# AutoPad-R3-RevA.net
KiCad netlist of a schematic drawn in EAGLE
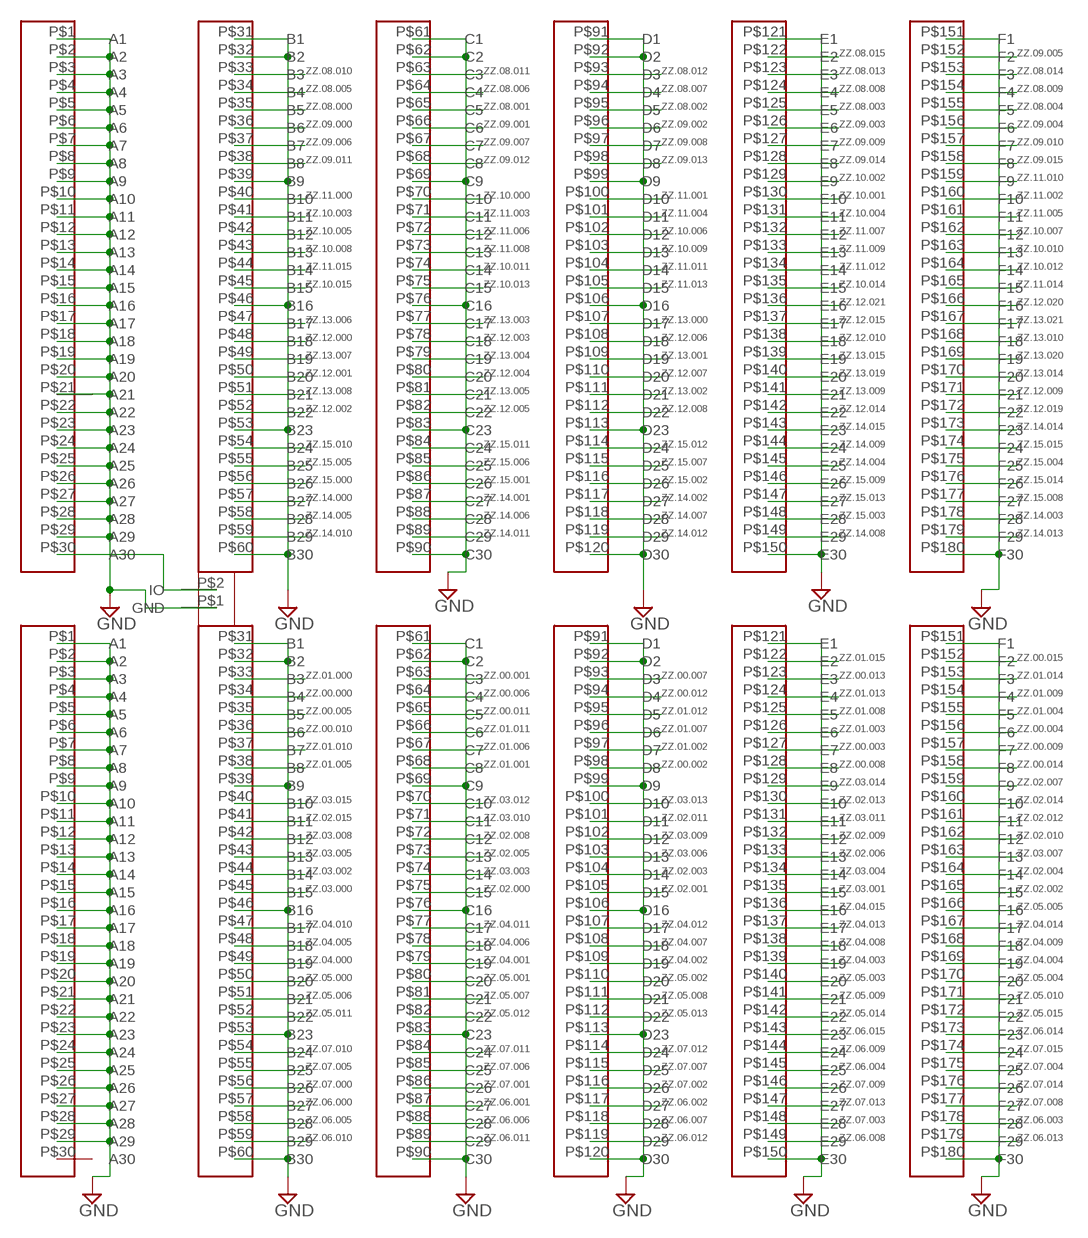
[diagram p0: schematic, sheet 1]
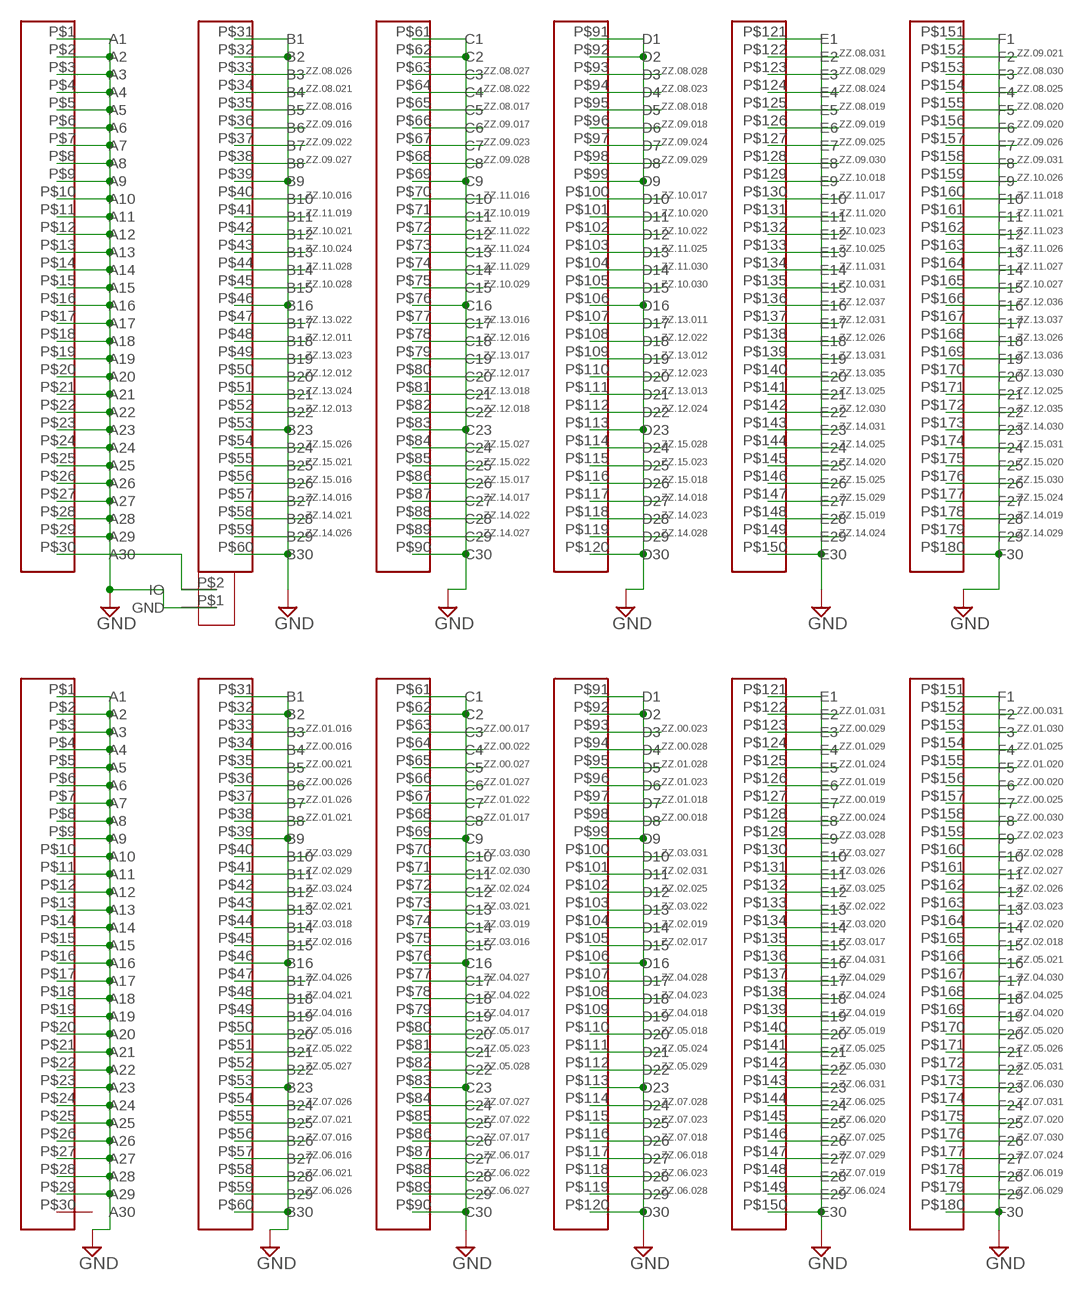
[diagram p1: schematic, sheet 2]
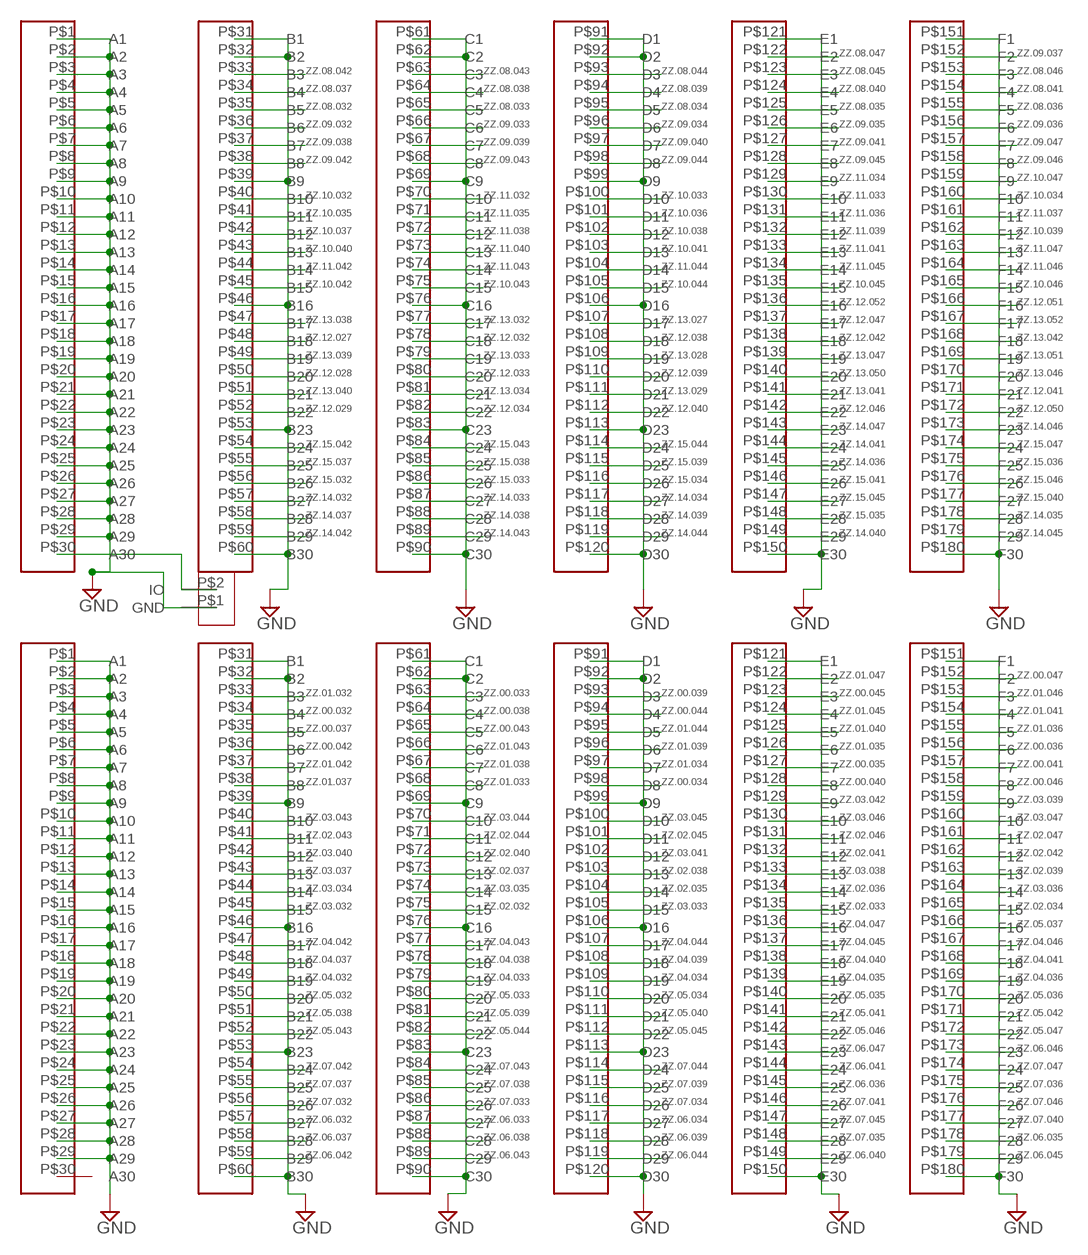
[diagram p2: schematic, sheet 3]
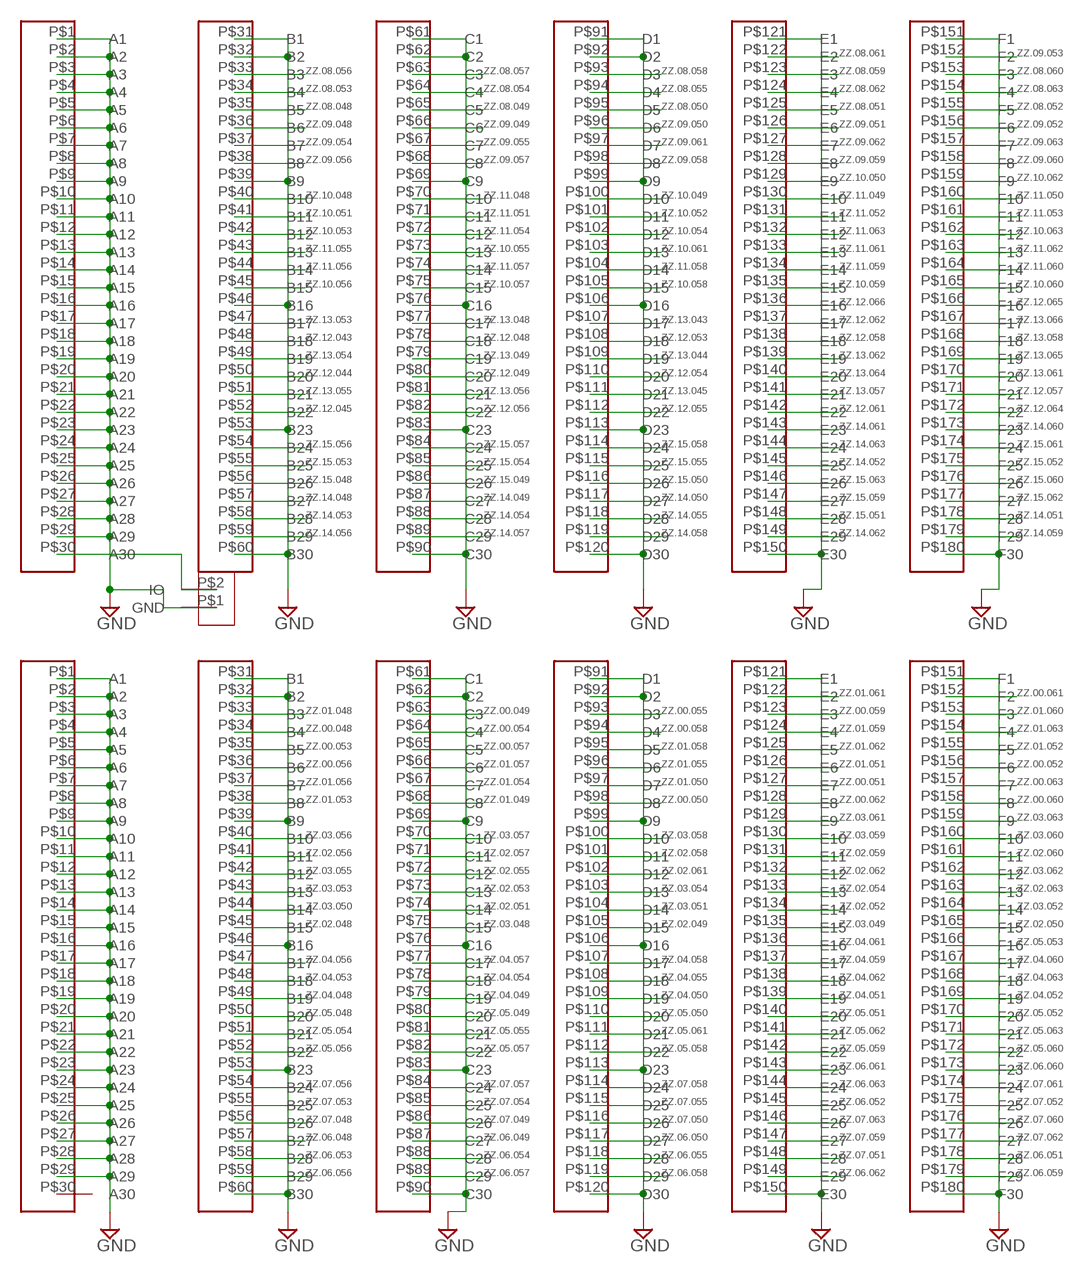
[diagram p3: schematic, sheet 4]
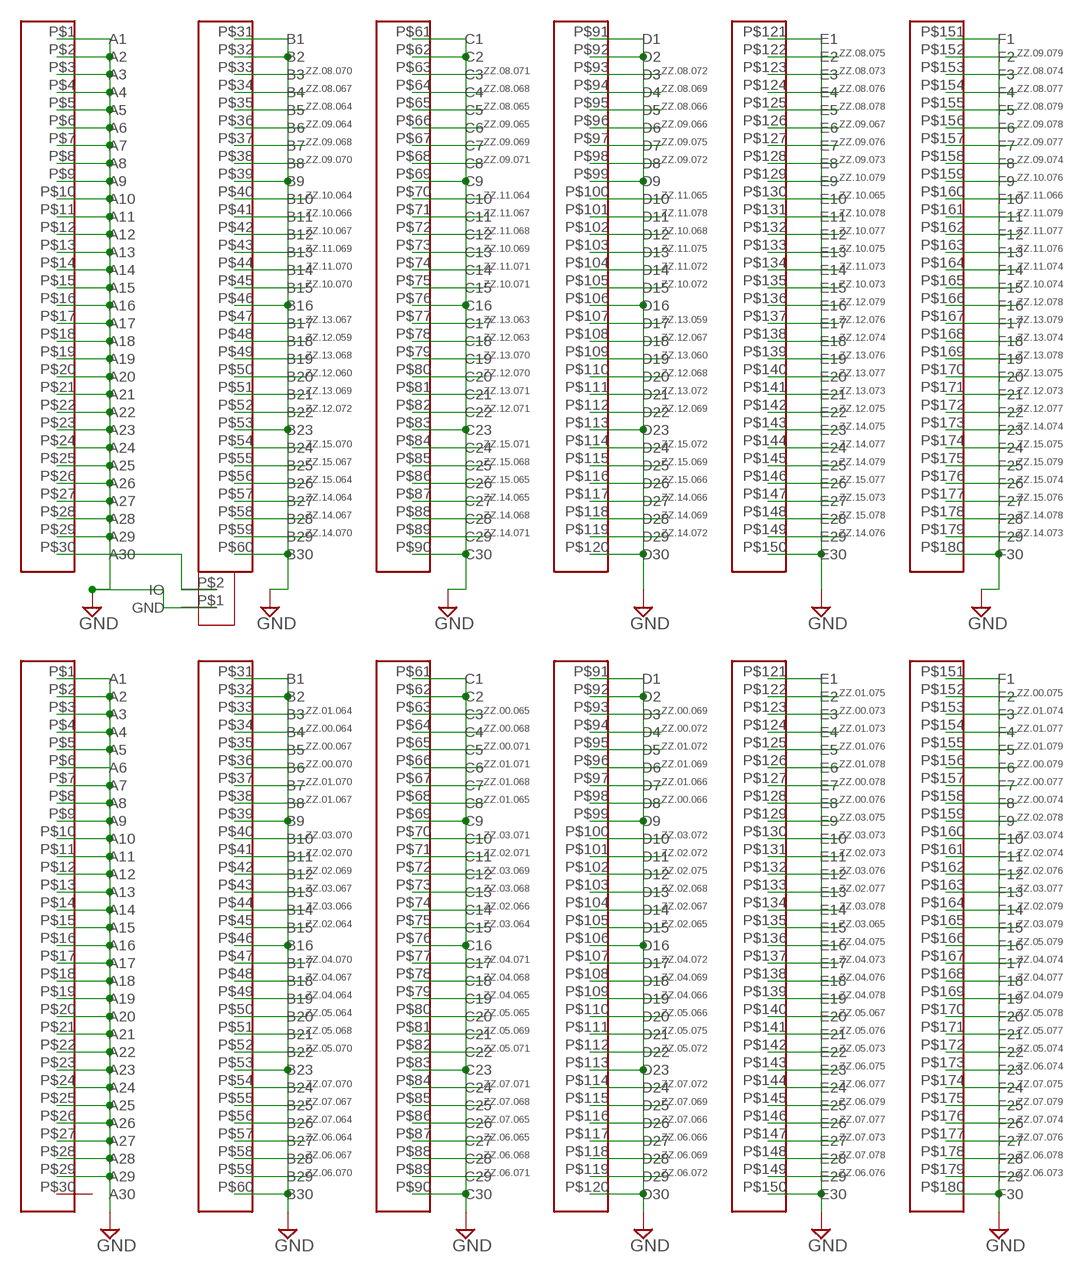
[diagram p4: schematic, sheet 5]
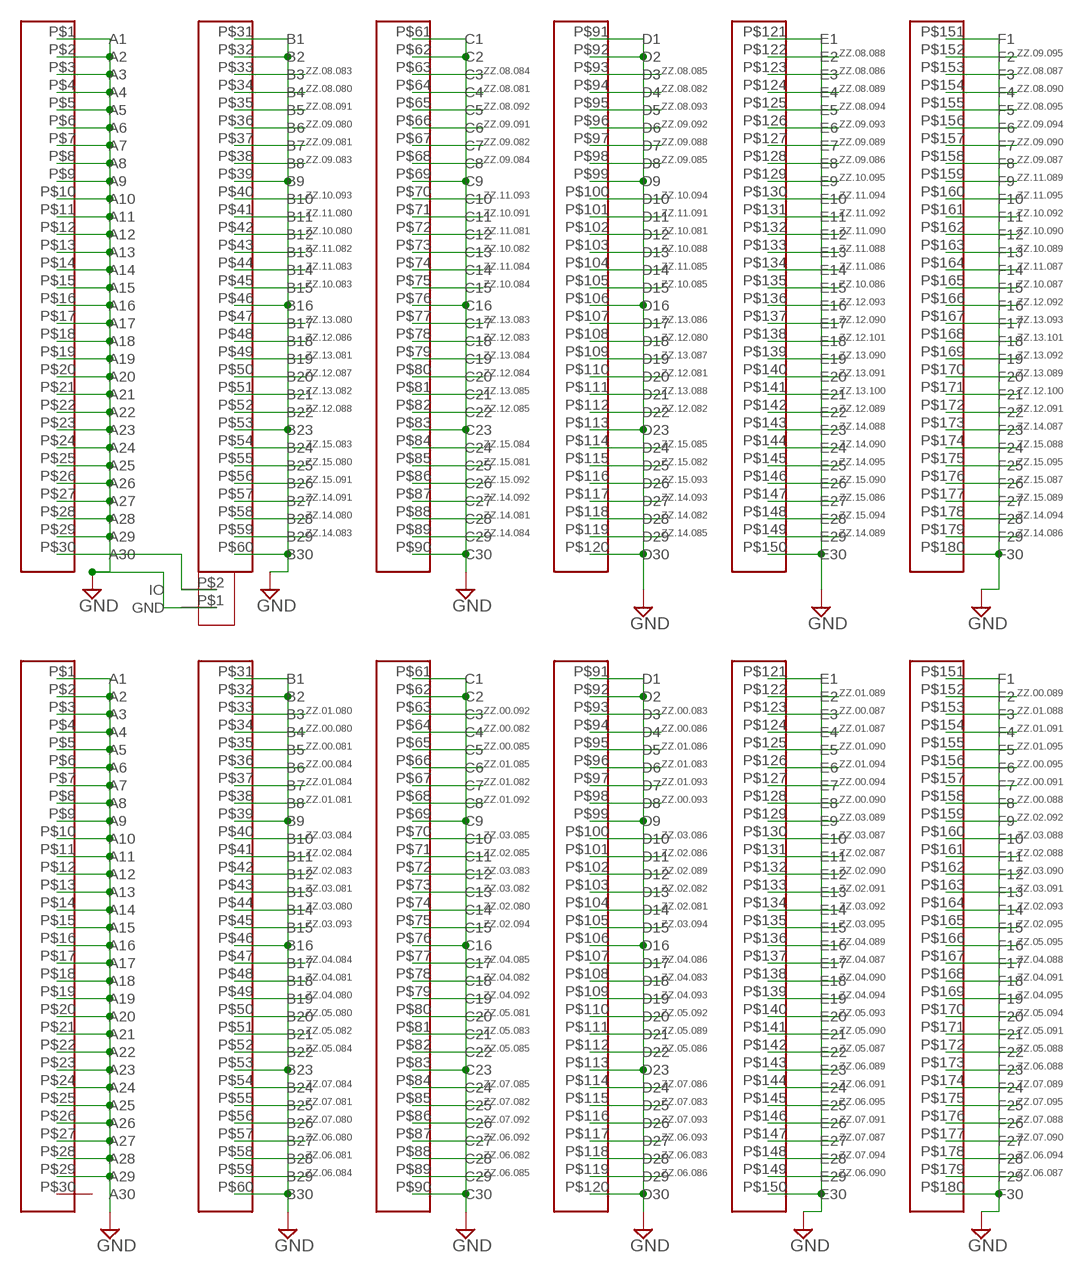
[diagram p5: schematic, sheet 6]
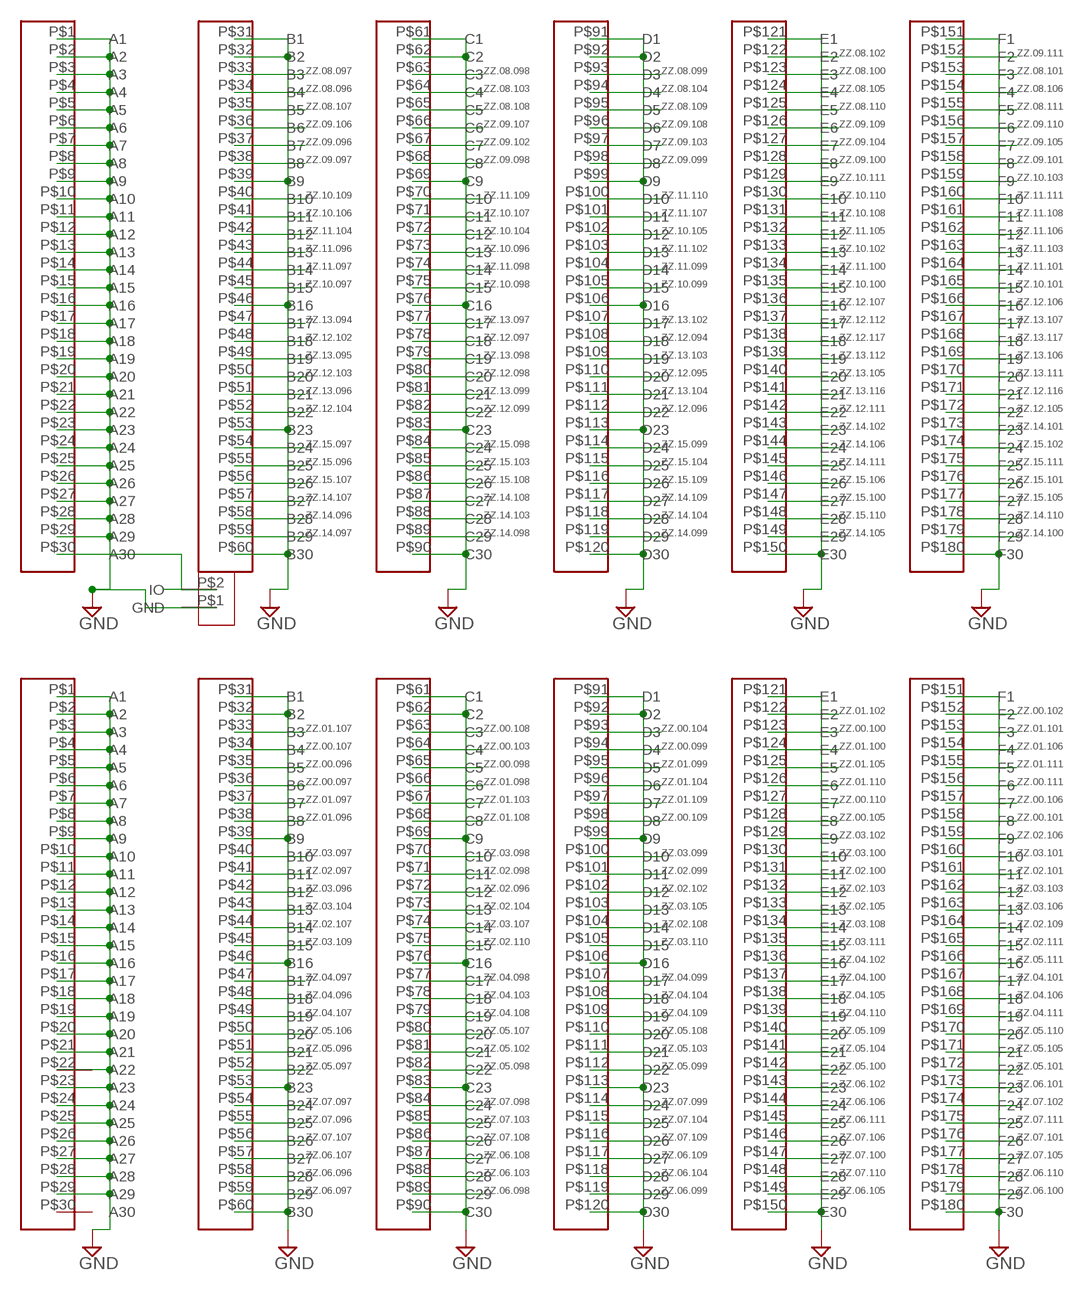
[diagram p6: schematic, sheet 7]
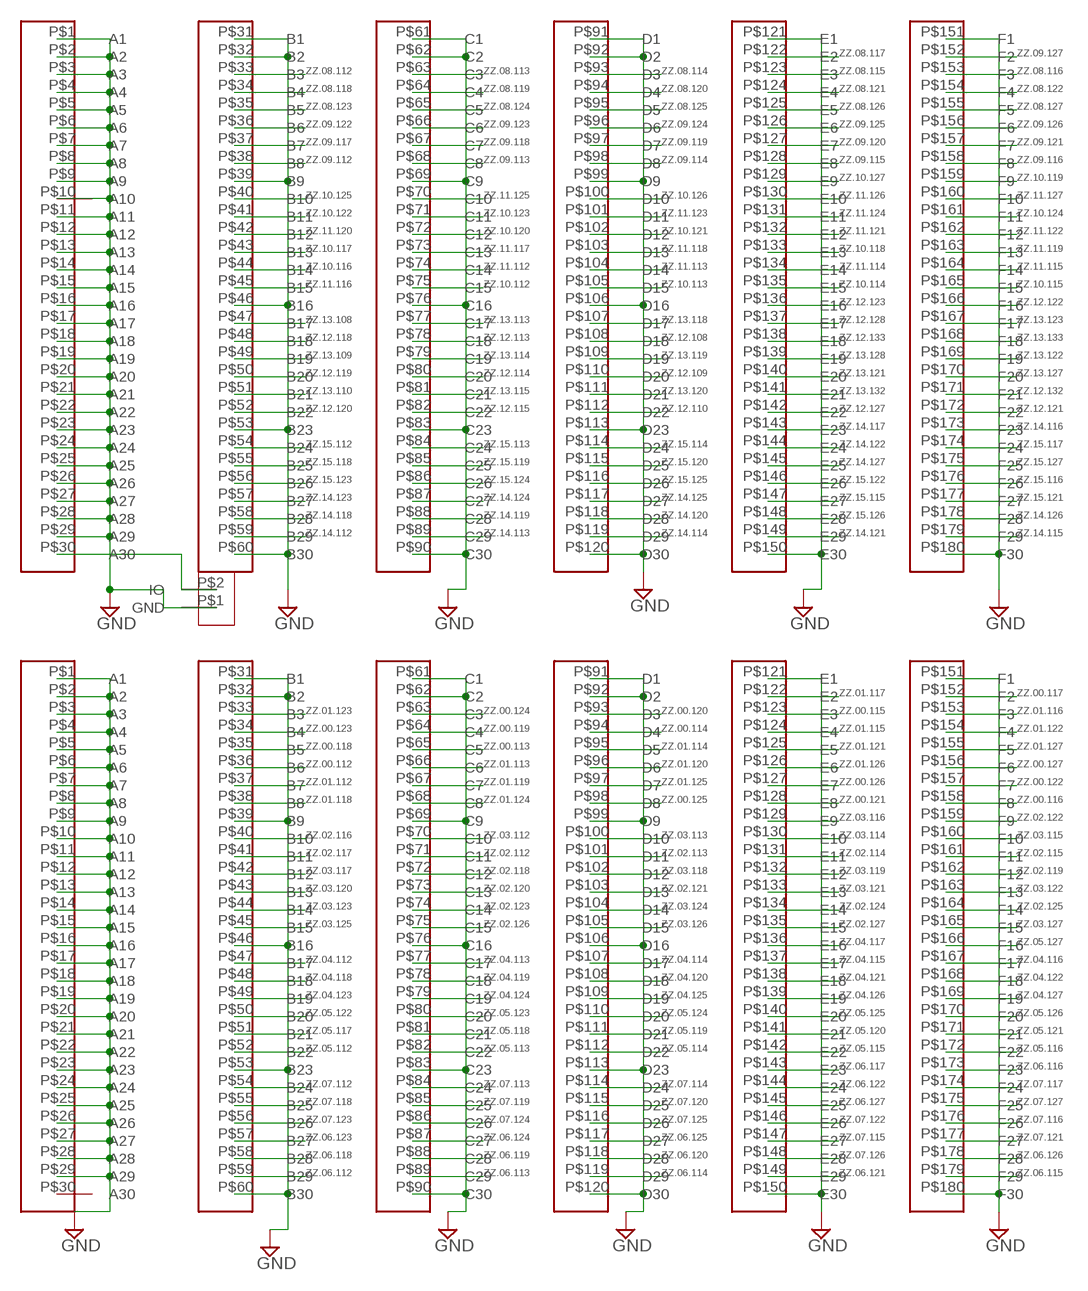
[diagram p7: schematic, sheet 8]
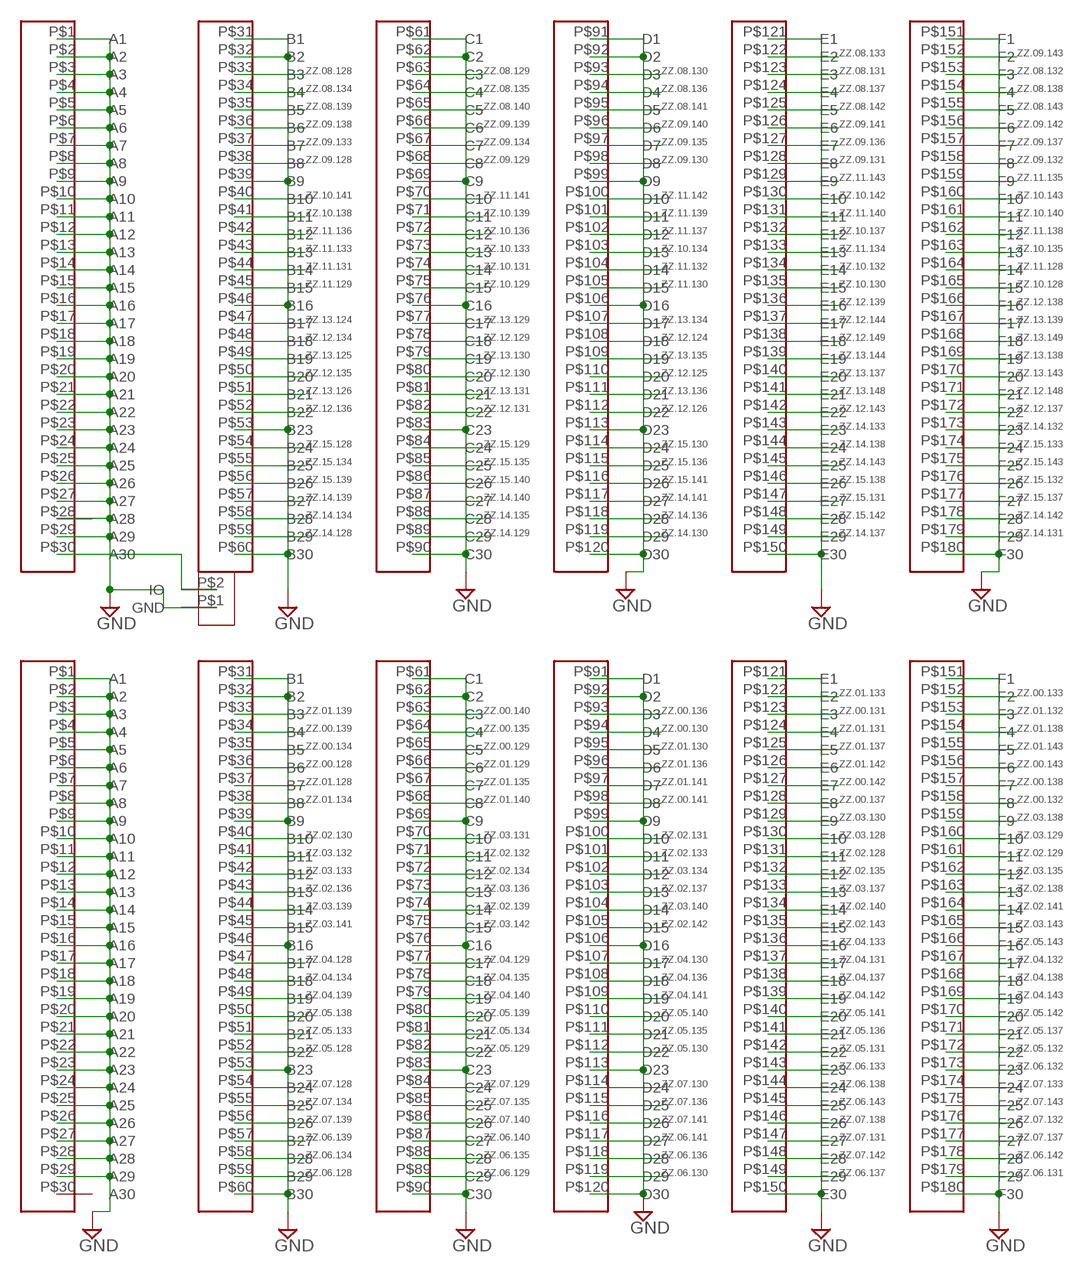
[diagram p8: schematic, sheet 9]
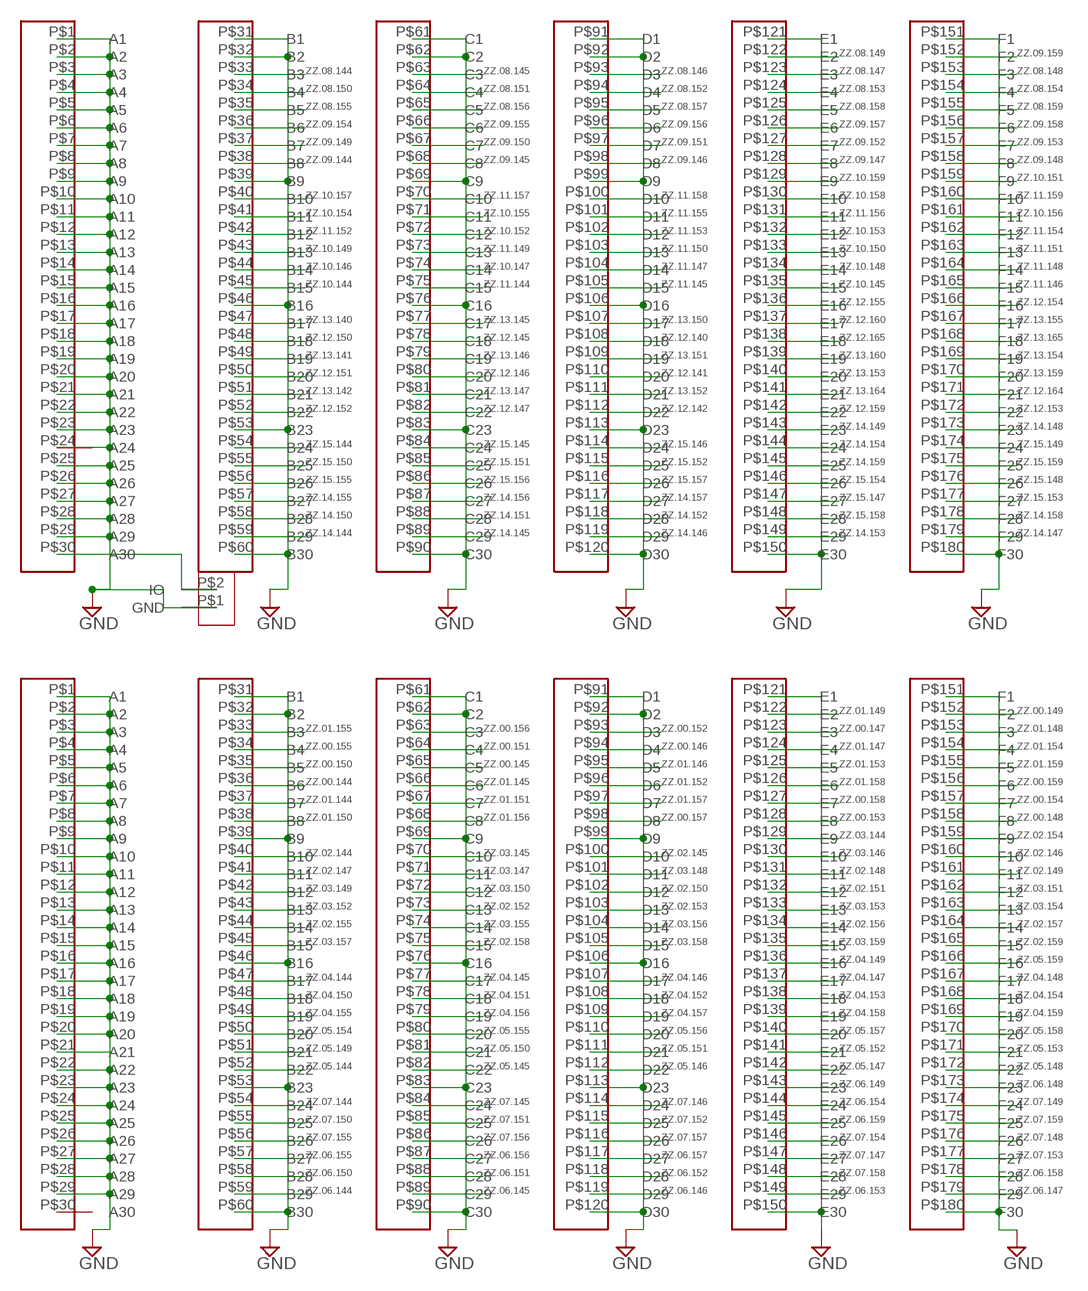
[diagram p9: schematic, sheet 10]
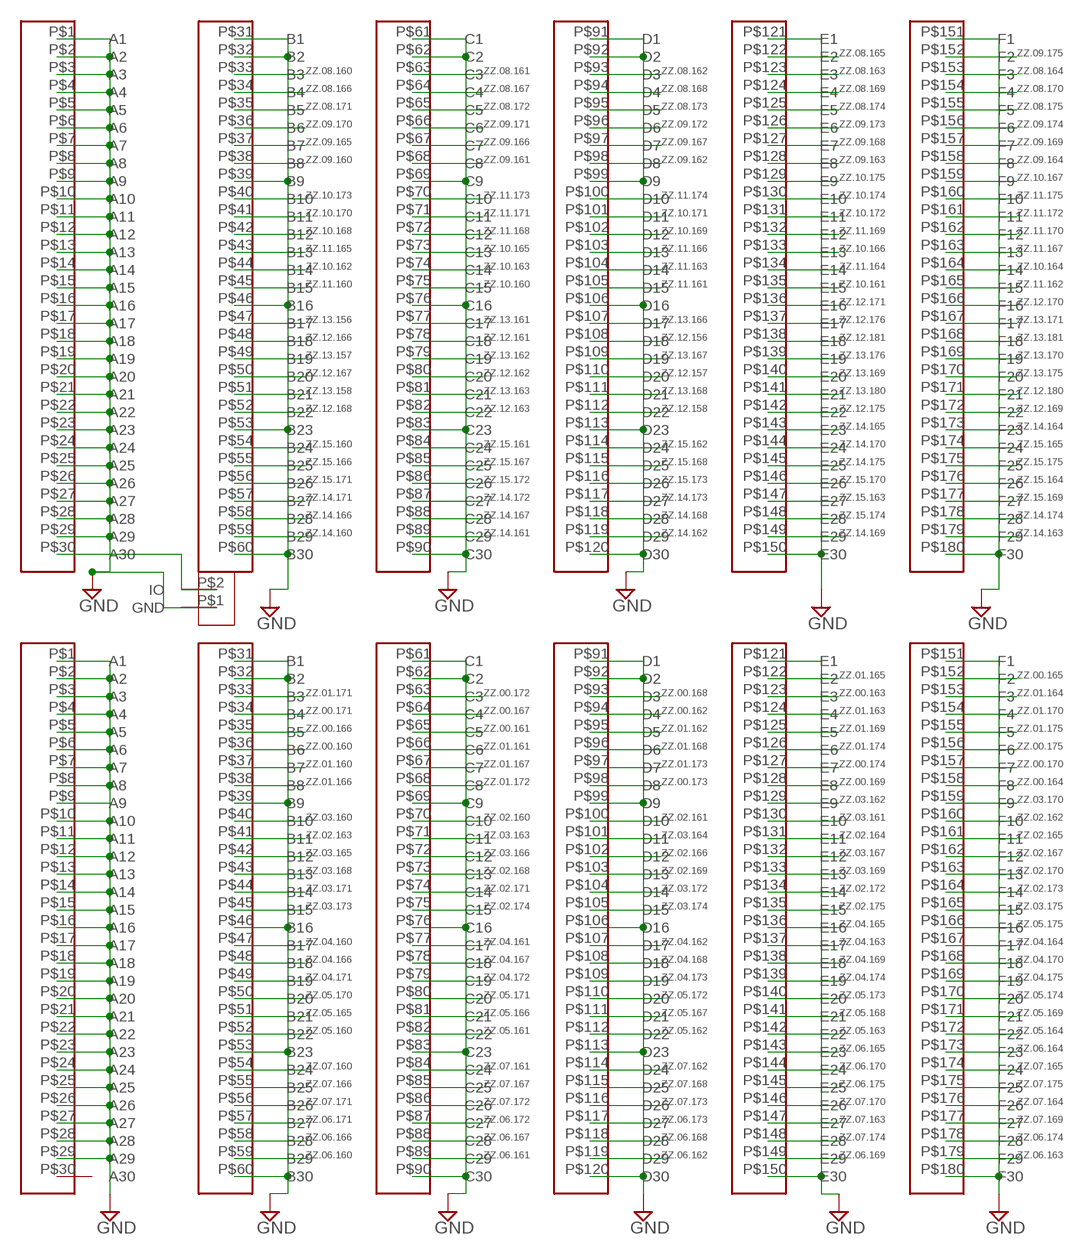
[diagram p10: schematic, sheet 11]
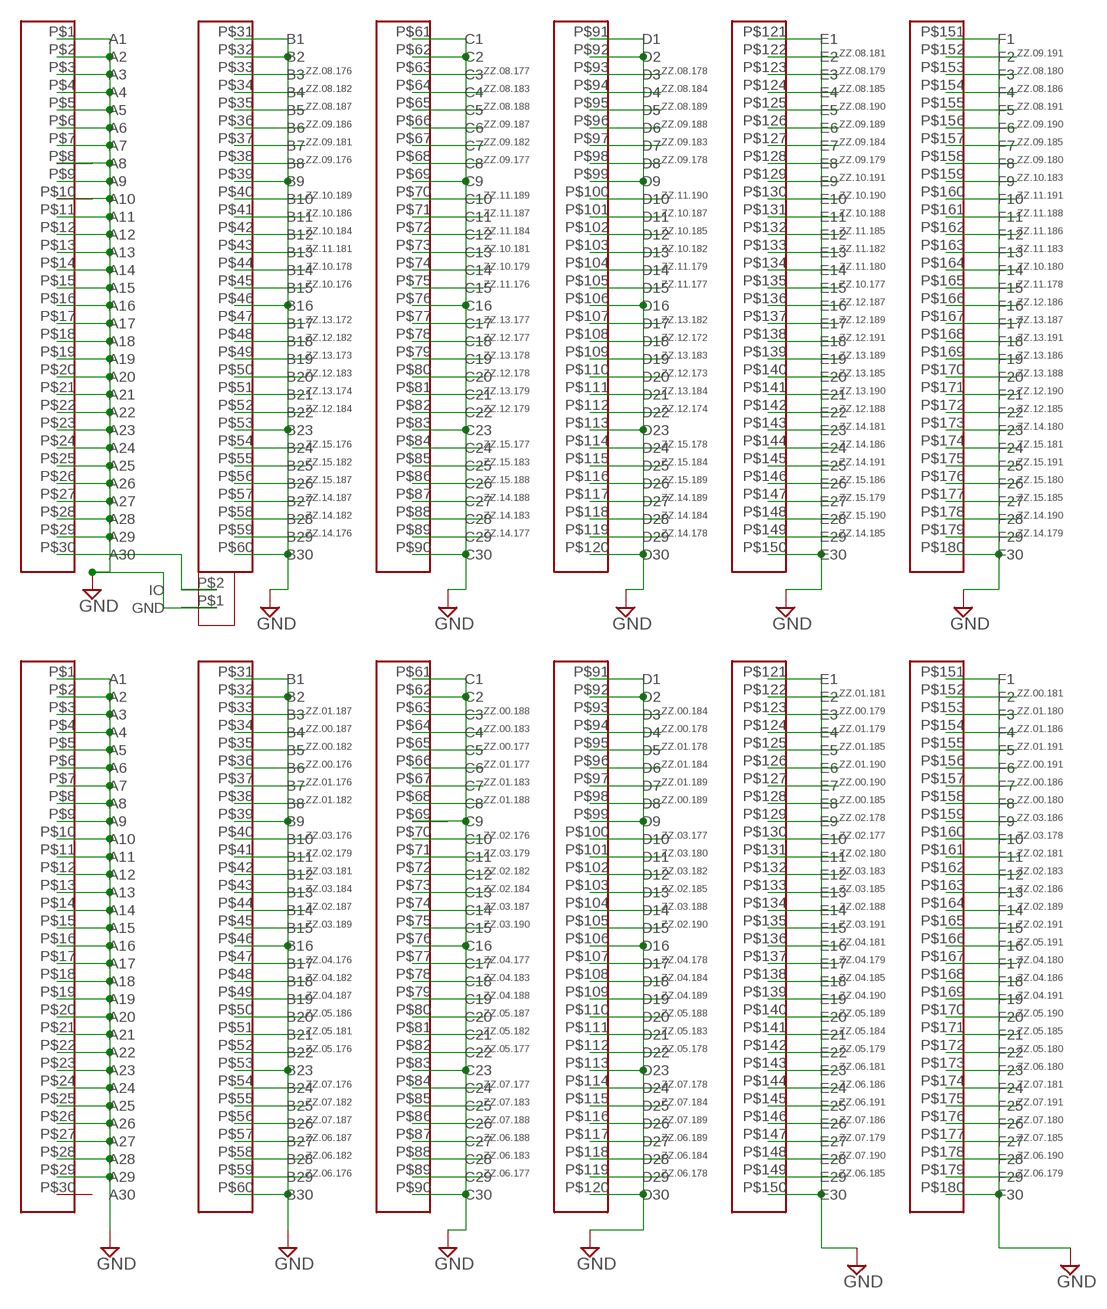
[diagram p11: schematic, sheet 12]

(export (version "E")
  (design (tool "Eeschema 10.0.6"))
  (components
    (comp (ref "U$5")
      (value "SEAM-30-02.0-L-06-1-A-K-TR")
      (footprint "eagle-import:SEAM-30-02.0-L-06-1-A-K-TR")
      (libsource (lib "eagle-import") (part "SEAM-30-02.0-L-06-1-A-K-TR"))
    )
    (comp (ref "U$6")
      (value "SEAM-30-02.0-L-06-1-A-K-TR")
      (footprint "eagle-import:SEAM-30-02.0-L-06-1-A-K-TR")
      (libsource (lib "eagle-import") (part "SEAM-30-02.0-L-06-1-A-K-TR"))
    )
    (comp (ref "U$27")
      (value "DS2431")
      (footprint "eagle-import:SD2431")
      (libsource (lib "eagle-import") (part "DS2431"))
    )
    (comp (ref "U$9")
      (value "SEAM-30-02.0-L-06-1-A-K-TR")
      (footprint "eagle-import:SEAM-30-02.0-L-06-1-A-K-TR")
      (libsource (lib "eagle-import") (part "SEAM-30-02.0-L-06-1-A-K-TR"))
    )
    (comp (ref "U$10")
      (value "SEAM-30-02.0-L-06-1-A-K-TR")
      (footprint "eagle-import:SEAM-30-02.0-L-06-1-A-K-TR")
      (libsource (lib "eagle-import") (part "SEAM-30-02.0-L-06-1-A-K-TR"))
    )
    (comp (ref "U$29")
      (value "DS2431")
      (footprint "eagle-import:SD2431")
      (libsource (lib "eagle-import") (part "DS2431"))
    )
    (comp (ref "U$13")
      (value "SEAM-30-02.0-L-06-1-A-K-TR")
      (footprint "eagle-import:SEAM-30-02.0-L-06-1-A-K-TR")
      (libsource (lib "eagle-import") (part "SEAM-30-02.0-L-06-1-A-K-TR"))
    )
    (comp (ref "U$14")
      (value "SEAM-30-02.0-L-06-1-A-K-TR")
      (footprint "eagle-import:SEAM-30-02.0-L-06-1-A-K-TR")
      (libsource (lib "eagle-import") (part "SEAM-30-02.0-L-06-1-A-K-TR"))
    )
    (comp (ref "U$31")
      (value "DS2431")
      (footprint "eagle-import:SD2431")
      (libsource (lib "eagle-import") (part "DS2431"))
    )
    (comp (ref "U$3")
      (value "SEAM-30-02.0-L-06-1-A-K-TR")
      (footprint "eagle-import:SEAM-30-02.0-L-06-1-A-K-TR")
      (libsource (lib "eagle-import") (part "SEAM-30-02.0-L-06-1-A-K-TR"))
    )
    (comp (ref "U$4")
      (value "SEAM-30-02.0-L-06-1-A-K-TR")
      (footprint "eagle-import:SEAM-30-02.0-L-06-1-A-K-TR")
      (libsource (lib "eagle-import") (part "SEAM-30-02.0-L-06-1-A-K-TR"))
    )
    (comp (ref "U$26")
      (value "DS2431")
      (footprint "eagle-import:SD2431")
      (libsource (lib "eagle-import") (part "DS2431"))
    )
    (comp (ref "U$21")
      (value "SEAM-30-02.0-L-06-1-A-K-TR")
      (footprint "eagle-import:SEAM-30-02.0-L-06-1-A-K-TR")
      (libsource (lib "eagle-import") (part "SEAM-30-02.0-L-06-1-A-K-TR"))
    )
    (comp (ref "U$22")
      (value "SEAM-30-02.0-L-06-1-A-K-TR")
      (footprint "eagle-import:SEAM-30-02.0-L-06-1-A-K-TR")
      (libsource (lib "eagle-import") (part "SEAM-30-02.0-L-06-1-A-K-TR"))
    )
    (comp (ref "U$35")
      (value "DS2431")
      (footprint "eagle-import:SD2431")
      (libsource (lib "eagle-import") (part "DS2431"))
    )
    (comp (ref "U$17")
      (value "SEAM-30-02.0-L-06-1-A-K-TR")
      (footprint "eagle-import:SEAM-30-02.0-L-06-1-A-K-TR")
      (libsource (lib "eagle-import") (part "SEAM-30-02.0-L-06-1-A-K-TR"))
    )
    (comp (ref "U$18")
      (value "SEAM-30-02.0-L-06-1-A-K-TR")
      (footprint "eagle-import:SEAM-30-02.0-L-06-1-A-K-TR")
      (libsource (lib "eagle-import") (part "SEAM-30-02.0-L-06-1-A-K-TR"))
    )
    (comp (ref "U$33")
      (value "DS2431")
      (footprint "eagle-import:SD2431")
      (libsource (lib "eagle-import") (part "DS2431"))
    )
    (comp (ref "U$1")
      (value "SEAM-30-02.0-L-06-1-A-K-TR")
      (footprint "eagle-import:SEAM-30-02.0-L-06-1-A-K-TR")
      (libsource (lib "eagle-import") (part "SEAM-30-02.0-L-06-1-A-K-TR"))
    )
    (comp (ref "U$2")
      (value "SEAM-30-02.0-L-06-1-A-K-TR")
      (footprint "eagle-import:SEAM-30-02.0-L-06-1-A-K-TR")
      (libsource (lib "eagle-import") (part "SEAM-30-02.0-L-06-1-A-K-TR"))
    )
    (comp (ref "U$25")
      (value "DS2431")
      (footprint "eagle-import:SD2431")
      (libsource (lib "eagle-import") (part "DS2431"))
    )
    (comp (ref "U$19")
      (value "SEAM-30-02.0-L-06-1-A-K-TR")
      (footprint "eagle-import:SEAM-30-02.0-L-06-1-A-K-TR")
      (libsource (lib "eagle-import") (part "SEAM-30-02.0-L-06-1-A-K-TR"))
    )
    (comp (ref "U$20")
      (value "SEAM-30-02.0-L-06-1-A-K-TR")
      (footprint "eagle-import:SEAM-30-02.0-L-06-1-A-K-TR")
      (libsource (lib "eagle-import") (part "SEAM-30-02.0-L-06-1-A-K-TR"))
    )
    (comp (ref "U$34")
      (value "DS2431")
      (footprint "eagle-import:SD2431")
      (libsource (lib "eagle-import") (part "DS2431"))
    )
    (comp (ref "U$23")
      (value "SEAM-30-02.0-L-06-1-A-K-TR")
      (footprint "eagle-import:SEAM-30-02.0-L-06-1-A-K-TR")
      (libsource (lib "eagle-import") (part "SEAM-30-02.0-L-06-1-A-K-TR"))
    )
    (comp (ref "U$24")
      (value "SEAM-30-02.0-L-06-1-A-K-TR")
      (footprint "eagle-import:SEAM-30-02.0-L-06-1-A-K-TR")
      (libsource (lib "eagle-import") (part "SEAM-30-02.0-L-06-1-A-K-TR"))
    )
    (comp (ref "U$36")
      (value "DS2431")
      (footprint "eagle-import:SD2431")
      (libsource (lib "eagle-import") (part "DS2431"))
    )
    (comp (ref "U$11")
      (value "SEAM-30-02.0-L-06-1-A-K-TR")
      (footprint "eagle-import:SEAM-30-02.0-L-06-1-A-K-TR")
      (libsource (lib "eagle-import") (part "SEAM-30-02.0-L-06-1-A-K-TR"))
    )
    (comp (ref "U$12")
      (value "SEAM-30-02.0-L-06-1-A-K-TR")
      (footprint "eagle-import:SEAM-30-02.0-L-06-1-A-K-TR")
      (libsource (lib "eagle-import") (part "SEAM-30-02.0-L-06-1-A-K-TR"))
    )
    (comp (ref "U$30")
      (value "DS2431")
      (footprint "eagle-import:SD2431")
      (libsource (lib "eagle-import") (part "DS2431"))
    )
    (comp (ref "U$15")
      (value "SEAM-30-02.0-L-06-1-A-K-TR")
      (footprint "eagle-import:SEAM-30-02.0-L-06-1-A-K-TR")
      (libsource (lib "eagle-import") (part "SEAM-30-02.0-L-06-1-A-K-TR"))
    )
    (comp (ref "U$16")
      (value "SEAM-30-02.0-L-06-1-A-K-TR")
      (footprint "eagle-import:SEAM-30-02.0-L-06-1-A-K-TR")
      (libsource (lib "eagle-import") (part "SEAM-30-02.0-L-06-1-A-K-TR"))
    )
    (comp (ref "U$32")
      (value "DS2431")
      (footprint "eagle-import:SD2431")
      (libsource (lib "eagle-import") (part "DS2431"))
    )
    (comp (ref "U$7")
      (value "SEAM-30-02.0-L-06-1-A-K-TR")
      (footprint "eagle-import:SEAM-30-02.0-L-06-1-A-K-TR")
      (libsource (lib "eagle-import") (part "SEAM-30-02.0-L-06-1-A-K-TR"))
    )
    (comp (ref "U$8")
      (value "SEAM-30-02.0-L-06-1-A-K-TR")
      (footprint "eagle-import:SEAM-30-02.0-L-06-1-A-K-TR")
      (libsource (lib "eagle-import") (part "SEAM-30-02.0-L-06-1-A-K-TR"))
    )
    (comp (ref "U$28")
      (value "DS2431")
      (footprint "eagle-import:SD2431")
      (libsource (lib "eagle-import") (part "DS2431"))
    )
  )
  (nets
    (net (code "1") (name "GND") (class "Default")
      (node (ref "U$1") (pin "P$1") (pinfunction "A1_P$1") (pintype "bidirectional"))
      (node (ref "U$1") (pin "P$10") (pinfunction "A10_P$10") (pintype "bidirectional"))
      (node (ref "U$1") (pin "P$106") (pinfunction "D16_P$106") (pintype "bidirectional"))
      (node (ref "U$1") (pin "P$11") (pinfunction "A11_P$11") (pintype "bidirectional"))
      (node (ref "U$1") (pin "P$113") (pinfunction "D23_P$113") (pintype "bidirectional"))
      (node (ref "U$1") (pin "P$12") (pinfunction "A12_P$12") (pintype "bidirectional"))
      (node (ref "U$1") (pin "P$120") (pinfunction "D30_P$120") (pintype "bidirectional"))
      (node (ref "U$1") (pin "P$121") (pinfunction "E1_P$121") (pintype "bidirectional"))
      (node (ref "U$1") (pin "P$13") (pinfunction "A13_P$13") (pintype "bidirectional"))
      (node (ref "U$1") (pin "P$14") (pinfunction "A14_P$14") (pintype "bidirectional"))
      (node (ref "U$1") (pin "P$15") (pinfunction "A15_P$15") (pintype "bidirectional"))
      (node (ref "U$1") (pin "P$150") (pinfunction "E30_P$150") (pintype "bidirectional"))
      (node (ref "U$1") (pin "P$151") (pinfunction "F1_P$151") (pintype "bidirectional"))
      (node (ref "U$1") (pin "P$16") (pinfunction "A16_P$16") (pintype "bidirectional"))
      (node (ref "U$1") (pin "P$17") (pinfunction "A17_P$17") (pintype "bidirectional"))
      (node (ref "U$1") (pin "P$18") (pinfunction "A18_P$18") (pintype "bidirectional"))
      (node (ref "U$1") (pin "P$180") (pinfunction "F30_P$180") (pintype "bidirectional"))
      (node (ref "U$1") (pin "P$19") (pinfunction "A19_P$19") (pintype "bidirectional"))
      (node (ref "U$1") (pin "P$2") (pinfunction "A2_P$2") (pintype "bidirectional"))
      (node (ref "U$1") (pin "P$20") (pinfunction "A20_P$20") (pintype "bidirectional"))
      (node (ref "U$1") (pin "P$21") (pinfunction "A21_P$21") (pintype "bidirectional"))
      (node (ref "U$1") (pin "P$22") (pinfunction "A22_P$22") (pintype "bidirectional"))
      (node (ref "U$1") (pin "P$23") (pinfunction "A23_P$23") (pintype "bidirectional"))
      (node (ref "U$1") (pin "P$24") (pinfunction "A24_P$24") (pintype "bidirectional"))
      (node (ref "U$1") (pin "P$25") (pinfunction "A25_P$25") (pintype "bidirectional"))
      (node (ref "U$1") (pin "P$26") (pinfunction "A26_P$26") (pintype "bidirectional"))
      (node (ref "U$1") (pin "P$27") (pinfunction "A27_P$27") (pintype "bidirectional"))
      (node (ref "U$1") (pin "P$28") (pinfunction "A28_P$28") (pintype "bidirectional"))
      (node (ref "U$1") (pin "P$29") (pinfunction "A29_P$29") (pintype "bidirectional"))
      (node (ref "U$1") (pin "P$3") (pinfunction "A3_P$3") (pintype "bidirectional"))
      (node (ref "U$1") (pin "P$31") (pinfunction "B1_P$31") (pintype "bidirectional"))
      (node (ref "U$1") (pin "P$32") (pinfunction "B2_P$32") (pintype "bidirectional"))
      (node (ref "U$1") (pin "P$39") (pinfunction "B9_P$39") (pintype "bidirectional"))
      (node (ref "U$1") (pin "P$4") (pinfunction "A4_P$4") (pintype "bidirectional"))
      (node (ref "U$1") (pin "P$46") (pinfunction "B16_P$46") (pintype "bidirectional"))
      (node (ref "U$1") (pin "P$5") (pinfunction "A5_P$5") (pintype "bidirectional"))
      (node (ref "U$1") (pin "P$53") (pinfunction "B23_P$53") (pintype "bidirectional"))
      (node (ref "U$1") (pin "P$6") (pinfunction "A6_P$6") (pintype "bidirectional"))
      (node (ref "U$1") (pin "P$60") (pinfunction "B30_P$60") (pintype "bidirectional"))
      (node (ref "U$1") (pin "P$61") (pinfunction "C1_P$61") (pintype "bidirectional"))
      (node (ref "U$1") (pin "P$62") (pinfunction "C2_P$62") (pintype "bidirectional"))
      (node (ref "U$1") (pin "P$69") (pinfunction "C9_P$69") (pintype "bidirectional"))
      (node (ref "U$1") (pin "P$7") (pinfunction "A7_P$7") (pintype "bidirectional"))
      (node (ref "U$1") (pin "P$76") (pinfunction "C16_P$76") (pintype "bidirectional"))
      (node (ref "U$1") (pin "P$8") (pinfunction "A8_P$8") (pintype "bidirectional"))
      (node (ref "U$1") (pin "P$83") (pinfunction "C23_P$83") (pintype "bidirectional"))
      (node (ref "U$1") (pin "P$9") (pinfunction "A9_P$9") (pintype "bidirectional"))
      (node (ref "U$1") (pin "P$90") (pinfunction "C30_P$90") (pintype "bidirectional"))
      (node (ref "U$1") (pin "P$91") (pinfunction "D1_P$91") (pintype "bidirectional"))
      (node (ref "U$1") (pin "P$92") (pinfunction "D2_P$92") (pintype "bidirectional"))
      (node (ref "U$1") (pin "P$99") (pinfunction "D9_P$99") (pintype "bidirectional"))
      (node (ref "U$10") (pin "P$1") (pinfunction "A1_P$1") (pintype "bidirectional"))
      (node (ref "U$10") (pin "P$10") (pinfunction "A10_P$10") (pintype "bidirectional"))
      (node (ref "U$10") (pin "P$106") (pinfunction "D16_P$106") (pintype "bidirectional"))
      (node (ref "U$10") (pin "P$11") (pinfunction "A11_P$11") (pintype "bidirectional"))
      (node (ref "U$10") (pin "P$113") (pinfunction "D23_P$113") (pintype "bidirectional"))
      (node (ref "U$10") (pin "P$12") (pinfunction "A12_P$12") (pintype "bidirectional"))
      (node (ref "U$10") (pin "P$120") (pinfunction "D30_P$120") (pintype "bidirectional"))
      (node (ref "U$10") (pin "P$121") (pinfunction "E1_P$121") (pintype "bidirectional"))
      (node (ref "U$10") (pin "P$13") (pinfunction "A13_P$13") (pintype "bidirectional"))
      (node (ref "U$10") (pin "P$14") (pinfunction "A14_P$14") (pintype "bidirectional"))
      (node (ref "U$10") (pin "P$15") (pinfunction "A15_P$15") (pintype "bidirectional"))
      (node (ref "U$10") (pin "P$150") (pinfunction "E30_P$150") (pintype "bidirectional"))
      (node (ref "U$10") (pin "P$151") (pinfunction "F1_P$151") (pintype "bidirectional"))
      (node (ref "U$10") (pin "P$16") (pinfunction "A16_P$16") (pintype "bidirectional"))
      (node (ref "U$10") (pin "P$17") (pinfunction "A17_P$17") (pintype "bidirectional"))
      (node (ref "U$10") (pin "P$18") (pinfunction "A18_P$18") (pintype "bidirectional"))
      (node (ref "U$10") (pin "P$180") (pinfunction "F30_P$180") (pintype "bidirectional"))
      (node (ref "U$10") (pin "P$19") (pinfunction "A19_P$19") (pintype "bidirectional"))
      (node (ref "U$10") (pin "P$2") (pinfunction "A2_P$2") (pintype "bidirectional"))
      (node (ref "U$10") (pin "P$20") (pinfunction "A20_P$20") (pintype "bidirectional"))
      (node (ref "U$10") (pin "P$21") (pinfunction "A21_P$21") (pintype "bidirectional"))
      (node (ref "U$10") (pin "P$22") (pinfunction "A22_P$22") (pintype "bidirectional"))
      (node (ref "U$10") (pin "P$23") (pinfunction "A23_P$23") (pintype "bidirectional"))
      (node (ref "U$10") (pin "P$24") (pinfunction "A24_P$24") (pintype "bidirectional"))
      (node (ref "U$10") (pin "P$25") (pinfunction "A25_P$25") (pintype "bidirectional"))
      (node (ref "U$10") (pin "P$26") (pinfunction "A26_P$26") (pintype "bidirectional"))
      (node (ref "U$10") (pin "P$27") (pinfunction "A27_P$27") (pintype "bidirectional"))
      (node (ref "U$10") (pin "P$28") (pinfunction "A28_P$28") (pintype "bidirectional"))
      (node (ref "U$10") (pin "P$29") (pinfunction "A29_P$29") (pintype "bidirectional"))
      (node (ref "U$10") (pin "P$3") (pinfunction "A3_P$3") (pintype "bidirectional"))
      (node (ref "U$10") (pin "P$31") (pinfunction "B1_P$31") (pintype "bidirectional"))
      (node (ref "U$10") (pin "P$32") (pinfunction "B2_P$32") (pintype "bidirectional"))
      (node (ref "U$10") (pin "P$39") (pinfunction "B9_P$39") (pintype "bidirectional"))
      (node (ref "U$10") (pin "P$4") (pinfunction "A4_P$4") (pintype "bidirectional"))
      (node (ref "U$10") (pin "P$46") (pinfunction "B16_P$46") (pintype "bidirectional"))
      (node (ref "U$10") (pin "P$5") (pinfunction "A5_P$5") (pintype "bidirectional"))
      (node (ref "U$10") (pin "P$53") (pinfunction "B23_P$53") (pintype "bidirectional"))
      (node (ref "U$10") (pin "P$6") (pinfunction "A6_P$6") (pintype "bidirectional"))
      (node (ref "U$10") (pin "P$60") (pinfunction "B30_P$60") (pintype "bidirectional"))
      (node (ref "U$10") (pin "P$61") (pinfunction "C1_P$61") (pintype "bidirectional"))
      (node (ref "U$10") (pin "P$62") (pinfunction "C2_P$62") (pintype "bidirectional"))
      (node (ref "U$10") (pin "P$69") (pinfunction "C9_P$69") (pintype "bidirectional"))
      (node (ref "U$10") (pin "P$7") (pinfunction "A7_P$7") (pintype "bidirectional"))
      (node (ref "U$10") (pin "P$76") (pinfunction "C16_P$76") (pintype "bidirectional"))
      (node (ref "U$10") (pin "P$8") (pinfunction "A8_P$8") (pintype "bidirectional"))
      (node (ref "U$10") (pin "P$83") (pinfunction "C23_P$83") (pintype "bidirectional"))
      (node (ref "U$10") (pin "P$9") (pinfunction "A9_P$9") (pintype "bidirectional"))
      (node (ref "U$10") (pin "P$90") (pinfunction "C30_P$90") (pintype "bidirectional"))
      (node (ref "U$10") (pin "P$91") (pinfunction "D1_P$91") (pintype "bidirectional"))
      (node (ref "U$10") (pin "P$92") (pinfunction "D2_P$92") (pintype "bidirectional"))
      (node (ref "U$10") (pin "P$99") (pinfunction "D9_P$99") (pintype "bidirectional"))
      (node (ref "U$11") (pin "P$1") (pinfunction "A1_P$1") (pintype "bidirectional"))
      (node (ref "U$11") (pin "P$10") (pinfunction "A10_P$10") (pintype "bidirectional"))
      (node (ref "U$11") (pin "P$106") (pinfunction "D16_P$106") (pintype "bidirectional"))
      (node (ref "U$11") (pin "P$11") (pinfunction "A11_P$11") (pintype "bidirectional"))
      (node (ref "U$11") (pin "P$113") (pinfunction "D23_P$113") (pintype "bidirectional"))
      (node (ref "U$11") (pin "P$12") (pinfunction "A12_P$12") (pintype "bidirectional"))
      (node (ref "U$11") (pin "P$120") (pinfunction "D30_P$120") (pintype "bidirectional"))
      (node (ref "U$11") (pin "P$121") (pinfunction "E1_P$121") (pintype "bidirectional"))
      (node (ref "U$11") (pin "P$13") (pinfunction "A13_P$13") (pintype "bidirectional"))
      (node (ref "U$11") (pin "P$14") (pinfunction "A14_P$14") (pintype "bidirectional"))
      (node (ref "U$11") (pin "P$15") (pinfunction "A15_P$15") (pintype "bidirectional"))
      (node (ref "U$11") (pin "P$150") (pinfunction "E30_P$150") (pintype "bidirectional"))
      (node (ref "U$11") (pin "P$151") (pinfunction "F1_P$151") (pintype "bidirectional"))
      (node (ref "U$11") (pin "P$16") (pinfunction "A16_P$16") (pintype "bidirectional"))
      (node (ref "U$11") (pin "P$17") (pinfunction "A17_P$17") (pintype "bidirectional"))
      (node (ref "U$11") (pin "P$18") (pinfunction "A18_P$18") (pintype "bidirectional"))
      (node (ref "U$11") (pin "P$180") (pinfunction "F30_P$180") (pintype "bidirectional"))
      (node (ref "U$11") (pin "P$19") (pinfunction "A19_P$19") (pintype "bidirectional"))
      (node (ref "U$11") (pin "P$2") (pinfunction "A2_P$2") (pintype "bidirectional"))
      (node (ref "U$11") (pin "P$20") (pinfunction "A20_P$20") (pintype "bidirectional"))
      (node (ref "U$11") (pin "P$21") (pinfunction "A21_P$21") (pintype "bidirectional"))
      (node (ref "U$11") (pin "P$22") (pinfunction "A22_P$22") (pintype "bidirectional"))
      (node (ref "U$11") (pin "P$23") (pinfunction "A23_P$23") (pintype "bidirectional"))
      (node (ref "U$11") (pin "P$24") (pinfunction "A24_P$24") (pintype "bidirectional"))
      (node (ref "U$11") (pin "P$25") (pinfunction "A25_P$25") (pintype "bidirectional"))
      (node (ref "U$11") (pin "P$26") (pinfunction "A26_P$26") (pintype "bidirectional"))
      (node (ref "U$11") (pin "P$27") (pinfunction "A27_P$27") (pintype "bidirectional"))
      (node (ref "U$11") (pin "P$28") (pinfunction "A28_P$28") (pintype "bidirectional"))
      (node (ref "U$11") (pin "P$29") (pinfunction "A29_P$29") (pintype "bidirectional"))
      (node (ref "U$11") (pin "P$3") (pinfunction "A3_P$3") (pintype "bidirectional"))
      (node (ref "U$11") (pin "P$31") (pinfunction "B1_P$31") (pintype "bidirectional"))
      (node (ref "U$11") (pin "P$32") (pinfunction "B2_P$32") (pintype "bidirectional"))
      (node (ref "U$11") (pin "P$39") (pinfunction "B9_P$39") (pintype "bidirectional"))
      (node (ref "U$11") (pin "P$4") (pinfunction "A4_P$4") (pintype "bidirectional"))
      (node (ref "U$11") (pin "P$46") (pinfunction "B16_P$46") (pintype "bidirectional"))
      (node (ref "U$11") (pin "P$5") (pinfunction "A5_P$5") (pintype "bidirectional"))
      (node (ref "U$11") (pin "P$53") (pinfunction "B23_P$53") (pintype "bidirectional"))
      (node (ref "U$11") (pin "P$6") (pinfunction "A6_P$6") (pintype "bidirectional"))
      (node (ref "U$11") (pin "P$60") (pinfunction "B30_P$60") (pintype "bidirectional"))
      (node (ref "U$11") (pin "P$61") (pinfunction "C1_P$61") (pintype "bidirectional"))
      (node (ref "U$11") (pin "P$62") (pinfunction "C2_P$62") (pintype "bidirectional"))
      (node (ref "U$11") (pin "P$69") (pinfunction "C9_P$69") (pintype "bidirectional"))
      (node (ref "U$11") (pin "P$7") (pinfunction "A7_P$7") (pintype "bidirectional"))
      (node (ref "U$11") (pin "P$76") (pinfunction "C16_P$76") (pintype "bidirectional"))
      (node (ref "U$11") (pin "P$8") (pinfunction "A8_P$8") (pintype "bidirectional"))
      (node (ref "U$11") (pin "P$83") (pinfunction "C23_P$83") (pintype "bidirectional"))
      (node (ref "U$11") (pin "P$9") (pinfunction "A9_P$9") (pintype "bidirectional"))
      (node (ref "U$11") (pin "P$90") (pinfunction "C30_P$90") (pintype "bidirectional"))
      (node (ref "U$11") (pin "P$91") (pinfunction "D1_P$91") (pintype "bidirectional"))
      (node (ref "U$11") (pin "P$92") (pinfunction "D2_P$92") (pintype "bidirectional"))
      (node (ref "U$11") (pin "P$99") (pinfunction "D9_P$99") (pintype "bidirectional"))
      (node (ref "U$12") (pin "P$1") (pinfunction "A1_P$1") (pintype "bidirectional"))
      (node (ref "U$12") (pin "P$10") (pinfunction "A10_P$10") (pintype "bidirectional"))
      (node (ref "U$12") (pin "P$106") (pinfunction "D16_P$106") (pintype "bidirectional"))
      (node (ref "U$12") (pin "P$11") (pinfunction "A11_P$11") (pintype "bidirectional"))
      (node (ref "U$12") (pin "P$113") (pinfunction "D23_P$113") (pintype "bidirectional"))
      (node (ref "U$12") (pin "P$12") (pinfunction "A12_P$12") (pintype "bidirectional"))
      (node (ref "U$12") (pin "P$120") (pinfunction "D30_P$120") (pintype "bidirectional"))
      (node (ref "U$12") (pin "P$121") (pinfunction "E1_P$121") (pintype "bidirectional"))
      (node (ref "U$12") (pin "P$13") (pinfunction "A13_P$13") (pintype "bidirectional"))
      (node (ref "U$12") (pin "P$14") (pinfunction "A14_P$14") (pintype "bidirectional"))
      (node (ref "U$12") (pin "P$15") (pinfunction "A15_P$15") (pintype "bidirectional"))
      (node (ref "U$12") (pin "P$150") (pinfunction "E30_P$150") (pintype "bidirectional"))
      (node (ref "U$12") (pin "P$151") (pinfunction "F1_P$151") (pintype "bidirectional"))
      (node (ref "U$12") (pin "P$16") (pinfunction "A16_P$16") (pintype "bidirectional"))
      (node (ref "U$12") (pin "P$17") (pinfunction "A17_P$17") (pintype "bidirectional"))
      (node (ref "U$12") (pin "P$18") (pinfunction "A18_P$18") (pintype "bidirectional"))
      (node (ref "U$12") (pin "P$180") (pinfunction "F30_P$180") (pintype "bidirectional"))
      (node (ref "U$12") (pin "P$19") (pinfunction "A19_P$19") (pintype "bidirectional"))
      (node (ref "U$12") (pin "P$2") (pinfunction "A2_P$2") (pintype "bidirectional"))
      (node (ref "U$12") (pin "P$20") (pinfunction "A20_P$20") (pintype "bidirectional"))
      (node (ref "U$12") (pin "P$21") (pinfunction "A21_P$21") (pintype "bidirectional"))
      (node (ref "U$12") (pin "P$22") (pinfunction "A22_P$22") (pintype "bidirectional"))
      (node (ref "U$12") (pin "P$23") (pinfunction "A23_P$23") (pintype "bidirectional"))
      (node (ref "U$12") (pin "P$24") (pinfunction "A24_P$24") (pintype "bidirectional"))
      (node (ref "U$12") (pin "P$25") (pinfunction "A25_P$25") (pintype "bidirectional"))
      (node (ref "U$12") (pin "P$26") (pinfunction "A26_P$26") (pintype "bidirectional"))
      (node (ref "U$12") (pin "P$27") (pinfunction "A27_P$27") (pintype "bidirectional"))
      (node (ref "U$12") (pin "P$28") (pinfunction "A28_P$28") (pintype "bidirectional"))
      (node (ref "U$12") (pin "P$29") (pinfunction "A29_P$29") (pintype "bidirectional"))
      (node (ref "U$12") (pin "P$3") (pinfunction "A3_P$3") (pintype "bidirectional"))
      (node (ref "U$12") (pin "P$31") (pinfunction "B1_P$31") (pintype "bidirectional"))
      (node (ref "U$12") (pin "P$32") (pinfunction "B2_P$32") (pintype "bidirectional"))
      (node (ref "U$12") (pin "P$39") (pinfunction "B9_P$39") (pintype "bidirectional"))
      (node (ref "U$12") (pin "P$4") (pinfunction "A4_P$4") (pintype "bidirectional"))
      (node (ref "U$12") (pin "P$46") (pinfunction "B16_P$46") (pintype "bidirectional"))
      (node (ref "U$12") (pin "P$5") (pinfunction "A5_P$5") (pintype "bidirectional"))
      (node (ref "U$12") (pin "P$53") (pinfunction "B23_P$53") (pintype "bidirectional"))
      (node (ref "U$12") (pin "P$6") (pinfunction "A6_P$6") (pintype "bidirectional"))
      (node (ref "U$12") (pin "P$60") (pinfunction "B30_P$60") (pintype "bidirectional"))
      (node (ref "U$12") (pin "P$61") (pinfunction "C1_P$61") (pintype "bidirectional"))
      (node (ref "U$12") (pin "P$62") (pinfunction "C2_P$62") (pintype "bidirectional"))
      (node (ref "U$12") (pin "P$69") (pinfunction "C9_P$69") (pintype "bidirectional"))
      (node (ref "U$12") (pin "P$7") (pinfunction "A7_P$7") (pintype "bidirectional"))
      (node (ref "U$12") (pin "P$76") (pinfunction "C16_P$76") (pintype "bidirectional"))
      (node (ref "U$12") (pin "P$8") (pinfunction "A8_P$8") (pintype "bidirectional"))
      (node (ref "U$12") (pin "P$83") (pinfunction "C23_P$83") (pintype "bidirectional"))
      (node (ref "U$12") (pin "P$9") (pinfunction "A9_P$9") (pintype "bidirectional"))
      (node (ref "U$12") (pin "P$90") (pinfunction "C30_P$90") (pintype "bidirectional"))
      (node (ref "U$12") (pin "P$91") (pinfunction "D1_P$91") (pintype "bidirectional"))
      (node (ref "U$12") (pin "P$92") (pinfunction "D2_P$92") (pintype "bidirectional"))
      (node (ref "U$12") (pin "P$99") (pinfunction "D9_P$99") (pintype "bidirectional"))
      (node (ref "U$13") (pin "P$1") (pinfunction "A1_P$1") (pintype "bidirectional"))
      (node (ref "U$13") (pin "P$10") (pinfunction "A10_P$10") (pintype "bidirectional"))
      (node (ref "U$13") (pin "P$106") (pinfunction "D16_P$106") (pintype "bidirectional"))
      (node (ref "U$13") (pin "P$11") (pinfunction "A11_P$11") (pintype "bidirectional"))
      (node (ref "U$13") (pin "P$113") (pinfunction "D23_P$113") (pintype "bidirectional"))
      (node (ref "U$13") (pin "P$12") (pinfunction "A12_P$12") (pintype "bidirectional"))
      (node (ref "U$13") (pin "P$120") (pinfunction "D30_P$120") (pintype "bidirectional"))
      (node (ref "U$13") (pin "P$121") (pinfunction "E1_P$121") (pintype "bidirectional"))
      (node (ref "U$13") (pin "P$13") (pinfunction "A13_P$13") (pintype "bidirectional"))
      (node (ref "U$13") (pin "P$14") (pinfunction "A14_P$14") (pintype "bidirectional"))
      (node (ref "U$13") (pin "P$15") (pinfunction "A15_P$15") (pintype "bidirectional"))
      (node (ref "U$13") (pin "P$150") (pinfunction "E30_P$150") (pintype "bidirectional"))
      (node (ref "U$13") (pin "P$151") (pinfunction "F1_P$151") (pintype "bidirectional"))
      (node (ref "U$13") (pin "P$16") (pinfunction "A16_P$16") (pintype "bidirectional"))
      (node (ref "U$13") (pin "P$17") (pinfunction "A17_P$17") (pintype "bidirectional"))
      (node (ref "U$13") (pin "P$18") (pinfunction "A18_P$18") (pintype "bidirectional"))
      (node (ref "U$13") (pin "P$180") (pinfunction "F30_P$180") (pintype "bidirectional"))
      (node (ref "U$13") (pin "P$19") (pinfunction "A19_P$19") (pintype "bidirectional"))
      (node (ref "U$13") (pin "P$2") (pinfunction "A2_P$2") (pintype "bidirectional"))
      (node (ref "U$13") (pin "P$20") (pinfunction "A20_P$20") (pintype "bidirectional"))
      (node (ref "U$13") (pin "P$21") (pinfunction "A21_P$21") (pintype "bidirectional"))
      (node (ref "U$13") (pin "P$22") (pinfunction "A22_P$22") (pintype "bidirectional"))
      (node (ref "U$13") (pin "P$23") (pinfunction "A23_P$23") (pintype "bidirectional"))
      (node (ref "U$13") (pin "P$24") (pinfunction "A24_P$24") (pintype "bidirectional"))
      (node (ref "U$13") (pin "P$25") (pinfunction "A25_P$25") (pintype "bidirectional"))
      (node (ref "U$13") (pin "P$26") (pinfunction "A26_P$26") (pintype "bidirectional"))
      (node (ref "U$13") (pin "P$27") (pinfunction "A27_P$27") (pintype "bidirectional"))
      (node (ref "U$13") (pin "P$28") (pinfunction "A28_P$28") (pintype "bidirectional"))
      (node (ref "U$13") (pin "P$29") (pinfunction "A29_P$29") (pintype "bidirectional"))
      (node (ref "U$13") (pin "P$3") (pinfunction "A3_P$3") (pintype "bidirectional"))
      (node (ref "U$13") (pin "P$31") (pinfunction "B1_P$31") (pintype "bidirectional"))
      (node (ref "U$13") (pin "P$32") (pinfunction "B2_P$32") (pintype "bidirectional"))
      (node (ref "U$13") (pin "P$39") (pinfunction "B9_P$39") (pintype "bidirectional"))
      (node (ref "U$13") (pin "P$4") (pinfunction "A4_P$4") (pintype "bidirectional"))
      (node (ref "U$13") (pin "P$46") (pinfunction "B16_P$46") (pintype "bidirectional"))
      (node (ref "U$13") (pin "P$5") (pinfunction "A5_P$5") (pintype "bidirectional"))
      (node (ref "U$13") (pin "P$53") (pinfunction "B23_P$53") (pintype "bidirectional"))
      (node (ref "U$13") (pin "P$6") (pinfunction "A6_P$6") (pintype "bidirectional"))
      (node (ref "U$13") (pin "P$60") (pinfunction "B30_P$60") (pintype "bidirectional"))
      (node (ref "U$13") (pin "P$61") (pinfunction "C1_P$61") (pintype "bidirectional"))
      (node (ref "U$13") (pin "P$62") (pinfunction "C2_P$62") (pintype "bidirectional"))
      (node (ref "U$13") (pin "P$69") (pinfunction "C9_P$69") (pintype "bidirectional"))
      (node (ref "U$13") (pin "P$7") (pinfunction "A7_P$7") (pintype "bidirectional"))
      (node (ref "U$13") (pin "P$76") (pinfunction "C16_P$76") (pintype "bidirectional"))
      (node (ref "U$13") (pin "P$8") (pinfunction "A8_P$8") (pintype "bidirectional"))
      (node (ref "U$13") (pin "P$83") (pinfunction "C23_P$83") (pintype "bidirectional"))
      (node (ref "U$13") (pin "P$9") (pinfunction "A9_P$9") (pintype "bidirectional"))
      (node (ref "U$13") (pin "P$90") (pinfunction "C30_P$90") (pintype "bidirectional"))
      (node (ref "U$13") (pin "P$91") (pinfunction "D1_P$91") (pintype "bidirectional"))
      (node (ref "U$13") (pin "P$92") (pinfunction "D2_P$92") (pintype "bidirectional"))
      (node (ref "U$13") (pin "P$99") (pinfunction "D9_P$99") (pintype "bidirectional"))
      (node (ref "U$14") (pin "P$1") (pinfunction "A1_P$1") (pintype "bidirectional"))
      (node (ref "U$14") (pin "P$10") (pinfunction "A10_P$10") (pintype "bidirectional"))
      (node (ref "U$14") (pin "P$106") (pinfunction "D16_P$106") (pintype "bidirectional"))
      (node (ref "U$14") (pin "P$11") (pinfunction "A11_P$11") (pintype "bidirectional"))
      (node (ref "U$14") (pin "P$113") (pinfunction "D23_P$113") (pintype "bidirectional"))
      (node (ref "U$14") (pin "P$12") (pinfunction "A12_P$12") (pintype "bidirectional"))
      (node (ref "U$14") (pin "P$120") (pinfunction "D30_P$120") (pintype "bidirectional"))
      (node (ref "U$14") (pin "P$121") (pinfunction "E1_P$121") (pintype "bidirectional"))
      (node (ref "U$14") (pin "P$13") (pinfunction "A13_P$13") (pintype "bidirectional"))
      (node (ref "U$14") (pin "P$14") (pinfunction "A14_P$14") (pintype "bidirectional"))
      (node (ref "U$14") (pin "P$15") (pinfunction "A15_P$15") (pintype "bidirectional"))
      (node (ref "U$14") (pin "P$150") (pinfunction "E30_P$150") (pintype "bidirectional"))
      (node (ref "U$14") (pin "P$151") (pinfunction "F1_P$151") (pintype "bidirectional"))
      (node (ref "U$14") (pin "P$16") (pinfunction "A16_P$16") (pintype "bidirectional"))
      (node (ref "U$14") (pin "P$17") (pinfunction "A17_P$17") (pintype "bidirectional"))
      (node (ref "U$14") (pin "P$18") (pinfunction "A18_P$18") (pintype "bidirectional"))
      (node (ref "U$14") (pin "P$180") (pinfunction "F30_P$180") (pintype "bidirectional"))
      (node (ref "U$14") (pin "P$19") (pinfunction "A19_P$19") (pintype "bidirectional"))
      (node (ref "U$14") (pin "P$2") (pinfunction "A2_P$2") (pintype "bidirectional"))
      (node (ref "U$14") (pin "P$20") (pinfunction "A20_P$20") (pintype "bidirectional"))
      (node (ref "U$14") (pin "P$21") (pinfunction "A21_P$21") (pintype "bidirectional"))
      (node (ref "U$14") (pin "P$22") (pinfunction "A22_P$22") (pintype "bidirectional"))
      (node (ref "U$14") (pin "P$23") (pinfunction "A23_P$23") (pintype "bidirectional"))
      (node (ref "U$14") (pin "P$24") (pinfunction "A24_P$24") (pintype "bidirectional"))
      (node (ref "U$14") (pin "P$25") (pinfunction "A25_P$25") (pintype "bidirectional"))
      (node (ref "U$14") (pin "P$26") (pinfunction "A26_P$26") (pintype "bidirectional"))
      (node (ref "U$14") (pin "P$27") (pinfunction "A27_P$27") (pintype "bidirectional"))
      (node (ref "U$14") (pin "P$28") (pinfunction "A28_P$28") (pintype "bidirectional"))
      (node (ref "U$14") (pin "P$29") (pinfunction "A29_P$29") (pintype "bidirectional"))
      (node (ref "U$14") (pin "P$3") (pinfunction "A3_P$3") (pintype "bidirectional"))
      (node (ref "U$14") (pin "P$31") (pinfunction "B1_P$31") (pintype "bidirectional"))
      (node (ref "U$14") (pin "P$32") (pinfunction "B2_P$32") (pintype "bidirectional"))
      (node (ref "U$14") (pin "P$39") (pinfunction "B9_P$39") (pintype "bidirectional"))
      (node (ref "U$14") (pin "P$4") (pinfunction "A4_P$4") (pintype "bidirectional"))
      (node (ref "U$14") (pin "P$46") (pinfunction "B16_P$46") (pintype "bidirectional"))
      (node (ref "U$14") (pin "P$5") (pinfunction "A5_P$5") (pintype "bidirectional"))
      (node (ref "U$14") (pin "P$53") (pinfunction "B23_P$53") (pintype "bidirectional"))
      (node (ref "U$14") (pin "P$6") (pinfunction "A6_P$6") (pintype "bidirectional"))
      (node (ref "U$14") (pin "P$60") (pinfunction "B30_P$60") (pintype "bidirectional"))
      (node (ref "U$14") (pin "P$61") (pinfunction "C1_P$61") (pintype "bidirectional"))
      (node (ref "U$14") (pin "P$62") (pinfunction "C2_P$62") (pintype "bidirectional"))
      (node (ref "U$14") (pin "P$69") (pinfunction "C9_P$69") (pintype "bidirectional"))
      (node (ref "U$14") (pin "P$7") (pinfunction "A7_P$7") (pintype "bidirectional"))
      (node (ref "U$14") (pin "P$76") (pinfunction "C16_P$76") (pintype "bidirectional"))
      (node (ref "U$14") (pin "P$8") (pinfunction "A8_P$8") (pintype "bidirectional"))
      (node (ref "U$14") (pin "P$83") (pinfunction "C23_P$83") (pintype "bidirectional"))
      (node (ref "U$14") (pin "P$9") (pinfunction "A9_P$9") (pintype "bidirectional"))
      (node (ref "U$14") (pin "P$90") (pinfunction "C30_P$90") (pintype "bidirectional"))
      (node (ref "U$14") (pin "P$91") (pinfunction "D1_P$91") (pintype "bidirectional"))
      (node (ref "U$14") (pin "P$92") (pinfunction "D2_P$92") (pintype "bidirectional"))
      (node (ref "U$14") (pin "P$99") (pinfunction "D9_P$99") (pintype "bidirectional"))
      (node (ref "U$15") (pin "P$1") (pinfunction "A1_P$1") (pintype "bidirectional"))
      (node (ref "U$15") (pin "P$10") (pinfunction "A10_P$10") (pintype "bidirectional"))
      (node (ref "U$15") (pin "P$106") (pinfunction "D16_P$106") (pintype "bidirectional"))
      (node (ref "U$15") (pin "P$11") (pinfunction "A11_P$11") (pintype "bidirectional"))
      (node (ref "U$15") (pin "P$113") (pinfunction "D23_P$113") (pintype "bidirectional"))
      (node (ref "U$15") (pin "P$12") (pinfunction "A12_P$12") (pintype "bidirectional"))
      (node (ref "U$15") (pin "P$120") (pinfunction "D30_P$120") (pintype "bidirectional"))
      (node (ref "U$15") (pin "P$121") (pinfunction "E1_P$121") (pintype "bidirectional"))
      (node (ref "U$15") (pin "P$13") (pinfunction "A13_P$13") (pintype "bidirectional"))
      (node (ref "U$15") (pin "P$14") (pinfunction "A14_P$14") (pintype "bidirectional"))
      (node (ref "U$15") (pin "P$15") (pinfunction "A15_P$15") (pintype "bidirectional"))
      (node (ref "U$15") (pin "P$150") (pinfunction "E30_P$150") (pintype "bidirectional"))
      (node (ref "U$15") (pin "P$151") (pinfunction "F1_P$151") (pintype "bidirectional"))
      (node (ref "U$15") (pin "P$16") (pinfunction "A16_P$16") (pintype "bidirectional"))
      (node (ref "U$15") (pin "P$17") (pinfunction "A17_P$17") (pintype "bidirectional"))
      (node (ref "U$15") (pin "P$18") (pinfunction "A18_P$18") (pintype "bidirectional"))
      (node (ref "U$15") (pin "P$180") (pinfunction "F30_P$180") (pintype "bidirectional"))
      (node (ref "U$15") (pin "P$19") (pinfunction "A19_P$19") (pintype "bidirectional"))
      (node (ref "U$15") (pin "P$2") (pinfunction "A2_P$2") (pintype "bidirectional"))
      (node (ref "U$15") (pin "P$20") (pinfunction "A20_P$20") (pintype "bidirectional"))
      (node (ref "U$15") (pin "P$21") (pinfunction "A21_P$21") (pintype "bidirectional"))
      (node (ref "U$15") (pin "P$22") (pinfunction "A22_P$22") (pintype "bidirectional"))
      (node (ref "U$15") (pin "P$23") (pinfunction "A23_P$23") (pintype "bidirectional"))
      (node (ref "U$15") (pin "P$24") (pinfunction "A24_P$24") (pintype "bidirectional"))
      (node (ref "U$15") (pin "P$25") (pinfunction "A25_P$25") (pintype "bidirectional"))
      (node (ref "U$15") (pin "P$26") (pinfunction "A26_P$26") (pintype "bidirectional"))
      (node (ref "U$15") (pin "P$27") (pinfunction "A27_P$27") (pintype "bidirectional"))
      (node (ref "U$15") (pin "P$28") (pinfunction "A28_P$28") (pintype "bidirectional"))
      (node (ref "U$15") (pin "P$29") (pinfunction "A29_P$29") (pintype "bidirectional"))
      (node (ref "U$15") (pin "P$3") (pinfunction "A3_P$3") (pintype "bidirectional"))
      (node (ref "U$15") (pin "P$31") (pinfunction "B1_P$31") (pintype "bidirectional"))
      (node (ref "U$15") (pin "P$32") (pinfunction "B2_P$32") (pintype "bidirectional"))
      (node (ref "U$15") (pin "P$39") (pinfunction "B9_P$39") (pintype "bidirectional"))
      (node (ref "U$15") (pin "P$4") (pinfunction "A4_P$4") (pintype "bidirectional"))
      (node (ref "U$15") (pin "P$46") (pinfunction "B16_P$46") (pintype "bidirectional"))
      (node (ref "U$15") (pin "P$5") (pinfunction "A5_P$5") (pintype "bidirectional"))
      (node (ref "U$15") (pin "P$53") (pinfunction "B23_P$53") (pintype "bidirectional"))
      (node (ref "U$15") (pin "P$6") (pinfunction "A6_P$6") (pintype "bidirectional"))
      (node (ref "U$15") (pin "P$60") (pinfunction "B30_P$60") (pintype "bidirectional"))
      (node (ref "U$15") (pin "P$61") (pinfunction "C1_P$61") (pintype "bidirectional"))
      (node (ref "U$15") (pin "P$62") (pinfunction "C2_P$62") (pintype "bidirectional"))
      (node (ref "U$15") (pin "P$69") (pinfunction "C9_P$69") (pintype "bidirectional"))
      (node (ref "U$15") (pin "P$7") (pinfunction "A7_P$7") (pintype "bidirectional"))
      (node (ref "U$15") (pin "P$76") (pinfunction "C16_P$76") (pintype "bidirectional"))
      (node (ref "U$15") (pin "P$8") (pinfunction "A8_P$8") (pintype "bidirectional"))
      (node (ref "U$15") (pin "P$83") (pinfunction "C23_P$83") (pintype "bidirectional"))
      (node (ref "U$15") (pin "P$9") (pinfunction "A9_P$9") (pintype "bidirectional"))
      (node (ref "U$15") (pin "P$90") (pinfunction "C30_P$90") (pintype "bidirectional"))
      (node (ref "U$15") (pin "P$91") (pinfunction "D1_P$91") (pintype "bidirectional"))
      (node (ref "U$15") (pin "P$92") (pinfunction "D2_P$92") (pintype "bidirectional"))
      (node (ref "U$15") (pin "P$99") (pinfunction "D9_P$99") (pintype "bidirectional"))
      (node (ref "U$16") (pin "P$1") (pinfunction "A1_P$1") (pintype "bidirectional"))
      (node (ref "U$16") (pin "P$10") (pinfunction "A10_P$10") (pintype "bidirectional"))
      (node (ref "U$16") (pin "P$106") (pinfunction "D16_P$106") (pintype "bidirectional"))
      (node (ref "U$16") (pin "P$11") (pinfunction "A11_P$11") (pintype "bidirectional"))
      (node (ref "U$16") (pin "P$113") (pinfunction "D23_P$113") (pintype "bidirectional"))
      (node (ref "U$16") (pin "P$12") (pinfunction "A12_P$12") (pintype "bidirectional"))
      (node (ref "U$16") (pin "P$120") (pinfunction "D30_P$120") (pintype "bidirectional"))
      (node (ref "U$16") (pin "P$121") (pinfunction "E1_P$121") (pintype "bidirectional"))
      (node (ref "U$16") (pin "P$13") (pinfunction "A13_P$13") (pintype "bidirectional"))
      (node (ref "U$16") (pin "P$14") (pinfunction "A14_P$14") (pintype "bidirectional"))
      (node (ref "U$16") (pin "P$15") (pinfunction "A15_P$15") (pintype "bidirectional"))
      (node (ref "U$16") (pin "P$150") (pinfunction "E30_P$150") (pintype "bidirectional"))
      (node (ref "U$16") (pin "P$151") (pinfunction "F1_P$151") (pintype "bidirectional"))
      (node (ref "U$16") (pin "P$16") (pinfunction "A16_P$16") (pintype "bidirectional"))
      (node (ref "U$16") (pin "P$17") (pinfunction "A17_P$17") (pintype "bidirectional"))
      (node (ref "U$16") (pin "P$18") (pinfunction "A18_P$18") (pintype "bidirectional"))
      (node (ref "U$16") (pin "P$180") (pinfunction "F30_P$180") (pintype "bidirectional"))
      (node (ref "U$16") (pin "P$19") (pinfunction "A19_P$19") (pintype "bidirectional"))
      (node (ref "U$16") (pin "P$2") (pinfunction "A2_P$2") (pintype "bidirectional"))
      (node (ref "U$16") (pin "P$20") (pinfunction "A20_P$20") (pintype "bidirectional"))
      (node (ref "U$16") (pin "P$21") (pinfunction "A21_P$21") (pintype "bidirectional"))
      (node (ref "U$16") (pin "P$22") (pinfunction "A22_P$22") (pintype "bidirectional"))
      (node (ref "U$16") (pin "P$23") (pinfunction "A23_P$23") (pintype "bidirectional"))
      (node (ref "U$16") (pin "P$24") (pinfunction "A24_P$24") (pintype "bidirectional"))
      (node (ref "U$16") (pin "P$25") (pinfunction "A25_P$25") (pintype "bidirectional"))
      (node (ref "U$16") (pin "P$26") (pinfunction "A26_P$26") (pintype "bidirectional"))
      (node (ref "U$16") (pin "P$27") (pinfunction "A27_P$27") (pintype "bidirectional"))
      (node (ref "U$16") (pin "P$28") (pinfunction "A28_P$28") (pintype "bidirectional"))
      (node (ref "U$16") (pin "P$29") (pinfunction "A29_P$29") (pintype "bidirectional"))
      (node (ref "U$16") (pin "P$3") (pinfunction "A3_P$3") (pintype "bidirectional"))
      (node (ref "U$16") (pin "P$31") (pinfunction "B1_P$31") (pintype "bidirectional"))
      (node (ref "U$16") (pin "P$32") (pinfunction "B2_P$32") (pintype "bidirectional"))
      (node (ref "U$16") (pin "P$39") (pinfunction "B9_P$39") (pintype "bidirectional"))
      (node (ref "U$16") (pin "P$4") (pinfunction "A4_P$4") (pintype "bidirectional"))
      (node (ref "U$16") (pin "P$46") (pinfunction "B16_P$46") (pintype "bidirectional"))
      (node (ref "U$16") (pin "P$5") (pinfunction "A5_P$5") (pintype "bidirectional"))
      (node (ref "U$16") (pin "P$53") (pinfunction "B23_P$53") (pintype "bidirectional"))
      (node (ref "U$16") (pin "P$6") (pinfunction "A6_P$6") (pintype "bidirectional"))
      (node (ref "U$16") (pin "P$60") (pinfunction "B30_P$60") (pintype "bidirectional"))
      (node (ref "U$16") (pin "P$61") (pinfunction "C1_P$61") (pintype "bidirectional"))
      (node (ref "U$16") (pin "P$62") (pinfunction "C2_P$62") (pintype "bidirectional"))
      (node (ref "U$16") (pin "P$69") (pinfunction "C9_P$69") (pintype "bidirectional"))
      (node (ref "U$16") (pin "P$7") (pinfunction "A7_P$7") (pintype "bidirectional"))
      (node (ref "U$16") (pin "P$76") (pinfunction "C16_P$76") (pintype "bidirectional"))
      (node (ref "U$16") (pin "P$8") (pinfunction "A8_P$8") (pintype "bidirectional"))
      (node (ref "U$16") (pin "P$83") (pinfunction "C23_P$83") (pintype "bidirectional"))
      (node (ref "U$16") (pin "P$9") (pinfunction "A9_P$9") (pintype "bidirectional"))
      (node (ref "U$16") (pin "P$90") (pinfunction "C30_P$90") (pintype "bidirectional"))
      (node (ref "U$16") (pin "P$91") (pinfunction "D1_P$91") (pintype "bidirectional"))
      (node (ref "U$16") (pin "P$92") (pinfunction "D2_P$92") (pintype "bidirectional"))
      (node (ref "U$16") (pin "P$99") (pinfunction "D9_P$99") (pintype "bidirectional"))
      (node (ref "U$17") (pin "P$1") (pinfunction "A1_P$1") (pintype "bidirectional"))
      (node (ref "U$17") (pin "P$10") (pinfunction "A10_P$10") (pintype "bidirectional"))
      (node (ref "U$17") (pin "P$106") (pinfunction "D16_P$106") (pintype "bidirectional"))
      (node (ref "U$17") (pin "P$11") (pinfunction "A11_P$11") (pintype "bidirectional"))
      (node (ref "U$17") (pin "P$113") (pinfunction "D23_P$113") (pintype "bidirectional"))
      (node (ref "U$17") (pin "P$12") (pinfunction "A12_P$12") (pintype "bidirectional"))
      (node (ref "U$17") (pin "P$120") (pinfunction "D30_P$120") (pintype "bidirectional"))
      (node (ref "U$17") (pin "P$121") (pinfunction "E1_P$121") (pintype "bidirectional"))
      (node (ref "U$17") (pin "P$13") (pinfunction "A13_P$13") (pintype "bidirectional"))
      (node (ref "U$17") (pin "P$14") (pinfunction "A14_P$14") (pintype "bidirectional"))
      (node (ref "U$17") (pin "P$15") (pinfunction "A15_P$15") (pintype "bidirectional"))
      (node (ref "U$17") (pin "P$150") (pinfunction "E30_P$150") (pintype "bidirectional"))
      (node (ref "U$17") (pin "P$151") (pinfunction "F1_P$151") (pintype "bidirectional"))
      (node (ref "U$17") (pin "P$16") (pinfunction "A16_P$16") (pintype "bidirectional"))
      (node (ref "U$17") (pin "P$17") (pinfunction "A17_P$17") (pintype "bidirectional"))
      (node (ref "U$17") (pin "P$18") (pinfunction "A18_P$18") (pintype "bidirectional"))
      (node (ref "U$17") (pin "P$180") (pinfunction "F30_P$180") (pintype "bidirectional"))
      (node (ref "U$17") (pin "P$19") (pinfunction "A19_P$19") (pintype "bidirectional"))
      (node (ref "U$17") (pin "P$2") (pinfunction "A2_P$2") (pintype "bidirectional"))
      (node (ref "U$17") (pin "P$20") (pinfunction "A20_P$20") (pintype "bidirectional"))
      (node (ref "U$17") (pin "P$21") (pinfunction "A21_P$21") (pintype "bidirectional"))
      (node (ref "U$17") (pin "P$22") (pinfunction "A22_P$22") (pintype "bidirectional"))
      (node (ref "U$17") (pin "P$23") (pinfunction "A23_P$23") (pintype "bidirectional"))
      (node (ref "U$17") (pin "P$24") (pinfunction "A24_P$24") (pintype "bidirectional"))
      (node (ref "U$17") (pin "P$25") (pinfunction "A25_P$25") (pintype "bidirectional"))
      (node (ref "U$17") (pin "P$26") (pinfunction "A26_P$26") (pintype "bidirectional"))
      (node (ref "U$17") (pin "P$27") (pinfunction "A27_P$27") (pintype "bidirectional"))
      (node (ref "U$17") (pin "P$28") (pinfunction "A28_P$28") (pintype "bidirectional"))
      (node (ref "U$17") (pin "P$29") (pinfunction "A29_P$29") (pintype "bidirectional"))
      (node (ref "U$17") (pin "P$3") (pinfunction "A3_P$3") (pintype "bidirectional"))
      (node (ref "U$17") (pin "P$31") (pinfunction "B1_P$31") (pintype "bidirectional"))
      (node (ref "U$17") (pin "P$32") (pinfunction "B2_P$32") (pintype "bidirectional"))
      (node (ref "U$17") (pin "P$39") (pinfunction "B9_P$39") (pintype "bidirectional"))
      (node (ref "U$17") (pin "P$4") (pinfunction "A4_P$4") (pintype "bidirectional"))
      (node (ref "U$17") (pin "P$46") (pinfunction "B16_P$46") (pintype "bidirectional"))
      (node (ref "U$17") (pin "P$5") (pinfunction "A5_P$5") (pintype "bidirectional"))
      (node (ref "U$17") (pin "P$53") (pinfunction "B23_P$53") (pintype "bidirectional"))
      (node (ref "U$17") (pin "P$6") (pinfunction "A6_P$6") (pintype "bidirectional"))
      (node (ref "U$17") (pin "P$60") (pinfunction "B30_P$60") (pintype "bidirectional"))
      (node (ref "U$17") (pin "P$61") (pinfunction "C1_P$61") (pintype "bidirectional"))
      (node (ref "U$17") (pin "P$62") (pinfunction "C2_P$62") (pintype "bidirectional"))
      (node (ref "U$17") (pin "P$69") (pinfunction "C9_P$69") (pintype "bidirectional"))
      (node (ref "U$17") (pin "P$7") (pinfunction "A7_P$7") (pintype "bidirectional"))
      (node (ref "U$17") (pin "P$76") (pinfunction "C16_P$76") (pintype "bidirectional"))
      (node (ref "U$17") (pin "P$8") (pinfunction "A8_P$8") (pintype "bidirectional"))
      (node (ref "U$17") (pin "P$83") (pinfunction "C23_P$83") (pintype "bidirectional"))
      (node (ref "U$17") (pin "P$9") (pinfunction "A9_P$9") (pintype "bidirectional"))
      (node (ref "U$17") (pin "P$90") (pinfunction "C30_P$90") (pintype "bidirectional"))
      (node (ref "U$17") (pin "P$91") (pinfunction "D1_P$91") (pintype "bidirectional"))
      (node (ref "U$17") (pin "P$92") (pinfunction "D2_P$92") (pintype "bidirectional"))
      (node (ref "U$17") (pin "P$99") (pinfunction "D9_P$99") (pintype "bidirectional"))
      (node (ref "U$18") (pin "P$1") (pinfunction "A1_P$1") (pintype "bidirectional"))
      (node (ref "U$18") (pin "P$10") (pinfunction "A10_P$10") (pintype "bidirectional"))
      (node (ref "U$18") (pin "P$106") (pinfunction "D16_P$106") (pintype "bidirectional"))
      (node (ref "U$18") (pin "P$11") (pinfunction "A11_P$11") (pintype "bidirectional"))
      (node (ref "U$18") (pin "P$113") (pinfunction "D23_P$113") (pintype "bidirectional"))
      (node (ref "U$18") (pin "P$12") (pinfunction "A12_P$12") (pintype "bidirectional"))
      (node (ref "U$18") (pin "P$120") (pinfunction "D30_P$120") (pintype "bidirectional"))
      (node (ref "U$18") (pin "P$121") (pinfunction "E1_P$121") (pintype "bidirectional"))
      (node (ref "U$18") (pin "P$13") (pinfunction "A13_P$13") (pintype "bidirectional"))
      (node (ref "U$18") (pin "P$14") (pinfunction "A14_P$14") (pintype "bidirectional"))
      (node (ref "U$18") (pin "P$15") (pinfunction "A15_P$15") (pintype "bidirectional"))
      (node (ref "U$18") (pin "P$150") (pinfunction "E30_P$150") (pintype "bidirectional"))
      (node (ref "U$18") (pin "P$151") (pinfunction "F1_P$151") (pintype "bidirectional"))
      (node (ref "U$18") (pin "P$16") (pinfunction "A16_P$16") (pintype "bidirectional"))
      (node (ref "U$18") (pin "P$17") (pinfunction "A17_P$17") (pintype "bidirectional"))
      (node (ref "U$18") (pin "P$18") (pinfunction "A18_P$18") (pintype "bidirectional"))
      (node (ref "U$18") (pin "P$180") (pinfunction "F30_P$180") (pintype "bidirectional"))
      (node (ref "U$18") (pin "P$19") (pinfunction "A19_P$19") (pintype "bidirectional"))
      (node (ref "U$18") (pin "P$2") (pinfunction "A2_P$2") (pintype "bidirectional"))
      (node (ref "U$18") (pin "P$20") (pinfunction "A20_P$20") (pintype "bidirectional"))
      (node (ref "U$18") (pin "P$21") (pinfunction "A21_P$21") (pintype "bidirectional"))
      (node (ref "U$18") (pin "P$22") (pinfunction "A22_P$22") (pintype "bidirectional"))
      (node (ref "U$18") (pin "P$23") (pinfunction "A23_P$23") (pintype "bidirectional"))
      (node (ref "U$18") (pin "P$24") (pinfunction "A24_P$24") (pintype "bidirectional"))
      (node (ref "U$18") (pin "P$25") (pinfunction "A25_P$25") (pintype "bidirectional"))
      (node (ref "U$18") (pin "P$26") (pinfunction "A26_P$26") (pintype "bidirectional"))
      (node (ref "U$18") (pin "P$27") (pinfunction "A27_P$27") (pintype "bidirectional"))
      (node (ref "U$18") (pin "P$28") (pinfunction "A28_P$28") (pintype "bidirectional"))
      (node (ref "U$18") (pin "P$29") (pinfunction "A29_P$29") (pintype "bidirectional"))
      (node (ref "U$18") (pin "P$3") (pinfunction "A3_P$3") (pintype "bidirectional"))
      (node (ref "U$18") (pin "P$31") (pinfunction "B1_P$31") (pintype "bidirectional"))
      (node (ref "U$18") (pin "P$32") (pinfunction "B2_P$32") (pintype "bidirectional"))
      (node (ref "U$18") (pin "P$39") (pinfunction "B9_P$39") (pintype "bidirectional"))
      (node (ref "U$18") (pin "P$4") (pinfunction "A4_P$4") (pintype "bidirectional"))
      (node (ref "U$18") (pin "P$46") (pinfunction "B16_P$46") (pintype "bidirectional"))
      (node (ref "U$18") (pin "P$5") (pinfunction "A5_P$5") (pintype "bidirectional"))
      (node (ref "U$18") (pin "P$53") (pinfunction "B23_P$53") (pintype "bidirectional"))
      (node (ref "U$18") (pin "P$6") (pinfunction "A6_P$6") (pintype "bidirectional"))
      (node (ref "U$18") (pin "P$60") (pinfunction "B30_P$60") (pintype "bidirectional"))
      (node (ref "U$18") (pin "P$61") (pinfunction "C1_P$61") (pintype "bidirectional"))
      (node (ref "U$18") (pin "P$62") (pinfunction "C2_P$62") (pintype "bidirectional"))
      (node (ref "U$18") (pin "P$69") (pinfunction "C9_P$69") (pintype "bidirectional"))
      (node (ref "U$18") (pin "P$7") (pinfunction "A7_P$7") (pintype "bidirectional"))
      (node (ref "U$18") (pin "P$76") (pinfunction "C16_P$76") (pintype "bidirectional"))
      (node (ref "U$18") (pin "P$8") (pinfunction "A8_P$8") (pintype "bidirectional"))
      (node (ref "U$18") (pin "P$83") (pinfunction "C23_P$83") (pintype "bidirectional"))
      (node (ref "U$18") (pin "P$9") (pinfunction "A9_P$9") (pintype "bidirectional"))
      (node (ref "U$18") (pin "P$90") (pinfunction "C30_P$90") (pintype "bidirectional"))
      (node (ref "U$18") (pin "P$91") (pinfunction "D1_P$91") (pintype "bidirectional"))
      (node (ref "U$18") (pin "P$92") (pinfunction "D2_P$92") (pintype "bidirectional"))
      (node (ref "U$18") (pin "P$99") (pinfunction "D9_P$99") (pintype "bidirectional"))
      (node (ref "U$19") (pin "P$1") (pinfunction "A1_P$1") (pintype "bidirectional"))
      (node (ref "U$19") (pin "P$10") (pinfunction "A10_P$10") (pintype "bidirectional"))
      (node (ref "U$19") (pin "P$106") (pinfunction "D16_P$106") (pintype "bidirectional"))
      (node (ref "U$19") (pin "P$11") (pinfunction "A11_P$11") (pintype "bidirectional"))
      (node (ref "U$19") (pin "P$113") (pinfunction "D23_P$113") (pintype "bidirectional"))
      (node (ref "U$19") (pin "P$12") (pinfunction "A12_P$12") (pintype "bidirectional"))
      (node (ref "U$19") (pin "P$120") (pinfunction "D30_P$120") (pintype "bidirectional"))
      (node (ref "U$19") (pin "P$121") (pinfunction "E1_P$121") (pintype "bidirectional"))
      (node (ref "U$19") (pin "P$13") (pinfunction "A13_P$13") (pintype "bidirectional"))
      (node (ref "U$19") (pin "P$14") (pinfunction "A14_P$14") (pintype "bidirectional"))
      (node (ref "U$19") (pin "P$15") (pinfunction "A15_P$15") (pintype "bidirectional"))
      (node (ref "U$19") (pin "P$150") (pinfunction "E30_P$150") (pintype "bidirectional"))
      (node (ref "U$19") (pin "P$151") (pinfunction "F1_P$151") (pintype "bidirectional"))
      (node (ref "U$19") (pin "P$16") (pinfunction "A16_P$16") (pintype "bidirectional"))
      (node (ref "U$19") (pin "P$17") (pinfunction "A17_P$17") (pintype "bidirectional"))
      (node (ref "U$19") (pin "P$18") (pinfunction "A18_P$18") (pintype "bidirectional"))
      (node (ref "U$19") (pin "P$180") (pinfunction "F30_P$180") (pintype "bidirectional"))
      (node (ref "U$19") (pin "P$19") (pinfunction "A19_P$19") (pintype "bidirectional"))
      (node (ref "U$19") (pin "P$2") (pinfunction "A2_P$2") (pintype "bidirectional"))
      (node (ref "U$19") (pin "P$20") (pinfunction "A20_P$20") (pintype "bidirectional"))
      (node (ref "U$19") (pin "P$21") (pinfunction "A21_P$21") (pintype "bidirectional"))
      (node (ref "U$19") (pin "P$22") (pinfunction "A22_P$22") (pintype "bidirectional"))
      (node (ref "U$19") (pin "P$23") (pinfunction "A23_P$23") (pintype "bidirectional"))
      (node (ref "U$19") (pin "P$24") (pinfunction "A24_P$24") (pintype "bidirectional"))
      (node (ref "U$19") (pin "P$25") (pinfunction "A25_P$25") (pintype "bidirectional"))
      (node (ref "U$19") (pin "P$26") (pinfunction "A26_P$26") (pintype "bidirectional"))
      (node (ref "U$19") (pin "P$27") (pinfunction "A27_P$27") (pintype "bidirectional"))
      (node (ref "U$19") (pin "P$28") (pinfunction "A28_P$28") (pintype "bidirectional"))
      (node (ref "U$19") (pin "P$29") (pinfunction "A29_P$29") (pintype "bidirectional"))
      (node (ref "U$19") (pin "P$3") (pinfunction "A3_P$3") (pintype "bidirectional"))
      (node (ref "U$19") (pin "P$31") (pinfunction "B1_P$31") (pintype "bidirectional"))
      (node (ref "U$19") (pin "P$32") (pinfunction "B2_P$32") (pintype "bidirectional"))
      (node (ref "U$19") (pin "P$39") (pinfunction "B9_P$39") (pintype "bidirectional"))
      (node (ref "U$19") (pin "P$4") (pinfunction "A4_P$4") (pintype "bidirectional"))
      (node (ref "U$19") (pin "P$46") (pinfunction "B16_P$46") (pintype "bidirectional"))
      (node (ref "U$19") (pin "P$5") (pinfunction "A5_P$5") (pintype "bidirectional"))
      (node (ref "U$19") (pin "P$53") (pinfunction "B23_P$53") (pintype "bidirectional"))
      (node (ref "U$19") (pin "P$6") (pinfunction "A6_P$6") (pintype "bidirectional"))
      (node (ref "U$19") (pin "P$60") (pinfunction "B30_P$60") (pintype "bidirectional"))
      (node (ref "U$19") (pin "P$61") (pinfunction "C1_P$61") (pintype "bidirectional"))
      (node (ref "U$19") (pin "P$62") (pinfunction "C2_P$62") (pintype "bidirectional"))
      (node (ref "U$19") (pin "P$69") (pinfunction "C9_P$69") (pintype "bidirectional"))
      (node (ref "U$19") (pin "P$7") (pinfunction "A7_P$7") (pintype "bidirectional"))
      (node (ref "U$19") (pin "P$76") (pinfunction "C16_P$76") (pintype "bidirectional"))
      (node (ref "U$19") (pin "P$8") (pinfunction "A8_P$8") (pintype "bidirectional"))
      (node (ref "U$19") (pin "P$83") (pinfunction "C23_P$83") (pintype "bidirectional"))
      (node (ref "U$19") (pin "P$9") (pinfunction "A9_P$9") (pintype "bidirectional"))
      (node (ref "U$19") (pin "P$90") (pinfunction "C30_P$90") (pintype "bidirectional"))
      (node (ref "U$19") (pin "P$91") (pinfunction "D1_P$91") (pintype "bidirectional"))
      (node (ref "U$19") (pin "P$92") (pinfunction "D2_P$92") (pintype "bidirectional"))
      (node (ref "U$19") (pin "P$99") (pinfunction "D9_P$99") (pintype "bidirectional"))
      (node (ref "U$2") (pin "P$1") (pinfunction "A1_P$1") (pintype "bidirectional"))
      (node (ref "U$2") (pin "P$10") (pinfunction "A10_P$10") (pintype "bidirectional"))
      (node (ref "U$2") (pin "P$106") (pinfunction "D16_P$106") (pintype "bidirectional"))
      (node (ref "U$2") (pin "P$11") (pinfunction "A11_P$11") (pintype "bidirectional"))
      (node (ref "U$2") (pin "P$113") (pinfunction "D23_P$113") (pintype "bidirectional"))
      (node (ref "U$2") (pin "P$12") (pinfunction "A12_P$12") (pintype "bidirectional"))
      (node (ref "U$2") (pin "P$120") (pinfunction "D30_P$120") (pintype "bidirectional"))
      (node (ref "U$2") (pin "P$121") (pinfunction "E1_P$121") (pintype "bidirectional"))
      (node (ref "U$2") (pin "P$13") (pinfunction "A13_P$13") (pintype "bidirectional"))
      (node (ref "U$2") (pin "P$14") (pinfunction "A14_P$14") (pintype "bidirectional"))
      (node (ref "U$2") (pin "P$15") (pinfunction "A15_P$15") (pintype "bidirectional"))
      (node (ref "U$2") (pin "P$150") (pinfunction "E30_P$150") (pintype "bidirectional"))
      (node (ref "U$2") (pin "P$151") (pinfunction "F1_P$151") (pintype "bidirectional"))
      (node (ref "U$2") (pin "P$16") (pinfunction "A16_P$16") (pintype "bidirectional"))
      (node (ref "U$2") (pin "P$17") (pinfunction "A17_P$17") (pintype "bidirectional"))
      (node (ref "U$2") (pin "P$18") (pinfunction "A18_P$18") (pintype "bidirectional"))
      (node (ref "U$2") (pin "P$180") (pinfunction "F30_P$180") (pintype "bidirectional"))
      (node (ref "U$2") (pin "P$19") (pinfunction "A19_P$19") (pintype "bidirectional"))
      (node (ref "U$2") (pin "P$2") (pinfunction "A2_P$2") (pintype "bidirectional"))
      (node (ref "U$2") (pin "P$20") (pinfunction "A20_P$20") (pintype "bidirectional"))
      (node (ref "U$2") (pin "P$21") (pinfunction "A21_P$21") (pintype "bidirectional"))
      (node (ref "U$2") (pin "P$22") (pinfunction "A22_P$22") (pintype "bidirectional"))
      (node (ref "U$2") (pin "P$23") (pinfunction "A23_P$23") (pintype "bidirectional"))
      (node (ref "U$2") (pin "P$24") (pinfunction "A24_P$24") (pintype "bidirectional"))
      (node (ref "U$2") (pin "P$25") (pinfunction "A25_P$25") (pintype "bidirectional"))
      (node (ref "U$2") (pin "P$26") (pinfunction "A26_P$26") (pintype "bidirectional"))
      (node (ref "U$2") (pin "P$27") (pinfunction "A27_P$27") (pintype "bidirectional"))
      (node (ref "U$2") (pin "P$28") (pinfunction "A28_P$28") (pintype "bidirectional"))
      (node (ref "U$2") (pin "P$29") (pinfunction "A29_P$29") (pintype "bidirectional"))
      (node (ref "U$2") (pin "P$3") (pinfunction "A3_P$3") (pintype "bidirectional"))
      (node (ref "U$2") (pin "P$31") (pinfunction "B1_P$31") (pintype "bidirectional"))
      (node (ref "U$2") (pin "P$32") (pinfunction "B2_P$32") (pintype "bidirectional"))
      (node (ref "U$2") (pin "P$39") (pinfunction "B9_P$39") (pintype "bidirectional"))
      (node (ref "U$2") (pin "P$4") (pinfunction "A4_P$4") (pintype "bidirectional"))
      (node (ref "U$2") (pin "P$46") (pinfunction "B16_P$46") (pintype "bidirectional"))
      (node (ref "U$2") (pin "P$5") (pinfunction "A5_P$5") (pintype "bidirectional"))
      (node (ref "U$2") (pin "P$53") (pinfunction "B23_P$53") (pintype "bidirectional"))
      (node (ref "U$2") (pin "P$6") (pinfunction "A6_P$6") (pintype "bidirectional"))
      (node (ref "U$2") (pin "P$60") (pinfunction "B30_P$60") (pintype "bidirectional"))
      (node (ref "U$2") (pin "P$61") (pinfunction "C1_P$61") (pintype "bidirectional"))
      (node (ref "U$2") (pin "P$62") (pinfunction "C2_P$62") (pintype "bidirectional"))
      (node (ref "U$2") (pin "P$69") (pinfunction "C9_P$69") (pintype "bidirectional"))
      (node (ref "U$2") (pin "P$7") (pinfunction "A7_P$7") (pintype "bidirectional"))
      (node (ref "U$2") (pin "P$76") (pinfunction "C16_P$76") (pintype "bidirectional"))
      (node (ref "U$2") (pin "P$8") (pinfunction "A8_P$8") (pintype "bidirectional"))
      (node (ref "U$2") (pin "P$83") (pinfunction "C23_P$83") (pintype "bidirectional"))
      (node (ref "U$2") (pin "P$9") (pinfunction "A9_P$9") (pintype "bidirectional"))
      (node (ref "U$2") (pin "P$90") (pinfunction "C30_P$90") (pintype "bidirectional"))
      (node (ref "U$2") (pin "P$91") (pinfunction "D1_P$91") (pintype "bidirectional"))
      (node (ref "U$2") (pin "P$92") (pinfunction "D2_P$92") (pintype "bidirectional"))
      (node (ref "U$2") (pin "P$99") (pinfunction "D9_P$99") (pintype "bidirectional"))
      (node (ref "U$20") (pin "P$1") (pinfunction "A1_P$1") (pintype "bidirectional"))
      (node (ref "U$20") (pin "P$10") (pinfunction "A10_P$10") (pintype "bidirectional"))
      (node (ref "U$20") (pin "P$106") (pinfunction "D16_P$106") (pintype "bidirectional"))
      (node (ref "U$20") (pin "P$11") (pinfunction "A11_P$11") (pintype "bidirectional"))
      (node (ref "U$20") (pin "P$113") (pinfunction "D23_P$113") (pintype "bidirectional"))
      (node (ref "U$20") (pin "P$12") (pinfunction "A12_P$12") (pintype "bidirectional"))
      (node (ref "U$20") (pin "P$120") (pinfunction "D30_P$120") (pintype "bidirectional"))
      (node (ref "U$20") (pin "P$121") (pinfunction "E1_P$121") (pintype "bidirectional"))
      (node (ref "U$20") (pin "P$13") (pinfunction "A13_P$13") (pintype "bidirectional"))
      (node (ref "U$20") (pin "P$14") (pinfunction "A14_P$14") (pintype "bidirectional"))
      (node (ref "U$20") (pin "P$15") (pinfunction "A15_P$15") (pintype "bidirectional"))
      (node (ref "U$20") (pin "P$150") (pinfunction "E30_P$150") (pintype "bidirectional"))
      (node (ref "U$20") (pin "P$151") (pinfunction "F1_P$151") (pintype "bidirectional"))
      (node (ref "U$20") (pin "P$16") (pinfunction "A16_P$16") (pintype "bidirectional"))
      (node (ref "U$20") (pin "P$17") (pinfunction "A17_P$17") (pintype "bidirectional"))
      (node (ref "U$20") (pin "P$18") (pinfunction "A18_P$18") (pintype "bidirectional"))
      (node (ref "U$20") (pin "P$180") (pinfunction "F30_P$180") (pintype "bidirectional"))
      (node (ref "U$20") (pin "P$19") (pinfunction "A19_P$19") (pintype "bidirectional"))
      (node (ref "U$20") (pin "P$2") (pinfunction "A2_P$2") (pintype "bidirectional"))
      (node (ref "U$20") (pin "P$20") (pinfunction "A20_P$20") (pintype "bidirectional"))
      (node (ref "U$20") (pin "P$21") (pinfunction "A21_P$21") (pintype "bidirectional"))
      (node (ref "U$20") (pin "P$22") (pinfunction "A22_P$22") (pintype "bidirectional"))
      (node (ref "U$20") (pin "P$23") (pinfunction "A23_P$23") (pintype "bidirectional"))
      (node (ref "U$20") (pin "P$24") (pinfunction "A24_P$24") (pintype "bidirectional"))
      (node (ref "U$20") (pin "P$25") (pinfunction "A25_P$25") (pintype "bidirectional"))
      (node (ref "U$20") (pin "P$26") (pinfunction "A26_P$26") (pintype "bidirectional"))
      (node (ref "U$20") (pin "P$27") (pinfunction "A27_P$27") (pintype "bidirectional"))
      (node (ref "U$20") (pin "P$28") (pinfunction "A28_P$28") (pintype "bidirectional"))
      (node (ref "U$20") (pin "P$29") (pinfunction "A29_P$29") (pintype "bidirectional"))
      (node (ref "U$20") (pin "P$3") (pinfunction "A3_P$3") (pintype "bidirectional"))
      (node (ref "U$20") (pin "P$31") (pinfunction "B1_P$31") (pintype "bidirectional"))
      (node (ref "U$20") (pin "P$32") (pinfunction "B2_P$32") (pintype "bidirectional"))
      (node (ref "U$20") (pin "P$39") (pinfunction "B9_P$39") (pintype "bidirectional"))
      (node (ref "U$20") (pin "P$4") (pinfunction "A4_P$4") (pintype "bidirectional"))
      (node (ref "U$20") (pin "P$46") (pinfunction "B16_P$46") (pintype "bidirectional"))
      (node (ref "U$20") (pin "P$5") (pinfunction "A5_P$5") (pintype "bidirectional"))
      (node (ref "U$20") (pin "P$53") (pinfunction "B23_P$53") (pintype "bidirectional"))
      (node (ref "U$20") (pin "P$6") (pinfunction "A6_P$6") (pintype "bidirectional"))
      (node (ref "U$20") (pin "P$60") (pinfunction "B30_P$60") (pintype "bidirectional"))
      (node (ref "U$20") (pin "P$61") (pinfunction "C1_P$61") (pintype "bidirectional"))
      (node (ref "U$20") (pin "P$62") (pinfunction "C2_P$62") (pintype "bidirectional"))
      (node (ref "U$20") (pin "P$69") (pinfunction "C9_P$69") (pintype "bidirectional"))
      (node (ref "U$20") (pin "P$7") (pinfunction "A7_P$7") (pintype "bidirectional"))
      (node (ref "U$20") (pin "P$76") (pinfunction "C16_P$76") (pintype "bidirectional"))
      (node (ref "U$20") (pin "P$8") (pinfunction "A8_P$8") (pintype "bidirectional"))
      (node (ref "U$20") (pin "P$83") (pinfunction "C23_P$83") (pintype "bidirectional"))
      (node (ref "U$20") (pin "P$9") (pinfunction "A9_P$9") (pintype "bidirectional"))
      (node (ref "U$20") (pin "P$90") (pinfunction "C30_P$90") (pintype "bidirectional"))
      (node (ref "U$20") (pin "P$91") (pinfunction "D1_P$91") (pintype "bidirectional"))
      (node (ref "U$20") (pin "P$92") (pinfunction "D2_P$92") (pintype "bidirectional"))
      (node (ref "U$20") (pin "P$99") (pinfunction "D9_P$99") (pintype "bidirectional"))
      (node (ref "U$21") (pin "P$1") (pinfunction "A1_P$1") (pintype "bidirectional"))
      (node (ref "U$21") (pin "P$10") (pinfunction "A10_P$10") (pintype "bidirectional"))
      (node (ref "U$21") (pin "P$106") (pinfunction "D16_P$106") (pintype "bidirectional"))
      (node (ref "U$21") (pin "P$11") (pinfunction "A11_P$11") (pintype "bidirectional"))
      (node (ref "U$21") (pin "P$113") (pinfunction "D23_P$113") (pintype "bidirectional"))
      (node (ref "U$21") (pin "P$12") (pinfunction "A12_P$12") (pintype "bidirectional"))
      (node (ref "U$21") (pin "P$120") (pinfunction "D30_P$120") (pintype "bidirectional"))
      (node (ref "U$21") (pin "P$121") (pinfunction "E1_P$121") (pintype "bidirectional"))
      (node (ref "U$21") (pin "P$13") (pinfunction "A13_P$13") (pintype "bidirectional"))
      (node (ref "U$21") (pin "P$14") (pinfunction "A14_P$14") (pintype "bidirectional"))
      (node (ref "U$21") (pin "P$15") (pinfunction "A15_P$15") (pintype "bidirectional"))
      (node (ref "U$21") (pin "P$150") (pinfunction "E30_P$150") (pintype "bidirectional"))
      (node (ref "U$21") (pin "P$151") (pinfunction "F1_P$151") (pintype "bidirectional"))
      (node (ref "U$21") (pin "P$16") (pinfunction "A16_P$16") (pintype "bidirectional"))
      (node (ref "U$21") (pin "P$17") (pinfunction "A17_P$17") (pintype "bidirectional"))
      (node (ref "U$21") (pin "P$18") (pinfunction "A18_P$18") (pintype "bidirectional"))
      (node (ref "U$21") (pin "P$180") (pinfunction "F30_P$180") (pintype "bidirectional"))
      (node (ref "U$21") (pin "P$19") (pinfunction "A19_P$19") (pintype "bidirectional"))
      (node (ref "U$21") (pin "P$2") (pinfunction "A2_P$2") (pintype "bidirectional"))
      (node (ref "U$21") (pin "P$20") (pinfunction "A20_P$20") (pintype "bidirectional"))
      (node (ref "U$21") (pin "P$21") (pinfunction "A21_P$21") (pintype "bidirectional"))
      (node (ref "U$21") (pin "P$22") (pinfunction "A22_P$22") (pintype "bidirectional"))
      (node (ref "U$21") (pin "P$23") (pinfunction "A23_P$23") (pintype "bidirectional"))
      (node (ref "U$21") (pin "P$24") (pinfunction "A24_P$24") (pintype "bidirectional"))
      (node (ref "U$21") (pin "P$25") (pinfunction "A25_P$25") (pintype "bidirectional"))
      (node (ref "U$21") (pin "P$26") (pinfunction "A26_P$26") (pintype "bidirectional"))
      (node (ref "U$21") (pin "P$27") (pinfunction "A27_P$27") (pintype "bidirectional"))
      (node (ref "U$21") (pin "P$28") (pinfunction "A28_P$28") (pintype "bidirectional"))
      (node (ref "U$21") (pin "P$29") (pinfunction "A29_P$29") (pintype "bidirectional"))
      (node (ref "U$21") (pin "P$3") (pinfunction "A3_P$3") (pintype "bidirectional"))
      (node (ref "U$21") (pin "P$31") (pinfunction "B1_P$31") (pintype "bidirectional"))
      (node (ref "U$21") (pin "P$32") (pinfunction "B2_P$32") (pintype "bidirectional"))
      (node (ref "U$21") (pin "P$39") (pinfunction "B9_P$39") (pintype "bidirectional"))
      (node (ref "U$21") (pin "P$4") (pinfunction "A4_P$4") (pintype "bidirectional"))
      (node (ref "U$21") (pin "P$46") (pinfunction "B16_P$46") (pintype "bidirectional"))
      (node (ref "U$21") (pin "P$5") (pinfunction "A5_P$5") (pintype "bidirectional"))
      (node (ref "U$21") (pin "P$53") (pinfunction "B23_P$53") (pintype "bidirectional"))
      (node (ref "U$21") (pin "P$6") (pinfunction "A6_P$6") (pintype "bidirectional"))
      (node (ref "U$21") (pin "P$60") (pinfunction "B30_P$60") (pintype "bidirectional"))
      (node (ref "U$21") (pin "P$61") (pinfunction "C1_P$61") (pintype "bidirectional"))
      (node (ref "U$21") (pin "P$62") (pinfunction "C2_P$62") (pintype "bidirectional"))
      (node (ref "U$21") (pin "P$69") (pinfunction "C9_P$69") (pintype "bidirectional"))
      (node (ref "U$21") (pin "P$7") (pinfunction "A7_P$7") (pintype "bidirectional"))
      (node (ref "U$21") (pin "P$76") (pinfunction "C16_P$76") (pintype "bidirectional"))
      (node (ref "U$21") (pin "P$8") (pinfunction "A8_P$8") (pintype "bidirectional"))
      (node (ref "U$21") (pin "P$83") (pinfunction "C23_P$83") (pintype "bidirectional"))
      (node (ref "U$21") (pin "P$9") (pinfunction "A9_P$9") (pintype "bidirectional"))
      (node (ref "U$21") (pin "P$90") (pinfunction "C30_P$90") (pintype "bidirectional"))
      (node (ref "U$21") (pin "P$91") (pinfunction "D1_P$91") (pintype "bidirectional"))
      (node (ref "U$21") (pin "P$92") (pinfunction "D2_P$92") (pintype "bidirectional"))
      (node (ref "U$21") (pin "P$99") (pinfunction "D9_P$99") (pintype "bidirectional"))
      (node (ref "U$22") (pin "P$1") (pinfunction "A1_P$1") (pintype "bidirectional"))
      (node (ref "U$22") (pin "P$10") (pinfunction "A10_P$10") (pintype "bidirectional"))
      (node (ref "U$22") (pin "P$106") (pinfunction "D16_P$106") (pintype "bidirectional"))
      (node (ref "U$22") (pin "P$11") (pinfunction "A11_P$11") (pintype "bidirectional"))
      (node (ref "U$22") (pin "P$113") (pinfunction "D23_P$113") (pintype "bidirectional"))
      (node (ref "U$22") (pin "P$12") (pinfunction "A12_P$12") (pintype "bidirectional"))
      (node (ref "U$22") (pin "P$120") (pinfunction "D30_P$120") (pintype "bidirectional"))
      (node (ref "U$22") (pin "P$121") (pinfunction "E1_P$121") (pintype "bidirectional"))
      (node (ref "U$22") (pin "P$13") (pinfunction "A13_P$13") (pintype "bidirectional"))
      (node (ref "U$22") (pin "P$14") (pinfunction "A14_P$14") (pintype "bidirectional"))
      (node (ref "U$22") (pin "P$15") (pinfunction "A15_P$15") (pintype "bidirectional"))
      (node (ref "U$22") (pin "P$150") (pinfunction "E30_P$150") (pintype "bidirectional"))
      (node (ref "U$22") (pin "P$151") (pinfunction "F1_P$151") (pintype "bidirectional"))
      (node (ref "U$22") (pin "P$16") (pinfunction "A16_P$16") (pintype "bidirectional"))
      (node (ref "U$22") (pin "P$17") (pinfunction "A17_P$17") (pintype "bidirectional"))
      (node (ref "U$22") (pin "P$18") (pinfunction "A18_P$18") (pintype "bidirectional"))
      (node (ref "U$22") (pin "P$180") (pinfunction "F30_P$180") (pintype "bidirectional"))
      (node (ref "U$22") (pin "P$19") (pinfunction "A19_P$19") (pintype "bidirectional"))
      (node (ref "U$22") (pin "P$2") (pinfunction "A2_P$2") (pintype "bidirectional"))
      (node (ref "U$22") (pin "P$20") (pinfunction "A20_P$20") (pintype "bidirectional"))
      (node (ref "U$22") (pin "P$21") (pinfunction "A21_P$21") (pintype "bidirectional"))
      (node (ref "U$22") (pin "P$22") (pinfunction "A22_P$22") (pintype "bidirectional"))
      (node (ref "U$22") (pin "P$23") (pinfunction "A23_P$23") (pintype "bidirectional"))
      (node (ref "U$22") (pin "P$24") (pinfunction "A24_P$24") (pintype "bidirectional"))
      (node (ref "U$22") (pin "P$25") (pinfunction "A25_P$25") (pintype "bidirectional"))
      (node (ref "U$22") (pin "P$26") (pinfunction "A26_P$26") (pintype "bidirectional"))
      (node (ref "U$22") (pin "P$27") (pinfunction "A27_P$27") (pintype "bidirectional"))
      (node (ref "U$22") (pin "P$28") (pinfunction "A28_P$28") (pintype "bidirectional"))
      (node (ref "U$22") (pin "P$29") (pinfunction "A29_P$29") (pintype "bidirectional"))
      (node (ref "U$22") (pin "P$3") (pinfunction "A3_P$3") (pintype "bidirectional"))
      (node (ref "U$22") (pin "P$31") (pinfunction "B1_P$31") (pintype "bidirectional"))
      (node (ref "U$22") (pin "P$32") (pinfunction "B2_P$32") (pintype "bidirectional"))
      (node (ref "U$22") (pin "P$39") (pinfunction "B9_P$39") (pintype "bidirectional"))
      (node (ref "U$22") (pin "P$4") (pinfunction "A4_P$4") (pintype "bidirectional"))
      (node (ref "U$22") (pin "P$46") (pinfunction "B16_P$46") (pintype "bidirectional"))
      (node (ref "U$22") (pin "P$5") (pinfunction "A5_P$5") (pintype "bidirectional"))
      (node (ref "U$22") (pin "P$53") (pinfunction "B23_P$53") (pintype "bidirectional"))
      (node (ref "U$22") (pin "P$6") (pinfunction "A6_P$6") (pintype "bidirectional"))
      (node (ref "U$22") (pin "P$60") (pinfunction "B30_P$60") (pintype "bidirectional"))
      (node (ref "U$22") (pin "P$61") (pinfunction "C1_P$61") (pintype "bidirectional"))
      (node (ref "U$22") (pin "P$62") (pinfunction "C2_P$62") (pintype "bidirectional"))
      (node (ref "U$22") (pin "P$69") (pinfunction "C9_P$69") (pintype "bidirectional"))
      (node (ref "U$22") (pin "P$7") (pinfunction "A7_P$7") (pintype "bidirectional"))
      (node (ref "U$22") (pin "P$76") (pinfunction "C16_P$76") (pintype "bidirectional"))
      (node (ref "U$22") (pin "P$8") (pinfunction "A8_P$8") (pintype "bidirectional"))
      (node (ref "U$22") (pin "P$83") (pinfunction "C23_P$83") (pintype "bidirectional"))
      (node (ref "U$22") (pin "P$9") (pinfunction "A9_P$9") (pintype "bidirectional"))
      (node (ref "U$22") (pin "P$90") (pinfunction "C30_P$90") (pintype "bidirectional"))
      (node (ref "U$22") (pin "P$91") (pinfunction "D1_P$91") (pintype "bidirectional"))
      (node (ref "U$22") (pin "P$92") (pinfunction "D2_P$92") (pintype "bidirectional"))
      (node (ref "U$22") (pin "P$99") (pinfunction "D9_P$99") (pintype "bidirectional"))
      (node (ref "U$23") (pin "P$1") (pinfunction "A1_P$1") (pintype "bidirectional"))
      (node (ref "U$23") (pin "P$10") (pinfunction "A10_P$10") (pintype "bidirectional"))
      (node (ref "U$23") (pin "P$106") (pinfunction "D16_P$106") (pintype "bidirectional"))
      (node (ref "U$23") (pin "P$11") (pinfunction "A11_P$11") (pintype "bidirectional"))
      (node (ref "U$23") (pin "P$113") (pinfunction "D23_P$113") (pintype "bidirectional"))
      (node (ref "U$23") (pin "P$12") (pinfunction "A12_P$12") (pintype "bidirectional"))
      (node (ref "U$23") (pin "P$120") (pinfunction "D30_P$120") (pintype "bidirectional"))
      (node (ref "U$23") (pin "P$121") (pinfunction "E1_P$121") (pintype "bidirectional"))
      (node (ref "U$23") (pin "P$13") (pinfunction "A13_P$13") (pintype "bidirectional"))
      (node (ref "U$23") (pin "P$14") (pinfunction "A14_P$14") (pintype "bidirectional"))
      (node (ref "U$23") (pin "P$15") (pinfunction "A15_P$15") (pintype "bidirectional"))
      (node (ref "U$23") (pin "P$150") (pinfunction "E30_P$150") (pintype "bidirectional"))
      (node (ref "U$23") (pin "P$151") (pinfunction "F1_P$151") (pintype "bidirectional"))
      (node (ref "U$23") (pin "P$16") (pinfunction "A16_P$16") (pintype "bidirectional"))
      (node (ref "U$23") (pin "P$17") (pinfunction "A17_P$17") (pintype "bidirectional"))
      (node (ref "U$23") (pin "P$18") (pinfunction "A18_P$18") (pintype "bidirectional"))
      (node (ref "U$23") (pin "P$180") (pinfunction "F30_P$180") (pintype "bidirectional"))
      (node (ref "U$23") (pin "P$19") (pinfunction "A19_P$19") (pintype "bidirectional"))
      (node (ref "U$23") (pin "P$2") (pinfunction "A2_P$2") (pintype "bidirectional"))
      (node (ref "U$23") (pin "P$20") (pinfunction "A20_P$20") (pintype "bidirectional"))
      (node (ref "U$23") (pin "P$21") (pinfunction "A21_P$21") (pintype "bidirectional"))
      (node (ref "U$23") (pin "P$22") (pinfunction "A22_P$22") (pintype "bidirectional"))
      (node (ref "U$23") (pin "P$23") (pinfunction "A23_P$23") (pintype "bidirectional"))
      (node (ref "U$23") (pin "P$24") (pinfunction "A24_P$24") (pintype "bidirectional"))
      (node (ref "U$23") (pin "P$25") (pinfunction "A25_P$25") (pintype "bidirectional"))
      (node (ref "U$23") (pin "P$26") (pinfunction "A26_P$26") (pintype "bidirectional"))
      (node (ref "U$23") (pin "P$27") (pinfunction "A27_P$27") (pintype "bidirectional"))
      (node (ref "U$23") (pin "P$28") (pinfunction "A28_P$28") (pintype "bidirectional"))
      (node (ref "U$23") (pin "P$29") (pinfunction "A29_P$29") (pintype "bidirectional"))
      (node (ref "U$23") (pin "P$3") (pinfunction "A3_P$3") (pintype "bidirectional"))
      (node (ref "U$23") (pin "P$31") (pinfunction "B1_P$31") (pintype "bidirectional"))
      (node (ref "U$23") (pin "P$32") (pinfunction "B2_P$32") (pintype "bidirectional"))
      (node (ref "U$23") (pin "P$39") (pinfunction "B9_P$39") (pintype "bidirectional"))
      (node (ref "U$23") (pin "P$4") (pinfunction "A4_P$4") (pintype "bidirectional"))
      (node (ref "U$23") (pin "P$46") (pinfunction "B16_P$46") (pintype "bidirectional"))
      (node (ref "U$23") (pin "P$5") (pinfunction "A5_P$5") (pintype "bidirectional"))
      (node (ref "U$23") (pin "P$53") (pinfunction "B23_P$53") (pintype "bidirectional"))
      (node (ref "U$23") (pin "P$6") (pinfunction "A6_P$6") (pintype "bidirectional"))
      (node (ref "U$23") (pin "P$60") (pinfunction "B30_P$60") (pintype "bidirectional"))
      (node (ref "U$23") (pin "P$61") (pinfunction "C1_P$61") (pintype "bidirectional"))
      (node (ref "U$23") (pin "P$62") (pinfunction "C2_P$62") (pintype "bidirectional"))
      (node (ref "U$23") (pin "P$69") (pinfunction "C9_P$69") (pintype "bidirectional"))
      (node (ref "U$23") (pin "P$7") (pinfunction "A7_P$7") (pintype "bidirectional"))
      (node (ref "U$23") (pin "P$76") (pinfunction "C16_P$76") (pintype "bidirectional"))
      (node (ref "U$23") (pin "P$8") (pinfunction "A8_P$8") (pintype "bidirectional"))
      (node (ref "U$23") (pin "P$83") (pinfunction "C23_P$83") (pintype "bidirectional"))
      (node (ref "U$23") (pin "P$9") (pinfunction "A9_P$9") (pintype "bidirectional"))
      (node (ref "U$23") (pin "P$90") (pinfunction "C30_P$90") (pintype "bidirectional"))
      (node (ref "U$23") (pin "P$91") (pinfunction "D1_P$91") (pintype "bidirectional"))
      (node (ref "U$23") (pin "P$92") (pinfunction "D2_P$92") (pintype "bidirectional"))
      (node (ref "U$23") (pin "P$99") (pinfunction "D9_P$99") (pintype "bidirectional"))
      (node (ref "U$24") (pin "P$1") (pinfunction "A1_P$1") (pintype "bidirectional"))
      (node (ref "U$24") (pin "P$10") (pinfunction "A10_P$10") (pintype "bidirectional"))
      (node (ref "U$24") (pin "P$106") (pinfunction "D16_P$106") (pintype "bidirectional"))
      (node (ref "U$24") (pin "P$11") (pinfunction "A11_P$11") (pintype "bidirectional"))
      (node (ref "U$24") (pin "P$113") (pinfunction "D23_P$113") (pintype "bidirectional"))
      (node (ref "U$24") (pin "P$12") (pinfunction "A12_P$12") (pintype "bidirectional"))
      (node (ref "U$24") (pin "P$120") (pinfunction "D30_P$120") (pintype "bidirectional"))
      (node (ref "U$24") (pin "P$121") (pinfunction "E1_P$121") (pintype "bidirectional"))
      (node (ref "U$24") (pin "P$13") (pinfunction "A13_P$13") (pintype "bidirectional"))
      (node (ref "U$24") (pin "P$14") (pinfunction "A14_P$14") (pintype "bidirectional"))
      (node (ref "U$24") (pin "P$15") (pinfunction "A15_P$15") (pintype "bidirectional"))
      (node (ref "U$24") (pin "P$150") (pinfunction "E30_P$150") (pintype "bidirectional"))
      (node (ref "U$24") (pin "P$151") (pinfunction "F1_P$151") (pintype "bidirectional"))
      (node (ref "U$24") (pin "P$16") (pinfunction "A16_P$16") (pintype "bidirectional"))
      (node (ref "U$24") (pin "P$17") (pinfunction "A17_P$17") (pintype "bidirectional"))
      (node (ref "U$24") (pin "P$18") (pinfunction "A18_P$18") (pintype "bidirectional"))
      (node (ref "U$24") (pin "P$180") (pinfunction "F30_P$180") (pintype "bidirectional"))
      (node (ref "U$24") (pin "P$19") (pinfunction "A19_P$19") (pintype "bidirectional"))
      (node (ref "U$24") (pin "P$2") (pinfunction "A2_P$2") (pintype "bidirectional"))
      (node (ref "U$24") (pin "P$20") (pinfunction "A20_P$20") (pintype "bidirectional"))
      (node (ref "U$24") (pin "P$21") (pinfunction "A21_P$21") (pintype "bidirectional"))
      (node (ref "U$24") (pin "P$22") (pinfunction "A22_P$22") (pintype "bidirectional"))
      (node (ref "U$24") (pin "P$23") (pinfunction "A23_P$23") (pintype "bidirectional"))
      (node (ref "U$24") (pin "P$24") (pinfunction "A24_P$24") (pintype "bidirectional"))
      (node (ref "U$24") (pin "P$25") (pinfunction "A25_P$25") (pintype "bidirectional"))
      (node (ref "U$24") (pin "P$26") (pinfunction "A26_P$26") (pintype "bidirectional"))
      (node (ref "U$24") (pin "P$27") (pinfunction "A27_P$27") (pintype "bidirectional"))
      (node (ref "U$24") (pin "P$28") (pinfunction "A28_P$28") (pintype "bidirectional"))
      (node (ref "U$24") (pin "P$29") (pinfunction "A29_P$29") (pintype "bidirectional"))
      (node (ref "U$24") (pin "P$3") (pinfunction "A3_P$3") (pintype "bidirectional"))
      (node (ref "U$24") (pin "P$31") (pinfunction "B1_P$31") (pintype "bidirectional"))
      (node (ref "U$24") (pin "P$32") (pinfunction "B2_P$32") (pintype "bidirectional"))
      (node (ref "U$24") (pin "P$39") (pinfunction "B9_P$39") (pintype "bidirectional"))
      (node (ref "U$24") (pin "P$4") (pinfunction "A4_P$4") (pintype "bidirectional"))
      (node (ref "U$24") (pin "P$46") (pinfunction "B16_P$46") (pintype "bidirectional"))
      (node (ref "U$24") (pin "P$5") (pinfunction "A5_P$5") (pintype "bidirectional"))
      (node (ref "U$24") (pin "P$53") (pinfunction "B23_P$53") (pintype "bidirectional"))
      (node (ref "U$24") (pin "P$6") (pinfunction "A6_P$6") (pintype "bidirectional"))
      (node (ref "U$24") (pin "P$60") (pinfunction "B30_P$60") (pintype "bidirectional"))
      (node (ref "U$24") (pin "P$61") (pinfunction "C1_P$61") (pintype "bidirectional"))
      (node (ref "U$24") (pin "P$62") (pinfunction "C2_P$62") (pintype "bidirectional"))
      (node (ref "U$24") (pin "P$69") (pinfunction "C9_P$69") (pintype "bidirectional"))
      (node (ref "U$24") (pin "P$7") (pinfunction "A7_P$7") (pintype "bidirectional"))
      (node (ref "U$24") (pin "P$76") (pinfunction "C16_P$76") (pintype "bidirectional"))
      (node (ref "U$24") (pin "P$8") (pinfunction "A8_P$8") (pintype "bidirectional"))
      (node (ref "U$24") (pin "P$83") (pinfunction "C23_P$83") (pintype "bidirectional"))
      (node (ref "U$24") (pin "P$9") (pinfunction "A9_P$9") (pintype "bidirectional"))
      (node (ref "U$24") (pin "P$90") (pinfunction "C30_P$90") (pintype "bidirectional"))
      (node (ref "U$24") (pin "P$91") (pinfunction "D1_P$91") (pintype "bidirectional"))
      (node (ref "U$24") (pin "P$92") (pinfunction "D2_P$92") (pintype "bidirectional"))
      (node (ref "U$24") (pin "P$99") (pinfunction "D9_P$99") (pintype "bidirectional"))
      (node (ref "U$25") (pin "P$1") (pinfunction "GND_P$1") (pintype "bidirectional"))
      (node (ref "U$26") (pin "P$1") (pinfunction "GND_P$1") (pintype "bidirectional"))
      (node (ref "U$27") (pin "P$1") (pinfunction "GND_P$1") (pintype "bidirectional"))
      (node (ref "U$28") (pin "P$1") (pinfunction "GND_P$1") (pintype "bidirectional"))
      (node (ref "U$29") (pin "P$1") (pinfunction "GND_P$1") (pintype "bidirectional"))
      (node (ref "U$3") (pin "P$1") (pinfunction "A1_P$1") (pintype "bidirectional"))
      (node (ref "U$3") (pin "P$10") (pinfunction "A10_P$10") (pintype "bidirectional"))
      (node (ref "U$3") (pin "P$106") (pinfunction "D16_P$106") (pintype "bidirectional"))
      (node (ref "U$3") (pin "P$11") (pinfunction "A11_P$11") (pintype "bidirectional"))
      (node (ref "U$3") (pin "P$113") (pinfunction "D23_P$113") (pintype "bidirectional"))
      (node (ref "U$3") (pin "P$12") (pinfunction "A12_P$12") (pintype "bidirectional"))
      (node (ref "U$3") (pin "P$120") (pinfunction "D30_P$120") (pintype "bidirectional"))
      (node (ref "U$3") (pin "P$121") (pinfunction "E1_P$121") (pintype "bidirectional"))
      (node (ref "U$3") (pin "P$13") (pinfunction "A13_P$13") (pintype "bidirectional"))
      (node (ref "U$3") (pin "P$14") (pinfunction "A14_P$14") (pintype "bidirectional"))
      (node (ref "U$3") (pin "P$15") (pinfunction "A15_P$15") (pintype "bidirectional"))
      (node (ref "U$3") (pin "P$150") (pinfunction "E30_P$150") (pintype "bidirectional"))
      (node (ref "U$3") (pin "P$151") (pinfunction "F1_P$151") (pintype "bidirectional"))
      (node (ref "U$3") (pin "P$16") (pinfunction "A16_P$16") (pintype "bidirectional"))
      (node (ref "U$3") (pin "P$17") (pinfunction "A17_P$17") (pintype "bidirectional"))
      (node (ref "U$3") (pin "P$18") (pinfunction "A18_P$18") (pintype "bidirectional"))
      (node (ref "U$3") (pin "P$180") (pinfunction "F30_P$180") (pintype "bidirectional"))
      (node (ref "U$3") (pin "P$19") (pinfunction "A19_P$19") (pintype "bidirectional"))
      (node (ref "U$3") (pin "P$2") (pinfunction "A2_P$2") (pintype "bidirectional"))
      (node (ref "U$3") (pin "P$20") (pinfunction "A20_P$20") (pintype "bidirectional"))
      (node (ref "U$3") (pin "P$21") (pinfunction "A21_P$21") (pintype "bidirectional"))
      (node (ref "U$3") (pin "P$22") (pinfunction "A22_P$22") (pintype "bidirectional"))
      (node (ref "U$3") (pin "P$23") (pinfunction "A23_P$23") (pintype "bidirectional"))
      (node (ref "U$3") (pin "P$24") (pinfunction "A24_P$24") (pintype "bidirectional"))
      (node (ref "U$3") (pin "P$25") (pinfunction "A25_P$25") (pintype "bidirectional"))
      (node (ref "U$3") (pin "P$26") (pinfunction "A26_P$26") (pintype "bidirectional"))
      (node (ref "U$3") (pin "P$27") (pinfunction "A27_P$27") (pintype "bidirectional"))
      (node (ref "U$3") (pin "P$28") (pinfunction "A28_P$28") (pintype "bidirectional"))
      (node (ref "U$3") (pin "P$29") (pinfunction "A29_P$29") (pintype "bidirectional"))
      (node (ref "U$3") (pin "P$3") (pinfunction "A3_P$3") (pintype "bidirectional"))
      (node (ref "U$3") (pin "P$31") (pinfunction "B1_P$31") (pintype "bidirectional"))
      (node (ref "U$3") (pin "P$32") (pinfunction "B2_P$32") (pintype "bidirectional"))
      (node (ref "U$3") (pin "P$39") (pinfunction "B9_P$39") (pintype "bidirectional"))
      (node (ref "U$3") (pin "P$4") (pinfunction "A4_P$4") (pintype "bidirectional"))
      (node (ref "U$3") (pin "P$46") (pinfunction "B16_P$46") (pintype "bidirectional"))
      (node (ref "U$3") (pin "P$5") (pinfunction "A5_P$5") (pintype "bidirectional"))
      (node (ref "U$3") (pin "P$53") (pinfunction "B23_P$53") (pintype "bidirectional"))
      (node (ref "U$3") (pin "P$6") (pinfunction "A6_P$6") (pintype "bidirectional"))
      (node (ref "U$3") (pin "P$60") (pinfunction "B30_P$60") (pintype "bidirectional"))
      (node (ref "U$3") (pin "P$61") (pinfunction "C1_P$61") (pintype "bidirectional"))
      (node (ref "U$3") (pin "P$62") (pinfunction "C2_P$62") (pintype "bidirectional"))
      (node (ref "U$3") (pin "P$69") (pinfunction "C9_P$69") (pintype "bidirectional"))
      (node (ref "U$3") (pin "P$7") (pinfunction "A7_P$7") (pintype "bidirectional"))
      (node (ref "U$3") (pin "P$76") (pinfunction "C16_P$76") (pintype "bidirectional"))
      (node (ref "U$3") (pin "P$8") (pinfunction "A8_P$8") (pintype "bidirectional"))
      (node (ref "U$3") (pin "P$83") (pinfunction "C23_P$83") (pintype "bidirectional"))
      (node (ref "U$3") (pin "P$9") (pinfunction "A9_P$9") (pintype "bidirectional"))
      (node (ref "U$3") (pin "P$90") (pinfunction "C30_P$90") (pintype "bidirectional"))
      (node (ref "U$3") (pin "P$91") (pinfunction "D1_P$91") (pintype "bidirectional"))
      (node (ref "U$3") (pin "P$92") (pinfunction "D2_P$92") (pintype "bidirectional"))
      (node (ref "U$3") (pin "P$99") (pinfunction "D9_P$99") (pintype "bidirectional"))
      (node (ref "U$30") (pin "P$1") (pinfunction "GND_P$1") (pintype "bidirectional"))
      (node (ref "U$31") (pin "P$1") (pinfunction "GND_P$1") (pintype "bidirectional"))
      (node (ref "U$32") (pin "P$1") (pinfunction "GND_P$1") (pintype "bidirectional"))
      (node (ref "U$33") (pin "P$1") (pinfunction "GND_P$1") (pintype "bidirectional"))
      (node (ref "U$34") (pin "P$1") (pinfunction "GND_P$1") (pintype "bidirectional"))
      (node (ref "U$35") (pin "P$1") (pinfunction "GND_P$1") (pintype "bidirectional"))
      (node (ref "U$36") (pin "P$1") (pinfunction "GND_P$1") (pintype "bidirectional"))
      (node (ref "U$4") (pin "P$1") (pinfunction "A1_P$1") (pintype "bidirectional"))
      (node (ref "U$4") (pin "P$10") (pinfunction "A10_P$10") (pintype "bidirectional"))
      (node (ref "U$4") (pin "P$106") (pinfunction "D16_P$106") (pintype "bidirectional"))
      (node (ref "U$4") (pin "P$11") (pinfunction "A11_P$11") (pintype "bidirectional"))
      (node (ref "U$4") (pin "P$113") (pinfunction "D23_P$113") (pintype "bidirectional"))
      (node (ref "U$4") (pin "P$12") (pinfunction "A12_P$12") (pintype "bidirectional"))
      (node (ref "U$4") (pin "P$120") (pinfunction "D30_P$120") (pintype "bidirectional"))
      (node (ref "U$4") (pin "P$121") (pinfunction "E1_P$121") (pintype "bidirectional"))
      (node (ref "U$4") (pin "P$13") (pinfunction "A13_P$13") (pintype "bidirectional"))
      (node (ref "U$4") (pin "P$14") (pinfunction "A14_P$14") (pintype "bidirectional"))
      (node (ref "U$4") (pin "P$15") (pinfunction "A15_P$15") (pintype "bidirectional"))
      (node (ref "U$4") (pin "P$150") (pinfunction "E30_P$150") (pintype "bidirectional"))
      (node (ref "U$4") (pin "P$151") (pinfunction "F1_P$151") (pintype "bidirectional"))
      (node (ref "U$4") (pin "P$16") (pinfunction "A16_P$16") (pintype "bidirectional"))
      (node (ref "U$4") (pin "P$17") (pinfunction "A17_P$17") (pintype "bidirectional"))
      (node (ref "U$4") (pin "P$18") (pinfunction "A18_P$18") (pintype "bidirectional"))
      (node (ref "U$4") (pin "P$180") (pinfunction "F30_P$180") (pintype "bidirectional"))
      (node (ref "U$4") (pin "P$19") (pinfunction "A19_P$19") (pintype "bidirectional"))
      (node (ref "U$4") (pin "P$2") (pinfunction "A2_P$2") (pintype "bidirectional"))
      (node (ref "U$4") (pin "P$20") (pinfunction "A20_P$20") (pintype "bidirectional"))
      (node (ref "U$4") (pin "P$21") (pinfunction "A21_P$21") (pintype "bidirectional"))
      (node (ref "U$4") (pin "P$22") (pinfunction "A22_P$22") (pintype "bidirectional"))
      (node (ref "U$4") (pin "P$23") (pinfunction "A23_P$23") (pintype "bidirectional"))
      (node (ref "U$4") (pin "P$24") (pinfunction "A24_P$24") (pintype "bidirectional"))
      (node (ref "U$4") (pin "P$25") (pinfunction "A25_P$25") (pintype "bidirectional"))
      (node (ref "U$4") (pin "P$26") (pinfunction "A26_P$26") (pintype "bidirectional"))
      (node (ref "U$4") (pin "P$27") (pinfunction "A27_P$27") (pintype "bidirectional"))
      (node (ref "U$4") (pin "P$28") (pinfunction "A28_P$28") (pintype "bidirectional"))
      (node (ref "U$4") (pin "P$29") (pinfunction "A29_P$29") (pintype "bidirectional"))
      (node (ref "U$4") (pin "P$3") (pinfunction "A3_P$3") (pintype "bidirectional"))
      (node (ref "U$4") (pin "P$31") (pinfunction "B1_P$31") (pintype "bidirectional"))
      (node (ref "U$4") (pin "P$32") (pinfunction "B2_P$32") (pintype "bidirectional"))
      (node (ref "U$4") (pin "P$39") (pinfunction "B9_P$39") (pintype "bidirectional"))
      (node (ref "U$4") (pin "P$4") (pinfunction "A4_P$4") (pintype "bidirectional"))
      (node (ref "U$4") (pin "P$46") (pinfunction "B16_P$46") (pintype "bidirectional"))
      (node (ref "U$4") (pin "P$5") (pinfunction "A5_P$5") (pintype "bidirectional"))
      (node (ref "U$4") (pin "P$53") (pinfunction "B23_P$53") (pintype "bidirectional"))
      (node (ref "U$4") (pin "P$6") (pinfunction "A6_P$6") (pintype "bidirectional"))
      (node (ref "U$4") (pin "P$60") (pinfunction "B30_P$60") (pintype "bidirectional"))
      (node (ref "U$4") (pin "P$61") (pinfunction "C1_P$61") (pintype "bidirectional"))
      (node (ref "U$4") (pin "P$62") (pinfunction "C2_P$62") (pintype "bidirectional"))
      (node (ref "U$4") (pin "P$69") (pinfunction "C9_P$69") (pintype "bidirectional"))
      (node (ref "U$4") (pin "P$7") (pinfunction "A7_P$7") (pintype "bidirectional"))
      (node (ref "U$4") (pin "P$76") (pinfunction "C16_P$76") (pintype "bidirectional"))
      (node (ref "U$4") (pin "P$8") (pinfunction "A8_P$8") (pintype "bidirectional"))
      (node (ref "U$4") (pin "P$83") (pinfunction "C23_P$83") (pintype "bidirectional"))
      (node (ref "U$4") (pin "P$9") (pinfunction "A9_P$9") (pintype "bidirectional"))
      (node (ref "U$4") (pin "P$90") (pinfunction "C30_P$90") (pintype "bidirectional"))
      (node (ref "U$4") (pin "P$91") (pinfunction "D1_P$91") (pintype "bidirectional"))
      (node (ref "U$4") (pin "P$92") (pinfunction "D2_P$92") (pintype "bidirectional"))
      (node (ref "U$4") (pin "P$99") (pinfunction "D9_P$99") (pintype "bidirectional"))
      (node (ref "U$5") (pin "P$1") (pinfunction "A1_P$1") (pintype "bidirectional"))
      (node (ref "U$5") (pin "P$10") (pinfunction "A10_P$10") (pintype "bidirectional"))
      (node (ref "U$5") (pin "P$106") (pinfunction "D16_P$106") (pintype "bidirectional"))
      (node (ref "U$5") (pin "P$11") (pinfunction "A11_P$11") (pintype "bidirectional"))
      (node (ref "U$5") (pin "P$113") (pinfunction "D23_P$113") (pintype "bidirectional"))
      (node (ref "U$5") (pin "P$12") (pinfunction "A12_P$12") (pintype "bidirectional"))
      (node (ref "U$5") (pin "P$120") (pinfunction "D30_P$120") (pintype "bidirectional"))
      (node (ref "U$5") (pin "P$121") (pinfunction "E1_P$121") (pintype "bidirectional"))
      (node (ref "U$5") (pin "P$13") (pinfunction "A13_P$13") (pintype "bidirectional"))
      (node (ref "U$5") (pin "P$14") (pinfunction "A14_P$14") (pintype "bidirectional"))
      (node (ref "U$5") (pin "P$15") (pinfunction "A15_P$15") (pintype "bidirectional"))
      (node (ref "U$5") (pin "P$150") (pinfunction "E30_P$150") (pintype "bidirectional"))
      (node (ref "U$5") (pin "P$151") (pinfunction "F1_P$151") (pintype "bidirectional"))
      (node (ref "U$5") (pin "P$16") (pinfunction "A16_P$16") (pintype "bidirectional"))
      (node (ref "U$5") (pin "P$17") (pinfunction "A17_P$17") (pintype "bidirectional"))
      (node (ref "U$5") (pin "P$18") (pinfunction "A18_P$18") (pintype "bidirectional"))
      (node (ref "U$5") (pin "P$180") (pinfunction "F30_P$180") (pintype "bidirectional"))
      (node (ref "U$5") (pin "P$19") (pinfunction "A19_P$19") (pintype "bidirectional"))
      (node (ref "U$5") (pin "P$2") (pinfunction "A2_P$2") (pintype "bidirectional"))
      (node (ref "U$5") (pin "P$20") (pinfunction "A20_P$20") (pintype "bidirectional"))
      (node (ref "U$5") (pin "P$21") (pinfunction "A21_P$21") (pintype "bidirectional"))
      (node (ref "U$5") (pin "P$22") (pinfunction "A22_P$22") (pintype "bidirectional"))
      (node (ref "U$5") (pin "P$23") (pinfunction "A23_P$23") (pintype "bidirectional"))
      (node (ref "U$5") (pin "P$24") (pinfunction "A24_P$24") (pintype "bidirectional"))
      (node (ref "U$5") (pin "P$25") (pinfunction "A25_P$25") (pintype "bidirectional"))
      (node (ref "U$5") (pin "P$26") (pinfunction "A26_P$26") (pintype "bidirectional"))
      (node (ref "U$5") (pin "P$27") (pinfunction "A27_P$27") (pintype "bidirectional"))
      (node (ref "U$5") (pin "P$28") (pinfunction "A28_P$28") (pintype "bidirectional"))
      (node (ref "U$5") (pin "P$29") (pinfunction "A29_P$29") (pintype "bidirectional"))
      (node (ref "U$5") (pin "P$3") (pinfunction "A3_P$3") (pintype "bidirectional"))
      (node (ref "U$5") (pin "P$31") (pinfunction "B1_P$31") (pintype "bidirectional"))
      (node (ref "U$5") (pin "P$32") (pinfunction "B2_P$32") (pintype "bidirectional"))
      (node (ref "U$5") (pin "P$39") (pinfunction "B9_P$39") (pintype "bidirectional"))
      (node (ref "U$5") (pin "P$4") (pinfunction "A4_P$4") (pintype "bidirectional"))
      (node (ref "U$5") (pin "P$46") (pinfunction "B16_P$46") (pintype "bidirectional"))
      (node (ref "U$5") (pin "P$5") (pinfunction "A5_P$5") (pintype "bidirectional"))
      (node (ref "U$5") (pin "P$53") (pinfunction "B23_P$53") (pintype "bidirectional"))
      (node (ref "U$5") (pin "P$6") (pinfunction "A6_P$6") (pintype "bidirectional"))
      (node (ref "U$5") (pin "P$60") (pinfunction "B30_P$60") (pintype "bidirectional"))
      (node (ref "U$5") (pin "P$61") (pinfunction "C1_P$61") (pintype "bidirectional"))
      (node (ref "U$5") (pin "P$62") (pinfunction "C2_P$62") (pintype "bidirectional"))
      (node (ref "U$5") (pin "P$69") (pinfunction "C9_P$69") (pintype "bidirectional"))
      (node (ref "U$5") (pin "P$7") (pinfunction "A7_P$7") (pintype "bidirectional"))
      (node (ref "U$5") (pin "P$76") (pinfunction "C16_P$76") (pintype "bidirectional"))
      (node (ref "U$5") (pin "P$8") (pinfunction "A8_P$8") (pintype "bidirectional"))
      (node (ref "U$5") (pin "P$83") (pinfunction "C23_P$83") (pintype "bidirectional"))
      (node (ref "U$5") (pin "P$9") (pinfunction "A9_P$9") (pintype "bidirectional"))
      (node (ref "U$5") (pin "P$90") (pinfunction "C30_P$90") (pintype "bidirectional"))
      (node (ref "U$5") (pin "P$91") (pinfunction "D1_P$91") (pintype "bidirectional"))
      (node (ref "U$5") (pin "P$92") (pinfunction "D2_P$92") (pintype "bidirectional"))
      (node (ref "U$5") (pin "P$99") (pinfunction "D9_P$99") (pintype "bidirectional"))
      (node (ref "U$6") (pin "P$1") (pinfunction "A1_P$1") (pintype "bidirectional"))
      (node (ref "U$6") (pin "P$10") (pinfunction "A10_P$10") (pintype "bidirectional"))
      (node (ref "U$6") (pin "P$106") (pinfunction "D16_P$106") (pintype "bidirectional"))
      (node (ref "U$6") (pin "P$11") (pinfunction "A11_P$11") (pintype "bidirectional"))
      (node (ref "U$6") (pin "P$113") (pinfunction "D23_P$113") (pintype "bidirectional"))
      (node (ref "U$6") (pin "P$12") (pinfunction "A12_P$12") (pintype "bidirectional"))
      (node (ref "U$6") (pin "P$120") (pinfunction "D30_P$120") (pintype "bidirectional"))
      (node (ref "U$6") (pin "P$121") (pinfunction "E1_P$121") (pintype "bidirectional"))
      (node (ref "U$6") (pin "P$13") (pinfunction "A13_P$13") (pintype "bidirectional"))
      (node (ref "U$6") (pin "P$14") (pinfunction "A14_P$14") (pintype "bidirectional"))
      (node (ref "U$6") (pin "P$15") (pinfunction "A15_P$15") (pintype "bidirectional"))
      (node (ref "U$6") (pin "P$150") (pinfunction "E30_P$150") (pintype "bidirectional"))
      (node (ref "U$6") (pin "P$151") (pinfunction "F1_P$151") (pintype "bidirectional"))
      (node (ref "U$6") (pin "P$16") (pinfunction "A16_P$16") (pintype "bidirectional"))
      (node (ref "U$6") (pin "P$17") (pinfunction "A17_P$17") (pintype "bidirectional"))
      (node (ref "U$6") (pin "P$18") (pinfunction "A18_P$18") (pintype "bidirectional"))
      (node (ref "U$6") (pin "P$180") (pinfunction "F30_P$180") (pintype "bidirectional"))
      (node (ref "U$6") (pin "P$19") (pinfunction "A19_P$19") (pintype "bidirectional"))
      (node (ref "U$6") (pin "P$2") (pinfunction "A2_P$2") (pintype "bidirectional"))
      (node (ref "U$6") (pin "P$20") (pinfunction "A20_P$20") (pintype "bidirectional"))
      (node (ref "U$6") (pin "P$21") (pinfunction "A21_P$21") (pintype "bidirectional"))
      (node (ref "U$6") (pin "P$22") (pinfunction "A22_P$22") (pintype "bidirectional"))
      (node (ref "U$6") (pin "P$23") (pinfunction "A23_P$23") (pintype "bidirectional"))
      (node (ref "U$6") (pin "P$24") (pinfunction "A24_P$24") (pintype "bidirectional"))
      (node (ref "U$6") (pin "P$25") (pinfunction "A25_P$25") (pintype "bidirectional"))
      (node (ref "U$6") (pin "P$26") (pinfunction "A26_P$26") (pintype "bidirectional"))
      (node (ref "U$6") (pin "P$27") (pinfunction "A27_P$27") (pintype "bidirectional"))
      (node (ref "U$6") (pin "P$28") (pinfunction "A28_P$28") (pintype "bidirectional"))
      (node (ref "U$6") (pin "P$29") (pinfunction "A29_P$29") (pintype "bidirectional"))
      (node (ref "U$6") (pin "P$3") (pinfunction "A3_P$3") (pintype "bidirectional"))
      (node (ref "U$6") (pin "P$31") (pinfunction "B1_P$31") (pintype "bidirectional"))
      (node (ref "U$6") (pin "P$32") (pinfunction "B2_P$32") (pintype "bidirectional"))
      (node (ref "U$6") (pin "P$39") (pinfunction "B9_P$39") (pintype "bidirectional"))
      (node (ref "U$6") (pin "P$4") (pinfunction "A4_P$4") (pintype "bidirectional"))
      (node (ref "U$6") (pin "P$46") (pinfunction "B16_P$46") (pintype "bidirectional"))
      (node (ref "U$6") (pin "P$5") (pinfunction "A5_P$5") (pintype "bidirectional"))
      (node (ref "U$6") (pin "P$53") (pinfunction "B23_P$53") (pintype "bidirectional"))
      (node (ref "U$6") (pin "P$6") (pinfunction "A6_P$6") (pintype "bidirectional"))
      (node (ref "U$6") (pin "P$60") (pinfunction "B30_P$60") (pintype "bidirectional"))
      (node (ref "U$6") (pin "P$61") (pinfunction "C1_P$61") (pintype "bidirectional"))
      (node (ref "U$6") (pin "P$62") (pinfunction "C2_P$62") (pintype "bidirectional"))
      (node (ref "U$6") (pin "P$69") (pinfunction "C9_P$69") (pintype "bidirectional"))
      (node (ref "U$6") (pin "P$7") (pinfunction "A7_P$7") (pintype "bidirectional"))
      (node (ref "U$6") (pin "P$76") (pinfunction "C16_P$76") (pintype "bidirectional"))
      (node (ref "U$6") (pin "P$8") (pinfunction "A8_P$8") (pintype "bidirectional"))
      (node (ref "U$6") (pin "P$83") (pinfunction "C23_P$83") (pintype "bidirectional"))
      (node (ref "U$6") (pin "P$9") (pinfunction "A9_P$9") (pintype "bidirectional"))
      (node (ref "U$6") (pin "P$90") (pinfunction "C30_P$90") (pintype "bidirectional"))
      (node (ref "U$6") (pin "P$91") (pinfunction "D1_P$91") (pintype "bidirectional"))
      (node (ref "U$6") (pin "P$92") (pinfunction "D2_P$92") (pintype "bidirectional"))
      (node (ref "U$6") (pin "P$99") (pinfunction "D9_P$99") (pintype "bidirectional"))
      (node (ref "U$7") (pin "P$1") (pinfunction "A1_P$1") (pintype "bidirectional"))
      (node (ref "U$7") (pin "P$10") (pinfunction "A10_P$10") (pintype "bidirectional"))
      (node (ref "U$7") (pin "P$106") (pinfunction "D16_P$106") (pintype "bidirectional"))
      (node (ref "U$7") (pin "P$11") (pinfunction "A11_P$11") (pintype "bidirectional"))
      (node (ref "U$7") (pin "P$113") (pinfunction "D23_P$113") (pintype "bidirectional"))
      (node (ref "U$7") (pin "P$12") (pinfunction "A12_P$12") (pintype "bidirectional"))
      (node (ref "U$7") (pin "P$120") (pinfunction "D30_P$120") (pintype "bidirectional"))
      (node (ref "U$7") (pin "P$121") (pinfunction "E1_P$121") (pintype "bidirectional"))
      (node (ref "U$7") (pin "P$13") (pinfunction "A13_P$13") (pintype "bidirectional"))
      (node (ref "U$7") (pin "P$14") (pinfunction "A14_P$14") (pintype "bidirectional"))
      (node (ref "U$7") (pin "P$15") (pinfunction "A15_P$15") (pintype "bidirectional"))
      (node (ref "U$7") (pin "P$150") (pinfunction "E30_P$150") (pintype "bidirectional"))
      (node (ref "U$7") (pin "P$151") (pinfunction "F1_P$151") (pintype "bidirectional"))
      (node (ref "U$7") (pin "P$16") (pinfunction "A16_P$16") (pintype "bidirectional"))
      (node (ref "U$7") (pin "P$17") (pinfunction "A17_P$17") (pintype "bidirectional"))
      (node (ref "U$7") (pin "P$18") (pinfunction "A18_P$18") (pintype "bidirectional"))
      (node (ref "U$7") (pin "P$180") (pinfunction "F30_P$180") (pintype "bidirectional"))
      (node (ref "U$7") (pin "P$19") (pinfunction "A19_P$19") (pintype "bidirectional"))
      (node (ref "U$7") (pin "P$2") (pinfunction "A2_P$2") (pintype "bidirectional"))
      (node (ref "U$7") (pin "P$20") (pinfunction "A20_P$20") (pintype "bidirectional"))
      (node (ref "U$7") (pin "P$21") (pinfunction "A21_P$21") (pintype "bidirectional"))
      (node (ref "U$7") (pin "P$22") (pinfunction "A22_P$22") (pintype "bidirectional"))
      (node (ref "U$7") (pin "P$23") (pinfunction "A23_P$23") (pintype "bidirectional"))
      (node (ref "U$7") (pin "P$24") (pinfunction "A24_P$24") (pintype "bidirectional"))
      (node (ref "U$7") (pin "P$25") (pinfunction "A25_P$25") (pintype "bidirectional"))
      (node (ref "U$7") (pin "P$26") (pinfunction "A26_P$26") (pintype "bidirectional"))
      (node (ref "U$7") (pin "P$27") (pinfunction "A27_P$27") (pintype "bidirectional"))
      (node (ref "U$7") (pin "P$28") (pinfunction "A28_P$28") (pintype "bidirectional"))
      (node (ref "U$7") (pin "P$29") (pinfunction "A29_P$29") (pintype "bidirectional"))
      (node (ref "U$7") (pin "P$3") (pinfunction "A3_P$3") (pintype "bidirectional"))
      (node (ref "U$7") (pin "P$31") (pinfunction "B1_P$31") (pintype "bidirectional"))
      (node (ref "U$7") (pin "P$32") (pinfunction "B2_P$32") (pintype "bidirectional"))
      (node (ref "U$7") (pin "P$39") (pinfunction "B9_P$39") (pintype "bidirectional"))
      (node (ref "U$7") (pin "P$4") (pinfunction "A4_P$4") (pintype "bidirectional"))
      (node (ref "U$7") (pin "P$46") (pinfunction "B16_P$46") (pintype "bidirectional"))
      (node (ref "U$7") (pin "P$5") (pinfunction "A5_P$5") (pintype "bidirectional"))
      (node (ref "U$7") (pin "P$53") (pinfunction "B23_P$53") (pintype "bidirectional"))
      (node (ref "U$7") (pin "P$6") (pinfunction "A6_P$6") (pintype "bidirectional"))
      (node (ref "U$7") (pin "P$60") (pinfunction "B30_P$60") (pintype "bidirectional"))
      (node (ref "U$7") (pin "P$61") (pinfunction "C1_P$61") (pintype "bidirectional"))
      (node (ref "U$7") (pin "P$62") (pinfunction "C2_P$62") (pintype "bidirectional"))
      (node (ref "U$7") (pin "P$69") (pinfunction "C9_P$69") (pintype "bidirectional"))
      (node (ref "U$7") (pin "P$7") (pinfunction "A7_P$7") (pintype "bidirectional"))
      (node (ref "U$7") (pin "P$76") (pinfunction "C16_P$76") (pintype "bidirectional"))
      (node (ref "U$7") (pin "P$8") (pinfunction "A8_P$8") (pintype "bidirectional"))
      (node (ref "U$7") (pin "P$83") (pinfunction "C23_P$83") (pintype "bidirectional"))
      (node (ref "U$7") (pin "P$9") (pinfunction "A9_P$9") (pintype "bidirectional"))
      (node (ref "U$7") (pin "P$90") (pinfunction "C30_P$90") (pintype "bidirectional"))
      (node (ref "U$7") (pin "P$91") (pinfunction "D1_P$91") (pintype "bidirectional"))
      (node (ref "U$7") (pin "P$92") (pinfunction "D2_P$92") (pintype "bidirectional"))
      (node (ref "U$7") (pin "P$99") (pinfunction "D9_P$99") (pintype "bidirectional"))
      (node (ref "U$8") (pin "P$1") (pinfunction "A1_P$1") (pintype "bidirectional"))
      (node (ref "U$8") (pin "P$10") (pinfunction "A10_P$10") (pintype "bidirectional"))
      (node (ref "U$8") (pin "P$106") (pinfunction "D16_P$106") (pintype "bidirectional"))
      (node (ref "U$8") (pin "P$11") (pinfunction "A11_P$11") (pintype "bidirectional"))
      (node (ref "U$8") (pin "P$113") (pinfunction "D23_P$113") (pintype "bidirectional"))
      (node (ref "U$8") (pin "P$12") (pinfunction "A12_P$12") (pintype "bidirectional"))
      (node (ref "U$8") (pin "P$120") (pinfunction "D30_P$120") (pintype "bidirectional"))
      (node (ref "U$8") (pin "P$121") (pinfunction "E1_P$121") (pintype "bidirectional"))
      (node (ref "U$8") (pin "P$13") (pinfunction "A13_P$13") (pintype "bidirectional"))
      (node (ref "U$8") (pin "P$14") (pinfunction "A14_P$14") (pintype "bidirectional"))
      (node (ref "U$8") (pin "P$15") (pinfunction "A15_P$15") (pintype "bidirectional"))
      (node (ref "U$8") (pin "P$150") (pinfunction "E30_P$150") (pintype "bidirectional"))
      (node (ref "U$8") (pin "P$151") (pinfunction "F1_P$151") (pintype "bidirectional"))
      (node (ref "U$8") (pin "P$16") (pinfunction "A16_P$16") (pintype "bidirectional"))
      (node (ref "U$8") (pin "P$17") (pinfunction "A17_P$17") (pintype "bidirectional"))
      (node (ref "U$8") (pin "P$18") (pinfunction "A18_P$18") (pintype "bidirectional"))
      (node (ref "U$8") (pin "P$180") (pinfunction "F30_P$180") (pintype "bidirectional"))
      (node (ref "U$8") (pin "P$19") (pinfunction "A19_P$19") (pintype "bidirectional"))
      (node (ref "U$8") (pin "P$2") (pinfunction "A2_P$2") (pintype "bidirectional"))
      (node (ref "U$8") (pin "P$20") (pinfunction "A20_P$20") (pintype "bidirectional"))
      (node (ref "U$8") (pin "P$21") (pinfunction "A21_P$21") (pintype "bidirectional"))
      (node (ref "U$8") (pin "P$22") (pinfunction "A22_P$22") (pintype "bidirectional"))
      (node (ref "U$8") (pin "P$23") (pinfunction "A23_P$23") (pintype "bidirectional"))
      (node (ref "U$8") (pin "P$24") (pinfunction "A24_P$24") (pintype "bidirectional"))
      (node (ref "U$8") (pin "P$25") (pinfunction "A25_P$25") (pintype "bidirectional"))
      (node (ref "U$8") (pin "P$26") (pinfunction "A26_P$26") (pintype "bidirectional"))
      (node (ref "U$8") (pin "P$27") (pinfunction "A27_P$27") (pintype "bidirectional"))
      (node (ref "U$8") (pin "P$28") (pinfunction "A28_P$28") (pintype "bidirectional"))
      (node (ref "U$8") (pin "P$29") (pinfunction "A29_P$29") (pintype "bidirectional"))
      (node (ref "U$8") (pin "P$3") (pinfunction "A3_P$3") (pintype "bidirectional"))
      (node (ref "U$8") (pin "P$31") (pinfunction "B1_P$31") (pintype "bidirectional"))
      (node (ref "U$8") (pin "P$32") (pinfunction "B2_P$32") (pintype "bidirectional"))
      (node (ref "U$8") (pin "P$39") (pinfunction "B9_P$39") (pintype "bidirectional"))
      (node (ref "U$8") (pin "P$4") (pinfunction "A4_P$4") (pintype "bidirectional"))
      (node (ref "U$8") (pin "P$46") (pinfunction "B16_P$46") (pintype "bidirectional"))
      (node (ref "U$8") (pin "P$5") (pinfunction "A5_P$5") (pintype "bidirectional"))
      (node (ref "U$8") (pin "P$53") (pinfunction "B23_P$53") (pintype "bidirectional"))
      (node (ref "U$8") (pin "P$6") (pinfunction "A6_P$6") (pintype "bidirectional"))
      (node (ref "U$8") (pin "P$60") (pinfunction "B30_P$60") (pintype "bidirectional"))
      (node (ref "U$8") (pin "P$61") (pinfunction "C1_P$61") (pintype "bidirectional"))
      (node (ref "U$8") (pin "P$62") (pinfunction "C2_P$62") (pintype "bidirectional"))
      (node (ref "U$8") (pin "P$69") (pinfunction "C9_P$69") (pintype "bidirectional"))
      (node (ref "U$8") (pin "P$7") (pinfunction "A7_P$7") (pintype "bidirectional"))
      (node (ref "U$8") (pin "P$76") (pinfunction "C16_P$76") (pintype "bidirectional"))
      (node (ref "U$8") (pin "P$8") (pinfunction "A8_P$8") (pintype "bidirectional"))
      (node (ref "U$8") (pin "P$83") (pinfunction "C23_P$83") (pintype "bidirectional"))
      (node (ref "U$8") (pin "P$9") (pinfunction "A9_P$9") (pintype "bidirectional"))
      (node (ref "U$8") (pin "P$90") (pinfunction "C30_P$90") (pintype "bidirectional"))
      (node (ref "U$8") (pin "P$91") (pinfunction "D1_P$91") (pintype "bidirectional"))
      (node (ref "U$8") (pin "P$92") (pinfunction "D2_P$92") (pintype "bidirectional"))
      (node (ref "U$8") (pin "P$99") (pinfunction "D9_P$99") (pintype "bidirectional"))
      (node (ref "U$9") (pin "P$1") (pinfunction "A1_P$1") (pintype "bidirectional"))
      (node (ref "U$9") (pin "P$10") (pinfunction "A10_P$10") (pintype "bidirectional"))
      (node (ref "U$9") (pin "P$106") (pinfunction "D16_P$106") (pintype "bidirectional"))
      (node (ref "U$9") (pin "P$11") (pinfunction "A11_P$11") (pintype "bidirectional"))
      (node (ref "U$9") (pin "P$113") (pinfunction "D23_P$113") (pintype "bidirectional"))
      (node (ref "U$9") (pin "P$12") (pinfunction "A12_P$12") (pintype "bidirectional"))
      (node (ref "U$9") (pin "P$120") (pinfunction "D30_P$120") (pintype "bidirectional"))
      (node (ref "U$9") (pin "P$121") (pinfunction "E1_P$121") (pintype "bidirectional"))
      (node (ref "U$9") (pin "P$13") (pinfunction "A13_P$13") (pintype "bidirectional"))
      (node (ref "U$9") (pin "P$14") (pinfunction "A14_P$14") (pintype "bidirectional"))
      (node (ref "U$9") (pin "P$15") (pinfunction "A15_P$15") (pintype "bidirectional"))
      (node (ref "U$9") (pin "P$150") (pinfunction "E30_P$150") (pintype "bidirectional"))
      (node (ref "U$9") (pin "P$151") (pinfunction "F1_P$151") (pintype "bidirectional"))
      (node (ref "U$9") (pin "P$16") (pinfunction "A16_P$16") (pintype "bidirectional"))
      (node (ref "U$9") (pin "P$17") (pinfunction "A17_P$17") (pintype "bidirectional"))
      (node (ref "U$9") (pin "P$18") (pinfunction "A18_P$18") (pintype "bidirectional"))
      (node (ref "U$9") (pin "P$180") (pinfunction "F30_P$180") (pintype "bidirectional"))
      (node (ref "U$9") (pin "P$19") (pinfunction "A19_P$19") (pintype "bidirectional"))
      (node (ref "U$9") (pin "P$2") (pinfunction "A2_P$2") (pintype "bidirectional"))
      (node (ref "U$9") (pin "P$20") (pinfunction "A20_P$20") (pintype "bidirectional"))
      (node (ref "U$9") (pin "P$21") (pinfunction "A21_P$21") (pintype "bidirectional"))
      (node (ref "U$9") (pin "P$22") (pinfunction "A22_P$22") (pintype "bidirectional"))
      (node (ref "U$9") (pin "P$23") (pinfunction "A23_P$23") (pintype "bidirectional"))
      (node (ref "U$9") (pin "P$24") (pinfunction "A24_P$24") (pintype "bidirectional"))
      (node (ref "U$9") (pin "P$25") (pinfunction "A25_P$25") (pintype "bidirectional"))
      (node (ref "U$9") (pin "P$26") (pinfunction "A26_P$26") (pintype "bidirectional"))
      (node (ref "U$9") (pin "P$27") (pinfunction "A27_P$27") (pintype "bidirectional"))
      (node (ref "U$9") (pin "P$28") (pinfunction "A28_P$28") (pintype "bidirectional"))
      (node (ref "U$9") (pin "P$29") (pinfunction "A29_P$29") (pintype "bidirectional"))
      (node (ref "U$9") (pin "P$3") (pinfunction "A3_P$3") (pintype "bidirectional"))
      (node (ref "U$9") (pin "P$31") (pinfunction "B1_P$31") (pintype "bidirectional"))
      (node (ref "U$9") (pin "P$32") (pinfunction "B2_P$32") (pintype "bidirectional"))
      (node (ref "U$9") (pin "P$39") (pinfunction "B9_P$39") (pintype "bidirectional"))
      (node (ref "U$9") (pin "P$4") (pinfunction "A4_P$4") (pintype "bidirectional"))
      (node (ref "U$9") (pin "P$46") (pinfunction "B16_P$46") (pintype "bidirectional"))
      (node (ref "U$9") (pin "P$5") (pinfunction "A5_P$5") (pintype "bidirectional"))
      (node (ref "U$9") (pin "P$53") (pinfunction "B23_P$53") (pintype "bidirectional"))
      (node (ref "U$9") (pin "P$6") (pinfunction "A6_P$6") (pintype "bidirectional"))
      (node (ref "U$9") (pin "P$60") (pinfunction "B30_P$60") (pintype "bidirectional"))
      (node (ref "U$9") (pin "P$61") (pinfunction "C1_P$61") (pintype "bidirectional"))
      (node (ref "U$9") (pin "P$62") (pinfunction "C2_P$62") (pintype "bidirectional"))
      (node (ref "U$9") (pin "P$69") (pinfunction "C9_P$69") (pintype "bidirectional"))
      (node (ref "U$9") (pin "P$7") (pinfunction "A7_P$7") (pintype "bidirectional"))
      (node (ref "U$9") (pin "P$76") (pinfunction "C16_P$76") (pintype "bidirectional"))
      (node (ref "U$9") (pin "P$8") (pinfunction "A8_P$8") (pintype "bidirectional"))
      (node (ref "U$9") (pin "P$83") (pinfunction "C23_P$83") (pintype "bidirectional"))
      (node (ref "U$9") (pin "P$9") (pinfunction "A9_P$9") (pintype "bidirectional"))
      (node (ref "U$9") (pin "P$90") (pinfunction "C30_P$90") (pintype "bidirectional"))
      (node (ref "U$9") (pin "P$91") (pinfunction "D1_P$91") (pintype "bidirectional"))
      (node (ref "U$9") (pin "P$92") (pinfunction "D2_P$92") (pintype "bidirectional"))
      (node (ref "U$9") (pin "P$99") (pinfunction "D9_P$99") (pintype "bidirectional"))
    )
    (net (code "2") (name "Net-(U$1-A30)") (class "Default")
      (node (ref "U$1") (pin "P$30") (pinfunction "A30_P$30") (pintype "bidirectional"))
      (node (ref "U$25") (pin "P$2") (pinfunction "IO_P$2") (pintype "bidirectional"))
    )
    (net (code "3") (name "Net-(U$11-A30)") (class "Default")
      (node (ref "U$11") (pin "P$30") (pinfunction "A30_P$30") (pintype "bidirectional"))
      (node (ref "U$30") (pin "P$2") (pinfunction "IO_P$2") (pintype "bidirectional"))
    )
    (net (code "4") (name "Net-(U$13-A30)") (class "Default")
      (node (ref "U$13") (pin "P$30") (pinfunction "A30_P$30") (pintype "bidirectional"))
      (node (ref "U$31") (pin "P$2") (pinfunction "IO_P$2") (pintype "bidirectional"))
    )
    (net (code "5") (name "Net-(U$15-A30)") (class "Default")
      (node (ref "U$15") (pin "P$30") (pinfunction "A30_P$30") (pintype "bidirectional"))
      (node (ref "U$32") (pin "P$2") (pinfunction "IO_P$2") (pintype "bidirectional"))
    )
    (net (code "6") (name "Net-(U$17-A30)") (class "Default")
      (node (ref "U$17") (pin "P$30") (pinfunction "A30_P$30") (pintype "bidirectional"))
      (node (ref "U$33") (pin "P$2") (pinfunction "IO_P$2") (pintype "bidirectional"))
    )
    (net (code "7") (name "Net-(U$19-A30)") (class "Default")
      (node (ref "U$19") (pin "P$30") (pinfunction "A30_P$30") (pintype "bidirectional"))
      (node (ref "U$34") (pin "P$2") (pinfunction "IO_P$2") (pintype "bidirectional"))
    )
    (net (code "8") (name "Net-(U$21-A30)") (class "Default")
      (node (ref "U$21") (pin "P$30") (pinfunction "A30_P$30") (pintype "bidirectional"))
      (node (ref "U$35") (pin "P$2") (pinfunction "IO_P$2") (pintype "bidirectional"))
    )
    (net (code "9") (name "Net-(U$23-A30)") (class "Default")
      (node (ref "U$23") (pin "P$30") (pinfunction "A30_P$30") (pintype "bidirectional"))
      (node (ref "U$36") (pin "P$2") (pinfunction "IO_P$2") (pintype "bidirectional"))
    )
    (net (code "10") (name "Net-(U$26-IO)") (class "Default")
      (node (ref "U$26") (pin "P$2") (pinfunction "IO_P$2") (pintype "bidirectional"))
      (node (ref "U$3") (pin "P$30") (pinfunction "A30_P$30") (pintype "bidirectional"))
    )
    (net (code "11") (name "Net-(U$27-IO)") (class "Default")
      (node (ref "U$27") (pin "P$2") (pinfunction "IO_P$2") (pintype "bidirectional"))
      (node (ref "U$5") (pin "P$30") (pinfunction "A30_P$30") (pintype "bidirectional"))
    )
    (net (code "12") (name "Net-(U$28-IO)") (class "Default")
      (node (ref "U$28") (pin "P$2") (pinfunction "IO_P$2") (pintype "bidirectional"))
      (node (ref "U$7") (pin "P$30") (pinfunction "A30_P$30") (pintype "bidirectional"))
    )
    (net (code "13") (name "Net-(U$29-IO)") (class "Default")
      (node (ref "U$29") (pin "P$2") (pinfunction "IO_P$2") (pintype "bidirectional"))
      (node (ref "U$9") (pin "P$30") (pinfunction "A30_P$30") (pintype "bidirectional"))
    )
    (net (code "14") (name "ZZ.00.000") (class "Default")
      (node (ref "U$2") (pin "P$34") (pinfunction "B4_P$34") (pintype "bidirectional"))
    )
    (net (code "15") (name "ZZ.00.001") (class "Default")
      (node (ref "U$2") (pin "P$63") (pinfunction "C3_P$63") (pintype "bidirectional"))
    )
    (net (code "16") (name "ZZ.00.002") (class "Default")
      (node (ref "U$2") (pin "P$98") (pinfunction "D8_P$98") (pintype "bidirectional"))
    )
    (net (code "17") (name "ZZ.00.003") (class "Default")
      (node (ref "U$2") (pin "P$127") (pinfunction "E7_P$127") (pintype "bidirectional"))
    )
    (net (code "18") (name "ZZ.00.004") (class "Default")
      (node (ref "U$2") (pin "P$156") (pinfunction "F6_P$156") (pintype "bidirectional"))
    )
    (net (code "19") (name "ZZ.00.005") (class "Default")
      (node (ref "U$2") (pin "P$35") (pinfunction "B5_P$35") (pintype "bidirectional"))
    )
    (net (code "20") (name "ZZ.00.006") (class "Default")
      (node (ref "U$2") (pin "P$64") (pinfunction "C4_P$64") (pintype "bidirectional"))
    )
    (net (code "21") (name "ZZ.00.007") (class "Default")
      (node (ref "U$2") (pin "P$93") (pinfunction "D3_P$93") (pintype "bidirectional"))
    )
    (net (code "22") (name "ZZ.00.008") (class "Default")
      (node (ref "U$2") (pin "P$128") (pinfunction "E8_P$128") (pintype "bidirectional"))
    )
    (net (code "23") (name "ZZ.00.009") (class "Default")
      (node (ref "U$2") (pin "P$157") (pinfunction "F7_P$157") (pintype "bidirectional"))
    )
    (net (code "24") (name "ZZ.00.010") (class "Default")
      (node (ref "U$2") (pin "P$36") (pinfunction "B6_P$36") (pintype "bidirectional"))
    )
    (net (code "25") (name "ZZ.00.011") (class "Default")
      (node (ref "U$2") (pin "P$65") (pinfunction "C5_P$65") (pintype "bidirectional"))
    )
    (net (code "26") (name "ZZ.00.012") (class "Default")
      (node (ref "U$2") (pin "P$94") (pinfunction "D4_P$94") (pintype "bidirectional"))
    )
    (net (code "27") (name "ZZ.00.013") (class "Default")
      (node (ref "U$2") (pin "P$123") (pinfunction "E3_P$123") (pintype "bidirectional"))
    )
    (net (code "28") (name "ZZ.00.014") (class "Default")
      (node (ref "U$2") (pin "P$158") (pinfunction "F8_P$158") (pintype "bidirectional"))
    )
    (net (code "29") (name "ZZ.00.015") (class "Default")
      (node (ref "U$2") (pin "P$152") (pinfunction "F2_P$152") (pintype "bidirectional"))
    )
    (net (code "30") (name "ZZ.00.016") (class "Default")
      (node (ref "U$4") (pin "P$34") (pinfunction "B4_P$34") (pintype "bidirectional"))
    )
    (net (code "31") (name "ZZ.00.017") (class "Default")
      (node (ref "U$4") (pin "P$63") (pinfunction "C3_P$63") (pintype "bidirectional"))
    )
    (net (code "32") (name "ZZ.00.018") (class "Default")
      (node (ref "U$4") (pin "P$98") (pinfunction "D8_P$98") (pintype "bidirectional"))
    )
    (net (code "33") (name "ZZ.00.019") (class "Default")
      (node (ref "U$4") (pin "P$127") (pinfunction "E7_P$127") (pintype "bidirectional"))
    )
    (net (code "34") (name "ZZ.00.020") (class "Default")
      (node (ref "U$4") (pin "P$156") (pinfunction "F6_P$156") (pintype "bidirectional"))
    )
    (net (code "35") (name "ZZ.00.021") (class "Default")
      (node (ref "U$4") (pin "P$35") (pinfunction "B5_P$35") (pintype "bidirectional"))
    )
    (net (code "36") (name "ZZ.00.022") (class "Default")
      (node (ref "U$4") (pin "P$64") (pinfunction "C4_P$64") (pintype "bidirectional"))
    )
    (net (code "37") (name "ZZ.00.023") (class "Default")
      (node (ref "U$4") (pin "P$93") (pinfunction "D3_P$93") (pintype "bidirectional"))
    )
    (net (code "38") (name "ZZ.00.024") (class "Default")
      (node (ref "U$4") (pin "P$128") (pinfunction "E8_P$128") (pintype "bidirectional"))
    )
    (net (code "39") (name "ZZ.00.025") (class "Default")
      (node (ref "U$4") (pin "P$157") (pinfunction "F7_P$157") (pintype "bidirectional"))
    )
    (net (code "40") (name "ZZ.00.026") (class "Default")
      (node (ref "U$4") (pin "P$36") (pinfunction "B6_P$36") (pintype "bidirectional"))
    )
    (net (code "41") (name "ZZ.00.027") (class "Default")
      (node (ref "U$4") (pin "P$65") (pinfunction "C5_P$65") (pintype "bidirectional"))
    )
    (net (code "42") (name "ZZ.00.028") (class "Default")
      (node (ref "U$4") (pin "P$94") (pinfunction "D4_P$94") (pintype "bidirectional"))
    )
    (net (code "43") (name "ZZ.00.029") (class "Default")
      (node (ref "U$4") (pin "P$123") (pinfunction "E3_P$123") (pintype "bidirectional"))
    )
    (net (code "44") (name "ZZ.00.030") (class "Default")
      (node (ref "U$4") (pin "P$158") (pinfunction "F8_P$158") (pintype "bidirectional"))
    )
    (net (code "45") (name "ZZ.00.031") (class "Default")
      (node (ref "U$4") (pin "P$152") (pinfunction "F2_P$152") (pintype "bidirectional"))
    )
    (net (code "46") (name "ZZ.00.032") (class "Default")
      (node (ref "U$6") (pin "P$34") (pinfunction "B4_P$34") (pintype "bidirectional"))
    )
    (net (code "47") (name "ZZ.00.033") (class "Default")
      (node (ref "U$6") (pin "P$63") (pinfunction "C3_P$63") (pintype "bidirectional"))
    )
    (net (code "48") (name "ZZ.00.034") (class "Default")
      (node (ref "U$6") (pin "P$98") (pinfunction "D8_P$98") (pintype "bidirectional"))
    )
    (net (code "49") (name "ZZ.00.035") (class "Default")
      (node (ref "U$6") (pin "P$127") (pinfunction "E7_P$127") (pintype "bidirectional"))
    )
    (net (code "50") (name "ZZ.00.036") (class "Default")
      (node (ref "U$6") (pin "P$156") (pinfunction "F6_P$156") (pintype "bidirectional"))
    )
    (net (code "51") (name "ZZ.00.037") (class "Default")
      (node (ref "U$6") (pin "P$35") (pinfunction "B5_P$35") (pintype "bidirectional"))
    )
    (net (code "52") (name "ZZ.00.038") (class "Default")
      (node (ref "U$6") (pin "P$64") (pinfunction "C4_P$64") (pintype "bidirectional"))
    )
    (net (code "53") (name "ZZ.00.039") (class "Default")
      (node (ref "U$6") (pin "P$93") (pinfunction "D3_P$93") (pintype "bidirectional"))
    )
    (net (code "54") (name "ZZ.00.040") (class "Default")
      (node (ref "U$6") (pin "P$128") (pinfunction "E8_P$128") (pintype "bidirectional"))
    )
    (net (code "55") (name "ZZ.00.041") (class "Default")
      (node (ref "U$6") (pin "P$157") (pinfunction "F7_P$157") (pintype "bidirectional"))
    )
    (net (code "56") (name "ZZ.00.042") (class "Default")
      (node (ref "U$6") (pin "P$36") (pinfunction "B6_P$36") (pintype "bidirectional"))
    )
    (net (code "57") (name "ZZ.00.043") (class "Default")
      (node (ref "U$6") (pin "P$65") (pinfunction "C5_P$65") (pintype "bidirectional"))
    )
    (net (code "58") (name "ZZ.00.044") (class "Default")
      (node (ref "U$6") (pin "P$94") (pinfunction "D4_P$94") (pintype "bidirectional"))
    )
    (net (code "59") (name "ZZ.00.045") (class "Default")
      (node (ref "U$6") (pin "P$123") (pinfunction "E3_P$123") (pintype "bidirectional"))
    )
    (net (code "60") (name "ZZ.00.046") (class "Default")
      (node (ref "U$6") (pin "P$158") (pinfunction "F8_P$158") (pintype "bidirectional"))
    )
    (net (code "61") (name "ZZ.00.047") (class "Default")
      (node (ref "U$6") (pin "P$152") (pinfunction "F2_P$152") (pintype "bidirectional"))
    )
    (net (code "62") (name "ZZ.00.048") (class "Default")
      (node (ref "U$8") (pin "P$34") (pinfunction "B4_P$34") (pintype "bidirectional"))
    )
    (net (code "63") (name "ZZ.00.049") (class "Default")
      (node (ref "U$8") (pin "P$63") (pinfunction "C3_P$63") (pintype "bidirectional"))
    )
    (net (code "64") (name "ZZ.00.050") (class "Default")
      (node (ref "U$8") (pin "P$98") (pinfunction "D8_P$98") (pintype "bidirectional"))
    )
    (net (code "65") (name "ZZ.00.051") (class "Default")
      (node (ref "U$8") (pin "P$127") (pinfunction "E7_P$127") (pintype "bidirectional"))
    )
    (net (code "66") (name "ZZ.00.052") (class "Default")
      (node (ref "U$8") (pin "P$156") (pinfunction "F6_P$156") (pintype "bidirectional"))
    )
    (net (code "67") (name "ZZ.00.053") (class "Default")
      (node (ref "U$8") (pin "P$35") (pinfunction "B5_P$35") (pintype "bidirectional"))
    )
    (net (code "68") (name "ZZ.00.054") (class "Default")
      (node (ref "U$8") (pin "P$64") (pinfunction "C4_P$64") (pintype "bidirectional"))
    )
    (net (code "69") (name "ZZ.00.055") (class "Default")
      (node (ref "U$8") (pin "P$93") (pinfunction "D3_P$93") (pintype "bidirectional"))
    )
    (net (code "70") (name "ZZ.00.056") (class "Default")
      (node (ref "U$8") (pin "P$36") (pinfunction "B6_P$36") (pintype "bidirectional"))
    )
    (net (code "71") (name "ZZ.00.057") (class "Default")
      (node (ref "U$8") (pin "P$65") (pinfunction "C5_P$65") (pintype "bidirectional"))
    )
    (net (code "72") (name "ZZ.00.058") (class "Default")
      (node (ref "U$8") (pin "P$94") (pinfunction "D4_P$94") (pintype "bidirectional"))
    )
    (net (code "73") (name "ZZ.00.059") (class "Default")
      (node (ref "U$8") (pin "P$123") (pinfunction "E3_P$123") (pintype "bidirectional"))
    )
    (net (code "74") (name "ZZ.00.060") (class "Default")
      (node (ref "U$8") (pin "P$158") (pinfunction "F8_P$158") (pintype "bidirectional"))
    )
    (net (code "75") (name "ZZ.00.061") (class "Default")
      (node (ref "U$8") (pin "P$152") (pinfunction "F2_P$152") (pintype "bidirectional"))
    )
    (net (code "76") (name "ZZ.00.062") (class "Default")
      (node (ref "U$8") (pin "P$128") (pinfunction "E8_P$128") (pintype "bidirectional"))
    )
    (net (code "77") (name "ZZ.00.063") (class "Default")
      (node (ref "U$8") (pin "P$157") (pinfunction "F7_P$157") (pintype "bidirectional"))
    )
    (net (code "78") (name "ZZ.00.064") (class "Default")
      (node (ref "U$10") (pin "P$34") (pinfunction "B4_P$34") (pintype "bidirectional"))
    )
    (net (code "79") (name "ZZ.00.065") (class "Default")
      (node (ref "U$10") (pin "P$63") (pinfunction "C3_P$63") (pintype "bidirectional"))
    )
    (net (code "80") (name "ZZ.00.066") (class "Default")
      (node (ref "U$10") (pin "P$98") (pinfunction "D8_P$98") (pintype "bidirectional"))
    )
    (net (code "81") (name "ZZ.00.067") (class "Default")
      (node (ref "U$10") (pin "P$35") (pinfunction "B5_P$35") (pintype "bidirectional"))
    )
    (net (code "82") (name "ZZ.00.068") (class "Default")
      (node (ref "U$10") (pin "P$64") (pinfunction "C4_P$64") (pintype "bidirectional"))
    )
    (net (code "83") (name "ZZ.00.069") (class "Default")
      (node (ref "U$10") (pin "P$93") (pinfunction "D3_P$93") (pintype "bidirectional"))
    )
    (net (code "84") (name "ZZ.00.070") (class "Default")
      (node (ref "U$10") (pin "P$36") (pinfunction "B6_P$36") (pintype "bidirectional"))
    )
    (net (code "85") (name "ZZ.00.071") (class "Default")
      (node (ref "U$10") (pin "P$65") (pinfunction "C5_P$65") (pintype "bidirectional"))
    )
    (net (code "86") (name "ZZ.00.072") (class "Default")
      (node (ref "U$10") (pin "P$94") (pinfunction "D4_P$94") (pintype "bidirectional"))
    )
    (net (code "87") (name "ZZ.00.073") (class "Default")
      (node (ref "U$10") (pin "P$123") (pinfunction "E3_P$123") (pintype "bidirectional"))
    )
    (net (code "88") (name "ZZ.00.074") (class "Default")
      (node (ref "U$10") (pin "P$158") (pinfunction "F8_P$158") (pintype "bidirectional"))
    )
    (net (code "89") (name "ZZ.00.075") (class "Default")
      (node (ref "U$10") (pin "P$152") (pinfunction "F2_P$152") (pintype "bidirectional"))
    )
    (net (code "90") (name "ZZ.00.076") (class "Default")
      (node (ref "U$10") (pin "P$128") (pinfunction "E8_P$128") (pintype "bidirectional"))
    )
    (net (code "91") (name "ZZ.00.077") (class "Default")
      (node (ref "U$10") (pin "P$157") (pinfunction "F7_P$157") (pintype "bidirectional"))
    )
    (net (code "92") (name "ZZ.00.078") (class "Default")
      (node (ref "U$10") (pin "P$127") (pinfunction "E7_P$127") (pintype "bidirectional"))
    )
    (net (code "93") (name "ZZ.00.079") (class "Default")
      (node (ref "U$10") (pin "P$156") (pinfunction "F6_P$156") (pintype "bidirectional"))
    )
    (net (code "94") (name "ZZ.00.080") (class "Default")
      (node (ref "U$12") (pin "P$34") (pinfunction "B4_P$34") (pintype "bidirectional"))
    )
    (net (code "95") (name "ZZ.00.081") (class "Default")
      (node (ref "U$12") (pin "P$35") (pinfunction "B5_P$35") (pintype "bidirectional"))
    )
    (net (code "96") (name "ZZ.00.082") (class "Default")
      (node (ref "U$12") (pin "P$64") (pinfunction "C4_P$64") (pintype "bidirectional"))
    )
    (net (code "97") (name "ZZ.00.083") (class "Default")
      (node (ref "U$12") (pin "P$93") (pinfunction "D3_P$93") (pintype "bidirectional"))
    )
    (net (code "98") (name "ZZ.00.084") (class "Default")
      (node (ref "U$12") (pin "P$36") (pinfunction "B6_P$36") (pintype "bidirectional"))
    )
    (net (code "99") (name "ZZ.00.085") (class "Default")
      (node (ref "U$12") (pin "P$65") (pinfunction "C5_P$65") (pintype "bidirectional"))
    )
    (net (code "100") (name "ZZ.00.086") (class "Default")
      (node (ref "U$12") (pin "P$94") (pinfunction "D4_P$94") (pintype "bidirectional"))
    )
    (net (code "101") (name "ZZ.00.087") (class "Default")
      (node (ref "U$12") (pin "P$123") (pinfunction "E3_P$123") (pintype "bidirectional"))
    )
    (net (code "102") (name "ZZ.00.088") (class "Default")
      (node (ref "U$12") (pin "P$158") (pinfunction "F8_P$158") (pintype "bidirectional"))
    )
    (net (code "103") (name "ZZ.00.089") (class "Default")
      (node (ref "U$12") (pin "P$152") (pinfunction "F2_P$152") (pintype "bidirectional"))
    )
    (net (code "104") (name "ZZ.00.090") (class "Default")
      (node (ref "U$12") (pin "P$128") (pinfunction "E8_P$128") (pintype "bidirectional"))
    )
    (net (code "105") (name "ZZ.00.091") (class "Default")
      (node (ref "U$12") (pin "P$157") (pinfunction "F7_P$157") (pintype "bidirectional"))
    )
    (net (code "106") (name "ZZ.00.092") (class "Default")
      (node (ref "U$12") (pin "P$63") (pinfunction "C3_P$63") (pintype "bidirectional"))
    )
    (net (code "107") (name "ZZ.00.093") (class "Default")
      (node (ref "U$12") (pin "P$98") (pinfunction "D8_P$98") (pintype "bidirectional"))
    )
    (net (code "108") (name "ZZ.00.094") (class "Default")
      (node (ref "U$12") (pin "P$127") (pinfunction "E7_P$127") (pintype "bidirectional"))
    )
    (net (code "109") (name "ZZ.00.095") (class "Default")
      (node (ref "U$12") (pin "P$156") (pinfunction "F6_P$156") (pintype "bidirectional"))
    )
    (net (code "110") (name "ZZ.00.096") (class "Default")
      (node (ref "U$14") (pin "P$35") (pinfunction "B5_P$35") (pintype "bidirectional"))
    )
    (net (code "111") (name "ZZ.00.097") (class "Default")
      (node (ref "U$14") (pin "P$36") (pinfunction "B6_P$36") (pintype "bidirectional"))
    )
    (net (code "112") (name "ZZ.00.098") (class "Default")
      (node (ref "U$14") (pin "P$65") (pinfunction "C5_P$65") (pintype "bidirectional"))
    )
    (net (code "113") (name "ZZ.00.099") (class "Default")
      (node (ref "U$14") (pin "P$94") (pinfunction "D4_P$94") (pintype "bidirectional"))
    )
    (net (code "114") (name "ZZ.00.100") (class "Default")
      (node (ref "U$14") (pin "P$123") (pinfunction "E3_P$123") (pintype "bidirectional"))
    )
    (net (code "115") (name "ZZ.00.101") (class "Default")
      (node (ref "U$14") (pin "P$158") (pinfunction "F8_P$158") (pintype "bidirectional"))
    )
    (net (code "116") (name "ZZ.00.102") (class "Default")
      (node (ref "U$14") (pin "P$152") (pinfunction "F2_P$152") (pintype "bidirectional"))
    )
    (net (code "117") (name "ZZ.00.103") (class "Default")
      (node (ref "U$14") (pin "P$64") (pinfunction "C4_P$64") (pintype "bidirectional"))
    )
    (net (code "118") (name "ZZ.00.104") (class "Default")
      (node (ref "U$14") (pin "P$93") (pinfunction "D3_P$93") (pintype "bidirectional"))
    )
    (net (code "119") (name "ZZ.00.105") (class "Default")
      (node (ref "U$14") (pin "P$128") (pinfunction "E8_P$128") (pintype "bidirectional"))
    )
    (net (code "120") (name "ZZ.00.106") (class "Default")
      (node (ref "U$14") (pin "P$157") (pinfunction "F7_P$157") (pintype "bidirectional"))
    )
    (net (code "121") (name "ZZ.00.107") (class "Default")
      (node (ref "U$14") (pin "P$34") (pinfunction "B4_P$34") (pintype "bidirectional"))
    )
    (net (code "122") (name "ZZ.00.108") (class "Default")
      (node (ref "U$14") (pin "P$63") (pinfunction "C3_P$63") (pintype "bidirectional"))
    )
    (net (code "123") (name "ZZ.00.109") (class "Default")
      (node (ref "U$14") (pin "P$98") (pinfunction "D8_P$98") (pintype "bidirectional"))
    )
    (net (code "124") (name "ZZ.00.110") (class "Default")
      (node (ref "U$14") (pin "P$127") (pinfunction "E7_P$127") (pintype "bidirectional"))
    )
    (net (code "125") (name "ZZ.00.111") (class "Default")
      (node (ref "U$14") (pin "P$156") (pinfunction "F6_P$156") (pintype "bidirectional"))
    )
    (net (code "126") (name "ZZ.00.112") (class "Default")
      (node (ref "U$16") (pin "P$36") (pinfunction "B6_P$36") (pintype "bidirectional"))
    )
    (net (code "127") (name "ZZ.00.113") (class "Default")
      (node (ref "U$16") (pin "P$65") (pinfunction "C5_P$65") (pintype "bidirectional"))
    )
    (net (code "128") (name "ZZ.00.114") (class "Default")
      (node (ref "U$16") (pin "P$94") (pinfunction "D4_P$94") (pintype "bidirectional"))
    )
    (net (code "129") (name "ZZ.00.115") (class "Default")
      (node (ref "U$16") (pin "P$123") (pinfunction "E3_P$123") (pintype "bidirectional"))
    )
    (net (code "130") (name "ZZ.00.116") (class "Default")
      (node (ref "U$16") (pin "P$158") (pinfunction "F8_P$158") (pintype "bidirectional"))
    )
    (net (code "131") (name "ZZ.00.117") (class "Default")
      (node (ref "U$16") (pin "P$152") (pinfunction "F2_P$152") (pintype "bidirectional"))
    )
    (net (code "132") (name "ZZ.00.118") (class "Default")
      (node (ref "U$16") (pin "P$35") (pinfunction "B5_P$35") (pintype "bidirectional"))
    )
    (net (code "133") (name "ZZ.00.119") (class "Default")
      (node (ref "U$16") (pin "P$64") (pinfunction "C4_P$64") (pintype "bidirectional"))
    )
    (net (code "134") (name "ZZ.00.120") (class "Default")
      (node (ref "U$16") (pin "P$93") (pinfunction "D3_P$93") (pintype "bidirectional"))
    )
    (net (code "135") (name "ZZ.00.121") (class "Default")
      (node (ref "U$16") (pin "P$128") (pinfunction "E8_P$128") (pintype "bidirectional"))
    )
    (net (code "136") (name "ZZ.00.122") (class "Default")
      (node (ref "U$16") (pin "P$157") (pinfunction "F7_P$157") (pintype "bidirectional"))
    )
    (net (code "137") (name "ZZ.00.123") (class "Default")
      (node (ref "U$16") (pin "P$34") (pinfunction "B4_P$34") (pintype "bidirectional"))
    )
    (net (code "138") (name "ZZ.00.124") (class "Default")
      (node (ref "U$16") (pin "P$63") (pinfunction "C3_P$63") (pintype "bidirectional"))
    )
    (net (code "139") (name "ZZ.00.125") (class "Default")
      (node (ref "U$16") (pin "P$98") (pinfunction "D8_P$98") (pintype "bidirectional"))
    )
    (net (code "140") (name "ZZ.00.126") (class "Default")
      (node (ref "U$16") (pin "P$127") (pinfunction "E7_P$127") (pintype "bidirectional"))
    )
    (net (code "141") (name "ZZ.00.127") (class "Default")
      (node (ref "U$16") (pin "P$156") (pinfunction "F6_P$156") (pintype "bidirectional"))
    )
    (net (code "142") (name "ZZ.00.128") (class "Default")
      (node (ref "U$18") (pin "P$36") (pinfunction "B6_P$36") (pintype "bidirectional"))
    )
    (net (code "143") (name "ZZ.00.129") (class "Default")
      (node (ref "U$18") (pin "P$65") (pinfunction "C5_P$65") (pintype "bidirectional"))
    )
    (net (code "144") (name "ZZ.00.130") (class "Default")
      (node (ref "U$18") (pin "P$94") (pinfunction "D4_P$94") (pintype "bidirectional"))
    )
    (net (code "145") (name "ZZ.00.131") (class "Default")
      (node (ref "U$18") (pin "P$123") (pinfunction "E3_P$123") (pintype "bidirectional"))
    )
    (net (code "146") (name "ZZ.00.132") (class "Default")
      (node (ref "U$18") (pin "P$158") (pinfunction "F8_P$158") (pintype "bidirectional"))
    )
    (net (code "147") (name "ZZ.00.133") (class "Default")
      (node (ref "U$18") (pin "P$152") (pinfunction "F2_P$152") (pintype "bidirectional"))
    )
    (net (code "148") (name "ZZ.00.134") (class "Default")
      (node (ref "U$18") (pin "P$35") (pinfunction "B5_P$35") (pintype "bidirectional"))
    )
    (net (code "149") (name "ZZ.00.135") (class "Default")
      (node (ref "U$18") (pin "P$64") (pinfunction "C4_P$64") (pintype "bidirectional"))
    )
    (net (code "150") (name "ZZ.00.136") (class "Default")
      (node (ref "U$18") (pin "P$93") (pinfunction "D3_P$93") (pintype "bidirectional"))
    )
    (net (code "151") (name "ZZ.00.137") (class "Default")
      (node (ref "U$18") (pin "P$128") (pinfunction "E8_P$128") (pintype "bidirectional"))
    )
    (net (code "152") (name "ZZ.00.138") (class "Default")
      (node (ref "U$18") (pin "P$157") (pinfunction "F7_P$157") (pintype "bidirectional"))
    )
    (net (code "153") (name "ZZ.00.139") (class "Default")
      (node (ref "U$18") (pin "P$34") (pinfunction "B4_P$34") (pintype "bidirectional"))
    )
    (net (code "154") (name "ZZ.00.140") (class "Default")
      (node (ref "U$18") (pin "P$63") (pinfunction "C3_P$63") (pintype "bidirectional"))
    )
    (net (code "155") (name "ZZ.00.141") (class "Default")
      (node (ref "U$18") (pin "P$98") (pinfunction "D8_P$98") (pintype "bidirectional"))
    )
    (net (code "156") (name "ZZ.00.142") (class "Default")
      (node (ref "U$18") (pin "P$127") (pinfunction "E7_P$127") (pintype "bidirectional"))
    )
    (net (code "157") (name "ZZ.00.143") (class "Default")
      (node (ref "U$18") (pin "P$156") (pinfunction "F6_P$156") (pintype "bidirectional"))
    )
    (net (code "158") (name "ZZ.00.144") (class "Default")
      (node (ref "U$20") (pin "P$36") (pinfunction "B6_P$36") (pintype "bidirectional"))
    )
    (net (code "159") (name "ZZ.00.145") (class "Default")
      (node (ref "U$20") (pin "P$65") (pinfunction "C5_P$65") (pintype "bidirectional"))
    )
    (net (code "160") (name "ZZ.00.146") (class "Default")
      (node (ref "U$20") (pin "P$94") (pinfunction "D4_P$94") (pintype "bidirectional"))
    )
    (net (code "161") (name "ZZ.00.147") (class "Default")
      (node (ref "U$20") (pin "P$123") (pinfunction "E3_P$123") (pintype "bidirectional"))
    )
    (net (code "162") (name "ZZ.00.148") (class "Default")
      (node (ref "U$20") (pin "P$158") (pinfunction "F8_P$158") (pintype "bidirectional"))
    )
    (net (code "163") (name "ZZ.00.149") (class "Default")
      (node (ref "U$20") (pin "P$152") (pinfunction "F2_P$152") (pintype "bidirectional"))
    )
    (net (code "164") (name "ZZ.00.150") (class "Default")
      (node (ref "U$20") (pin "P$35") (pinfunction "B5_P$35") (pintype "bidirectional"))
    )
    (net (code "165") (name "ZZ.00.151") (class "Default")
      (node (ref "U$20") (pin "P$64") (pinfunction "C4_P$64") (pintype "bidirectional"))
    )
    (net (code "166") (name "ZZ.00.152") (class "Default")
      (node (ref "U$20") (pin "P$93") (pinfunction "D3_P$93") (pintype "bidirectional"))
    )
    (net (code "167") (name "ZZ.00.153") (class "Default")
      (node (ref "U$20") (pin "P$128") (pinfunction "E8_P$128") (pintype "bidirectional"))
    )
    (net (code "168") (name "ZZ.00.154") (class "Default")
      (node (ref "U$20") (pin "P$157") (pinfunction "F7_P$157") (pintype "bidirectional"))
    )
    (net (code "169") (name "ZZ.00.155") (class "Default")
      (node (ref "U$20") (pin "P$34") (pinfunction "B4_P$34") (pintype "bidirectional"))
    )
    (net (code "170") (name "ZZ.00.156") (class "Default")
      (node (ref "U$20") (pin "P$63") (pinfunction "C3_P$63") (pintype "bidirectional"))
    )
    (net (code "171") (name "ZZ.00.157") (class "Default")
      (node (ref "U$20") (pin "P$98") (pinfunction "D8_P$98") (pintype "bidirectional"))
    )
    (net (code "172") (name "ZZ.00.158") (class "Default")
      (node (ref "U$20") (pin "P$127") (pinfunction "E7_P$127") (pintype "bidirectional"))
    )
    (net (code "173") (name "ZZ.00.159") (class "Default")
      (node (ref "U$20") (pin "P$156") (pinfunction "F6_P$156") (pintype "bidirectional"))
    )
    (net (code "174") (name "ZZ.00.160") (class "Default")
      (node (ref "U$22") (pin "P$36") (pinfunction "B6_P$36") (pintype "bidirectional"))
    )
    (net (code "175") (name "ZZ.00.161") (class "Default")
      (node (ref "U$22") (pin "P$65") (pinfunction "C5_P$65") (pintype "bidirectional"))
    )
    (net (code "176") (name "ZZ.00.162") (class "Default")
      (node (ref "U$22") (pin "P$94") (pinfunction "D4_P$94") (pintype "bidirectional"))
    )
    (net (code "177") (name "ZZ.00.163") (class "Default")
      (node (ref "U$22") (pin "P$123") (pinfunction "E3_P$123") (pintype "bidirectional"))
    )
    (net (code "178") (name "ZZ.00.164") (class "Default")
      (node (ref "U$22") (pin "P$158") (pinfunction "F8_P$158") (pintype "bidirectional"))
    )
    (net (code "179") (name "ZZ.00.165") (class "Default")
      (node (ref "U$22") (pin "P$152") (pinfunction "F2_P$152") (pintype "bidirectional"))
    )
    (net (code "180") (name "ZZ.00.166") (class "Default")
      (node (ref "U$22") (pin "P$35") (pinfunction "B5_P$35") (pintype "bidirectional"))
    )
    (net (code "181") (name "ZZ.00.167") (class "Default")
      (node (ref "U$22") (pin "P$64") (pinfunction "C4_P$64") (pintype "bidirectional"))
    )
    (net (code "182") (name "ZZ.00.168") (class "Default")
      (node (ref "U$22") (pin "P$93") (pinfunction "D3_P$93") (pintype "bidirectional"))
    )
    (net (code "183") (name "ZZ.00.169") (class "Default")
      (node (ref "U$22") (pin "P$128") (pinfunction "E8_P$128") (pintype "bidirectional"))
    )
    (net (code "184") (name "ZZ.00.170") (class "Default")
      (node (ref "U$22") (pin "P$157") (pinfunction "F7_P$157") (pintype "bidirectional"))
    )
    (net (code "185") (name "ZZ.00.171") (class "Default")
      (node (ref "U$22") (pin "P$34") (pinfunction "B4_P$34") (pintype "bidirectional"))
    )
    (net (code "186") (name "ZZ.00.172") (class "Default")
      (node (ref "U$22") (pin "P$63") (pinfunction "C3_P$63") (pintype "bidirectional"))
    )
    (net (code "187") (name "ZZ.00.173") (class "Default")
      (node (ref "U$22") (pin "P$98") (pinfunction "D8_P$98") (pintype "bidirectional"))
    )
    (net (code "188") (name "ZZ.00.174") (class "Default")
      (node (ref "U$22") (pin "P$127") (pinfunction "E7_P$127") (pintype "bidirectional"))
    )
    (net (code "189") (name "ZZ.00.175") (class "Default")
      (node (ref "U$22") (pin "P$156") (pinfunction "F6_P$156") (pintype "bidirectional"))
    )
    (net (code "190") (name "ZZ.00.176") (class "Default")
      (node (ref "U$24") (pin "P$36") (pinfunction "B6_P$36") (pintype "bidirectional"))
    )
    (net (code "191") (name "ZZ.00.177") (class "Default")
      (node (ref "U$24") (pin "P$65") (pinfunction "C5_P$65") (pintype "bidirectional"))
    )
    (net (code "192") (name "ZZ.00.178") (class "Default")
      (node (ref "U$24") (pin "P$94") (pinfunction "D4_P$94") (pintype "bidirectional"))
    )
    (net (code "193") (name "ZZ.00.179") (class "Default")
      (node (ref "U$24") (pin "P$123") (pinfunction "E3_P$123") (pintype "bidirectional"))
    )
    (net (code "194") (name "ZZ.00.180") (class "Default")
      (node (ref "U$24") (pin "P$158") (pinfunction "F8_P$158") (pintype "bidirectional"))
    )
    (net (code "195") (name "ZZ.00.181") (class "Default")
      (node (ref "U$24") (pin "P$152") (pinfunction "F2_P$152") (pintype "bidirectional"))
    )
    (net (code "196") (name "ZZ.00.182") (class "Default")
      (node (ref "U$24") (pin "P$35") (pinfunction "B5_P$35") (pintype "bidirectional"))
    )
    (net (code "197") (name "ZZ.00.183") (class "Default")
      (node (ref "U$24") (pin "P$64") (pinfunction "C4_P$64") (pintype "bidirectional"))
    )
    (net (code "198") (name "ZZ.00.184") (class "Default")
      (node (ref "U$24") (pin "P$93") (pinfunction "D3_P$93") (pintype "bidirectional"))
    )
    (net (code "199") (name "ZZ.00.185") (class "Default")
      (node (ref "U$24") (pin "P$128") (pinfunction "E8_P$128") (pintype "bidirectional"))
    )
    (net (code "200") (name "ZZ.00.186") (class "Default")
      (node (ref "U$24") (pin "P$157") (pinfunction "F7_P$157") (pintype "bidirectional"))
    )
    (net (code "201") (name "ZZ.00.187") (class "Default")
      (node (ref "U$24") (pin "P$34") (pinfunction "B4_P$34") (pintype "bidirectional"))
    )
    (net (code "202") (name "ZZ.00.188") (class "Default")
      (node (ref "U$24") (pin "P$63") (pinfunction "C3_P$63") (pintype "bidirectional"))
    )
    (net (code "203") (name "ZZ.00.189") (class "Default")
      (node (ref "U$24") (pin "P$98") (pinfunction "D8_P$98") (pintype "bidirectional"))
    )
    (net (code "204") (name "ZZ.00.190") (class "Default")
      (node (ref "U$24") (pin "P$127") (pinfunction "E7_P$127") (pintype "bidirectional"))
    )
    (net (code "205") (name "ZZ.00.191") (class "Default")
      (node (ref "U$24") (pin "P$156") (pinfunction "F6_P$156") (pintype "bidirectional"))
    )
    (net (code "206") (name "ZZ.01.000") (class "Default")
      (node (ref "U$2") (pin "P$33") (pinfunction "B3_P$33") (pintype "bidirectional"))
    )
    (net (code "207") (name "ZZ.01.001") (class "Default")
      (node (ref "U$2") (pin "P$68") (pinfunction "C8_P$68") (pintype "bidirectional"))
    )
    (net (code "208") (name "ZZ.01.002") (class "Default")
      (node (ref "U$2") (pin "P$97") (pinfunction "D7_P$97") (pintype "bidirectional"))
    )
    (net (code "209") (name "ZZ.01.003") (class "Default")
      (node (ref "U$2") (pin "P$126") (pinfunction "E6_P$126") (pintype "bidirectional"))
    )
    (net (code "210") (name "ZZ.01.004") (class "Default")
      (node (ref "U$2") (pin "P$155") (pinfunction "F5_P$155") (pintype "bidirectional"))
    )
    (net (code "211") (name "ZZ.01.005") (class "Default")
      (node (ref "U$2") (pin "P$38") (pinfunction "B8_P$38") (pintype "bidirectional"))
    )
    (net (code "212") (name "ZZ.01.006") (class "Default")
      (node (ref "U$2") (pin "P$67") (pinfunction "C7_P$67") (pintype "bidirectional"))
    )
    (net (code "213") (name "ZZ.01.007") (class "Default")
      (node (ref "U$2") (pin "P$96") (pinfunction "D6_P$96") (pintype "bidirectional"))
    )
    (net (code "214") (name "ZZ.01.008") (class "Default")
      (node (ref "U$2") (pin "P$125") (pinfunction "E5_P$125") (pintype "bidirectional"))
    )
    (net (code "215") (name "ZZ.01.009") (class "Default")
      (node (ref "U$2") (pin "P$154") (pinfunction "F4_P$154") (pintype "bidirectional"))
    )
    (net (code "216") (name "ZZ.01.010") (class "Default")
      (node (ref "U$2") (pin "P$37") (pinfunction "B7_P$37") (pintype "bidirectional"))
    )
    (net (code "217") (name "ZZ.01.011") (class "Default")
      (node (ref "U$2") (pin "P$66") (pinfunction "C6_P$66") (pintype "bidirectional"))
    )
    (net (code "218") (name "ZZ.01.012") (class "Default")
      (node (ref "U$2") (pin "P$95") (pinfunction "D5_P$95") (pintype "bidirectional"))
    )
    (net (code "219") (name "ZZ.01.013") (class "Default")
      (node (ref "U$2") (pin "P$124") (pinfunction "E4_P$124") (pintype "bidirectional"))
    )
    (net (code "220") (name "ZZ.01.014") (class "Default")
      (node (ref "U$2") (pin "P$153") (pinfunction "F3_P$153") (pintype "bidirectional"))
    )
    (net (code "221") (name "ZZ.01.015") (class "Default")
      (node (ref "U$2") (pin "P$122") (pinfunction "E2_P$122") (pintype "bidirectional"))
    )
    (net (code "222") (name "ZZ.01.016") (class "Default")
      (node (ref "U$4") (pin "P$33") (pinfunction "B3_P$33") (pintype "bidirectional"))
    )
    (net (code "223") (name "ZZ.01.017") (class "Default")
      (node (ref "U$4") (pin "P$68") (pinfunction "C8_P$68") (pintype "bidirectional"))
    )
    (net (code "224") (name "ZZ.01.018") (class "Default")
      (node (ref "U$4") (pin "P$97") (pinfunction "D7_P$97") (pintype "bidirectional"))
    )
    (net (code "225") (name "ZZ.01.019") (class "Default")
      (node (ref "U$4") (pin "P$126") (pinfunction "E6_P$126") (pintype "bidirectional"))
    )
    (net (code "226") (name "ZZ.01.020") (class "Default")
      (node (ref "U$4") (pin "P$155") (pinfunction "F5_P$155") (pintype "bidirectional"))
    )
    (net (code "227") (name "ZZ.01.021") (class "Default")
      (node (ref "U$4") (pin "P$38") (pinfunction "B8_P$38") (pintype "bidirectional"))
    )
    (net (code "228") (name "ZZ.01.022") (class "Default")
      (node (ref "U$4") (pin "P$67") (pinfunction "C7_P$67") (pintype "bidirectional"))
    )
    (net (code "229") (name "ZZ.01.023") (class "Default")
      (node (ref "U$4") (pin "P$96") (pinfunction "D6_P$96") (pintype "bidirectional"))
    )
    (net (code "230") (name "ZZ.01.024") (class "Default")
      (node (ref "U$4") (pin "P$125") (pinfunction "E5_P$125") (pintype "bidirectional"))
    )
    (net (code "231") (name "ZZ.01.025") (class "Default")
      (node (ref "U$4") (pin "P$154") (pinfunction "F4_P$154") (pintype "bidirectional"))
    )
    (net (code "232") (name "ZZ.01.026") (class "Default")
      (node (ref "U$4") (pin "P$37") (pinfunction "B7_P$37") (pintype "bidirectional"))
    )
    (net (code "233") (name "ZZ.01.027") (class "Default")
      (node (ref "U$4") (pin "P$66") (pinfunction "C6_P$66") (pintype "bidirectional"))
    )
    (net (code "234") (name "ZZ.01.028") (class "Default")
      (node (ref "U$4") (pin "P$95") (pinfunction "D5_P$95") (pintype "bidirectional"))
    )
    (net (code "235") (name "ZZ.01.029") (class "Default")
      (node (ref "U$4") (pin "P$124") (pinfunction "E4_P$124") (pintype "bidirectional"))
    )
    (net (code "236") (name "ZZ.01.030") (class "Default")
      (node (ref "U$4") (pin "P$153") (pinfunction "F3_P$153") (pintype "bidirectional"))
    )
    (net (code "237") (name "ZZ.01.031") (class "Default")
      (node (ref "U$4") (pin "P$122") (pinfunction "E2_P$122") (pintype "bidirectional"))
    )
    (net (code "238") (name "ZZ.01.032") (class "Default")
      (node (ref "U$6") (pin "P$33") (pinfunction "B3_P$33") (pintype "bidirectional"))
    )
    (net (code "239") (name "ZZ.01.033") (class "Default")
      (node (ref "U$6") (pin "P$68") (pinfunction "C8_P$68") (pintype "bidirectional"))
    )
    (net (code "240") (name "ZZ.01.034") (class "Default")
      (node (ref "U$6") (pin "P$97") (pinfunction "D7_P$97") (pintype "bidirectional"))
    )
    (net (code "241") (name "ZZ.01.035") (class "Default")
      (node (ref "U$6") (pin "P$126") (pinfunction "E6_P$126") (pintype "bidirectional"))
    )
    (net (code "242") (name "ZZ.01.036") (class "Default")
      (node (ref "U$6") (pin "P$155") (pinfunction "F5_P$155") (pintype "bidirectional"))
    )
    (net (code "243") (name "ZZ.01.037") (class "Default")
      (node (ref "U$6") (pin "P$38") (pinfunction "B8_P$38") (pintype "bidirectional"))
    )
    (net (code "244") (name "ZZ.01.038") (class "Default")
      (node (ref "U$6") (pin "P$67") (pinfunction "C7_P$67") (pintype "bidirectional"))
    )
    (net (code "245") (name "ZZ.01.039") (class "Default")
      (node (ref "U$6") (pin "P$96") (pinfunction "D6_P$96") (pintype "bidirectional"))
    )
    (net (code "246") (name "ZZ.01.040") (class "Default")
      (node (ref "U$6") (pin "P$125") (pinfunction "E5_P$125") (pintype "bidirectional"))
    )
    (net (code "247") (name "ZZ.01.041") (class "Default")
      (node (ref "U$6") (pin "P$154") (pinfunction "F4_P$154") (pintype "bidirectional"))
    )
    (net (code "248") (name "ZZ.01.042") (class "Default")
      (node (ref "U$6") (pin "P$37") (pinfunction "B7_P$37") (pintype "bidirectional"))
    )
    (net (code "249") (name "ZZ.01.043") (class "Default")
      (node (ref "U$6") (pin "P$66") (pinfunction "C6_P$66") (pintype "bidirectional"))
    )
    (net (code "250") (name "ZZ.01.044") (class "Default")
      (node (ref "U$6") (pin "P$95") (pinfunction "D5_P$95") (pintype "bidirectional"))
    )
    (net (code "251") (name "ZZ.01.045") (class "Default")
      (node (ref "U$6") (pin "P$124") (pinfunction "E4_P$124") (pintype "bidirectional"))
    )
    (net (code "252") (name "ZZ.01.046") (class "Default")
      (node (ref "U$6") (pin "P$153") (pinfunction "F3_P$153") (pintype "bidirectional"))
    )
    (net (code "253") (name "ZZ.01.047") (class "Default")
      (node (ref "U$6") (pin "P$122") (pinfunction "E2_P$122") (pintype "bidirectional"))
    )
    (net (code "254") (name "ZZ.01.048") (class "Default")
      (node (ref "U$8") (pin "P$33") (pinfunction "B3_P$33") (pintype "bidirectional"))
    )
    (net (code "255") (name "ZZ.01.049") (class "Default")
      (node (ref "U$8") (pin "P$68") (pinfunction "C8_P$68") (pintype "bidirectional"))
    )
    (net (code "256") (name "ZZ.01.050") (class "Default")
      (node (ref "U$8") (pin "P$97") (pinfunction "D7_P$97") (pintype "bidirectional"))
    )
    (net (code "257") (name "ZZ.01.051") (class "Default")
      (node (ref "U$8") (pin "P$126") (pinfunction "E6_P$126") (pintype "bidirectional"))
    )
    (net (code "258") (name "ZZ.01.052") (class "Default")
      (node (ref "U$8") (pin "P$155") (pinfunction "F5_P$155") (pintype "bidirectional"))
    )
    (net (code "259") (name "ZZ.01.053") (class "Default")
      (node (ref "U$8") (pin "P$38") (pinfunction "B8_P$38") (pintype "bidirectional"))
    )
    (net (code "260") (name "ZZ.01.054") (class "Default")
      (node (ref "U$8") (pin "P$67") (pinfunction "C7_P$67") (pintype "bidirectional"))
    )
    (net (code "261") (name "ZZ.01.055") (class "Default")
      (node (ref "U$8") (pin "P$96") (pinfunction "D6_P$96") (pintype "bidirectional"))
    )
    (net (code "262") (name "ZZ.01.056") (class "Default")
      (node (ref "U$8") (pin "P$37") (pinfunction "B7_P$37") (pintype "bidirectional"))
    )
    (net (code "263") (name "ZZ.01.057") (class "Default")
      (node (ref "U$8") (pin "P$66") (pinfunction "C6_P$66") (pintype "bidirectional"))
    )
    (net (code "264") (name "ZZ.01.058") (class "Default")
      (node (ref "U$8") (pin "P$95") (pinfunction "D5_P$95") (pintype "bidirectional"))
    )
    (net (code "265") (name "ZZ.01.059") (class "Default")
      (node (ref "U$8") (pin "P$124") (pinfunction "E4_P$124") (pintype "bidirectional"))
    )
    (net (code "266") (name "ZZ.01.060") (class "Default")
      (node (ref "U$8") (pin "P$153") (pinfunction "F3_P$153") (pintype "bidirectional"))
    )
    (net (code "267") (name "ZZ.01.061") (class "Default")
      (node (ref "U$8") (pin "P$122") (pinfunction "E2_P$122") (pintype "bidirectional"))
    )
    (net (code "268") (name "ZZ.01.062") (class "Default")
      (node (ref "U$8") (pin "P$125") (pinfunction "E5_P$125") (pintype "bidirectional"))
    )
    (net (code "269") (name "ZZ.01.063") (class "Default")
      (node (ref "U$8") (pin "P$154") (pinfunction "F4_P$154") (pintype "bidirectional"))
    )
    (net (code "270") (name "ZZ.01.064") (class "Default")
      (node (ref "U$10") (pin "P$33") (pinfunction "B3_P$33") (pintype "bidirectional"))
    )
    (net (code "271") (name "ZZ.01.065") (class "Default")
      (node (ref "U$10") (pin "P$68") (pinfunction "C8_P$68") (pintype "bidirectional"))
    )
    (net (code "272") (name "ZZ.01.066") (class "Default")
      (node (ref "U$10") (pin "P$97") (pinfunction "D7_P$97") (pintype "bidirectional"))
    )
    (net (code "273") (name "ZZ.01.067") (class "Default")
      (node (ref "U$10") (pin "P$38") (pinfunction "B8_P$38") (pintype "bidirectional"))
    )
    (net (code "274") (name "ZZ.01.068") (class "Default")
      (node (ref "U$10") (pin "P$67") (pinfunction "C7_P$67") (pintype "bidirectional"))
    )
    (net (code "275") (name "ZZ.01.069") (class "Default")
      (node (ref "U$10") (pin "P$96") (pinfunction "D6_P$96") (pintype "bidirectional"))
    )
    (net (code "276") (name "ZZ.01.070") (class "Default")
      (node (ref "U$10") (pin "P$37") (pinfunction "B7_P$37") (pintype "bidirectional"))
    )
    (net (code "277") (name "ZZ.01.071") (class "Default")
      (node (ref "U$10") (pin "P$66") (pinfunction "C6_P$66") (pintype "bidirectional"))
    )
    (net (code "278") (name "ZZ.01.072") (class "Default")
      (node (ref "U$10") (pin "P$95") (pinfunction "D5_P$95") (pintype "bidirectional"))
    )
    (net (code "279") (name "ZZ.01.073") (class "Default")
      (node (ref "U$10") (pin "P$124") (pinfunction "E4_P$124") (pintype "bidirectional"))
    )
    (net (code "280") (name "ZZ.01.074") (class "Default")
      (node (ref "U$10") (pin "P$153") (pinfunction "F3_P$153") (pintype "bidirectional"))
    )
    (net (code "281") (name "ZZ.01.075") (class "Default")
      (node (ref "U$10") (pin "P$122") (pinfunction "E2_P$122") (pintype "bidirectional"))
    )
    (net (code "282") (name "ZZ.01.076") (class "Default")
      (node (ref "U$10") (pin "P$125") (pinfunction "E5_P$125") (pintype "bidirectional"))
    )
    (net (code "283") (name "ZZ.01.077") (class "Default")
      (node (ref "U$10") (pin "P$154") (pinfunction "F4_P$154") (pintype "bidirectional"))
    )
    (net (code "284") (name "ZZ.01.078") (class "Default")
      (node (ref "U$10") (pin "P$126") (pinfunction "E6_P$126") (pintype "bidirectional"))
    )
    (net (code "285") (name "ZZ.01.079") (class "Default")
      (node (ref "U$10") (pin "P$155") (pinfunction "F5_P$155") (pintype "bidirectional"))
    )
    (net (code "286") (name "ZZ.01.080") (class "Default")
      (node (ref "U$12") (pin "P$33") (pinfunction "B3_P$33") (pintype "bidirectional"))
    )
    (net (code "287") (name "ZZ.01.081") (class "Default")
      (node (ref "U$12") (pin "P$38") (pinfunction "B8_P$38") (pintype "bidirectional"))
    )
    (net (code "288") (name "ZZ.01.082") (class "Default")
      (node (ref "U$12") (pin "P$67") (pinfunction "C7_P$67") (pintype "bidirectional"))
    )
    (net (code "289") (name "ZZ.01.083") (class "Default")
      (node (ref "U$12") (pin "P$96") (pinfunction "D6_P$96") (pintype "bidirectional"))
    )
    (net (code "290") (name "ZZ.01.084") (class "Default")
      (node (ref "U$12") (pin "P$37") (pinfunction "B7_P$37") (pintype "bidirectional"))
    )
    (net (code "291") (name "ZZ.01.085") (class "Default")
      (node (ref "U$12") (pin "P$66") (pinfunction "C6_P$66") (pintype "bidirectional"))
    )
    (net (code "292") (name "ZZ.01.086") (class "Default")
      (node (ref "U$12") (pin "P$95") (pinfunction "D5_P$95") (pintype "bidirectional"))
    )
    (net (code "293") (name "ZZ.01.087") (class "Default")
      (node (ref "U$12") (pin "P$124") (pinfunction "E4_P$124") (pintype "bidirectional"))
    )
    (net (code "294") (name "ZZ.01.088") (class "Default")
      (node (ref "U$12") (pin "P$153") (pinfunction "F3_P$153") (pintype "bidirectional"))
    )
    (net (code "295") (name "ZZ.01.089") (class "Default")
      (node (ref "U$12") (pin "P$122") (pinfunction "E2_P$122") (pintype "bidirectional"))
    )
    (net (code "296") (name "ZZ.01.090") (class "Default")
      (node (ref "U$12") (pin "P$125") (pinfunction "E5_P$125") (pintype "bidirectional"))
    )
    (net (code "297") (name "ZZ.01.091") (class "Default")
      (node (ref "U$12") (pin "P$154") (pinfunction "F4_P$154") (pintype "bidirectional"))
    )
    (net (code "298") (name "ZZ.01.092") (class "Default")
      (node (ref "U$12") (pin "P$68") (pinfunction "C8_P$68") (pintype "bidirectional"))
    )
    (net (code "299") (name "ZZ.01.093") (class "Default")
      (node (ref "U$12") (pin "P$97") (pinfunction "D7_P$97") (pintype "bidirectional"))
    )
    (net (code "300") (name "ZZ.01.094") (class "Default")
      (node (ref "U$12") (pin "P$126") (pinfunction "E6_P$126") (pintype "bidirectional"))
    )
    (net (code "301") (name "ZZ.01.095") (class "Default")
      (node (ref "U$12") (pin "P$155") (pinfunction "F5_P$155") (pintype "bidirectional"))
    )
    (net (code "302") (name "ZZ.01.096") (class "Default")
      (node (ref "U$14") (pin "P$38") (pinfunction "B8_P$38") (pintype "bidirectional"))
    )
    (net (code "303") (name "ZZ.01.097") (class "Default")
      (node (ref "U$14") (pin "P$37") (pinfunction "B7_P$37") (pintype "bidirectional"))
    )
    (net (code "304") (name "ZZ.01.098") (class "Default")
      (node (ref "U$14") (pin "P$66") (pinfunction "C6_P$66") (pintype "bidirectional"))
    )
    (net (code "305") (name "ZZ.01.099") (class "Default")
      (node (ref "U$14") (pin "P$95") (pinfunction "D5_P$95") (pintype "bidirectional"))
    )
    (net (code "306") (name "ZZ.01.100") (class "Default")
      (node (ref "U$14") (pin "P$124") (pinfunction "E4_P$124") (pintype "bidirectional"))
    )
    (net (code "307") (name "ZZ.01.101") (class "Default")
      (node (ref "U$14") (pin "P$153") (pinfunction "F3_P$153") (pintype "bidirectional"))
    )
    (net (code "308") (name "ZZ.01.102") (class "Default")
      (node (ref "U$14") (pin "P$122") (pinfunction "E2_P$122") (pintype "bidirectional"))
    )
    (net (code "309") (name "ZZ.01.103") (class "Default")
      (node (ref "U$14") (pin "P$67") (pinfunction "C7_P$67") (pintype "bidirectional"))
    )
    (net (code "310") (name "ZZ.01.104") (class "Default")
      (node (ref "U$14") (pin "P$96") (pinfunction "D6_P$96") (pintype "bidirectional"))
    )
    (net (code "311") (name "ZZ.01.105") (class "Default")
      (node (ref "U$14") (pin "P$125") (pinfunction "E5_P$125") (pintype "bidirectional"))
    )
    (net (code "312") (name "ZZ.01.106") (class "Default")
      (node (ref "U$14") (pin "P$154") (pinfunction "F4_P$154") (pintype "bidirectional"))
    )
    (net (code "313") (name "ZZ.01.107") (class "Default")
      (node (ref "U$14") (pin "P$33") (pinfunction "B3_P$33") (pintype "bidirectional"))
    )
    (net (code "314") (name "ZZ.01.108") (class "Default")
      (node (ref "U$14") (pin "P$68") (pinfunction "C8_P$68") (pintype "bidirectional"))
    )
    (net (code "315") (name "ZZ.01.109") (class "Default")
      (node (ref "U$14") (pin "P$97") (pinfunction "D7_P$97") (pintype "bidirectional"))
    )
    (net (code "316") (name "ZZ.01.110") (class "Default")
      (node (ref "U$14") (pin "P$126") (pinfunction "E6_P$126") (pintype "bidirectional"))
    )
    (net (code "317") (name "ZZ.01.111") (class "Default")
      (node (ref "U$14") (pin "P$155") (pinfunction "F5_P$155") (pintype "bidirectional"))
    )
    (net (code "318") (name "ZZ.01.112") (class "Default")
      (node (ref "U$16") (pin "P$37") (pinfunction "B7_P$37") (pintype "bidirectional"))
    )
    (net (code "319") (name "ZZ.01.113") (class "Default")
      (node (ref "U$16") (pin "P$66") (pinfunction "C6_P$66") (pintype "bidirectional"))
    )
    (net (code "320") (name "ZZ.01.114") (class "Default")
      (node (ref "U$16") (pin "P$95") (pinfunction "D5_P$95") (pintype "bidirectional"))
    )
    (net (code "321") (name "ZZ.01.115") (class "Default")
      (node (ref "U$16") (pin "P$124") (pinfunction "E4_P$124") (pintype "bidirectional"))
    )
    (net (code "322") (name "ZZ.01.116") (class "Default")
      (node (ref "U$16") (pin "P$153") (pinfunction "F3_P$153") (pintype "bidirectional"))
    )
    (net (code "323") (name "ZZ.01.117") (class "Default")
      (node (ref "U$16") (pin "P$122") (pinfunction "E2_P$122") (pintype "bidirectional"))
    )
    (net (code "324") (name "ZZ.01.118") (class "Default")
      (node (ref "U$16") (pin "P$38") (pinfunction "B8_P$38") (pintype "bidirectional"))
    )
    (net (code "325") (name "ZZ.01.119") (class "Default")
      (node (ref "U$16") (pin "P$67") (pinfunction "C7_P$67") (pintype "bidirectional"))
    )
    (net (code "326") (name "ZZ.01.120") (class "Default")
      (node (ref "U$16") (pin "P$96") (pinfunction "D6_P$96") (pintype "bidirectional"))
    )
    (net (code "327") (name "ZZ.01.121") (class "Default")
      (node (ref "U$16") (pin "P$125") (pinfunction "E5_P$125") (pintype "bidirectional"))
    )
    (net (code "328") (name "ZZ.01.122") (class "Default")
      (node (ref "U$16") (pin "P$154") (pinfunction "F4_P$154") (pintype "bidirectional"))
    )
    (net (code "329") (name "ZZ.01.123") (class "Default")
      (node (ref "U$16") (pin "P$33") (pinfunction "B3_P$33") (pintype "bidirectional"))
    )
    (net (code "330") (name "ZZ.01.124") (class "Default")
      (node (ref "U$16") (pin "P$68") (pinfunction "C8_P$68") (pintype "bidirectional"))
    )
    (net (code "331") (name "ZZ.01.125") (class "Default")
      (node (ref "U$16") (pin "P$97") (pinfunction "D7_P$97") (pintype "bidirectional"))
    )
    (net (code "332") (name "ZZ.01.126") (class "Default")
      (node (ref "U$16") (pin "P$126") (pinfunction "E6_P$126") (pintype "bidirectional"))
    )
    (net (code "333") (name "ZZ.01.127") (class "Default")
      (node (ref "U$16") (pin "P$155") (pinfunction "F5_P$155") (pintype "bidirectional"))
    )
    (net (code "334") (name "ZZ.01.128") (class "Default")
      (node (ref "U$18") (pin "P$37") (pinfunction "B7_P$37") (pintype "bidirectional"))
    )
    (net (code "335") (name "ZZ.01.129") (class "Default")
      (node (ref "U$18") (pin "P$66") (pinfunction "C6_P$66") (pintype "bidirectional"))
    )
    (net (code "336") (name "ZZ.01.130") (class "Default")
      (node (ref "U$18") (pin "P$95") (pinfunction "D5_P$95") (pintype "bidirectional"))
    )
    (net (code "337") (name "ZZ.01.131") (class "Default")
      (node (ref "U$18") (pin "P$124") (pinfunction "E4_P$124") (pintype "bidirectional"))
    )
    (net (code "338") (name "ZZ.01.132") (class "Default")
      (node (ref "U$18") (pin "P$153") (pinfunction "F3_P$153") (pintype "bidirectional"))
    )
    (net (code "339") (name "ZZ.01.133") (class "Default")
      (node (ref "U$18") (pin "P$122") (pinfunction "E2_P$122") (pintype "bidirectional"))
    )
    (net (code "340") (name "ZZ.01.134") (class "Default")
      (node (ref "U$18") (pin "P$38") (pinfunction "B8_P$38") (pintype "bidirectional"))
    )
    (net (code "341") (name "ZZ.01.135") (class "Default")
      (node (ref "U$18") (pin "P$67") (pinfunction "C7_P$67") (pintype "bidirectional"))
    )
    (net (code "342") (name "ZZ.01.136") (class "Default")
      (node (ref "U$18") (pin "P$96") (pinfunction "D6_P$96") (pintype "bidirectional"))
    )
    (net (code "343") (name "ZZ.01.137") (class "Default")
      (node (ref "U$18") (pin "P$125") (pinfunction "E5_P$125") (pintype "bidirectional"))
    )
    (net (code "344") (name "ZZ.01.138") (class "Default")
      (node (ref "U$18") (pin "P$154") (pinfunction "F4_P$154") (pintype "bidirectional"))
    )
    (net (code "345") (name "ZZ.01.139") (class "Default")
      (node (ref "U$18") (pin "P$33") (pinfunction "B3_P$33") (pintype "bidirectional"))
    )
    (net (code "346") (name "ZZ.01.140") (class "Default")
      (node (ref "U$18") (pin "P$68") (pinfunction "C8_P$68") (pintype "bidirectional"))
    )
    (net (code "347") (name "ZZ.01.141") (class "Default")
      (node (ref "U$18") (pin "P$97") (pinfunction "D7_P$97") (pintype "bidirectional"))
    )
    (net (code "348") (name "ZZ.01.142") (class "Default")
      (node (ref "U$18") (pin "P$126") (pinfunction "E6_P$126") (pintype "bidirectional"))
    )
    (net (code "349") (name "ZZ.01.143") (class "Default")
      (node (ref "U$18") (pin "P$155") (pinfunction "F5_P$155") (pintype "bidirectional"))
    )
    (net (code "350") (name "ZZ.01.144") (class "Default")
      (node (ref "U$20") (pin "P$37") (pinfunction "B7_P$37") (pintype "bidirectional"))
    )
    (net (code "351") (name "ZZ.01.145") (class "Default")
      (node (ref "U$20") (pin "P$66") (pinfunction "C6_P$66") (pintype "bidirectional"))
    )
    (net (code "352") (name "ZZ.01.146") (class "Default")
      (node (ref "U$20") (pin "P$95") (pinfunction "D5_P$95") (pintype "bidirectional"))
    )
    (net (code "353") (name "ZZ.01.147") (class "Default")
      (node (ref "U$20") (pin "P$124") (pinfunction "E4_P$124") (pintype "bidirectional"))
    )
    (net (code "354") (name "ZZ.01.148") (class "Default")
      (node (ref "U$20") (pin "P$153") (pinfunction "F3_P$153") (pintype "bidirectional"))
    )
    (net (code "355") (name "ZZ.01.149") (class "Default")
      (node (ref "U$20") (pin "P$122") (pinfunction "E2_P$122") (pintype "bidirectional"))
    )
    (net (code "356") (name "ZZ.01.150") (class "Default")
      (node (ref "U$20") (pin "P$38") (pinfunction "B8_P$38") (pintype "bidirectional"))
    )
    (net (code "357") (name "ZZ.01.151") (class "Default")
      (node (ref "U$20") (pin "P$67") (pinfunction "C7_P$67") (pintype "bidirectional"))
    )
    (net (code "358") (name "ZZ.01.152") (class "Default")
      (node (ref "U$20") (pin "P$96") (pinfunction "D6_P$96") (pintype "bidirectional"))
    )
    (net (code "359") (name "ZZ.01.153") (class "Default")
      (node (ref "U$20") (pin "P$125") (pinfunction "E5_P$125") (pintype "bidirectional"))
    )
    (net (code "360") (name "ZZ.01.154") (class "Default")
      (node (ref "U$20") (pin "P$154") (pinfunction "F4_P$154") (pintype "bidirectional"))
    )
    (net (code "361") (name "ZZ.01.155") (class "Default")
      (node (ref "U$20") (pin "P$33") (pinfunction "B3_P$33") (pintype "bidirectional"))
    )
    (net (code "362") (name "ZZ.01.156") (class "Default")
      (node (ref "U$20") (pin "P$68") (pinfunction "C8_P$68") (pintype "bidirectional"))
    )
    (net (code "363") (name "ZZ.01.157") (class "Default")
      (node (ref "U$20") (pin "P$97") (pinfunction "D7_P$97") (pintype "bidirectional"))
    )
    (net (code "364") (name "ZZ.01.158") (class "Default")
      (node (ref "U$20") (pin "P$126") (pinfunction "E6_P$126") (pintype "bidirectional"))
    )
    (net (code "365") (name "ZZ.01.159") (class "Default")
      (node (ref "U$20") (pin "P$155") (pinfunction "F5_P$155") (pintype "bidirectional"))
    )
    (net (code "366") (name "ZZ.01.160") (class "Default")
      (node (ref "U$22") (pin "P$37") (pinfunction "B7_P$37") (pintype "bidirectional"))
    )
    (net (code "367") (name "ZZ.01.161") (class "Default")
      (node (ref "U$22") (pin "P$66") (pinfunction "C6_P$66") (pintype "bidirectional"))
    )
    (net (code "368") (name "ZZ.01.162") (class "Default")
      (node (ref "U$22") (pin "P$95") (pinfunction "D5_P$95") (pintype "bidirectional"))
    )
    (net (code "369") (name "ZZ.01.163") (class "Default")
      (node (ref "U$22") (pin "P$124") (pinfunction "E4_P$124") (pintype "bidirectional"))
    )
    (net (code "370") (name "ZZ.01.164") (class "Default")
      (node (ref "U$22") (pin "P$153") (pinfunction "F3_P$153") (pintype "bidirectional"))
    )
    (net (code "371") (name "ZZ.01.165") (class "Default")
      (node (ref "U$22") (pin "P$122") (pinfunction "E2_P$122") (pintype "bidirectional"))
    )
    (net (code "372") (name "ZZ.01.166") (class "Default")
      (node (ref "U$22") (pin "P$38") (pinfunction "B8_P$38") (pintype "bidirectional"))
    )
    (net (code "373") (name "ZZ.01.167") (class "Default")
      (node (ref "U$22") (pin "P$67") (pinfunction "C7_P$67") (pintype "bidirectional"))
    )
    (net (code "374") (name "ZZ.01.168") (class "Default")
      (node (ref "U$22") (pin "P$96") (pinfunction "D6_P$96") (pintype "bidirectional"))
    )
    (net (code "375") (name "ZZ.01.169") (class "Default")
      (node (ref "U$22") (pin "P$125") (pinfunction "E5_P$125") (pintype "bidirectional"))
    )
    (net (code "376") (name "ZZ.01.170") (class "Default")
      (node (ref "U$22") (pin "P$154") (pinfunction "F4_P$154") (pintype "bidirectional"))
    )
    (net (code "377") (name "ZZ.01.171") (class "Default")
      (node (ref "U$22") (pin "P$33") (pinfunction "B3_P$33") (pintype "bidirectional"))
    )
    (net (code "378") (name "ZZ.01.172") (class "Default")
      (node (ref "U$22") (pin "P$68") (pinfunction "C8_P$68") (pintype "bidirectional"))
    )
    (net (code "379") (name "ZZ.01.173") (class "Default")
      (node (ref "U$22") (pin "P$97") (pinfunction "D7_P$97") (pintype "bidirectional"))
    )
    (net (code "380") (name "ZZ.01.174") (class "Default")
      (node (ref "U$22") (pin "P$126") (pinfunction "E6_P$126") (pintype "bidirectional"))
    )
    (net (code "381") (name "ZZ.01.175") (class "Default")
      (node (ref "U$22") (pin "P$155") (pinfunction "F5_P$155") (pintype "bidirectional"))
    )
    (net (code "382") (name "ZZ.01.176") (class "Default")
      (node (ref "U$24") (pin "P$37") (pinfunction "B7_P$37") (pintype "bidirectional"))
    )
    (net (code "383") (name "ZZ.01.177") (class "Default")
      (node (ref "U$24") (pin "P$66") (pinfunction "C6_P$66") (pintype "bidirectional"))
    )
    (net (code "384") (name "ZZ.01.178") (class "Default")
      (node (ref "U$24") (pin "P$95") (pinfunction "D5_P$95") (pintype "bidirectional"))
    )
    (net (code "385") (name "ZZ.01.179") (class "Default")
      (node (ref "U$24") (pin "P$124") (pinfunction "E4_P$124") (pintype "bidirectional"))
    )
    (net (code "386") (name "ZZ.01.180") (class "Default")
      (node (ref "U$24") (pin "P$153") (pinfunction "F3_P$153") (pintype "bidirectional"))
    )
    (net (code "387") (name "ZZ.01.181") (class "Default")
      (node (ref "U$24") (pin "P$122") (pinfunction "E2_P$122") (pintype "bidirectional"))
    )
    (net (code "388") (name "ZZ.01.182") (class "Default")
      (node (ref "U$24") (pin "P$38") (pinfunction "B8_P$38") (pintype "bidirectional"))
    )
    (net (code "389") (name "ZZ.01.183") (class "Default")
      (node (ref "U$24") (pin "P$67") (pinfunction "C7_P$67") (pintype "bidirectional"))
    )
    (net (code "390") (name "ZZ.01.184") (class "Default")
      (node (ref "U$24") (pin "P$96") (pinfunction "D6_P$96") (pintype "bidirectional"))
    )
    (net (code "391") (name "ZZ.01.185") (class "Default")
      (node (ref "U$24") (pin "P$125") (pinfunction "E5_P$125") (pintype "bidirectional"))
    )
    (net (code "392") (name "ZZ.01.186") (class "Default")
      (node (ref "U$24") (pin "P$154") (pinfunction "F4_P$154") (pintype "bidirectional"))
    )
    (net (code "393") (name "ZZ.01.187") (class "Default")
      (node (ref "U$24") (pin "P$33") (pinfunction "B3_P$33") (pintype "bidirectional"))
    )
    (net (code "394") (name "ZZ.01.188") (class "Default")
      (node (ref "U$24") (pin "P$68") (pinfunction "C8_P$68") (pintype "bidirectional"))
    )
    (net (code "395") (name "ZZ.01.189") (class "Default")
      (node (ref "U$24") (pin "P$97") (pinfunction "D7_P$97") (pintype "bidirectional"))
    )
    (net (code "396") (name "ZZ.01.190") (class "Default")
      (node (ref "U$24") (pin "P$126") (pinfunction "E6_P$126") (pintype "bidirectional"))
    )
    (net (code "397") (name "ZZ.01.191") (class "Default")
      (node (ref "U$24") (pin "P$155") (pinfunction "F5_P$155") (pintype "bidirectional"))
    )
    (net (code "398") (name "ZZ.02.000") (class "Default")
      (node (ref "U$2") (pin "P$75") (pinfunction "C15_P$75") (pintype "bidirectional"))
    )
    (net (code "399") (name "ZZ.02.001") (class "Default")
      (node (ref "U$2") (pin "P$105") (pinfunction "D15_P$105") (pintype "bidirectional"))
    )
    (net (code "400") (name "ZZ.02.002") (class "Default")
      (node (ref "U$2") (pin "P$165") (pinfunction "F15_P$165") (pintype "bidirectional"))
    )
    (net (code "401") (name "ZZ.02.003") (class "Default")
      (node (ref "U$2") (pin "P$104") (pinfunction "D14_P$104") (pintype "bidirectional"))
    )
    (net (code "402") (name "ZZ.02.004") (class "Default")
      (node (ref "U$2") (pin "P$164") (pinfunction "F14_P$164") (pintype "bidirectional"))
    )
    (net (code "403") (name "ZZ.02.005") (class "Default")
      (node (ref "U$2") (pin "P$73") (pinfunction "C13_P$73") (pintype "bidirectional"))
    )
    (net (code "404") (name "ZZ.02.006") (class "Default")
      (node (ref "U$2") (pin "P$133") (pinfunction "E13_P$133") (pintype "bidirectional"))
    )
    (net (code "405") (name "ZZ.02.007") (class "Default")
      (node (ref "U$2") (pin "P$159") (pinfunction "F9_P$159") (pintype "bidirectional"))
    )
    (net (code "406") (name "ZZ.02.008") (class "Default")
      (node (ref "U$2") (pin "P$72") (pinfunction "C12_P$72") (pintype "bidirectional"))
    )
    (net (code "407") (name "ZZ.02.009") (class "Default")
      (node (ref "U$2") (pin "P$132") (pinfunction "E12_P$132") (pintype "bidirectional"))
    )
    (net (code "408") (name "ZZ.02.010") (class "Default")
      (node (ref "U$2") (pin "P$162") (pinfunction "F12_P$162") (pintype "bidirectional"))
    )
    (net (code "409") (name "ZZ.02.011") (class "Default")
      (node (ref "U$2") (pin "P$101") (pinfunction "D11_P$101") (pintype "bidirectional"))
    )
    (net (code "410") (name "ZZ.02.012") (class "Default")
      (node (ref "U$2") (pin "P$161") (pinfunction "F11_P$161") (pintype "bidirectional"))
    )
    (net (code "411") (name "ZZ.02.013") (class "Default")
      (node (ref "U$2") (pin "P$130") (pinfunction "E10_P$130") (pintype "bidirectional"))
    )
    (net (code "412") (name "ZZ.02.014") (class "Default")
      (node (ref "U$2") (pin "P$160") (pinfunction "F10_P$160") (pintype "bidirectional"))
    )
    (net (code "413") (name "ZZ.02.015") (class "Default")
      (node (ref "U$2") (pin "P$41") (pinfunction "B11_P$41") (pintype "bidirectional"))
    )
    (net (code "414") (name "ZZ.02.016") (class "Default")
      (node (ref "U$4") (pin "P$45") (pinfunction "B15_P$45") (pintype "bidirectional"))
    )
    (net (code "415") (name "ZZ.02.017") (class "Default")
      (node (ref "U$4") (pin "P$105") (pinfunction "D15_P$105") (pintype "bidirectional"))
    )
    (net (code "416") (name "ZZ.02.018") (class "Default")
      (node (ref "U$4") (pin "P$165") (pinfunction "F15_P$165") (pintype "bidirectional"))
    )
    (net (code "417") (name "ZZ.02.019") (class "Default")
      (node (ref "U$4") (pin "P$104") (pinfunction "D14_P$104") (pintype "bidirectional"))
    )
    (net (code "418") (name "ZZ.02.020") (class "Default")
      (node (ref "U$4") (pin "P$164") (pinfunction "F14_P$164") (pintype "bidirectional"))
    )
    (net (code "419") (name "ZZ.02.021") (class "Default")
      (node (ref "U$4") (pin "P$43") (pinfunction "B13_P$43") (pintype "bidirectional"))
    )
    (net (code "420") (name "ZZ.02.022") (class "Default")
      (node (ref "U$4") (pin "P$133") (pinfunction "E13_P$133") (pintype "bidirectional"))
    )
    (net (code "421") (name "ZZ.02.023") (class "Default")
      (node (ref "U$4") (pin "P$159") (pinfunction "F9_P$159") (pintype "bidirectional"))
    )
    (net (code "422") (name "ZZ.02.024") (class "Default")
      (node (ref "U$4") (pin "P$72") (pinfunction "C12_P$72") (pintype "bidirectional"))
    )
    (net (code "423") (name "ZZ.02.025") (class "Default")
      (node (ref "U$4") (pin "P$102") (pinfunction "D12_P$102") (pintype "bidirectional"))
    )
    (net (code "424") (name "ZZ.02.026") (class "Default")
      (node (ref "U$4") (pin "P$162") (pinfunction "F12_P$162") (pintype "bidirectional"))
    )
    (net (code "425") (name "ZZ.02.027") (class "Default")
      (node (ref "U$4") (pin "P$161") (pinfunction "F11_P$161") (pintype "bidirectional"))
    )
    (net (code "426") (name "ZZ.02.028") (class "Default")
      (node (ref "U$4") (pin "P$160") (pinfunction "F10_P$160") (pintype "bidirectional"))
    )
    (net (code "427") (name "ZZ.02.029") (class "Default")
      (node (ref "U$4") (pin "P$41") (pinfunction "B11_P$41") (pintype "bidirectional"))
    )
    (net (code "428") (name "ZZ.02.030") (class "Default")
      (node (ref "U$4") (pin "P$71") (pinfunction "C11_P$71") (pintype "bidirectional"))
    )
    (net (code "429") (name "ZZ.02.031") (class "Default")
      (node (ref "U$4") (pin "P$101") (pinfunction "D11_P$101") (pintype "bidirectional"))
    )
    (net (code "430") (name "ZZ.02.032") (class "Default")
      (node (ref "U$6") (pin "P$75") (pinfunction "C15_P$75") (pintype "bidirectional"))
    )
    (net (code "431") (name "ZZ.02.033") (class "Default")
      (node (ref "U$6") (pin "P$135") (pinfunction "E15_P$135") (pintype "bidirectional"))
    )
    (net (code "432") (name "ZZ.02.034") (class "Default")
      (node (ref "U$6") (pin "P$165") (pinfunction "F15_P$165") (pintype "bidirectional"))
    )
    (net (code "433") (name "ZZ.02.035") (class "Default")
      (node (ref "U$6") (pin "P$104") (pinfunction "D14_P$104") (pintype "bidirectional"))
    )
    (net (code "434") (name "ZZ.02.036") (class "Default")
      (node (ref "U$6") (pin "P$134") (pinfunction "E14_P$134") (pintype "bidirectional"))
    )
    (net (code "435") (name "ZZ.02.037") (class "Default")
      (node (ref "U$6") (pin "P$73") (pinfunction "C13_P$73") (pintype "bidirectional"))
    )
    (net (code "436") (name "ZZ.02.038") (class "Default")
      (node (ref "U$6") (pin "P$103") (pinfunction "D13_P$103") (pintype "bidirectional"))
    )
    (net (code "437") (name "ZZ.02.039") (class "Default")
      (node (ref "U$6") (pin "P$163") (pinfunction "F13_P$163") (pintype "bidirectional"))
    )
    (net (code "438") (name "ZZ.02.040") (class "Default")
      (node (ref "U$6") (pin "P$72") (pinfunction "C12_P$72") (pintype "bidirectional"))
    )
    (net (code "439") (name "ZZ.02.041") (class "Default")
      (node (ref "U$6") (pin "P$132") (pinfunction "E12_P$132") (pintype "bidirectional"))
    )
    (net (code "440") (name "ZZ.02.042") (class "Default")
      (node (ref "U$6") (pin "P$162") (pinfunction "F12_P$162") (pintype "bidirectional"))
    )
    (net (code "441") (name "ZZ.02.043") (class "Default")
      (node (ref "U$6") (pin "P$41") (pinfunction "B11_P$41") (pintype "bidirectional"))
    )
    (net (code "442") (name "ZZ.02.044") (class "Default")
      (node (ref "U$6") (pin "P$71") (pinfunction "C11_P$71") (pintype "bidirectional"))
    )
    (net (code "443") (name "ZZ.02.045") (class "Default")
      (node (ref "U$6") (pin "P$101") (pinfunction "D11_P$101") (pintype "bidirectional"))
    )
    (net (code "444") (name "ZZ.02.046") (class "Default")
      (node (ref "U$6") (pin "P$131") (pinfunction "E11_P$131") (pintype "bidirectional"))
    )
    (net (code "445") (name "ZZ.02.047") (class "Default")
      (node (ref "U$6") (pin "P$161") (pinfunction "F11_P$161") (pintype "bidirectional"))
    )
    (net (code "446") (name "ZZ.02.048") (class "Default")
      (node (ref "U$8") (pin "P$45") (pinfunction "B15_P$45") (pintype "bidirectional"))
    )
    (net (code "447") (name "ZZ.02.049") (class "Default")
      (node (ref "U$8") (pin "P$105") (pinfunction "D15_P$105") (pintype "bidirectional"))
    )
    (net (code "448") (name "ZZ.02.050") (class "Default")
      (node (ref "U$8") (pin "P$165") (pinfunction "F15_P$165") (pintype "bidirectional"))
    )
    (net (code "449") (name "ZZ.02.051") (class "Default")
      (node (ref "U$8") (pin "P$74") (pinfunction "C14_P$74") (pintype "bidirectional"))
    )
    (net (code "450") (name "ZZ.02.052") (class "Default")
      (node (ref "U$8") (pin "P$134") (pinfunction "E14_P$134") (pintype "bidirectional"))
    )
    (net (code "451") (name "ZZ.02.053") (class "Default")
      (node (ref "U$8") (pin "P$73") (pinfunction "C13_P$73") (pintype "bidirectional"))
    )
    (net (code "452") (name "ZZ.02.054") (class "Default")
      (node (ref "U$8") (pin "P$133") (pinfunction "E13_P$133") (pintype "bidirectional"))
    )
    (net (code "453") (name "ZZ.02.055") (class "Default")
      (node (ref "U$8") (pin "P$72") (pinfunction "C12_P$72") (pintype "bidirectional"))
    )
    (net (code "454") (name "ZZ.02.056") (class "Default")
      (node (ref "U$8") (pin "P$41") (pinfunction "B11_P$41") (pintype "bidirectional"))
    )
    (net (code "455") (name "ZZ.02.057") (class "Default")
      (node (ref "U$8") (pin "P$71") (pinfunction "C11_P$71") (pintype "bidirectional"))
    )
    (net (code "456") (name "ZZ.02.058") (class "Default")
      (node (ref "U$8") (pin "P$101") (pinfunction "D11_P$101") (pintype "bidirectional"))
    )
    (net (code "457") (name "ZZ.02.059") (class "Default")
      (node (ref "U$8") (pin "P$131") (pinfunction "E11_P$131") (pintype "bidirectional"))
    )
    (net (code "458") (name "ZZ.02.060") (class "Default")
      (node (ref "U$8") (pin "P$161") (pinfunction "F11_P$161") (pintype "bidirectional"))
    )
    (net (code "459") (name "ZZ.02.061") (class "Default")
      (node (ref "U$8") (pin "P$102") (pinfunction "D12_P$102") (pintype "bidirectional"))
    )
    (net (code "460") (name "ZZ.02.062") (class "Default")
      (node (ref "U$8") (pin "P$132") (pinfunction "E12_P$132") (pintype "bidirectional"))
    )
    (net (code "461") (name "ZZ.02.063") (class "Default")
      (node (ref "U$8") (pin "P$163") (pinfunction "F13_P$163") (pintype "bidirectional"))
    )
    (net (code "462") (name "ZZ.02.064") (class "Default")
      (node (ref "U$10") (pin "P$45") (pinfunction "B15_P$45") (pintype "bidirectional"))
    )
    (net (code "463") (name "ZZ.02.065") (class "Default")
      (node (ref "U$10") (pin "P$105") (pinfunction "D15_P$105") (pintype "bidirectional"))
    )
    (net (code "464") (name "ZZ.02.066") (class "Default")
      (node (ref "U$10") (pin "P$74") (pinfunction "C14_P$74") (pintype "bidirectional"))
    )
    (net (code "465") (name "ZZ.02.067") (class "Default")
      (node (ref "U$10") (pin "P$104") (pinfunction "D14_P$104") (pintype "bidirectional"))
    )
    (net (code "466") (name "ZZ.02.068") (class "Default")
      (node (ref "U$10") (pin "P$103") (pinfunction "D13_P$103") (pintype "bidirectional"))
    )
    (net (code "467") (name "ZZ.02.069") (class "Default")
      (node (ref "U$10") (pin "P$42") (pinfunction "B12_P$42") (pintype "bidirectional"))
    )
    (net (code "468") (name "ZZ.02.070") (class "Default")
      (node (ref "U$10") (pin "P$41") (pinfunction "B11_P$41") (pintype "bidirectional"))
    )
    (net (code "469") (name "ZZ.02.071") (class "Default")
      (node (ref "U$10") (pin "P$71") (pinfunction "C11_P$71") (pintype "bidirectional"))
    )
    (net (code "470") (name "ZZ.02.072") (class "Default")
      (node (ref "U$10") (pin "P$101") (pinfunction "D11_P$101") (pintype "bidirectional"))
    )
    (net (code "471") (name "ZZ.02.073") (class "Default")
      (node (ref "U$10") (pin "P$131") (pinfunction "E11_P$131") (pintype "bidirectional"))
    )
    (net (code "472") (name "ZZ.02.074") (class "Default")
      (node (ref "U$10") (pin "P$161") (pinfunction "F11_P$161") (pintype "bidirectional"))
    )
    (net (code "473") (name "ZZ.02.075") (class "Default")
      (node (ref "U$10") (pin "P$102") (pinfunction "D12_P$102") (pintype "bidirectional"))
    )
    (net (code "474") (name "ZZ.02.076") (class "Default")
      (node (ref "U$10") (pin "P$162") (pinfunction "F12_P$162") (pintype "bidirectional"))
    )
    (net (code "475") (name "ZZ.02.077") (class "Default")
      (node (ref "U$10") (pin "P$133") (pinfunction "E13_P$133") (pintype "bidirectional"))
    )
    (net (code "476") (name "ZZ.02.078") (class "Default")
      (node (ref "U$10") (pin "P$159") (pinfunction "F9_P$159") (pintype "bidirectional"))
    )
    (net (code "477") (name "ZZ.02.079") (class "Default")
      (node (ref "U$10") (pin "P$164") (pinfunction "F14_P$164") (pintype "bidirectional"))
    )
    (net (code "478") (name "ZZ.02.080") (class "Default")
      (node (ref "U$12") (pin "P$74") (pinfunction "C14_P$74") (pintype "bidirectional"))
    )
    (net (code "479") (name "ZZ.02.081") (class "Default")
      (node (ref "U$12") (pin "P$104") (pinfunction "D14_P$104") (pintype "bidirectional"))
    )
    (net (code "480") (name "ZZ.02.082") (class "Default")
      (node (ref "U$12") (pin "P$103") (pinfunction "D13_P$103") (pintype "bidirectional"))
    )
    (net (code "481") (name "ZZ.02.083") (class "Default")
      (node (ref "U$12") (pin "P$42") (pinfunction "B12_P$42") (pintype "bidirectional"))
    )
    (net (code "482") (name "ZZ.02.084") (class "Default")
      (node (ref "U$12") (pin "P$41") (pinfunction "B11_P$41") (pintype "bidirectional"))
    )
    (net (code "483") (name "ZZ.02.085") (class "Default")
      (node (ref "U$12") (pin "P$71") (pinfunction "C11_P$71") (pintype "bidirectional"))
    )
    (net (code "484") (name "ZZ.02.086") (class "Default")
      (node (ref "U$12") (pin "P$101") (pinfunction "D11_P$101") (pintype "bidirectional"))
    )
    (net (code "485") (name "ZZ.02.087") (class "Default")
      (node (ref "U$12") (pin "P$131") (pinfunction "E11_P$131") (pintype "bidirectional"))
    )
    (net (code "486") (name "ZZ.02.088") (class "Default")
      (node (ref "U$12") (pin "P$161") (pinfunction "F11_P$161") (pintype "bidirectional"))
    )
    (net (code "487") (name "ZZ.02.089") (class "Default")
      (node (ref "U$12") (pin "P$102") (pinfunction "D12_P$102") (pintype "bidirectional"))
    )
    (net (code "488") (name "ZZ.02.090") (class "Default")
      (node (ref "U$12") (pin "P$132") (pinfunction "E12_P$132") (pintype "bidirectional"))
    )
    (net (code "489") (name "ZZ.02.091") (class "Default")
      (node (ref "U$12") (pin "P$133") (pinfunction "E13_P$133") (pintype "bidirectional"))
    )
    (net (code "490") (name "ZZ.02.092") (class "Default")
      (node (ref "U$12") (pin "P$159") (pinfunction "F9_P$159") (pintype "bidirectional"))
    )
    (net (code "491") (name "ZZ.02.093") (class "Default")
      (node (ref "U$12") (pin "P$164") (pinfunction "F14_P$164") (pintype "bidirectional"))
    )
    (net (code "492") (name "ZZ.02.094") (class "Default")
      (node (ref "U$12") (pin "P$75") (pinfunction "C15_P$75") (pintype "bidirectional"))
    )
    (net (code "493") (name "ZZ.02.095") (class "Default")
      (node (ref "U$12") (pin "P$165") (pinfunction "F15_P$165") (pintype "bidirectional"))
    )
    (net (code "494") (name "ZZ.02.096") (class "Default")
      (node (ref "U$14") (pin "P$72") (pinfunction "C12_P$72") (pintype "bidirectional"))
    )
    (net (code "495") (name "ZZ.02.097") (class "Default")
      (node (ref "U$14") (pin "P$41") (pinfunction "B11_P$41") (pintype "bidirectional"))
    )
    (net (code "496") (name "ZZ.02.098") (class "Default")
      (node (ref "U$14") (pin "P$71") (pinfunction "C11_P$71") (pintype "bidirectional"))
    )
    (net (code "497") (name "ZZ.02.099") (class "Default")
      (node (ref "U$14") (pin "P$101") (pinfunction "D11_P$101") (pintype "bidirectional"))
    )
    (net (code "498") (name "ZZ.02.100") (class "Default")
      (node (ref "U$14") (pin "P$131") (pinfunction "E11_P$131") (pintype "bidirectional"))
    )
    (net (code "499") (name "ZZ.02.101") (class "Default")
      (node (ref "U$14") (pin "P$161") (pinfunction "F11_P$161") (pintype "bidirectional"))
    )
    (net (code "500") (name "ZZ.02.102") (class "Default")
      (node (ref "U$14") (pin "P$102") (pinfunction "D12_P$102") (pintype "bidirectional"))
    )
    (net (code "501") (name "ZZ.02.103") (class "Default")
      (node (ref "U$14") (pin "P$132") (pinfunction "E12_P$132") (pintype "bidirectional"))
    )
    (net (code "502") (name "ZZ.02.104") (class "Default")
      (node (ref "U$14") (pin "P$73") (pinfunction "C13_P$73") (pintype "bidirectional"))
    )
    (net (code "503") (name "ZZ.02.105") (class "Default")
      (node (ref "U$14") (pin "P$133") (pinfunction "E13_P$133") (pintype "bidirectional"))
    )
    (net (code "504") (name "ZZ.02.106") (class "Default")
      (node (ref "U$14") (pin "P$159") (pinfunction "F9_P$159") (pintype "bidirectional"))
    )
    (net (code "505") (name "ZZ.02.107") (class "Default")
      (node (ref "U$14") (pin "P$44") (pinfunction "B14_P$44") (pintype "bidirectional"))
    )
    (net (code "506") (name "ZZ.02.108") (class "Default")
      (node (ref "U$14") (pin "P$104") (pinfunction "D14_P$104") (pintype "bidirectional"))
    )
    (net (code "507") (name "ZZ.02.109") (class "Default")
      (node (ref "U$14") (pin "P$164") (pinfunction "F14_P$164") (pintype "bidirectional"))
    )
    (net (code "508") (name "ZZ.02.110") (class "Default")
      (node (ref "U$14") (pin "P$75") (pinfunction "C15_P$75") (pintype "bidirectional"))
    )
    (net (code "509") (name "ZZ.02.111") (class "Default")
      (node (ref "U$14") (pin "P$165") (pinfunction "F15_P$165") (pintype "bidirectional"))
    )
    (net (code "510") (name "ZZ.02.112") (class "Default")
      (node (ref "U$16") (pin "P$71") (pinfunction "C11_P$71") (pintype "bidirectional"))
    )
    (net (code "511") (name "ZZ.02.113") (class "Default")
      (node (ref "U$16") (pin "P$101") (pinfunction "D11_P$101") (pintype "bidirectional"))
    )
    (net (code "512") (name "ZZ.02.114") (class "Default")
      (node (ref "U$16") (pin "P$131") (pinfunction "E11_P$131") (pintype "bidirectional"))
    )
    (net (code "513") (name "ZZ.02.115") (class "Default")
      (node (ref "U$16") (pin "P$161") (pinfunction "F11_P$161") (pintype "bidirectional"))
    )
    (net (code "514") (name "ZZ.02.116") (class "Default")
      (node (ref "U$16") (pin "P$40") (pinfunction "B10_P$40") (pintype "bidirectional"))
    )
    (net (code "515") (name "ZZ.02.117") (class "Default")
      (node (ref "U$16") (pin "P$41") (pinfunction "B11_P$41") (pintype "bidirectional"))
    )
    (net (code "516") (name "ZZ.02.118") (class "Default")
      (node (ref "U$16") (pin "P$72") (pinfunction "C12_P$72") (pintype "bidirectional"))
    )
    (net (code "517") (name "ZZ.02.119") (class "Default")
      (node (ref "U$16") (pin "P$162") (pinfunction "F12_P$162") (pintype "bidirectional"))
    )
    (net (code "518") (name "ZZ.02.120") (class "Default")
      (node (ref "U$16") (pin "P$73") (pinfunction "C13_P$73") (pintype "bidirectional"))
    )
    (net (code "519") (name "ZZ.02.121") (class "Default")
      (node (ref "U$16") (pin "P$103") (pinfunction "D13_P$103") (pintype "bidirectional"))
    )
    (net (code "520") (name "ZZ.02.122") (class "Default")
      (node (ref "U$16") (pin "P$159") (pinfunction "F9_P$159") (pintype "bidirectional"))
    )
    (net (code "521") (name "ZZ.02.123") (class "Default")
      (node (ref "U$16") (pin "P$74") (pinfunction "C14_P$74") (pintype "bidirectional"))
    )
    (net (code "522") (name "ZZ.02.124") (class "Default")
      (node (ref "U$16") (pin "P$134") (pinfunction "E14_P$134") (pintype "bidirectional"))
    )
    (net (code "523") (name "ZZ.02.125") (class "Default")
      (node (ref "U$16") (pin "P$164") (pinfunction "F14_P$164") (pintype "bidirectional"))
    )
    (net (code "524") (name "ZZ.02.126") (class "Default")
      (node (ref "U$16") (pin "P$75") (pinfunction "C15_P$75") (pintype "bidirectional"))
    )
    (net (code "525") (name "ZZ.02.127") (class "Default")
      (node (ref "U$16") (pin "P$135") (pinfunction "E15_P$135") (pintype "bidirectional"))
    )
    (net (code "526") (name "ZZ.02.128") (class "Default")
      (node (ref "U$18") (pin "P$131") (pinfunction "E11_P$131") (pintype "bidirectional"))
    )
    (net (code "527") (name "ZZ.02.129") (class "Default")
      (node (ref "U$18") (pin "P$161") (pinfunction "F11_P$161") (pintype "bidirectional"))
    )
    (net (code "528") (name "ZZ.02.130") (class "Default")
      (node (ref "U$18") (pin "P$40") (pinfunction "B10_P$40") (pintype "bidirectional"))
    )
    (net (code "529") (name "ZZ.02.131") (class "Default")
      (node (ref "U$18") (pin "P$100") (pinfunction "D10_P$100") (pintype "bidirectional"))
    )
    (net (code "530") (name "ZZ.02.132") (class "Default")
      (node (ref "U$18") (pin "P$71") (pinfunction "C11_P$71") (pintype "bidirectional"))
    )
    (net (code "531") (name "ZZ.02.133") (class "Default")
      (node (ref "U$18") (pin "P$101") (pinfunction "D11_P$101") (pintype "bidirectional"))
    )
    (net (code "532") (name "ZZ.02.134") (class "Default")
      (node (ref "U$18") (pin "P$72") (pinfunction "C12_P$72") (pintype "bidirectional"))
    )
    (net (code "533") (name "ZZ.02.135") (class "Default")
      (node (ref "U$18") (pin "P$132") (pinfunction "E12_P$132") (pintype "bidirectional"))
    )
    (net (code "534") (name "ZZ.02.136") (class "Default")
      (node (ref "U$18") (pin "P$43") (pinfunction "B13_P$43") (pintype "bidirectional"))
    )
    (net (code "535") (name "ZZ.02.137") (class "Default")
      (node (ref "U$18") (pin "P$103") (pinfunction "D13_P$103") (pintype "bidirectional"))
    )
    (net (code "536") (name "ZZ.02.138") (class "Default")
      (node (ref "U$18") (pin "P$163") (pinfunction "F13_P$163") (pintype "bidirectional"))
    )
    (net (code "537") (name "ZZ.02.139") (class "Default")
      (node (ref "U$18") (pin "P$74") (pinfunction "C14_P$74") (pintype "bidirectional"))
    )
    (net (code "538") (name "ZZ.02.140") (class "Default")
      (node (ref "U$18") (pin "P$134") (pinfunction "E14_P$134") (pintype "bidirectional"))
    )
    (net (code "539") (name "ZZ.02.141") (class "Default")
      (node (ref "U$18") (pin "P$164") (pinfunction "F14_P$164") (pintype "bidirectional"))
    )
    (net (code "540") (name "ZZ.02.142") (class "Default")
      (node (ref "U$18") (pin "P$105") (pinfunction "D15_P$105") (pintype "bidirectional"))
    )
    (net (code "541") (name "ZZ.02.143") (class "Default")
      (node (ref "U$18") (pin "P$135") (pinfunction "E15_P$135") (pintype "bidirectional"))
    )
    (net (code "542") (name "ZZ.02.144") (class "Default")
      (node (ref "U$20") (pin "P$40") (pinfunction "B10_P$40") (pintype "bidirectional"))
    )
    (net (code "543") (name "ZZ.02.145") (class "Default")
      (node (ref "U$20") (pin "P$100") (pinfunction "D10_P$100") (pintype "bidirectional"))
    )
    (net (code "544") (name "ZZ.02.146") (class "Default")
      (node (ref "U$20") (pin "P$160") (pinfunction "F10_P$160") (pintype "bidirectional"))
    )
    (net (code "545") (name "ZZ.02.147") (class "Default")
      (node (ref "U$20") (pin "P$41") (pinfunction "B11_P$41") (pintype "bidirectional"))
    )
    (net (code "546") (name "ZZ.02.148") (class "Default")
      (node (ref "U$20") (pin "P$131") (pinfunction "E11_P$131") (pintype "bidirectional"))
    )
    (net (code "547") (name "ZZ.02.149") (class "Default")
      (node (ref "U$20") (pin "P$161") (pinfunction "F11_P$161") (pintype "bidirectional"))
    )
    (net (code "548") (name "ZZ.02.150") (class "Default")
      (node (ref "U$20") (pin "P$102") (pinfunction "D12_P$102") (pintype "bidirectional"))
    )
    (net (code "549") (name "ZZ.02.151") (class "Default")
      (node (ref "U$20") (pin "P$132") (pinfunction "E12_P$132") (pintype "bidirectional"))
    )
    (net (code "550") (name "ZZ.02.152") (class "Default")
      (node (ref "U$20") (pin "P$73") (pinfunction "C13_P$73") (pintype "bidirectional"))
    )
    (net (code "551") (name "ZZ.02.153") (class "Default")
      (node (ref "U$20") (pin "P$103") (pinfunction "D13_P$103") (pintype "bidirectional"))
    )
    (net (code "552") (name "ZZ.02.154") (class "Default")
      (node (ref "U$20") (pin "P$159") (pinfunction "F9_P$159") (pintype "bidirectional"))
    )
    (net (code "553") (name "ZZ.02.155") (class "Default")
      (node (ref "U$20") (pin "P$44") (pinfunction "B14_P$44") (pintype "bidirectional"))
    )
    (net (code "554") (name "ZZ.02.156") (class "Default")
      (node (ref "U$20") (pin "P$134") (pinfunction "E14_P$134") (pintype "bidirectional"))
    )
    (net (code "555") (name "ZZ.02.157") (class "Default")
      (node (ref "U$20") (pin "P$164") (pinfunction "F14_P$164") (pintype "bidirectional"))
    )
    (net (code "556") (name "ZZ.02.158") (class "Default")
      (node (ref "U$20") (pin "P$75") (pinfunction "C15_P$75") (pintype "bidirectional"))
    )
    (net (code "557") (name "ZZ.02.159") (class "Default")
      (node (ref "U$20") (pin "P$165") (pinfunction "F15_P$165") (pintype "bidirectional"))
    )
    (net (code "558") (name "ZZ.02.160") (class "Default")
      (node (ref "U$22") (pin "P$70") (pinfunction "C10_P$70") (pintype "bidirectional"))
    )
    (net (code "559") (name "ZZ.02.161") (class "Default")
      (node (ref "U$22") (pin "P$100") (pinfunction "D10_P$100") (pintype "bidirectional"))
    )
    (net (code "560") (name "ZZ.02.162") (class "Default")
      (node (ref "U$22") (pin "P$160") (pinfunction "F10_P$160") (pintype "bidirectional"))
    )
    (net (code "561") (name "ZZ.02.163") (class "Default")
      (node (ref "U$22") (pin "P$41") (pinfunction "B11_P$41") (pintype "bidirectional"))
    )
    (net (code "562") (name "ZZ.02.164") (class "Default")
      (node (ref "U$22") (pin "P$131") (pinfunction "E11_P$131") (pintype "bidirectional"))
    )
    (net (code "563") (name "ZZ.02.165") (class "Default")
      (node (ref "U$22") (pin "P$161") (pinfunction "F11_P$161") (pintype "bidirectional"))
    )
    (net (code "564") (name "ZZ.02.166") (class "Default")
      (node (ref "U$22") (pin "P$102") (pinfunction "D12_P$102") (pintype "bidirectional"))
    )
    (net (code "565") (name "ZZ.02.167") (class "Default")
      (node (ref "U$22") (pin "P$162") (pinfunction "F12_P$162") (pintype "bidirectional"))
    )
    (net (code "566") (name "ZZ.02.168") (class "Default")
      (node (ref "U$22") (pin "P$73") (pinfunction "C13_P$73") (pintype "bidirectional"))
    )
    (net (code "567") (name "ZZ.02.169") (class "Default")
      (node (ref "U$22") (pin "P$103") (pinfunction "D13_P$103") (pintype "bidirectional"))
    )
    (net (code "568") (name "ZZ.02.170") (class "Default")
      (node (ref "U$22") (pin "P$163") (pinfunction "F13_P$163") (pintype "bidirectional"))
    )
    (net (code "569") (name "ZZ.02.171") (class "Default")
      (node (ref "U$22") (pin "P$74") (pinfunction "C14_P$74") (pintype "bidirectional"))
    )
    (net (code "570") (name "ZZ.02.172") (class "Default")
      (node (ref "U$22") (pin "P$134") (pinfunction "E14_P$134") (pintype "bidirectional"))
    )
    (net (code "571") (name "ZZ.02.173") (class "Default")
      (node (ref "U$22") (pin "P$164") (pinfunction "F14_P$164") (pintype "bidirectional"))
    )
    (net (code "572") (name "ZZ.02.174") (class "Default")
      (node (ref "U$22") (pin "P$75") (pinfunction "C15_P$75") (pintype "bidirectional"))
    )
    (net (code "573") (name "ZZ.02.175") (class "Default")
      (node (ref "U$22") (pin "P$135") (pinfunction "E15_P$135") (pintype "bidirectional"))
    )
    (net (code "574") (name "ZZ.02.176") (class "Default")
      (node (ref "U$24") (pin "P$70") (pinfunction "C10_P$70") (pintype "bidirectional"))
    )
    (net (code "575") (name "ZZ.02.177") (class "Default")
      (node (ref "U$24") (pin "P$130") (pinfunction "E10_P$130") (pintype "bidirectional"))
    )
    (net (code "576") (name "ZZ.02.178") (class "Default")
      (node (ref "U$24") (pin "P$129") (pinfunction "E9_P$129") (pintype "bidirectional"))
    )
    (net (code "577") (name "ZZ.02.179") (class "Default")
      (node (ref "U$24") (pin "P$41") (pinfunction "B11_P$41") (pintype "bidirectional"))
    )
    (net (code "578") (name "ZZ.02.180") (class "Default")
      (node (ref "U$24") (pin "P$131") (pinfunction "E11_P$131") (pintype "bidirectional"))
    )
    (net (code "579") (name "ZZ.02.181") (class "Default")
      (node (ref "U$24") (pin "P$161") (pinfunction "F11_P$161") (pintype "bidirectional"))
    )
    (net (code "580") (name "ZZ.02.182") (class "Default")
      (node (ref "U$24") (pin "P$72") (pinfunction "C12_P$72") (pintype "bidirectional"))
    )
    (net (code "581") (name "ZZ.02.183") (class "Default")
      (node (ref "U$24") (pin "P$162") (pinfunction "F12_P$162") (pintype "bidirectional"))
    )
    (net (code "582") (name "ZZ.02.184") (class "Default")
      (node (ref "U$24") (pin "P$73") (pinfunction "C13_P$73") (pintype "bidirectional"))
    )
    (net (code "583") (name "ZZ.02.185") (class "Default")
      (node (ref "U$24") (pin "P$103") (pinfunction "D13_P$103") (pintype "bidirectional"))
    )
    (net (code "584") (name "ZZ.02.186") (class "Default")
      (node (ref "U$24") (pin "P$163") (pinfunction "F13_P$163") (pintype "bidirectional"))
    )
    (net (code "585") (name "ZZ.02.187") (class "Default")
      (node (ref "U$24") (pin "P$44") (pinfunction "B14_P$44") (pintype "bidirectional"))
    )
    (net (code "586") (name "ZZ.02.188") (class "Default")
      (node (ref "U$24") (pin "P$134") (pinfunction "E14_P$134") (pintype "bidirectional"))
    )
    (net (code "587") (name "ZZ.02.189") (class "Default")
      (node (ref "U$24") (pin "P$164") (pinfunction "F14_P$164") (pintype "bidirectional"))
    )
    (net (code "588") (name "ZZ.02.190") (class "Default")
      (node (ref "U$24") (pin "P$105") (pinfunction "D15_P$105") (pintype "bidirectional"))
    )
    (net (code "589") (name "ZZ.02.191") (class "Default")
      (node (ref "U$24") (pin "P$165") (pinfunction "F15_P$165") (pintype "bidirectional"))
    )
    (net (code "590") (name "ZZ.03.000") (class "Default")
      (node (ref "U$2") (pin "P$45") (pinfunction "B15_P$45") (pintype "bidirectional"))
    )
    (net (code "591") (name "ZZ.03.001") (class "Default")
      (node (ref "U$2") (pin "P$135") (pinfunction "E15_P$135") (pintype "bidirectional"))
    )
    (net (code "592") (name "ZZ.03.002") (class "Default")
      (node (ref "U$2") (pin "P$44") (pinfunction "B14_P$44") (pintype "bidirectional"))
    )
    (net (code "593") (name "ZZ.03.003") (class "Default")
      (node (ref "U$2") (pin "P$74") (pinfunction "C14_P$74") (pintype "bidirectional"))
    )
    (net (code "594") (name "ZZ.03.004") (class "Default")
      (node (ref "U$2") (pin "P$134") (pinfunction "E14_P$134") (pintype "bidirectional"))
    )
    (net (code "595") (name "ZZ.03.005") (class "Default")
      (node (ref "U$2") (pin "P$43") (pinfunction "B13_P$43") (pintype "bidirectional"))
    )
    (net (code "596") (name "ZZ.03.006") (class "Default")
      (node (ref "U$2") (pin "P$103") (pinfunction "D13_P$103") (pintype "bidirectional"))
    )
    (net (code "597") (name "ZZ.03.007") (class "Default")
      (node (ref "U$2") (pin "P$163") (pinfunction "F13_P$163") (pintype "bidirectional"))
    )
    (net (code "598") (name "ZZ.03.008") (class "Default")
      (node (ref "U$2") (pin "P$42") (pinfunction "B12_P$42") (pintype "bidirectional"))
    )
    (net (code "599") (name "ZZ.03.009") (class "Default")
      (node (ref "U$2") (pin "P$102") (pinfunction "D12_P$102") (pintype "bidirectional"))
    )
    (net (code "600") (name "ZZ.03.010") (class "Default")
      (node (ref "U$2") (pin "P$71") (pinfunction "C11_P$71") (pintype "bidirectional"))
    )
    (net (code "601") (name "ZZ.03.011") (class "Default")
      (node (ref "U$2") (pin "P$131") (pinfunction "E11_P$131") (pintype "bidirectional"))
    )
    (net (code "602") (name "ZZ.03.012") (class "Default")
      (node (ref "U$2") (pin "P$70") (pinfunction "C10_P$70") (pintype "bidirectional"))
    )
    (net (code "603") (name "ZZ.03.013") (class "Default")
      (node (ref "U$2") (pin "P$100") (pinfunction "D10_P$100") (pintype "bidirectional"))
    )
    (net (code "604") (name "ZZ.03.014") (class "Default")
      (node (ref "U$2") (pin "P$129") (pinfunction "E9_P$129") (pintype "bidirectional"))
    )
    (net (code "605") (name "ZZ.03.015") (class "Default")
      (node (ref "U$2") (pin "P$40") (pinfunction "B10_P$40") (pintype "bidirectional"))
    )
    (net (code "606") (name "ZZ.03.016") (class "Default")
      (node (ref "U$4") (pin "P$75") (pinfunction "C15_P$75") (pintype "bidirectional"))
    )
    (net (code "607") (name "ZZ.03.017") (class "Default")
      (node (ref "U$4") (pin "P$135") (pinfunction "E15_P$135") (pintype "bidirectional"))
    )
    (net (code "608") (name "ZZ.03.018") (class "Default")
      (node (ref "U$4") (pin "P$44") (pinfunction "B14_P$44") (pintype "bidirectional"))
    )
    (net (code "609") (name "ZZ.03.019") (class "Default")
      (node (ref "U$4") (pin "P$74") (pinfunction "C14_P$74") (pintype "bidirectional"))
    )
    (net (code "610") (name "ZZ.03.020") (class "Default")
      (node (ref "U$4") (pin "P$134") (pinfunction "E14_P$134") (pintype "bidirectional"))
    )
    (net (code "611") (name "ZZ.03.021") (class "Default")
      (node (ref "U$4") (pin "P$73") (pinfunction "C13_P$73") (pintype "bidirectional"))
    )
    (net (code "612") (name "ZZ.03.022") (class "Default")
      (node (ref "U$4") (pin "P$103") (pinfunction "D13_P$103") (pintype "bidirectional"))
    )
    (net (code "613") (name "ZZ.03.023") (class "Default")
      (node (ref "U$4") (pin "P$163") (pinfunction "F13_P$163") (pintype "bidirectional"))
    )
    (net (code "614") (name "ZZ.03.024") (class "Default")
      (node (ref "U$4") (pin "P$42") (pinfunction "B12_P$42") (pintype "bidirectional"))
    )
    (net (code "615") (name "ZZ.03.025") (class "Default")
      (node (ref "U$4") (pin "P$132") (pinfunction "E12_P$132") (pintype "bidirectional"))
    )
    (net (code "616") (name "ZZ.03.026") (class "Default")
      (node (ref "U$4") (pin "P$131") (pinfunction "E11_P$131") (pintype "bidirectional"))
    )
    (net (code "617") (name "ZZ.03.027") (class "Default")
      (node (ref "U$4") (pin "P$130") (pinfunction "E10_P$130") (pintype "bidirectional"))
    )
    (net (code "618") (name "ZZ.03.028") (class "Default")
      (node (ref "U$4") (pin "P$129") (pinfunction "E9_P$129") (pintype "bidirectional"))
    )
    (net (code "619") (name "ZZ.03.029") (class "Default")
      (node (ref "U$4") (pin "P$40") (pinfunction "B10_P$40") (pintype "bidirectional"))
    )
    (net (code "620") (name "ZZ.03.030") (class "Default")
      (node (ref "U$4") (pin "P$70") (pinfunction "C10_P$70") (pintype "bidirectional"))
    )
    (net (code "621") (name "ZZ.03.031") (class "Default")
      (node (ref "U$4") (pin "P$100") (pinfunction "D10_P$100") (pintype "bidirectional"))
    )
    (net (code "622") (name "ZZ.03.032") (class "Default")
      (node (ref "U$6") (pin "P$45") (pinfunction "B15_P$45") (pintype "bidirectional"))
    )
    (net (code "623") (name "ZZ.03.033") (class "Default")
      (node (ref "U$6") (pin "P$105") (pinfunction "D15_P$105") (pintype "bidirectional"))
    )
    (net (code "624") (name "ZZ.03.034") (class "Default")
      (node (ref "U$6") (pin "P$44") (pinfunction "B14_P$44") (pintype "bidirectional"))
    )
    (net (code "625") (name "ZZ.03.035") (class "Default")
      (node (ref "U$6") (pin "P$74") (pinfunction "C14_P$74") (pintype "bidirectional"))
    )
    (net (code "626") (name "ZZ.03.036") (class "Default")
      (node (ref "U$6") (pin "P$164") (pinfunction "F14_P$164") (pintype "bidirectional"))
    )
    (net (code "627") (name "ZZ.03.037") (class "Default")
      (node (ref "U$6") (pin "P$43") (pinfunction "B13_P$43") (pintype "bidirectional"))
    )
    (net (code "628") (name "ZZ.03.038") (class "Default")
      (node (ref "U$6") (pin "P$133") (pinfunction "E13_P$133") (pintype "bidirectional"))
    )
    (net (code "629") (name "ZZ.03.039") (class "Default")
      (node (ref "U$6") (pin "P$159") (pinfunction "F9_P$159") (pintype "bidirectional"))
    )
    (net (code "630") (name "ZZ.03.040") (class "Default")
      (node (ref "U$6") (pin "P$42") (pinfunction "B12_P$42") (pintype "bidirectional"))
    )
    (net (code "631") (name "ZZ.03.041") (class "Default")
      (node (ref "U$6") (pin "P$102") (pinfunction "D12_P$102") (pintype "bidirectional"))
    )
    (net (code "632") (name "ZZ.03.042") (class "Default")
      (node (ref "U$6") (pin "P$129") (pinfunction "E9_P$129") (pintype "bidirectional"))
    )
    (net (code "633") (name "ZZ.03.043") (class "Default")
      (node (ref "U$6") (pin "P$40") (pinfunction "B10_P$40") (pintype "bidirectional"))
    )
    (net (code "634") (name "ZZ.03.044") (class "Default")
      (node (ref "U$6") (pin "P$70") (pinfunction "C10_P$70") (pintype "bidirectional"))
    )
    (net (code "635") (name "ZZ.03.045") (class "Default")
      (node (ref "U$6") (pin "P$100") (pinfunction "D10_P$100") (pintype "bidirectional"))
    )
    (net (code "636") (name "ZZ.03.046") (class "Default")
      (node (ref "U$6") (pin "P$130") (pinfunction "E10_P$130") (pintype "bidirectional"))
    )
    (net (code "637") (name "ZZ.03.047") (class "Default")
      (node (ref "U$6") (pin "P$160") (pinfunction "F10_P$160") (pintype "bidirectional"))
    )
    (net (code "638") (name "ZZ.03.048") (class "Default")
      (node (ref "U$8") (pin "P$75") (pinfunction "C15_P$75") (pintype "bidirectional"))
    )
    (net (code "639") (name "ZZ.03.049") (class "Default")
      (node (ref "U$8") (pin "P$135") (pinfunction "E15_P$135") (pintype "bidirectional"))
    )
    (net (code "640") (name "ZZ.03.050") (class "Default")
      (node (ref "U$8") (pin "P$44") (pinfunction "B14_P$44") (pintype "bidirectional"))
    )
    (net (code "641") (name "ZZ.03.051") (class "Default")
      (node (ref "U$8") (pin "P$104") (pinfunction "D14_P$104") (pintype "bidirectional"))
    )
    (net (code "642") (name "ZZ.03.052") (class "Default")
      (node (ref "U$8") (pin "P$164") (pinfunction "F14_P$164") (pintype "bidirectional"))
    )
    (net (code "643") (name "ZZ.03.053") (class "Default")
      (node (ref "U$8") (pin "P$43") (pinfunction "B13_P$43") (pintype "bidirectional"))
    )
    (net (code "644") (name "ZZ.03.054") (class "Default")
      (node (ref "U$8") (pin "P$103") (pinfunction "D13_P$103") (pintype "bidirectional"))
    )
    (net (code "645") (name "ZZ.03.055") (class "Default")
      (node (ref "U$8") (pin "P$42") (pinfunction "B12_P$42") (pintype "bidirectional"))
    )
    (net (code "646") (name "ZZ.03.056") (class "Default")
      (node (ref "U$8") (pin "P$40") (pinfunction "B10_P$40") (pintype "bidirectional"))
    )
    (net (code "647") (name "ZZ.03.057") (class "Default")
      (node (ref "U$8") (pin "P$70") (pinfunction "C10_P$70") (pintype "bidirectional"))
    )
    (net (code "648") (name "ZZ.03.058") (class "Default")
      (node (ref "U$8") (pin "P$100") (pinfunction "D10_P$100") (pintype "bidirectional"))
    )
    (net (code "649") (name "ZZ.03.059") (class "Default")
      (node (ref "U$8") (pin "P$130") (pinfunction "E10_P$130") (pintype "bidirectional"))
    )
    (net (code "650") (name "ZZ.03.060") (class "Default")
      (node (ref "U$8") (pin "P$160") (pinfunction "F10_P$160") (pintype "bidirectional"))
    )
    (net (code "651") (name "ZZ.03.061") (class "Default")
      (node (ref "U$8") (pin "P$129") (pinfunction "E9_P$129") (pintype "bidirectional"))
    )
    (net (code "652") (name "ZZ.03.062") (class "Default")
      (node (ref "U$8") (pin "P$162") (pinfunction "F12_P$162") (pintype "bidirectional"))
    )
    (net (code "653") (name "ZZ.03.063") (class "Default")
      (node (ref "U$8") (pin "P$159") (pinfunction "F9_P$159") (pintype "bidirectional"))
    )
    (net (code "654") (name "ZZ.03.064") (class "Default")
      (node (ref "U$10") (pin "P$75") (pinfunction "C15_P$75") (pintype "bidirectional"))
    )
    (net (code "655") (name "ZZ.03.065") (class "Default")
      (node (ref "U$10") (pin "P$135") (pinfunction "E15_P$135") (pintype "bidirectional"))
    )
    (net (code "656") (name "ZZ.03.066") (class "Default")
      (node (ref "U$10") (pin "P$44") (pinfunction "B14_P$44") (pintype "bidirectional"))
    )
    (net (code "657") (name "ZZ.03.067") (class "Default")
      (node (ref "U$10") (pin "P$43") (pinfunction "B13_P$43") (pintype "bidirectional"))
    )
    (net (code "658") (name "ZZ.03.068") (class "Default")
      (node (ref "U$10") (pin "P$73") (pinfunction "C13_P$73") (pintype "bidirectional"))
    )
    (net (code "659") (name "ZZ.03.069") (class "Default")
      (node (ref "U$10") (pin "P$72") (pinfunction "C12_P$72") (pintype "bidirectional"))
    )
    (net (code "660") (name "ZZ.03.070") (class "Default")
      (node (ref "U$10") (pin "P$40") (pinfunction "B10_P$40") (pintype "bidirectional"))
    )
    (net (code "661") (name "ZZ.03.071") (class "Default")
      (node (ref "U$10") (pin "P$70") (pinfunction "C10_P$70") (pintype "bidirectional"))
    )
    (net (code "662") (name "ZZ.03.072") (class "Default")
      (node (ref "U$10") (pin "P$100") (pinfunction "D10_P$100") (pintype "bidirectional"))
    )
    (net (code "663") (name "ZZ.03.073") (class "Default")
      (node (ref "U$10") (pin "P$130") (pinfunction "E10_P$130") (pintype "bidirectional"))
    )
    (net (code "664") (name "ZZ.03.074") (class "Default")
      (node (ref "U$10") (pin "P$160") (pinfunction "F10_P$160") (pintype "bidirectional"))
    )
    (net (code "665") (name "ZZ.03.075") (class "Default")
      (node (ref "U$10") (pin "P$129") (pinfunction "E9_P$129") (pintype "bidirectional"))
    )
    (net (code "666") (name "ZZ.03.076") (class "Default")
      (node (ref "U$10") (pin "P$132") (pinfunction "E12_P$132") (pintype "bidirectional"))
    )
    (net (code "667") (name "ZZ.03.077") (class "Default")
      (node (ref "U$10") (pin "P$163") (pinfunction "F13_P$163") (pintype "bidirectional"))
    )
    (net (code "668") (name "ZZ.03.078") (class "Default")
      (node (ref "U$10") (pin "P$134") (pinfunction "E14_P$134") (pintype "bidirectional"))
    )
    (net (code "669") (name "ZZ.03.079") (class "Default")
      (node (ref "U$10") (pin "P$165") (pinfunction "F15_P$165") (pintype "bidirectional"))
    )
    (net (code "670") (name "ZZ.03.080") (class "Default")
      (node (ref "U$12") (pin "P$44") (pinfunction "B14_P$44") (pintype "bidirectional"))
    )
    (net (code "671") (name "ZZ.03.081") (class "Default")
      (node (ref "U$12") (pin "P$43") (pinfunction "B13_P$43") (pintype "bidirectional"))
    )
    (net (code "672") (name "ZZ.03.082") (class "Default")
      (node (ref "U$12") (pin "P$73") (pinfunction "C13_P$73") (pintype "bidirectional"))
    )
    (net (code "673") (name "ZZ.03.083") (class "Default")
      (node (ref "U$12") (pin "P$72") (pinfunction "C12_P$72") (pintype "bidirectional"))
    )
    (net (code "674") (name "ZZ.03.084") (class "Default")
      (node (ref "U$12") (pin "P$40") (pinfunction "B10_P$40") (pintype "bidirectional"))
    )
    (net (code "675") (name "ZZ.03.085") (class "Default")
      (node (ref "U$12") (pin "P$70") (pinfunction "C10_P$70") (pintype "bidirectional"))
    )
    (net (code "676") (name "ZZ.03.086") (class "Default")
      (node (ref "U$12") (pin "P$100") (pinfunction "D10_P$100") (pintype "bidirectional"))
    )
    (net (code "677") (name "ZZ.03.087") (class "Default")
      (node (ref "U$12") (pin "P$130") (pinfunction "E10_P$130") (pintype "bidirectional"))
    )
    (net (code "678") (name "ZZ.03.088") (class "Default")
      (node (ref "U$12") (pin "P$160") (pinfunction "F10_P$160") (pintype "bidirectional"))
    )
    (net (code "679") (name "ZZ.03.089") (class "Default")
      (node (ref "U$12") (pin "P$129") (pinfunction "E9_P$129") (pintype "bidirectional"))
    )
    (net (code "680") (name "ZZ.03.090") (class "Default")
      (node (ref "U$12") (pin "P$162") (pinfunction "F12_P$162") (pintype "bidirectional"))
    )
    (net (code "681") (name "ZZ.03.091") (class "Default")
      (node (ref "U$12") (pin "P$163") (pinfunction "F13_P$163") (pintype "bidirectional"))
    )
    (net (code "682") (name "ZZ.03.092") (class "Default")
      (node (ref "U$12") (pin "P$134") (pinfunction "E14_P$134") (pintype "bidirectional"))
    )
    (net (code "683") (name "ZZ.03.093") (class "Default")
      (node (ref "U$12") (pin "P$45") (pinfunction "B15_P$45") (pintype "bidirectional"))
    )
    (net (code "684") (name "ZZ.03.094") (class "Default")
      (node (ref "U$12") (pin "P$105") (pinfunction "D15_P$105") (pintype "bidirectional"))
    )
    (net (code "685") (name "ZZ.03.095") (class "Default")
      (node (ref "U$12") (pin "P$135") (pinfunction "E15_P$135") (pintype "bidirectional"))
    )
    (net (code "686") (name "ZZ.03.096") (class "Default")
      (node (ref "U$14") (pin "P$42") (pinfunction "B12_P$42") (pintype "bidirectional"))
    )
    (net (code "687") (name "ZZ.03.097") (class "Default")
      (node (ref "U$14") (pin "P$40") (pinfunction "B10_P$40") (pintype "bidirectional"))
    )
    (net (code "688") (name "ZZ.03.098") (class "Default")
      (node (ref "U$14") (pin "P$70") (pinfunction "C10_P$70") (pintype "bidirectional"))
    )
    (net (code "689") (name "ZZ.03.099") (class "Default")
      (node (ref "U$14") (pin "P$100") (pinfunction "D10_P$100") (pintype "bidirectional"))
    )
    (net (code "690") (name "ZZ.03.100") (class "Default")
      (node (ref "U$14") (pin "P$130") (pinfunction "E10_P$130") (pintype "bidirectional"))
    )
    (net (code "691") (name "ZZ.03.101") (class "Default")
      (node (ref "U$14") (pin "P$160") (pinfunction "F10_P$160") (pintype "bidirectional"))
    )
    (net (code "692") (name "ZZ.03.102") (class "Default")
      (node (ref "U$14") (pin "P$129") (pinfunction "E9_P$129") (pintype "bidirectional"))
    )
    (net (code "693") (name "ZZ.03.103") (class "Default")
      (node (ref "U$14") (pin "P$162") (pinfunction "F12_P$162") (pintype "bidirectional"))
    )
    (net (code "694") (name "ZZ.03.104") (class "Default")
      (node (ref "U$14") (pin "P$43") (pinfunction "B13_P$43") (pintype "bidirectional"))
    )
    (net (code "695") (name "ZZ.03.105") (class "Default")
      (node (ref "U$14") (pin "P$103") (pinfunction "D13_P$103") (pintype "bidirectional"))
    )
    (net (code "696") (name "ZZ.03.106") (class "Default")
      (node (ref "U$14") (pin "P$163") (pinfunction "F13_P$163") (pintype "bidirectional"))
    )
    (net (code "697") (name "ZZ.03.107") (class "Default")
      (node (ref "U$14") (pin "P$74") (pinfunction "C14_P$74") (pintype "bidirectional"))
    )
    (net (code "698") (name "ZZ.03.108") (class "Default")
      (node (ref "U$14") (pin "P$134") (pinfunction "E14_P$134") (pintype "bidirectional"))
    )
    (net (code "699") (name "ZZ.03.109") (class "Default")
      (node (ref "U$14") (pin "P$45") (pinfunction "B15_P$45") (pintype "bidirectional"))
    )
    (net (code "700") (name "ZZ.03.110") (class "Default")
      (node (ref "U$14") (pin "P$105") (pinfunction "D15_P$105") (pintype "bidirectional"))
    )
    (net (code "701") (name "ZZ.03.111") (class "Default")
      (node (ref "U$14") (pin "P$135") (pinfunction "E15_P$135") (pintype "bidirectional"))
    )
    (net (code "702") (name "ZZ.03.112") (class "Default")
      (node (ref "U$16") (pin "P$70") (pinfunction "C10_P$70") (pintype "bidirectional"))
    )
    (net (code "703") (name "ZZ.03.113") (class "Default")
      (node (ref "U$16") (pin "P$100") (pinfunction "D10_P$100") (pintype "bidirectional"))
    )
    (net (code "704") (name "ZZ.03.114") (class "Default")
      (node (ref "U$16") (pin "P$130") (pinfunction "E10_P$130") (pintype "bidirectional"))
    )
    (net (code "705") (name "ZZ.03.115") (class "Default")
      (node (ref "U$16") (pin "P$160") (pinfunction "F10_P$160") (pintype "bidirectional"))
    )
    (net (code "706") (name "ZZ.03.116") (class "Default")
      (node (ref "U$16") (pin "P$129") (pinfunction "E9_P$129") (pintype "bidirectional"))
    )
    (net (code "707") (name "ZZ.03.117") (class "Default")
      (node (ref "U$16") (pin "P$42") (pinfunction "B12_P$42") (pintype "bidirectional"))
    )
    (net (code "708") (name "ZZ.03.118") (class "Default")
      (node (ref "U$16") (pin "P$102") (pinfunction "D12_P$102") (pintype "bidirectional"))
    )
    (net (code "709") (name "ZZ.03.119") (class "Default")
      (node (ref "U$16") (pin "P$132") (pinfunction "E12_P$132") (pintype "bidirectional"))
    )
    (net (code "710") (name "ZZ.03.120") (class "Default")
      (node (ref "U$16") (pin "P$43") (pinfunction "B13_P$43") (pintype "bidirectional"))
    )
    (net (code "711") (name "ZZ.03.121") (class "Default")
      (node (ref "U$16") (pin "P$133") (pinfunction "E13_P$133") (pintype "bidirectional"))
    )
    (net (code "712") (name "ZZ.03.122") (class "Default")
      (node (ref "U$16") (pin "P$163") (pinfunction "F13_P$163") (pintype "bidirectional"))
    )
    (net (code "713") (name "ZZ.03.123") (class "Default")
      (node (ref "U$16") (pin "P$44") (pinfunction "B14_P$44") (pintype "bidirectional"))
    )
    (net (code "714") (name "ZZ.03.124") (class "Default")
      (node (ref "U$16") (pin "P$104") (pinfunction "D14_P$104") (pintype "bidirectional"))
    )
    (net (code "715") (name "ZZ.03.125") (class "Default")
      (node (ref "U$16") (pin "P$45") (pinfunction "B15_P$45") (pintype "bidirectional"))
    )
    (net (code "716") (name "ZZ.03.126") (class "Default")
      (node (ref "U$16") (pin "P$105") (pinfunction "D15_P$105") (pintype "bidirectional"))
    )
    (net (code "717") (name "ZZ.03.127") (class "Default")
      (node (ref "U$16") (pin "P$165") (pinfunction "F15_P$165") (pintype "bidirectional"))
    )
    (net (code "718") (name "ZZ.03.128") (class "Default")
      (node (ref "U$18") (pin "P$130") (pinfunction "E10_P$130") (pintype "bidirectional"))
    )
    (net (code "719") (name "ZZ.03.129") (class "Default")
      (node (ref "U$18") (pin "P$160") (pinfunction "F10_P$160") (pintype "bidirectional"))
    )
    (net (code "720") (name "ZZ.03.130") (class "Default")
      (node (ref "U$18") (pin "P$129") (pinfunction "E9_P$129") (pintype "bidirectional"))
    )
    (net (code "721") (name "ZZ.03.131") (class "Default")
      (node (ref "U$18") (pin "P$70") (pinfunction "C10_P$70") (pintype "bidirectional"))
    )
    (net (code "722") (name "ZZ.03.132") (class "Default")
      (node (ref "U$18") (pin "P$41") (pinfunction "B11_P$41") (pintype "bidirectional"))
    )
    (net (code "723") (name "ZZ.03.133") (class "Default")
      (node (ref "U$18") (pin "P$42") (pinfunction "B12_P$42") (pintype "bidirectional"))
    )
    (net (code "724") (name "ZZ.03.134") (class "Default")
      (node (ref "U$18") (pin "P$102") (pinfunction "D12_P$102") (pintype "bidirectional"))
    )
    (net (code "725") (name "ZZ.03.135") (class "Default")
      (node (ref "U$18") (pin "P$162") (pinfunction "F12_P$162") (pintype "bidirectional"))
    )
    (net (code "726") (name "ZZ.03.136") (class "Default")
      (node (ref "U$18") (pin "P$73") (pinfunction "C13_P$73") (pintype "bidirectional"))
    )
    (net (code "727") (name "ZZ.03.137") (class "Default")
      (node (ref "U$18") (pin "P$133") (pinfunction "E13_P$133") (pintype "bidirectional"))
    )
    (net (code "728") (name "ZZ.03.138") (class "Default")
      (node (ref "U$18") (pin "P$159") (pinfunction "F9_P$159") (pintype "bidirectional"))
    )
    (net (code "729") (name "ZZ.03.139") (class "Default")
      (node (ref "U$18") (pin "P$44") (pinfunction "B14_P$44") (pintype "bidirectional"))
    )
    (net (code "730") (name "ZZ.03.140") (class "Default")
      (node (ref "U$18") (pin "P$104") (pinfunction "D14_P$104") (pintype "bidirectional"))
    )
    (net (code "731") (name "ZZ.03.141") (class "Default")
      (node (ref "U$18") (pin "P$45") (pinfunction "B15_P$45") (pintype "bidirectional"))
    )
    (net (code "732") (name "ZZ.03.142") (class "Default")
      (node (ref "U$18") (pin "P$75") (pinfunction "C15_P$75") (pintype "bidirectional"))
    )
    (net (code "733") (name "ZZ.03.143") (class "Default")
      (node (ref "U$18") (pin "P$165") (pinfunction "F15_P$165") (pintype "bidirectional"))
    )
    (net (code "734") (name "ZZ.03.144") (class "Default")
      (node (ref "U$20") (pin "P$129") (pinfunction "E9_P$129") (pintype "bidirectional"))
    )
    (net (code "735") (name "ZZ.03.145") (class "Default")
      (node (ref "U$20") (pin "P$70") (pinfunction "C10_P$70") (pintype "bidirectional"))
    )
    (net (code "736") (name "ZZ.03.146") (class "Default")
      (node (ref "U$20") (pin "P$130") (pinfunction "E10_P$130") (pintype "bidirectional"))
    )
    (net (code "737") (name "ZZ.03.147") (class "Default")
      (node (ref "U$20") (pin "P$71") (pinfunction "C11_P$71") (pintype "bidirectional"))
    )
    (net (code "738") (name "ZZ.03.148") (class "Default")
      (node (ref "U$20") (pin "P$101") (pinfunction "D11_P$101") (pintype "bidirectional"))
    )
    (net (code "739") (name "ZZ.03.149") (class "Default")
      (node (ref "U$20") (pin "P$42") (pinfunction "B12_P$42") (pintype "bidirectional"))
    )
    (net (code "740") (name "ZZ.03.150") (class "Default")
      (node (ref "U$20") (pin "P$72") (pinfunction "C12_P$72") (pintype "bidirectional"))
    )
    (net (code "741") (name "ZZ.03.151") (class "Default")
      (node (ref "U$20") (pin "P$162") (pinfunction "F12_P$162") (pintype "bidirectional"))
    )
    (net (code "742") (name "ZZ.03.152") (class "Default")
      (node (ref "U$20") (pin "P$43") (pinfunction "B13_P$43") (pintype "bidirectional"))
    )
    (net (code "743") (name "ZZ.03.153") (class "Default")
      (node (ref "U$20") (pin "P$133") (pinfunction "E13_P$133") (pintype "bidirectional"))
    )
    (net (code "744") (name "ZZ.03.154") (class "Default")
      (node (ref "U$20") (pin "P$163") (pinfunction "F13_P$163") (pintype "bidirectional"))
    )
    (net (code "745") (name "ZZ.03.155") (class "Default")
      (node (ref "U$20") (pin "P$74") (pinfunction "C14_P$74") (pintype "bidirectional"))
    )
    (net (code "746") (name "ZZ.03.156") (class "Default")
      (node (ref "U$20") (pin "P$104") (pinfunction "D14_P$104") (pintype "bidirectional"))
    )
    (net (code "747") (name "ZZ.03.157") (class "Default")
      (node (ref "U$20") (pin "P$45") (pinfunction "B15_P$45") (pintype "bidirectional"))
    )
    (net (code "748") (name "ZZ.03.158") (class "Default")
      (node (ref "U$20") (pin "P$105") (pinfunction "D15_P$105") (pintype "bidirectional"))
    )
    (net (code "749") (name "ZZ.03.159") (class "Default")
      (node (ref "U$20") (pin "P$135") (pinfunction "E15_P$135") (pintype "bidirectional"))
    )
    (net (code "750") (name "ZZ.03.160") (class "Default")
      (node (ref "U$22") (pin "P$40") (pinfunction "B10_P$40") (pintype "bidirectional"))
    )
    (net (code "751") (name "ZZ.03.161") (class "Default")
      (node (ref "U$22") (pin "P$130") (pinfunction "E10_P$130") (pintype "bidirectional"))
    )
    (net (code "752") (name "ZZ.03.162") (class "Default")
      (node (ref "U$22") (pin "P$129") (pinfunction "E9_P$129") (pintype "bidirectional"))
    )
    (net (code "753") (name "ZZ.03.163") (class "Default")
      (node (ref "U$22") (pin "P$71") (pinfunction "C11_P$71") (pintype "bidirectional"))
    )
    (net (code "754") (name "ZZ.03.164") (class "Default")
      (node (ref "U$22") (pin "P$101") (pinfunction "D11_P$101") (pintype "bidirectional"))
    )
    (net (code "755") (name "ZZ.03.165") (class "Default")
      (node (ref "U$22") (pin "P$42") (pinfunction "B12_P$42") (pintype "bidirectional"))
    )
    (net (code "756") (name "ZZ.03.166") (class "Default")
      (node (ref "U$22") (pin "P$72") (pinfunction "C12_P$72") (pintype "bidirectional"))
    )
    (net (code "757") (name "ZZ.03.167") (class "Default")
      (node (ref "U$22") (pin "P$132") (pinfunction "E12_P$132") (pintype "bidirectional"))
    )
    (net (code "758") (name "ZZ.03.168") (class "Default")
      (node (ref "U$22") (pin "P$43") (pinfunction "B13_P$43") (pintype "bidirectional"))
    )
    (net (code "759") (name "ZZ.03.169") (class "Default")
      (node (ref "U$22") (pin "P$133") (pinfunction "E13_P$133") (pintype "bidirectional"))
    )
    (net (code "760") (name "ZZ.03.170") (class "Default")
      (node (ref "U$22") (pin "P$159") (pinfunction "F9_P$159") (pintype "bidirectional"))
    )
    (net (code "761") (name "ZZ.03.171") (class "Default")
      (node (ref "U$22") (pin "P$44") (pinfunction "B14_P$44") (pintype "bidirectional"))
    )
    (net (code "762") (name "ZZ.03.172") (class "Default")
      (node (ref "U$22") (pin "P$104") (pinfunction "D14_P$104") (pintype "bidirectional"))
    )
    (net (code "763") (name "ZZ.03.173") (class "Default")
      (node (ref "U$22") (pin "P$45") (pinfunction "B15_P$45") (pintype "bidirectional"))
    )
    (net (code "764") (name "ZZ.03.174") (class "Default")
      (node (ref "U$22") (pin "P$105") (pinfunction "D15_P$105") (pintype "bidirectional"))
    )
    (net (code "765") (name "ZZ.03.175") (class "Default")
      (node (ref "U$22") (pin "P$165") (pinfunction "F15_P$165") (pintype "bidirectional"))
    )
    (net (code "766") (name "ZZ.03.176") (class "Default")
      (node (ref "U$24") (pin "P$40") (pinfunction "B10_P$40") (pintype "bidirectional"))
    )
    (net (code "767") (name "ZZ.03.177") (class "Default")
      (node (ref "U$24") (pin "P$100") (pinfunction "D10_P$100") (pintype "bidirectional"))
    )
    (net (code "768") (name "ZZ.03.178") (class "Default")
      (node (ref "U$24") (pin "P$160") (pinfunction "F10_P$160") (pintype "bidirectional"))
    )
    (net (code "769") (name "ZZ.03.179") (class "Default")
      (node (ref "U$24") (pin "P$71") (pinfunction "C11_P$71") (pintype "bidirectional"))
    )
    (net (code "770") (name "ZZ.03.180") (class "Default")
      (node (ref "U$24") (pin "P$101") (pinfunction "D11_P$101") (pintype "bidirectional"))
    )
    (net (code "771") (name "ZZ.03.181") (class "Default")
      (node (ref "U$24") (pin "P$42") (pinfunction "B12_P$42") (pintype "bidirectional"))
    )
    (net (code "772") (name "ZZ.03.182") (class "Default")
      (node (ref "U$24") (pin "P$102") (pinfunction "D12_P$102") (pintype "bidirectional"))
    )
    (net (code "773") (name "ZZ.03.183") (class "Default")
      (node (ref "U$24") (pin "P$132") (pinfunction "E12_P$132") (pintype "bidirectional"))
    )
    (net (code "774") (name "ZZ.03.184") (class "Default")
      (node (ref "U$24") (pin "P$43") (pinfunction "B13_P$43") (pintype "bidirectional"))
    )
    (net (code "775") (name "ZZ.03.185") (class "Default")
      (node (ref "U$24") (pin "P$133") (pinfunction "E13_P$133") (pintype "bidirectional"))
    )
    (net (code "776") (name "ZZ.03.186") (class "Default")
      (node (ref "U$24") (pin "P$159") (pinfunction "F9_P$159") (pintype "bidirectional"))
    )
    (net (code "777") (name "ZZ.03.187") (class "Default")
      (node (ref "U$24") (pin "P$74") (pinfunction "C14_P$74") (pintype "bidirectional"))
    )
    (net (code "778") (name "ZZ.03.188") (class "Default")
      (node (ref "U$24") (pin "P$104") (pinfunction "D14_P$104") (pintype "bidirectional"))
    )
    (net (code "779") (name "ZZ.03.189") (class "Default")
      (node (ref "U$24") (pin "P$45") (pinfunction "B15_P$45") (pintype "bidirectional"))
    )
    (net (code "780") (name "ZZ.03.190") (class "Default")
      (node (ref "U$24") (pin "P$75") (pinfunction "C15_P$75") (pintype "bidirectional"))
    )
    (net (code "781") (name "ZZ.03.191") (class "Default")
      (node (ref "U$24") (pin "P$135") (pinfunction "E15_P$135") (pintype "bidirectional"))
    )
    (net (code "782") (name "ZZ.04.000") (class "Default")
      (node (ref "U$2") (pin "P$49") (pinfunction "B19_P$49") (pintype "bidirectional"))
    )
    (net (code "783") (name "ZZ.04.001") (class "Default")
      (node (ref "U$2") (pin "P$79") (pinfunction "C19_P$79") (pintype "bidirectional"))
    )
    (net (code "784") (name "ZZ.04.002") (class "Default")
      (node (ref "U$2") (pin "P$109") (pinfunction "D19_P$109") (pintype "bidirectional"))
    )
    (net (code "785") (name "ZZ.04.003") (class "Default")
      (node (ref "U$2") (pin "P$139") (pinfunction "E19_P$139") (pintype "bidirectional"))
    )
    (net (code "786") (name "ZZ.04.004") (class "Default")
      (node (ref "U$2") (pin "P$169") (pinfunction "F19_P$169") (pintype "bidirectional"))
    )
    (net (code "787") (name "ZZ.04.005") (class "Default")
      (node (ref "U$2") (pin "P$48") (pinfunction "B18_P$48") (pintype "bidirectional"))
    )
    (net (code "788") (name "ZZ.04.006") (class "Default")
      (node (ref "U$2") (pin "P$78") (pinfunction "C18_P$78") (pintype "bidirectional"))
    )
    (net (code "789") (name "ZZ.04.007") (class "Default")
      (node (ref "U$2") (pin "P$108") (pinfunction "D18_P$108") (pintype "bidirectional"))
    )
    (net (code "790") (name "ZZ.04.008") (class "Default")
      (node (ref "U$2") (pin "P$138") (pinfunction "E18_P$138") (pintype "bidirectional"))
    )
    (net (code "791") (name "ZZ.04.009") (class "Default")
      (node (ref "U$2") (pin "P$168") (pinfunction "F18_P$168") (pintype "bidirectional"))
    )
    (net (code "792") (name "ZZ.04.010") (class "Default")
      (node (ref "U$2") (pin "P$47") (pinfunction "B17_P$47") (pintype "bidirectional"))
    )
    (net (code "793") (name "ZZ.04.011") (class "Default")
      (node (ref "U$2") (pin "P$77") (pinfunction "C17_P$77") (pintype "bidirectional"))
    )
    (net (code "794") (name "ZZ.04.012") (class "Default")
      (node (ref "U$2") (pin "P$107") (pinfunction "D17_P$107") (pintype "bidirectional"))
    )
    (net (code "795") (name "ZZ.04.013") (class "Default")
      (node (ref "U$2") (pin "P$137") (pinfunction "E17_P$137") (pintype "bidirectional"))
    )
    (net (code "796") (name "ZZ.04.014") (class "Default")
      (node (ref "U$2") (pin "P$167") (pinfunction "F17_P$167") (pintype "bidirectional"))
    )
    (net (code "797") (name "ZZ.04.015") (class "Default")
      (node (ref "U$2") (pin "P$136") (pinfunction "E16_P$136") (pintype "bidirectional"))
    )
    (net (code "798") (name "ZZ.04.016") (class "Default")
      (node (ref "U$4") (pin "P$49") (pinfunction "B19_P$49") (pintype "bidirectional"))
    )
    (net (code "799") (name "ZZ.04.017") (class "Default")
      (node (ref "U$4") (pin "P$79") (pinfunction "C19_P$79") (pintype "bidirectional"))
    )
    (net (code "800") (name "ZZ.04.018") (class "Default")
      (node (ref "U$4") (pin "P$109") (pinfunction "D19_P$109") (pintype "bidirectional"))
    )
    (net (code "801") (name "ZZ.04.019") (class "Default")
      (node (ref "U$4") (pin "P$139") (pinfunction "E19_P$139") (pintype "bidirectional"))
    )
    (net (code "802") (name "ZZ.04.020") (class "Default")
      (node (ref "U$4") (pin "P$169") (pinfunction "F19_P$169") (pintype "bidirectional"))
    )
    (net (code "803") (name "ZZ.04.021") (class "Default")
      (node (ref "U$4") (pin "P$48") (pinfunction "B18_P$48") (pintype "bidirectional"))
    )
    (net (code "804") (name "ZZ.04.022") (class "Default")
      (node (ref "U$4") (pin "P$78") (pinfunction "C18_P$78") (pintype "bidirectional"))
    )
    (net (code "805") (name "ZZ.04.023") (class "Default")
      (node (ref "U$4") (pin "P$108") (pinfunction "D18_P$108") (pintype "bidirectional"))
    )
    (net (code "806") (name "ZZ.04.024") (class "Default")
      (node (ref "U$4") (pin "P$138") (pinfunction "E18_P$138") (pintype "bidirectional"))
    )
    (net (code "807") (name "ZZ.04.025") (class "Default")
      (node (ref "U$4") (pin "P$168") (pinfunction "F18_P$168") (pintype "bidirectional"))
    )
    (net (code "808") (name "ZZ.04.026") (class "Default")
      (node (ref "U$4") (pin "P$47") (pinfunction "B17_P$47") (pintype "bidirectional"))
    )
    (net (code "809") (name "ZZ.04.027") (class "Default")
      (node (ref "U$4") (pin "P$77") (pinfunction "C17_P$77") (pintype "bidirectional"))
    )
    (net (code "810") (name "ZZ.04.028") (class "Default")
      (node (ref "U$4") (pin "P$107") (pinfunction "D17_P$107") (pintype "bidirectional"))
    )
    (net (code "811") (name "ZZ.04.029") (class "Default")
      (node (ref "U$4") (pin "P$137") (pinfunction "E17_P$137") (pintype "bidirectional"))
    )
    (net (code "812") (name "ZZ.04.030") (class "Default")
      (node (ref "U$4") (pin "P$167") (pinfunction "F17_P$167") (pintype "bidirectional"))
    )
    (net (code "813") (name "ZZ.04.031") (class "Default")
      (node (ref "U$4") (pin "P$136") (pinfunction "E16_P$136") (pintype "bidirectional"))
    )
    (net (code "814") (name "ZZ.04.032") (class "Default")
      (node (ref "U$6") (pin "P$49") (pinfunction "B19_P$49") (pintype "bidirectional"))
    )
    (net (code "815") (name "ZZ.04.033") (class "Default")
      (node (ref "U$6") (pin "P$79") (pinfunction "C19_P$79") (pintype "bidirectional"))
    )
    (net (code "816") (name "ZZ.04.034") (class "Default")
      (node (ref "U$6") (pin "P$109") (pinfunction "D19_P$109") (pintype "bidirectional"))
    )
    (net (code "817") (name "ZZ.04.035") (class "Default")
      (node (ref "U$6") (pin "P$139") (pinfunction "E19_P$139") (pintype "bidirectional"))
    )
    (net (code "818") (name "ZZ.04.036") (class "Default")
      (node (ref "U$6") (pin "P$169") (pinfunction "F19_P$169") (pintype "bidirectional"))
    )
    (net (code "819") (name "ZZ.04.037") (class "Default")
      (node (ref "U$6") (pin "P$48") (pinfunction "B18_P$48") (pintype "bidirectional"))
    )
    (net (code "820") (name "ZZ.04.038") (class "Default")
      (node (ref "U$6") (pin "P$78") (pinfunction "C18_P$78") (pintype "bidirectional"))
    )
    (net (code "821") (name "ZZ.04.039") (class "Default")
      (node (ref "U$6") (pin "P$108") (pinfunction "D18_P$108") (pintype "bidirectional"))
    )
    (net (code "822") (name "ZZ.04.040") (class "Default")
      (node (ref "U$6") (pin "P$138") (pinfunction "E18_P$138") (pintype "bidirectional"))
    )
    (net (code "823") (name "ZZ.04.041") (class "Default")
      (node (ref "U$6") (pin "P$168") (pinfunction "F18_P$168") (pintype "bidirectional"))
    )
    (net (code "824") (name "ZZ.04.042") (class "Default")
      (node (ref "U$6") (pin "P$47") (pinfunction "B17_P$47") (pintype "bidirectional"))
    )
    (net (code "825") (name "ZZ.04.043") (class "Default")
      (node (ref "U$6") (pin "P$77") (pinfunction "C17_P$77") (pintype "bidirectional"))
    )
    (net (code "826") (name "ZZ.04.044") (class "Default")
      (node (ref "U$6") (pin "P$107") (pinfunction "D17_P$107") (pintype "bidirectional"))
    )
    (net (code "827") (name "ZZ.04.045") (class "Default")
      (node (ref "U$6") (pin "P$137") (pinfunction "E17_P$137") (pintype "bidirectional"))
    )
    (net (code "828") (name "ZZ.04.046") (class "Default")
      (node (ref "U$6") (pin "P$167") (pinfunction "F17_P$167") (pintype "bidirectional"))
    )
    (net (code "829") (name "ZZ.04.047") (class "Default")
      (node (ref "U$6") (pin "P$136") (pinfunction "E16_P$136") (pintype "bidirectional"))
    )
    (net (code "830") (name "ZZ.04.048") (class "Default")
      (node (ref "U$8") (pin "P$49") (pinfunction "B19_P$49") (pintype "bidirectional"))
    )
    (net (code "831") (name "ZZ.04.049") (class "Default")
      (node (ref "U$8") (pin "P$79") (pinfunction "C19_P$79") (pintype "bidirectional"))
    )
    (net (code "832") (name "ZZ.04.050") (class "Default")
      (node (ref "U$8") (pin "P$109") (pinfunction "D19_P$109") (pintype "bidirectional"))
    )
    (net (code "833") (name "ZZ.04.051") (class "Default")
      (node (ref "U$8") (pin "P$139") (pinfunction "E19_P$139") (pintype "bidirectional"))
    )
    (net (code "834") (name "ZZ.04.052") (class "Default")
      (node (ref "U$8") (pin "P$169") (pinfunction "F19_P$169") (pintype "bidirectional"))
    )
    (net (code "835") (name "ZZ.04.053") (class "Default")
      (node (ref "U$8") (pin "P$48") (pinfunction "B18_P$48") (pintype "bidirectional"))
    )
    (net (code "836") (name "ZZ.04.054") (class "Default")
      (node (ref "U$8") (pin "P$78") (pinfunction "C18_P$78") (pintype "bidirectional"))
    )
    (net (code "837") (name "ZZ.04.055") (class "Default")
      (node (ref "U$8") (pin "P$108") (pinfunction "D18_P$108") (pintype "bidirectional"))
    )
    (net (code "838") (name "ZZ.04.056") (class "Default")
      (node (ref "U$8") (pin "P$47") (pinfunction "B17_P$47") (pintype "bidirectional"))
    )
    (net (code "839") (name "ZZ.04.057") (class "Default")
      (node (ref "U$8") (pin "P$77") (pinfunction "C17_P$77") (pintype "bidirectional"))
    )
    (net (code "840") (name "ZZ.04.058") (class "Default")
      (node (ref "U$8") (pin "P$107") (pinfunction "D17_P$107") (pintype "bidirectional"))
    )
    (net (code "841") (name "ZZ.04.059") (class "Default")
      (node (ref "U$8") (pin "P$137") (pinfunction "E17_P$137") (pintype "bidirectional"))
    )
    (net (code "842") (name "ZZ.04.060") (class "Default")
      (node (ref "U$8") (pin "P$167") (pinfunction "F17_P$167") (pintype "bidirectional"))
    )
    (net (code "843") (name "ZZ.04.061") (class "Default")
      (node (ref "U$8") (pin "P$136") (pinfunction "E16_P$136") (pintype "bidirectional"))
    )
    (net (code "844") (name "ZZ.04.062") (class "Default")
      (node (ref "U$8") (pin "P$138") (pinfunction "E18_P$138") (pintype "bidirectional"))
    )
    (net (code "845") (name "ZZ.04.063") (class "Default")
      (node (ref "U$8") (pin "P$168") (pinfunction "F18_P$168") (pintype "bidirectional"))
    )
    (net (code "846") (name "ZZ.04.064") (class "Default")
      (node (ref "U$10") (pin "P$49") (pinfunction "B19_P$49") (pintype "bidirectional"))
    )
    (net (code "847") (name "ZZ.04.065") (class "Default")
      (node (ref "U$10") (pin "P$79") (pinfunction "C19_P$79") (pintype "bidirectional"))
    )
    (net (code "848") (name "ZZ.04.066") (class "Default")
      (node (ref "U$10") (pin "P$109") (pinfunction "D19_P$109") (pintype "bidirectional"))
    )
    (net (code "849") (name "ZZ.04.067") (class "Default")
      (node (ref "U$10") (pin "P$48") (pinfunction "B18_P$48") (pintype "bidirectional"))
    )
    (net (code "850") (name "ZZ.04.068") (class "Default")
      (node (ref "U$10") (pin "P$78") (pinfunction "C18_P$78") (pintype "bidirectional"))
    )
    (net (code "851") (name "ZZ.04.069") (class "Default")
      (node (ref "U$10") (pin "P$108") (pinfunction "D18_P$108") (pintype "bidirectional"))
    )
    (net (code "852") (name "ZZ.04.070") (class "Default")
      (node (ref "U$10") (pin "P$47") (pinfunction "B17_P$47") (pintype "bidirectional"))
    )
    (net (code "853") (name "ZZ.04.071") (class "Default")
      (node (ref "U$10") (pin "P$77") (pinfunction "C17_P$77") (pintype "bidirectional"))
    )
    (net (code "854") (name "ZZ.04.072") (class "Default")
      (node (ref "U$10") (pin "P$107") (pinfunction "D17_P$107") (pintype "bidirectional"))
    )
    (net (code "855") (name "ZZ.04.073") (class "Default")
      (node (ref "U$10") (pin "P$137") (pinfunction "E17_P$137") (pintype "bidirectional"))
    )
    (net (code "856") (name "ZZ.04.074") (class "Default")
      (node (ref "U$10") (pin "P$167") (pinfunction "F17_P$167") (pintype "bidirectional"))
    )
    (net (code "857") (name "ZZ.04.075") (class "Default")
      (node (ref "U$10") (pin "P$136") (pinfunction "E16_P$136") (pintype "bidirectional"))
    )
    (net (code "858") (name "ZZ.04.076") (class "Default")
      (node (ref "U$10") (pin "P$138") (pinfunction "E18_P$138") (pintype "bidirectional"))
    )
    (net (code "859") (name "ZZ.04.077") (class "Default")
      (node (ref "U$10") (pin "P$168") (pinfunction "F18_P$168") (pintype "bidirectional"))
    )
    (net (code "860") (name "ZZ.04.078") (class "Default")
      (node (ref "U$10") (pin "P$139") (pinfunction "E19_P$139") (pintype "bidirectional"))
    )
    (net (code "861") (name "ZZ.04.079") (class "Default")
      (node (ref "U$10") (pin "P$169") (pinfunction "F19_P$169") (pintype "bidirectional"))
    )
    (net (code "862") (name "ZZ.04.080") (class "Default")
      (node (ref "U$12") (pin "P$49") (pinfunction "B19_P$49") (pintype "bidirectional"))
    )
    (net (code "863") (name "ZZ.04.081") (class "Default")
      (node (ref "U$12") (pin "P$48") (pinfunction "B18_P$48") (pintype "bidirectional"))
    )
    (net (code "864") (name "ZZ.04.082") (class "Default")
      (node (ref "U$12") (pin "P$78") (pinfunction "C18_P$78") (pintype "bidirectional"))
    )
    (net (code "865") (name "ZZ.04.083") (class "Default")
      (node (ref "U$12") (pin "P$108") (pinfunction "D18_P$108") (pintype "bidirectional"))
    )
    (net (code "866") (name "ZZ.04.084") (class "Default")
      (node (ref "U$12") (pin "P$47") (pinfunction "B17_P$47") (pintype "bidirectional"))
    )
    (net (code "867") (name "ZZ.04.085") (class "Default")
      (node (ref "U$12") (pin "P$77") (pinfunction "C17_P$77") (pintype "bidirectional"))
    )
    (net (code "868") (name "ZZ.04.086") (class "Default")
      (node (ref "U$12") (pin "P$107") (pinfunction "D17_P$107") (pintype "bidirectional"))
    )
    (net (code "869") (name "ZZ.04.087") (class "Default")
      (node (ref "U$12") (pin "P$137") (pinfunction "E17_P$137") (pintype "bidirectional"))
    )
    (net (code "870") (name "ZZ.04.088") (class "Default")
      (node (ref "U$12") (pin "P$167") (pinfunction "F17_P$167") (pintype "bidirectional"))
    )
    (net (code "871") (name "ZZ.04.089") (class "Default")
      (node (ref "U$12") (pin "P$136") (pinfunction "E16_P$136") (pintype "bidirectional"))
    )
    (net (code "872") (name "ZZ.04.090") (class "Default")
      (node (ref "U$12") (pin "P$138") (pinfunction "E18_P$138") (pintype "bidirectional"))
    )
    (net (code "873") (name "ZZ.04.091") (class "Default")
      (node (ref "U$12") (pin "P$168") (pinfunction "F18_P$168") (pintype "bidirectional"))
    )
    (net (code "874") (name "ZZ.04.092") (class "Default")
      (node (ref "U$12") (pin "P$79") (pinfunction "C19_P$79") (pintype "bidirectional"))
    )
    (net (code "875") (name "ZZ.04.093") (class "Default")
      (node (ref "U$12") (pin "P$109") (pinfunction "D19_P$109") (pintype "bidirectional"))
    )
    (net (code "876") (name "ZZ.04.094") (class "Default")
      (node (ref "U$12") (pin "P$139") (pinfunction "E19_P$139") (pintype "bidirectional"))
    )
    (net (code "877") (name "ZZ.04.095") (class "Default")
      (node (ref "U$12") (pin "P$169") (pinfunction "F19_P$169") (pintype "bidirectional"))
    )
    (net (code "878") (name "ZZ.04.096") (class "Default")
      (node (ref "U$14") (pin "P$48") (pinfunction "B18_P$48") (pintype "bidirectional"))
    )
    (net (code "879") (name "ZZ.04.097") (class "Default")
      (node (ref "U$14") (pin "P$47") (pinfunction "B17_P$47") (pintype "bidirectional"))
    )
    (net (code "880") (name "ZZ.04.098") (class "Default")
      (node (ref "U$14") (pin "P$77") (pinfunction "C17_P$77") (pintype "bidirectional"))
    )
    (net (code "881") (name "ZZ.04.099") (class "Default")
      (node (ref "U$14") (pin "P$107") (pinfunction "D17_P$107") (pintype "bidirectional"))
    )
    (net (code "882") (name "ZZ.04.100") (class "Default")
      (node (ref "U$14") (pin "P$137") (pinfunction "E17_P$137") (pintype "bidirectional"))
    )
    (net (code "883") (name "ZZ.04.101") (class "Default")
      (node (ref "U$14") (pin "P$167") (pinfunction "F17_P$167") (pintype "bidirectional"))
    )
    (net (code "884") (name "ZZ.04.102") (class "Default")
      (node (ref "U$14") (pin "P$136") (pinfunction "E16_P$136") (pintype "bidirectional"))
    )
    (net (code "885") (name "ZZ.04.103") (class "Default")
      (node (ref "U$14") (pin "P$78") (pinfunction "C18_P$78") (pintype "bidirectional"))
    )
    (net (code "886") (name "ZZ.04.104") (class "Default")
      (node (ref "U$14") (pin "P$108") (pinfunction "D18_P$108") (pintype "bidirectional"))
    )
    (net (code "887") (name "ZZ.04.105") (class "Default")
      (node (ref "U$14") (pin "P$138") (pinfunction "E18_P$138") (pintype "bidirectional"))
    )
    (net (code "888") (name "ZZ.04.106") (class "Default")
      (node (ref "U$14") (pin "P$168") (pinfunction "F18_P$168") (pintype "bidirectional"))
    )
    (net (code "889") (name "ZZ.04.107") (class "Default")
      (node (ref "U$14") (pin "P$49") (pinfunction "B19_P$49") (pintype "bidirectional"))
    )
    (net (code "890") (name "ZZ.04.108") (class "Default")
      (node (ref "U$14") (pin "P$79") (pinfunction "C19_P$79") (pintype "bidirectional"))
    )
    (net (code "891") (name "ZZ.04.109") (class "Default")
      (node (ref "U$14") (pin "P$109") (pinfunction "D19_P$109") (pintype "bidirectional"))
    )
    (net (code "892") (name "ZZ.04.110") (class "Default")
      (node (ref "U$14") (pin "P$139") (pinfunction "E19_P$139") (pintype "bidirectional"))
    )
    (net (code "893") (name "ZZ.04.111") (class "Default")
      (node (ref "U$14") (pin "P$169") (pinfunction "F19_P$169") (pintype "bidirectional"))
    )
    (net (code "894") (name "ZZ.04.112") (class "Default")
      (node (ref "U$16") (pin "P$47") (pinfunction "B17_P$47") (pintype "bidirectional"))
    )
    (net (code "895") (name "ZZ.04.113") (class "Default")
      (node (ref "U$16") (pin "P$77") (pinfunction "C17_P$77") (pintype "bidirectional"))
    )
    (net (code "896") (name "ZZ.04.114") (class "Default")
      (node (ref "U$16") (pin "P$107") (pinfunction "D17_P$107") (pintype "bidirectional"))
    )
    (net (code "897") (name "ZZ.04.115") (class "Default")
      (node (ref "U$16") (pin "P$137") (pinfunction "E17_P$137") (pintype "bidirectional"))
    )
    (net (code "898") (name "ZZ.04.116") (class "Default")
      (node (ref "U$16") (pin "P$167") (pinfunction "F17_P$167") (pintype "bidirectional"))
    )
    (net (code "899") (name "ZZ.04.117") (class "Default")
      (node (ref "U$16") (pin "P$136") (pinfunction "E16_P$136") (pintype "bidirectional"))
    )
    (net (code "900") (name "ZZ.04.118") (class "Default")
      (node (ref "U$16") (pin "P$48") (pinfunction "B18_P$48") (pintype "bidirectional"))
    )
    (net (code "901") (name "ZZ.04.119") (class "Default")
      (node (ref "U$16") (pin "P$78") (pinfunction "C18_P$78") (pintype "bidirectional"))
    )
    (net (code "902") (name "ZZ.04.120") (class "Default")
      (node (ref "U$16") (pin "P$108") (pinfunction "D18_P$108") (pintype "bidirectional"))
    )
    (net (code "903") (name "ZZ.04.121") (class "Default")
      (node (ref "U$16") (pin "P$138") (pinfunction "E18_P$138") (pintype "bidirectional"))
    )
    (net (code "904") (name "ZZ.04.122") (class "Default")
      (node (ref "U$16") (pin "P$168") (pinfunction "F18_P$168") (pintype "bidirectional"))
    )
    (net (code "905") (name "ZZ.04.123") (class "Default")
      (node (ref "U$16") (pin "P$49") (pinfunction "B19_P$49") (pintype "bidirectional"))
    )
    (net (code "906") (name "ZZ.04.124") (class "Default")
      (node (ref "U$16") (pin "P$79") (pinfunction "C19_P$79") (pintype "bidirectional"))
    )
    (net (code "907") (name "ZZ.04.125") (class "Default")
      (node (ref "U$16") (pin "P$109") (pinfunction "D19_P$109") (pintype "bidirectional"))
    )
    (net (code "908") (name "ZZ.04.126") (class "Default")
      (node (ref "U$16") (pin "P$139") (pinfunction "E19_P$139") (pintype "bidirectional"))
    )
    (net (code "909") (name "ZZ.04.127") (class "Default")
      (node (ref "U$16") (pin "P$169") (pinfunction "F19_P$169") (pintype "bidirectional"))
    )
    (net (code "910") (name "ZZ.04.128") (class "Default")
      (node (ref "U$18") (pin "P$47") (pinfunction "B17_P$47") (pintype "bidirectional"))
    )
    (net (code "911") (name "ZZ.04.129") (class "Default")
      (node (ref "U$18") (pin "P$77") (pinfunction "C17_P$77") (pintype "bidirectional"))
    )
    (net (code "912") (name "ZZ.04.130") (class "Default")
      (node (ref "U$18") (pin "P$107") (pinfunction "D17_P$107") (pintype "bidirectional"))
    )
    (net (code "913") (name "ZZ.04.131") (class "Default")
      (node (ref "U$18") (pin "P$137") (pinfunction "E17_P$137") (pintype "bidirectional"))
    )
    (net (code "914") (name "ZZ.04.132") (class "Default")
      (node (ref "U$18") (pin "P$167") (pinfunction "F17_P$167") (pintype "bidirectional"))
    )
    (net (code "915") (name "ZZ.04.133") (class "Default")
      (node (ref "U$18") (pin "P$136") (pinfunction "E16_P$136") (pintype "bidirectional"))
    )
    (net (code "916") (name "ZZ.04.134") (class "Default")
      (node (ref "U$18") (pin "P$48") (pinfunction "B18_P$48") (pintype "bidirectional"))
    )
    (net (code "917") (name "ZZ.04.135") (class "Default")
      (node (ref "U$18") (pin "P$78") (pinfunction "C18_P$78") (pintype "bidirectional"))
    )
    (net (code "918") (name "ZZ.04.136") (class "Default")
      (node (ref "U$18") (pin "P$108") (pinfunction "D18_P$108") (pintype "bidirectional"))
    )
    (net (code "919") (name "ZZ.04.137") (class "Default")
      (node (ref "U$18") (pin "P$138") (pinfunction "E18_P$138") (pintype "bidirectional"))
    )
    (net (code "920") (name "ZZ.04.138") (class "Default")
      (node (ref "U$18") (pin "P$168") (pinfunction "F18_P$168") (pintype "bidirectional"))
    )
    (net (code "921") (name "ZZ.04.139") (class "Default")
      (node (ref "U$18") (pin "P$49") (pinfunction "B19_P$49") (pintype "bidirectional"))
    )
    (net (code "922") (name "ZZ.04.140") (class "Default")
      (node (ref "U$18") (pin "P$79") (pinfunction "C19_P$79") (pintype "bidirectional"))
    )
    (net (code "923") (name "ZZ.04.141") (class "Default")
      (node (ref "U$18") (pin "P$109") (pinfunction "D19_P$109") (pintype "bidirectional"))
    )
    (net (code "924") (name "ZZ.04.142") (class "Default")
      (node (ref "U$18") (pin "P$139") (pinfunction "E19_P$139") (pintype "bidirectional"))
    )
    (net (code "925") (name "ZZ.04.143") (class "Default")
      (node (ref "U$18") (pin "P$169") (pinfunction "F19_P$169") (pintype "bidirectional"))
    )
    (net (code "926") (name "ZZ.04.144") (class "Default")
      (node (ref "U$20") (pin "P$47") (pinfunction "B17_P$47") (pintype "bidirectional"))
    )
    (net (code "927") (name "ZZ.04.145") (class "Default")
      (node (ref "U$20") (pin "P$77") (pinfunction "C17_P$77") (pintype "bidirectional"))
    )
    (net (code "928") (name "ZZ.04.146") (class "Default")
      (node (ref "U$20") (pin "P$107") (pinfunction "D17_P$107") (pintype "bidirectional"))
    )
    (net (code "929") (name "ZZ.04.147") (class "Default")
      (node (ref "U$20") (pin "P$137") (pinfunction "E17_P$137") (pintype "bidirectional"))
    )
    (net (code "930") (name "ZZ.04.148") (class "Default")
      (node (ref "U$20") (pin "P$167") (pinfunction "F17_P$167") (pintype "bidirectional"))
    )
    (net (code "931") (name "ZZ.04.149") (class "Default")
      (node (ref "U$20") (pin "P$136") (pinfunction "E16_P$136") (pintype "bidirectional"))
    )
    (net (code "932") (name "ZZ.04.150") (class "Default")
      (node (ref "U$20") (pin "P$48") (pinfunction "B18_P$48") (pintype "bidirectional"))
    )
    (net (code "933") (name "ZZ.04.151") (class "Default")
      (node (ref "U$20") (pin "P$78") (pinfunction "C18_P$78") (pintype "bidirectional"))
    )
    (net (code "934") (name "ZZ.04.152") (class "Default")
      (node (ref "U$20") (pin "P$108") (pinfunction "D18_P$108") (pintype "bidirectional"))
    )
    (net (code "935") (name "ZZ.04.153") (class "Default")
      (node (ref "U$20") (pin "P$138") (pinfunction "E18_P$138") (pintype "bidirectional"))
    )
    (net (code "936") (name "ZZ.04.154") (class "Default")
      (node (ref "U$20") (pin "P$168") (pinfunction "F18_P$168") (pintype "bidirectional"))
    )
    (net (code "937") (name "ZZ.04.155") (class "Default")
      (node (ref "U$20") (pin "P$49") (pinfunction "B19_P$49") (pintype "bidirectional"))
    )
    (net (code "938") (name "ZZ.04.156") (class "Default")
      (node (ref "U$20") (pin "P$79") (pinfunction "C19_P$79") (pintype "bidirectional"))
    )
    (net (code "939") (name "ZZ.04.157") (class "Default")
      (node (ref "U$20") (pin "P$109") (pinfunction "D19_P$109") (pintype "bidirectional"))
    )
    (net (code "940") (name "ZZ.04.158") (class "Default")
      (node (ref "U$20") (pin "P$139") (pinfunction "E19_P$139") (pintype "bidirectional"))
    )
    (net (code "941") (name "ZZ.04.159") (class "Default")
      (node (ref "U$20") (pin "P$169") (pinfunction "F19_P$169") (pintype "bidirectional"))
    )
    (net (code "942") (name "ZZ.04.160") (class "Default")
      (node (ref "U$22") (pin "P$47") (pinfunction "B17_P$47") (pintype "bidirectional"))
    )
    (net (code "943") (name "ZZ.04.161") (class "Default")
      (node (ref "U$22") (pin "P$77") (pinfunction "C17_P$77") (pintype "bidirectional"))
    )
    (net (code "944") (name "ZZ.04.162") (class "Default")
      (node (ref "U$22") (pin "P$107") (pinfunction "D17_P$107") (pintype "bidirectional"))
    )
    (net (code "945") (name "ZZ.04.163") (class "Default")
      (node (ref "U$22") (pin "P$137") (pinfunction "E17_P$137") (pintype "bidirectional"))
    )
    (net (code "946") (name "ZZ.04.164") (class "Default")
      (node (ref "U$22") (pin "P$167") (pinfunction "F17_P$167") (pintype "bidirectional"))
    )
    (net (code "947") (name "ZZ.04.165") (class "Default")
      (node (ref "U$22") (pin "P$136") (pinfunction "E16_P$136") (pintype "bidirectional"))
    )
    (net (code "948") (name "ZZ.04.166") (class "Default")
      (node (ref "U$22") (pin "P$48") (pinfunction "B18_P$48") (pintype "bidirectional"))
    )
    (net (code "949") (name "ZZ.04.167") (class "Default")
      (node (ref "U$22") (pin "P$78") (pinfunction "C18_P$78") (pintype "bidirectional"))
    )
    (net (code "950") (name "ZZ.04.168") (class "Default")
      (node (ref "U$22") (pin "P$108") (pinfunction "D18_P$108") (pintype "bidirectional"))
    )
    (net (code "951") (name "ZZ.04.169") (class "Default")
      (node (ref "U$22") (pin "P$138") (pinfunction "E18_P$138") (pintype "bidirectional"))
    )
    (net (code "952") (name "ZZ.04.170") (class "Default")
      (node (ref "U$22") (pin "P$168") (pinfunction "F18_P$168") (pintype "bidirectional"))
    )
    (net (code "953") (name "ZZ.04.171") (class "Default")
      (node (ref "U$22") (pin "P$49") (pinfunction "B19_P$49") (pintype "bidirectional"))
    )
    (net (code "954") (name "ZZ.04.172") (class "Default")
      (node (ref "U$22") (pin "P$79") (pinfunction "C19_P$79") (pintype "bidirectional"))
    )
    (net (code "955") (name "ZZ.04.173") (class "Default")
      (node (ref "U$22") (pin "P$109") (pinfunction "D19_P$109") (pintype "bidirectional"))
    )
    (net (code "956") (name "ZZ.04.174") (class "Default")
      (node (ref "U$22") (pin "P$139") (pinfunction "E19_P$139") (pintype "bidirectional"))
    )
    (net (code "957") (name "ZZ.04.175") (class "Default")
      (node (ref "U$22") (pin "P$169") (pinfunction "F19_P$169") (pintype "bidirectional"))
    )
    (net (code "958") (name "ZZ.04.176") (class "Default")
      (node (ref "U$24") (pin "P$47") (pinfunction "B17_P$47") (pintype "bidirectional"))
    )
    (net (code "959") (name "ZZ.04.177") (class "Default")
      (node (ref "U$24") (pin "P$77") (pinfunction "C17_P$77") (pintype "bidirectional"))
    )
    (net (code "960") (name "ZZ.04.178") (class "Default")
      (node (ref "U$24") (pin "P$107") (pinfunction "D17_P$107") (pintype "bidirectional"))
    )
    (net (code "961") (name "ZZ.04.179") (class "Default")
      (node (ref "U$24") (pin "P$137") (pinfunction "E17_P$137") (pintype "bidirectional"))
    )
    (net (code "962") (name "ZZ.04.180") (class "Default")
      (node (ref "U$24") (pin "P$167") (pinfunction "F17_P$167") (pintype "bidirectional"))
    )
    (net (code "963") (name "ZZ.04.181") (class "Default")
      (node (ref "U$24") (pin "P$136") (pinfunction "E16_P$136") (pintype "bidirectional"))
    )
    (net (code "964") (name "ZZ.04.182") (class "Default")
      (node (ref "U$24") (pin "P$48") (pinfunction "B18_P$48") (pintype "bidirectional"))
    )
    (net (code "965") (name "ZZ.04.183") (class "Default")
      (node (ref "U$24") (pin "P$78") (pinfunction "C18_P$78") (pintype "bidirectional"))
    )
    (net (code "966") (name "ZZ.04.184") (class "Default")
      (node (ref "U$24") (pin "P$108") (pinfunction "D18_P$108") (pintype "bidirectional"))
    )
    (net (code "967") (name "ZZ.04.185") (class "Default")
      (node (ref "U$24") (pin "P$138") (pinfunction "E18_P$138") (pintype "bidirectional"))
    )
    (net (code "968") (name "ZZ.04.186") (class "Default")
      (node (ref "U$24") (pin "P$168") (pinfunction "F18_P$168") (pintype "bidirectional"))
    )
    (net (code "969") (name "ZZ.04.187") (class "Default")
      (node (ref "U$24") (pin "P$49") (pinfunction "B19_P$49") (pintype "bidirectional"))
    )
    (net (code "970") (name "ZZ.04.188") (class "Default")
      (node (ref "U$24") (pin "P$79") (pinfunction "C19_P$79") (pintype "bidirectional"))
    )
    (net (code "971") (name "ZZ.04.189") (class "Default")
      (node (ref "U$24") (pin "P$109") (pinfunction "D19_P$109") (pintype "bidirectional"))
    )
    (net (code "972") (name "ZZ.04.190") (class "Default")
      (node (ref "U$24") (pin "P$139") (pinfunction "E19_P$139") (pintype "bidirectional"))
    )
    (net (code "973") (name "ZZ.04.191") (class "Default")
      (node (ref "U$24") (pin "P$169") (pinfunction "F19_P$169") (pintype "bidirectional"))
    )
    (net (code "974") (name "ZZ.05.000") (class "Default")
      (node (ref "U$2") (pin "P$50") (pinfunction "B20_P$50") (pintype "bidirectional"))
    )
    (net (code "975") (name "ZZ.05.001") (class "Default")
      (node (ref "U$2") (pin "P$80") (pinfunction "C20_P$80") (pintype "bidirectional"))
    )
    (net (code "976") (name "ZZ.05.002") (class "Default")
      (node (ref "U$2") (pin "P$110") (pinfunction "D20_P$110") (pintype "bidirectional"))
    )
    (net (code "977") (name "ZZ.05.003") (class "Default")
      (node (ref "U$2") (pin "P$140") (pinfunction "E20_P$140") (pintype "bidirectional"))
    )
    (net (code "978") (name "ZZ.05.004") (class "Default")
      (node (ref "U$2") (pin "P$170") (pinfunction "F20_P$170") (pintype "bidirectional"))
    )
    (net (code "979") (name "ZZ.05.005") (class "Default")
      (node (ref "U$2") (pin "P$166") (pinfunction "F16_P$166") (pintype "bidirectional"))
    )
    (net (code "980") (name "ZZ.05.006") (class "Default")
      (node (ref "U$2") (pin "P$51") (pinfunction "B21_P$51") (pintype "bidirectional"))
    )
    (net (code "981") (name "ZZ.05.007") (class "Default")
      (node (ref "U$2") (pin "P$81") (pinfunction "C21_P$81") (pintype "bidirectional"))
    )
    (net (code "982") (name "ZZ.05.008") (class "Default")
      (node (ref "U$2") (pin "P$111") (pinfunction "D21_P$111") (pintype "bidirectional"))
    )
    (net (code "983") (name "ZZ.05.009") (class "Default")
      (node (ref "U$2") (pin "P$141") (pinfunction "E21_P$141") (pintype "bidirectional"))
    )
    (net (code "984") (name "ZZ.05.010") (class "Default")
      (node (ref "U$2") (pin "P$171") (pinfunction "F21_P$171") (pintype "bidirectional"))
    )
    (net (code "985") (name "ZZ.05.011") (class "Default")
      (node (ref "U$2") (pin "P$52") (pinfunction "B22_P$52") (pintype "bidirectional"))
    )
    (net (code "986") (name "ZZ.05.012") (class "Default")
      (node (ref "U$2") (pin "P$82") (pinfunction "C22_P$82") (pintype "bidirectional"))
    )
    (net (code "987") (name "ZZ.05.013") (class "Default")
      (node (ref "U$2") (pin "P$112") (pinfunction "D22_P$112") (pintype "bidirectional"))
    )
    (net (code "988") (name "ZZ.05.014") (class "Default")
      (node (ref "U$2") (pin "P$142") (pinfunction "E22_P$142") (pintype "bidirectional"))
    )
    (net (code "989") (name "ZZ.05.015") (class "Default")
      (node (ref "U$2") (pin "P$172") (pinfunction "F22_P$172") (pintype "bidirectional"))
    )
    (net (code "990") (name "ZZ.05.016") (class "Default")
      (node (ref "U$4") (pin "P$50") (pinfunction "B20_P$50") (pintype "bidirectional"))
    )
    (net (code "991") (name "ZZ.05.017") (class "Default")
      (node (ref "U$4") (pin "P$80") (pinfunction "C20_P$80") (pintype "bidirectional"))
    )
    (net (code "992") (name "ZZ.05.018") (class "Default")
      (node (ref "U$4") (pin "P$110") (pinfunction "D20_P$110") (pintype "bidirectional"))
    )
    (net (code "993") (name "ZZ.05.019") (class "Default")
      (node (ref "U$4") (pin "P$140") (pinfunction "E20_P$140") (pintype "bidirectional"))
    )
    (net (code "994") (name "ZZ.05.020") (class "Default")
      (node (ref "U$4") (pin "P$170") (pinfunction "F20_P$170") (pintype "bidirectional"))
    )
    (net (code "995") (name "ZZ.05.021") (class "Default")
      (node (ref "U$4") (pin "P$166") (pinfunction "F16_P$166") (pintype "bidirectional"))
    )
    (net (code "996") (name "ZZ.05.022") (class "Default")
      (node (ref "U$4") (pin "P$51") (pinfunction "B21_P$51") (pintype "bidirectional"))
    )
    (net (code "997") (name "ZZ.05.023") (class "Default")
      (node (ref "U$4") (pin "P$81") (pinfunction "C21_P$81") (pintype "bidirectional"))
    )
    (net (code "998") (name "ZZ.05.024") (class "Default")
      (node (ref "U$4") (pin "P$111") (pinfunction "D21_P$111") (pintype "bidirectional"))
    )
    (net (code "999") (name "ZZ.05.025") (class "Default")
      (node (ref "U$4") (pin "P$141") (pinfunction "E21_P$141") (pintype "bidirectional"))
    )
    (net (code "1000") (name "ZZ.05.026") (class "Default")
      (node (ref "U$4") (pin "P$171") (pinfunction "F21_P$171") (pintype "bidirectional"))
    )
    (net (code "1001") (name "ZZ.05.027") (class "Default")
      (node (ref "U$4") (pin "P$52") (pinfunction "B22_P$52") (pintype "bidirectional"))
    )
    (net (code "1002") (name "ZZ.05.028") (class "Default")
      (node (ref "U$4") (pin "P$82") (pinfunction "C22_P$82") (pintype "bidirectional"))
    )
    (net (code "1003") (name "ZZ.05.029") (class "Default")
      (node (ref "U$4") (pin "P$112") (pinfunction "D22_P$112") (pintype "bidirectional"))
    )
    (net (code "1004") (name "ZZ.05.030") (class "Default")
      (node (ref "U$4") (pin "P$142") (pinfunction "E22_P$142") (pintype "bidirectional"))
    )
    (net (code "1005") (name "ZZ.05.031") (class "Default")
      (node (ref "U$4") (pin "P$172") (pinfunction "F22_P$172") (pintype "bidirectional"))
    )
    (net (code "1006") (name "ZZ.05.032") (class "Default")
      (node (ref "U$6") (pin "P$50") (pinfunction "B20_P$50") (pintype "bidirectional"))
    )
    (net (code "1007") (name "ZZ.05.033") (class "Default")
      (node (ref "U$6") (pin "P$80") (pinfunction "C20_P$80") (pintype "bidirectional"))
    )
    (net (code "1008") (name "ZZ.05.034") (class "Default")
      (node (ref "U$6") (pin "P$110") (pinfunction "D20_P$110") (pintype "bidirectional"))
    )
    (net (code "1009") (name "ZZ.05.035") (class "Default")
      (node (ref "U$6") (pin "P$140") (pinfunction "E20_P$140") (pintype "bidirectional"))
    )
    (net (code "1010") (name "ZZ.05.036") (class "Default")
      (node (ref "U$6") (pin "P$170") (pinfunction "F20_P$170") (pintype "bidirectional"))
    )
    (net (code "1011") (name "ZZ.05.037") (class "Default")
      (node (ref "U$6") (pin "P$166") (pinfunction "F16_P$166") (pintype "bidirectional"))
    )
    (net (code "1012") (name "ZZ.05.038") (class "Default")
      (node (ref "U$6") (pin "P$51") (pinfunction "B21_P$51") (pintype "bidirectional"))
    )
    (net (code "1013") (name "ZZ.05.039") (class "Default")
      (node (ref "U$6") (pin "P$81") (pinfunction "C21_P$81") (pintype "bidirectional"))
    )
    (net (code "1014") (name "ZZ.05.040") (class "Default")
      (node (ref "U$6") (pin "P$111") (pinfunction "D21_P$111") (pintype "bidirectional"))
    )
    (net (code "1015") (name "ZZ.05.041") (class "Default")
      (node (ref "U$6") (pin "P$141") (pinfunction "E21_P$141") (pintype "bidirectional"))
    )
    (net (code "1016") (name "ZZ.05.042") (class "Default")
      (node (ref "U$6") (pin "P$171") (pinfunction "F21_P$171") (pintype "bidirectional"))
    )
    (net (code "1017") (name "ZZ.05.043") (class "Default")
      (node (ref "U$6") (pin "P$52") (pinfunction "B22_P$52") (pintype "bidirectional"))
    )
    (net (code "1018") (name "ZZ.05.044") (class "Default")
      (node (ref "U$6") (pin "P$82") (pinfunction "C22_P$82") (pintype "bidirectional"))
    )
    (net (code "1019") (name "ZZ.05.045") (class "Default")
      (node (ref "U$6") (pin "P$112") (pinfunction "D22_P$112") (pintype "bidirectional"))
    )
    (net (code "1020") (name "ZZ.05.046") (class "Default")
      (node (ref "U$6") (pin "P$142") (pinfunction "E22_P$142") (pintype "bidirectional"))
    )
    (net (code "1021") (name "ZZ.05.047") (class "Default")
      (node (ref "U$6") (pin "P$172") (pinfunction "F22_P$172") (pintype "bidirectional"))
    )
    (net (code "1022") (name "ZZ.05.048") (class "Default")
      (node (ref "U$8") (pin "P$50") (pinfunction "B20_P$50") (pintype "bidirectional"))
    )
    (net (code "1023") (name "ZZ.05.049") (class "Default")
      (node (ref "U$8") (pin "P$80") (pinfunction "C20_P$80") (pintype "bidirectional"))
    )
    (net (code "1024") (name "ZZ.05.050") (class "Default")
      (node (ref "U$8") (pin "P$110") (pinfunction "D20_P$110") (pintype "bidirectional"))
    )
    (net (code "1025") (name "ZZ.05.051") (class "Default")
      (node (ref "U$8") (pin "P$140") (pinfunction "E20_P$140") (pintype "bidirectional"))
    )
    (net (code "1026") (name "ZZ.05.052") (class "Default")
      (node (ref "U$8") (pin "P$170") (pinfunction "F20_P$170") (pintype "bidirectional"))
    )
    (net (code "1027") (name "ZZ.05.053") (class "Default")
      (node (ref "U$8") (pin "P$166") (pinfunction "F16_P$166") (pintype "bidirectional"))
    )
    (net (code "1028") (name "ZZ.05.054") (class "Default")
      (node (ref "U$8") (pin "P$51") (pinfunction "B21_P$51") (pintype "bidirectional"))
    )
    (net (code "1029") (name "ZZ.05.055") (class "Default")
      (node (ref "U$8") (pin "P$81") (pinfunction "C21_P$81") (pintype "bidirectional"))
    )
    (net (code "1030") (name "ZZ.05.056") (class "Default")
      (node (ref "U$8") (pin "P$52") (pinfunction "B22_P$52") (pintype "bidirectional"))
    )
    (net (code "1031") (name "ZZ.05.057") (class "Default")
      (node (ref "U$8") (pin "P$82") (pinfunction "C22_P$82") (pintype "bidirectional"))
    )
    (net (code "1032") (name "ZZ.05.058") (class "Default")
      (node (ref "U$8") (pin "P$112") (pinfunction "D22_P$112") (pintype "bidirectional"))
    )
    (net (code "1033") (name "ZZ.05.059") (class "Default")
      (node (ref "U$8") (pin "P$142") (pinfunction "E22_P$142") (pintype "bidirectional"))
    )
    (net (code "1034") (name "ZZ.05.060") (class "Default")
      (node (ref "U$8") (pin "P$172") (pinfunction "F22_P$172") (pintype "bidirectional"))
    )
    (net (code "1035") (name "ZZ.05.061") (class "Default")
      (node (ref "U$8") (pin "P$111") (pinfunction "D21_P$111") (pintype "bidirectional"))
    )
    (net (code "1036") (name "ZZ.05.062") (class "Default")
      (node (ref "U$8") (pin "P$141") (pinfunction "E21_P$141") (pintype "bidirectional"))
    )
    (net (code "1037") (name "ZZ.05.063") (class "Default")
      (node (ref "U$8") (pin "P$171") (pinfunction "F21_P$171") (pintype "bidirectional"))
    )
    (net (code "1038") (name "ZZ.05.064") (class "Default")
      (node (ref "U$10") (pin "P$50") (pinfunction "B20_P$50") (pintype "bidirectional"))
    )
    (net (code "1039") (name "ZZ.05.065") (class "Default")
      (node (ref "U$10") (pin "P$80") (pinfunction "C20_P$80") (pintype "bidirectional"))
    )
    (net (code "1040") (name "ZZ.05.066") (class "Default")
      (node (ref "U$10") (pin "P$110") (pinfunction "D20_P$110") (pintype "bidirectional"))
    )
    (net (code "1041") (name "ZZ.05.067") (class "Default")
      (node (ref "U$10") (pin "P$140") (pinfunction "E20_P$140") (pintype "bidirectional"))
    )
    (net (code "1042") (name "ZZ.05.068") (class "Default")
      (node (ref "U$10") (pin "P$51") (pinfunction "B21_P$51") (pintype "bidirectional"))
    )
    (net (code "1043") (name "ZZ.05.069") (class "Default")
      (node (ref "U$10") (pin "P$81") (pinfunction "C21_P$81") (pintype "bidirectional"))
    )
    (net (code "1044") (name "ZZ.05.070") (class "Default")
      (node (ref "U$10") (pin "P$52") (pinfunction "B22_P$52") (pintype "bidirectional"))
    )
    (net (code "1045") (name "ZZ.05.071") (class "Default")
      (node (ref "U$10") (pin "P$82") (pinfunction "C22_P$82") (pintype "bidirectional"))
    )
    (net (code "1046") (name "ZZ.05.072") (class "Default")
      (node (ref "U$10") (pin "P$112") (pinfunction "D22_P$112") (pintype "bidirectional"))
    )
    (net (code "1047") (name "ZZ.05.073") (class "Default")
      (node (ref "U$10") (pin "P$142") (pinfunction "E22_P$142") (pintype "bidirectional"))
    )
    (net (code "1048") (name "ZZ.05.074") (class "Default")
      (node (ref "U$10") (pin "P$172") (pinfunction "F22_P$172") (pintype "bidirectional"))
    )
    (net (code "1049") (name "ZZ.05.075") (class "Default")
      (node (ref "U$10") (pin "P$111") (pinfunction "D21_P$111") (pintype "bidirectional"))
    )
    (net (code "1050") (name "ZZ.05.076") (class "Default")
      (node (ref "U$10") (pin "P$141") (pinfunction "E21_P$141") (pintype "bidirectional"))
    )
    (net (code "1051") (name "ZZ.05.077") (class "Default")
      (node (ref "U$10") (pin "P$171") (pinfunction "F21_P$171") (pintype "bidirectional"))
    )
    (net (code "1052") (name "ZZ.05.078") (class "Default")
      (node (ref "U$10") (pin "P$170") (pinfunction "F20_P$170") (pintype "bidirectional"))
    )
    (net (code "1053") (name "ZZ.05.079") (class "Default")
      (node (ref "U$10") (pin "P$166") (pinfunction "F16_P$166") (pintype "bidirectional"))
    )
    (net (code "1054") (name "ZZ.05.080") (class "Default")
      (node (ref "U$12") (pin "P$50") (pinfunction "B20_P$50") (pintype "bidirectional"))
    )
    (net (code "1055") (name "ZZ.05.081") (class "Default")
      (node (ref "U$12") (pin "P$80") (pinfunction "C20_P$80") (pintype "bidirectional"))
    )
    (net (code "1056") (name "ZZ.05.082") (class "Default")
      (node (ref "U$12") (pin "P$51") (pinfunction "B21_P$51") (pintype "bidirectional"))
    )
    (net (code "1057") (name "ZZ.05.083") (class "Default")
      (node (ref "U$12") (pin "P$81") (pinfunction "C21_P$81") (pintype "bidirectional"))
    )
    (net (code "1058") (name "ZZ.05.084") (class "Default")
      (node (ref "U$12") (pin "P$52") (pinfunction "B22_P$52") (pintype "bidirectional"))
    )
    (net (code "1059") (name "ZZ.05.085") (class "Default")
      (node (ref "U$12") (pin "P$82") (pinfunction "C22_P$82") (pintype "bidirectional"))
    )
    (net (code "1060") (name "ZZ.05.086") (class "Default")
      (node (ref "U$12") (pin "P$112") (pinfunction "D22_P$112") (pintype "bidirectional"))
    )
    (net (code "1061") (name "ZZ.05.087") (class "Default")
      (node (ref "U$12") (pin "P$142") (pinfunction "E22_P$142") (pintype "bidirectional"))
    )
    (net (code "1062") (name "ZZ.05.088") (class "Default")
      (node (ref "U$12") (pin "P$172") (pinfunction "F22_P$172") (pintype "bidirectional"))
    )
    (net (code "1063") (name "ZZ.05.089") (class "Default")
      (node (ref "U$12") (pin "P$111") (pinfunction "D21_P$111") (pintype "bidirectional"))
    )
    (net (code "1064") (name "ZZ.05.090") (class "Default")
      (node (ref "U$12") (pin "P$141") (pinfunction "E21_P$141") (pintype "bidirectional"))
    )
    (net (code "1065") (name "ZZ.05.091") (class "Default")
      (node (ref "U$12") (pin "P$171") (pinfunction "F21_P$171") (pintype "bidirectional"))
    )
    (net (code "1066") (name "ZZ.05.092") (class "Default")
      (node (ref "U$12") (pin "P$110") (pinfunction "D20_P$110") (pintype "bidirectional"))
    )
    (net (code "1067") (name "ZZ.05.093") (class "Default")
      (node (ref "U$12") (pin "P$140") (pinfunction "E20_P$140") (pintype "bidirectional"))
    )
    (net (code "1068") (name "ZZ.05.094") (class "Default")
      (node (ref "U$12") (pin "P$170") (pinfunction "F20_P$170") (pintype "bidirectional"))
    )
    (net (code "1069") (name "ZZ.05.095") (class "Default")
      (node (ref "U$12") (pin "P$166") (pinfunction "F16_P$166") (pintype "bidirectional"))
    )
    (net (code "1070") (name "ZZ.05.096") (class "Default")
      (node (ref "U$14") (pin "P$51") (pinfunction "B21_P$51") (pintype "bidirectional"))
    )
    (net (code "1071") (name "ZZ.05.097") (class "Default")
      (node (ref "U$14") (pin "P$52") (pinfunction "B22_P$52") (pintype "bidirectional"))
    )
    (net (code "1072") (name "ZZ.05.098") (class "Default")
      (node (ref "U$14") (pin "P$82") (pinfunction "C22_P$82") (pintype "bidirectional"))
    )
    (net (code "1073") (name "ZZ.05.099") (class "Default")
      (node (ref "U$14") (pin "P$112") (pinfunction "D22_P$112") (pintype "bidirectional"))
    )
    (net (code "1074") (name "ZZ.05.100") (class "Default")
      (node (ref "U$14") (pin "P$142") (pinfunction "E22_P$142") (pintype "bidirectional"))
    )
    (net (code "1075") (name "ZZ.05.101") (class "Default")
      (node (ref "U$14") (pin "P$172") (pinfunction "F22_P$172") (pintype "bidirectional"))
    )
    (net (code "1076") (name "ZZ.05.102") (class "Default")
      (node (ref "U$14") (pin "P$81") (pinfunction "C21_P$81") (pintype "bidirectional"))
    )
    (net (code "1077") (name "ZZ.05.103") (class "Default")
      (node (ref "U$14") (pin "P$111") (pinfunction "D21_P$111") (pintype "bidirectional"))
    )
    (net (code "1078") (name "ZZ.05.104") (class "Default")
      (node (ref "U$14") (pin "P$141") (pinfunction "E21_P$141") (pintype "bidirectional"))
    )
    (net (code "1079") (name "ZZ.05.105") (class "Default")
      (node (ref "U$14") (pin "P$171") (pinfunction "F21_P$171") (pintype "bidirectional"))
    )
    (net (code "1080") (name "ZZ.05.106") (class "Default")
      (node (ref "U$14") (pin "P$50") (pinfunction "B20_P$50") (pintype "bidirectional"))
    )
    (net (code "1081") (name "ZZ.05.107") (class "Default")
      (node (ref "U$14") (pin "P$80") (pinfunction "C20_P$80") (pintype "bidirectional"))
    )
    (net (code "1082") (name "ZZ.05.108") (class "Default")
      (node (ref "U$14") (pin "P$110") (pinfunction "D20_P$110") (pintype "bidirectional"))
    )
    (net (code "1083") (name "ZZ.05.109") (class "Default")
      (node (ref "U$14") (pin "P$140") (pinfunction "E20_P$140") (pintype "bidirectional"))
    )
    (net (code "1084") (name "ZZ.05.110") (class "Default")
      (node (ref "U$14") (pin "P$170") (pinfunction "F20_P$170") (pintype "bidirectional"))
    )
    (net (code "1085") (name "ZZ.05.111") (class "Default")
      (node (ref "U$14") (pin "P$166") (pinfunction "F16_P$166") (pintype "bidirectional"))
    )
    (net (code "1086") (name "ZZ.05.112") (class "Default")
      (node (ref "U$16") (pin "P$52") (pinfunction "B22_P$52") (pintype "bidirectional"))
    )
    (net (code "1087") (name "ZZ.05.113") (class "Default")
      (node (ref "U$16") (pin "P$82") (pinfunction "C22_P$82") (pintype "bidirectional"))
    )
    (net (code "1088") (name "ZZ.05.114") (class "Default")
      (node (ref "U$16") (pin "P$112") (pinfunction "D22_P$112") (pintype "bidirectional"))
    )
    (net (code "1089") (name "ZZ.05.115") (class "Default")
      (node (ref "U$16") (pin "P$142") (pinfunction "E22_P$142") (pintype "bidirectional"))
    )
    (net (code "1090") (name "ZZ.05.116") (class "Default")
      (node (ref "U$16") (pin "P$172") (pinfunction "F22_P$172") (pintype "bidirectional"))
    )
    (net (code "1091") (name "ZZ.05.117") (class "Default")
      (node (ref "U$16") (pin "P$51") (pinfunction "B21_P$51") (pintype "bidirectional"))
    )
    (net (code "1092") (name "ZZ.05.118") (class "Default")
      (node (ref "U$16") (pin "P$81") (pinfunction "C21_P$81") (pintype "bidirectional"))
    )
    (net (code "1093") (name "ZZ.05.119") (class "Default")
      (node (ref "U$16") (pin "P$111") (pinfunction "D21_P$111") (pintype "bidirectional"))
    )
    (net (code "1094") (name "ZZ.05.120") (class "Default")
      (node (ref "U$16") (pin "P$141") (pinfunction "E21_P$141") (pintype "bidirectional"))
    )
    (net (code "1095") (name "ZZ.05.121") (class "Default")
      (node (ref "U$16") (pin "P$171") (pinfunction "F21_P$171") (pintype "bidirectional"))
    )
    (net (code "1096") (name "ZZ.05.122") (class "Default")
      (node (ref "U$16") (pin "P$50") (pinfunction "B20_P$50") (pintype "bidirectional"))
    )
    (net (code "1097") (name "ZZ.05.123") (class "Default")
      (node (ref "U$16") (pin "P$80") (pinfunction "C20_P$80") (pintype "bidirectional"))
    )
    (net (code "1098") (name "ZZ.05.124") (class "Default")
      (node (ref "U$16") (pin "P$110") (pinfunction "D20_P$110") (pintype "bidirectional"))
    )
    (net (code "1099") (name "ZZ.05.125") (class "Default")
      (node (ref "U$16") (pin "P$140") (pinfunction "E20_P$140") (pintype "bidirectional"))
    )
    (net (code "1100") (name "ZZ.05.126") (class "Default")
      (node (ref "U$16") (pin "P$170") (pinfunction "F20_P$170") (pintype "bidirectional"))
    )
    (net (code "1101") (name "ZZ.05.127") (class "Default")
      (node (ref "U$16") (pin "P$166") (pinfunction "F16_P$166") (pintype "bidirectional"))
    )
    (net (code "1102") (name "ZZ.05.128") (class "Default")
      (node (ref "U$18") (pin "P$52") (pinfunction "B22_P$52") (pintype "bidirectional"))
    )
    (net (code "1103") (name "ZZ.05.129") (class "Default")
      (node (ref "U$18") (pin "P$82") (pinfunction "C22_P$82") (pintype "bidirectional"))
    )
    (net (code "1104") (name "ZZ.05.130") (class "Default")
      (node (ref "U$18") (pin "P$112") (pinfunction "D22_P$112") (pintype "bidirectional"))
    )
    (net (code "1105") (name "ZZ.05.131") (class "Default")
      (node (ref "U$18") (pin "P$142") (pinfunction "E22_P$142") (pintype "bidirectional"))
    )
    (net (code "1106") (name "ZZ.05.132") (class "Default")
      (node (ref "U$18") (pin "P$172") (pinfunction "F22_P$172") (pintype "bidirectional"))
    )
    (net (code "1107") (name "ZZ.05.133") (class "Default")
      (node (ref "U$18") (pin "P$51") (pinfunction "B21_P$51") (pintype "bidirectional"))
    )
    (net (code "1108") (name "ZZ.05.134") (class "Default")
      (node (ref "U$18") (pin "P$81") (pinfunction "C21_P$81") (pintype "bidirectional"))
    )
    (net (code "1109") (name "ZZ.05.135") (class "Default")
      (node (ref "U$18") (pin "P$111") (pinfunction "D21_P$111") (pintype "bidirectional"))
    )
    (net (code "1110") (name "ZZ.05.136") (class "Default")
      (node (ref "U$18") (pin "P$141") (pinfunction "E21_P$141") (pintype "bidirectional"))
    )
    (net (code "1111") (name "ZZ.05.137") (class "Default")
      (node (ref "U$18") (pin "P$171") (pinfunction "F21_P$171") (pintype "bidirectional"))
    )
    (net (code "1112") (name "ZZ.05.138") (class "Default")
      (node (ref "U$18") (pin "P$50") (pinfunction "B20_P$50") (pintype "bidirectional"))
    )
    (net (code "1113") (name "ZZ.05.139") (class "Default")
      (node (ref "U$18") (pin "P$80") (pinfunction "C20_P$80") (pintype "bidirectional"))
    )
    (net (code "1114") (name "ZZ.05.140") (class "Default")
      (node (ref "U$18") (pin "P$110") (pinfunction "D20_P$110") (pintype "bidirectional"))
    )
    (net (code "1115") (name "ZZ.05.141") (class "Default")
      (node (ref "U$18") (pin "P$140") (pinfunction "E20_P$140") (pintype "bidirectional"))
    )
    (net (code "1116") (name "ZZ.05.142") (class "Default")
      (node (ref "U$18") (pin "P$170") (pinfunction "F20_P$170") (pintype "bidirectional"))
    )
    (net (code "1117") (name "ZZ.05.143") (class "Default")
      (node (ref "U$18") (pin "P$166") (pinfunction "F16_P$166") (pintype "bidirectional"))
    )
    (net (code "1118") (name "ZZ.05.144") (class "Default")
      (node (ref "U$20") (pin "P$52") (pinfunction "B22_P$52") (pintype "bidirectional"))
    )
    (net (code "1119") (name "ZZ.05.145") (class "Default")
      (node (ref "U$20") (pin "P$82") (pinfunction "C22_P$82") (pintype "bidirectional"))
    )
    (net (code "1120") (name "ZZ.05.146") (class "Default")
      (node (ref "U$20") (pin "P$112") (pinfunction "D22_P$112") (pintype "bidirectional"))
    )
    (net (code "1121") (name "ZZ.05.147") (class "Default")
      (node (ref "U$20") (pin "P$142") (pinfunction "E22_P$142") (pintype "bidirectional"))
    )
    (net (code "1122") (name "ZZ.05.148") (class "Default")
      (node (ref "U$20") (pin "P$172") (pinfunction "F22_P$172") (pintype "bidirectional"))
    )
    (net (code "1123") (name "ZZ.05.149") (class "Default")
      (node (ref "U$20") (pin "P$51") (pinfunction "B21_P$51") (pintype "bidirectional"))
    )
    (net (code "1124") (name "ZZ.05.150") (class "Default")
      (node (ref "U$20") (pin "P$81") (pinfunction "C21_P$81") (pintype "bidirectional"))
    )
    (net (code "1125") (name "ZZ.05.151") (class "Default")
      (node (ref "U$20") (pin "P$111") (pinfunction "D21_P$111") (pintype "bidirectional"))
    )
    (net (code "1126") (name "ZZ.05.152") (class "Default")
      (node (ref "U$20") (pin "P$141") (pinfunction "E21_P$141") (pintype "bidirectional"))
    )
    (net (code "1127") (name "ZZ.05.153") (class "Default")
      (node (ref "U$20") (pin "P$171") (pinfunction "F21_P$171") (pintype "bidirectional"))
    )
    (net (code "1128") (name "ZZ.05.154") (class "Default")
      (node (ref "U$20") (pin "P$50") (pinfunction "B20_P$50") (pintype "bidirectional"))
    )
    (net (code "1129") (name "ZZ.05.155") (class "Default")
      (node (ref "U$20") (pin "P$80") (pinfunction "C20_P$80") (pintype "bidirectional"))
    )
    (net (code "1130") (name "ZZ.05.156") (class "Default")
      (node (ref "U$20") (pin "P$110") (pinfunction "D20_P$110") (pintype "bidirectional"))
    )
    (net (code "1131") (name "ZZ.05.157") (class "Default")
      (node (ref "U$20") (pin "P$140") (pinfunction "E20_P$140") (pintype "bidirectional"))
    )
    (net (code "1132") (name "ZZ.05.158") (class "Default")
      (node (ref "U$20") (pin "P$170") (pinfunction "F20_P$170") (pintype "bidirectional"))
    )
    (net (code "1133") (name "ZZ.05.159") (class "Default")
      (node (ref "U$20") (pin "P$166") (pinfunction "F16_P$166") (pintype "bidirectional"))
    )
    (net (code "1134") (name "ZZ.05.160") (class "Default")
      (node (ref "U$22") (pin "P$52") (pinfunction "B22_P$52") (pintype "bidirectional"))
    )
    (net (code "1135") (name "ZZ.05.161") (class "Default")
      (node (ref "U$22") (pin "P$82") (pinfunction "C22_P$82") (pintype "bidirectional"))
    )
    (net (code "1136") (name "ZZ.05.162") (class "Default")
      (node (ref "U$22") (pin "P$112") (pinfunction "D22_P$112") (pintype "bidirectional"))
    )
    (net (code "1137") (name "ZZ.05.163") (class "Default")
      (node (ref "U$22") (pin "P$142") (pinfunction "E22_P$142") (pintype "bidirectional"))
    )
    (net (code "1138") (name "ZZ.05.164") (class "Default")
      (node (ref "U$22") (pin "P$172") (pinfunction "F22_P$172") (pintype "bidirectional"))
    )
    (net (code "1139") (name "ZZ.05.165") (class "Default")
      (node (ref "U$22") (pin "P$51") (pinfunction "B21_P$51") (pintype "bidirectional"))
    )
    (net (code "1140") (name "ZZ.05.166") (class "Default")
      (node (ref "U$22") (pin "P$81") (pinfunction "C21_P$81") (pintype "bidirectional"))
    )
    (net (code "1141") (name "ZZ.05.167") (class "Default")
      (node (ref "U$22") (pin "P$111") (pinfunction "D21_P$111") (pintype "bidirectional"))
    )
    (net (code "1142") (name "ZZ.05.168") (class "Default")
      (node (ref "U$22") (pin "P$141") (pinfunction "E21_P$141") (pintype "bidirectional"))
    )
    (net (code "1143") (name "ZZ.05.169") (class "Default")
      (node (ref "U$22") (pin "P$171") (pinfunction "F21_P$171") (pintype "bidirectional"))
    )
    (net (code "1144") (name "ZZ.05.170") (class "Default")
      (node (ref "U$22") (pin "P$50") (pinfunction "B20_P$50") (pintype "bidirectional"))
    )
    (net (code "1145") (name "ZZ.05.171") (class "Default")
      (node (ref "U$22") (pin "P$80") (pinfunction "C20_P$80") (pintype "bidirectional"))
    )
    (net (code "1146") (name "ZZ.05.172") (class "Default")
      (node (ref "U$22") (pin "P$110") (pinfunction "D20_P$110") (pintype "bidirectional"))
    )
    (net (code "1147") (name "ZZ.05.173") (class "Default")
      (node (ref "U$22") (pin "P$140") (pinfunction "E20_P$140") (pintype "bidirectional"))
    )
    (net (code "1148") (name "ZZ.05.174") (class "Default")
      (node (ref "U$22") (pin "P$170") (pinfunction "F20_P$170") (pintype "bidirectional"))
    )
    (net (code "1149") (name "ZZ.05.175") (class "Default")
      (node (ref "U$22") (pin "P$166") (pinfunction "F16_P$166") (pintype "bidirectional"))
    )
    (net (code "1150") (name "ZZ.05.176") (class "Default")
      (node (ref "U$24") (pin "P$52") (pinfunction "B22_P$52") (pintype "bidirectional"))
    )
    (net (code "1151") (name "ZZ.05.177") (class "Default")
      (node (ref "U$24") (pin "P$82") (pinfunction "C22_P$82") (pintype "bidirectional"))
    )
    (net (code "1152") (name "ZZ.05.178") (class "Default")
      (node (ref "U$24") (pin "P$112") (pinfunction "D22_P$112") (pintype "bidirectional"))
    )
    (net (code "1153") (name "ZZ.05.179") (class "Default")
      (node (ref "U$24") (pin "P$142") (pinfunction "E22_P$142") (pintype "bidirectional"))
    )
    (net (code "1154") (name "ZZ.05.180") (class "Default")
      (node (ref "U$24") (pin "P$172") (pinfunction "F22_P$172") (pintype "bidirectional"))
    )
    (net (code "1155") (name "ZZ.05.181") (class "Default")
      (node (ref "U$24") (pin "P$51") (pinfunction "B21_P$51") (pintype "bidirectional"))
    )
    (net (code "1156") (name "ZZ.05.182") (class "Default")
      (node (ref "U$24") (pin "P$81") (pinfunction "C21_P$81") (pintype "bidirectional"))
    )
    (net (code "1157") (name "ZZ.05.183") (class "Default")
      (node (ref "U$24") (pin "P$111") (pinfunction "D21_P$111") (pintype "bidirectional"))
    )
    (net (code "1158") (name "ZZ.05.184") (class "Default")
      (node (ref "U$24") (pin "P$141") (pinfunction "E21_P$141") (pintype "bidirectional"))
    )
    (net (code "1159") (name "ZZ.05.185") (class "Default")
      (node (ref "U$24") (pin "P$171") (pinfunction "F21_P$171") (pintype "bidirectional"))
    )
    (net (code "1160") (name "ZZ.05.186") (class "Default")
      (node (ref "U$24") (pin "P$50") (pinfunction "B20_P$50") (pintype "bidirectional"))
    )
    (net (code "1161") (name "ZZ.05.187") (class "Default")
      (node (ref "U$24") (pin "P$80") (pinfunction "C20_P$80") (pintype "bidirectional"))
    )
    (net (code "1162") (name "ZZ.05.188") (class "Default")
      (node (ref "U$24") (pin "P$110") (pinfunction "D20_P$110") (pintype "bidirectional"))
    )
    (net (code "1163") (name "ZZ.05.189") (class "Default")
      (node (ref "U$24") (pin "P$140") (pinfunction "E20_P$140") (pintype "bidirectional"))
    )
    (net (code "1164") (name "ZZ.05.190") (class "Default")
      (node (ref "U$24") (pin "P$170") (pinfunction "F20_P$170") (pintype "bidirectional"))
    )
    (net (code "1165") (name "ZZ.05.191") (class "Default")
      (node (ref "U$24") (pin "P$166") (pinfunction "F16_P$166") (pintype "bidirectional"))
    )
    (net (code "1166") (name "ZZ.06.000") (class "Default")
      (node (ref "U$2") (pin "P$57") (pinfunction "B27_P$57") (pintype "bidirectional"))
    )
    (net (code "1167") (name "ZZ.06.001") (class "Default")
      (node (ref "U$2") (pin "P$87") (pinfunction "C27_P$87") (pintype "bidirectional"))
    )
    (net (code "1168") (name "ZZ.06.002") (class "Default")
      (node (ref "U$2") (pin "P$117") (pinfunction "D27_P$117") (pintype "bidirectional"))
    )
    (net (code "1169") (name "ZZ.06.003") (class "Default")
      (node (ref "U$2") (pin "P$178") (pinfunction "F28_P$178") (pintype "bidirectional"))
    )
    (net (code "1170") (name "ZZ.06.004") (class "Default")
      (node (ref "U$2") (pin "P$145") (pinfunction "E25_P$145") (pintype "bidirectional"))
    )
    (net (code "1171") (name "ZZ.06.005") (class "Default")
      (node (ref "U$2") (pin "P$58") (pinfunction "B28_P$58") (pintype "bidirectional"))
    )
    (net (code "1172") (name "ZZ.06.006") (class "Default")
      (node (ref "U$2") (pin "P$88") (pinfunction "C28_P$88") (pintype "bidirectional"))
    )
    (net (code "1173") (name "ZZ.06.007") (class "Default")
      (node (ref "U$2") (pin "P$118") (pinfunction "D28_P$118") (pintype "bidirectional"))
    )
    (net (code "1174") (name "ZZ.06.008") (class "Default")
      (node (ref "U$2") (pin "P$149") (pinfunction "E29_P$149") (pintype "bidirectional"))
    )
    (net (code "1175") (name "ZZ.06.009") (class "Default")
      (node (ref "U$2") (pin "P$144") (pinfunction "E24_P$144") (pintype "bidirectional"))
    )
    (net (code "1176") (name "ZZ.06.010") (class "Default")
      (node (ref "U$2") (pin "P$59") (pinfunction "B29_P$59") (pintype "bidirectional"))
    )
    (net (code "1177") (name "ZZ.06.011") (class "Default")
      (node (ref "U$2") (pin "P$89") (pinfunction "C29_P$89") (pintype "bidirectional"))
    )
    (net (code "1178") (name "ZZ.06.012") (class "Default")
      (node (ref "U$2") (pin "P$119") (pinfunction "D29_P$119") (pintype "bidirectional"))
    )
    (net (code "1179") (name "ZZ.06.013") (class "Default")
      (node (ref "U$2") (pin "P$179") (pinfunction "F29_P$179") (pintype "bidirectional"))
    )
    (net (code "1180") (name "ZZ.06.014") (class "Default")
      (node (ref "U$2") (pin "P$173") (pinfunction "F23_P$173") (pintype "bidirectional"))
    )
    (net (code "1181") (name "ZZ.06.015") (class "Default")
      (node (ref "U$2") (pin "P$143") (pinfunction "E23_P$143") (pintype "bidirectional"))
    )
    (net (code "1182") (name "ZZ.06.016") (class "Default")
      (node (ref "U$4") (pin "P$57") (pinfunction "B27_P$57") (pintype "bidirectional"))
    )
    (net (code "1183") (name "ZZ.06.017") (class "Default")
      (node (ref "U$4") (pin "P$87") (pinfunction "C27_P$87") (pintype "bidirectional"))
    )
    (net (code "1184") (name "ZZ.06.018") (class "Default")
      (node (ref "U$4") (pin "P$117") (pinfunction "D27_P$117") (pintype "bidirectional"))
    )
    (net (code "1185") (name "ZZ.06.019") (class "Default")
      (node (ref "U$4") (pin "P$178") (pinfunction "F28_P$178") (pintype "bidirectional"))
    )
    (net (code "1186") (name "ZZ.06.020") (class "Default")
      (node (ref "U$4") (pin "P$145") (pinfunction "E25_P$145") (pintype "bidirectional"))
    )
    (net (code "1187") (name "ZZ.06.021") (class "Default")
      (node (ref "U$4") (pin "P$58") (pinfunction "B28_P$58") (pintype "bidirectional"))
    )
    (net (code "1188") (name "ZZ.06.022") (class "Default")
      (node (ref "U$4") (pin "P$88") (pinfunction "C28_P$88") (pintype "bidirectional"))
    )
    (net (code "1189") (name "ZZ.06.023") (class "Default")
      (node (ref "U$4") (pin "P$118") (pinfunction "D28_P$118") (pintype "bidirectional"))
    )
    (net (code "1190") (name "ZZ.06.024") (class "Default")
      (node (ref "U$4") (pin "P$149") (pinfunction "E29_P$149") (pintype "bidirectional"))
    )
    (net (code "1191") (name "ZZ.06.025") (class "Default")
      (node (ref "U$4") (pin "P$144") (pinfunction "E24_P$144") (pintype "bidirectional"))
    )
    (net (code "1192") (name "ZZ.06.026") (class "Default")
      (node (ref "U$4") (pin "P$59") (pinfunction "B29_P$59") (pintype "bidirectional"))
    )
    (net (code "1193") (name "ZZ.06.027") (class "Default")
      (node (ref "U$4") (pin "P$89") (pinfunction "C29_P$89") (pintype "bidirectional"))
    )
    (net (code "1194") (name "ZZ.06.028") (class "Default")
      (node (ref "U$4") (pin "P$119") (pinfunction "D29_P$119") (pintype "bidirectional"))
    )
    (net (code "1195") (name "ZZ.06.029") (class "Default")
      (node (ref "U$4") (pin "P$179") (pinfunction "F29_P$179") (pintype "bidirectional"))
    )
    (net (code "1196") (name "ZZ.06.030") (class "Default")
      (node (ref "U$4") (pin "P$173") (pinfunction "F23_P$173") (pintype "bidirectional"))
    )
    (net (code "1197") (name "ZZ.06.031") (class "Default")
      (node (ref "U$4") (pin "P$143") (pinfunction "E23_P$143") (pintype "bidirectional"))
    )
    (net (code "1198") (name "ZZ.06.032") (class "Default")
      (node (ref "U$6") (pin "P$57") (pinfunction "B27_P$57") (pintype "bidirectional"))
    )
    (net (code "1199") (name "ZZ.06.033") (class "Default")
      (node (ref "U$6") (pin "P$87") (pinfunction "C27_P$87") (pintype "bidirectional"))
    )
    (net (code "1200") (name "ZZ.06.034") (class "Default")
      (node (ref "U$6") (pin "P$117") (pinfunction "D27_P$117") (pintype "bidirectional"))
    )
    (net (code "1201") (name "ZZ.06.035") (class "Default")
      (node (ref "U$6") (pin "P$178") (pinfunction "F28_P$178") (pintype "bidirectional"))
    )
    (net (code "1202") (name "ZZ.06.036") (class "Default")
      (node (ref "U$6") (pin "P$145") (pinfunction "E25_P$145") (pintype "bidirectional"))
    )
    (net (code "1203") (name "ZZ.06.037") (class "Default")
      (node (ref "U$6") (pin "P$58") (pinfunction "B28_P$58") (pintype "bidirectional"))
    )
    (net (code "1204") (name "ZZ.06.038") (class "Default")
      (node (ref "U$6") (pin "P$88") (pinfunction "C28_P$88") (pintype "bidirectional"))
    )
    (net (code "1205") (name "ZZ.06.039") (class "Default")
      (node (ref "U$6") (pin "P$118") (pinfunction "D28_P$118") (pintype "bidirectional"))
    )
    (net (code "1206") (name "ZZ.06.040") (class "Default")
      (node (ref "U$6") (pin "P$149") (pinfunction "E29_P$149") (pintype "bidirectional"))
    )
    (net (code "1207") (name "ZZ.06.041") (class "Default")
      (node (ref "U$6") (pin "P$144") (pinfunction "E24_P$144") (pintype "bidirectional"))
    )
    (net (code "1208") (name "ZZ.06.042") (class "Default")
      (node (ref "U$6") (pin "P$59") (pinfunction "B29_P$59") (pintype "bidirectional"))
    )
    (net (code "1209") (name "ZZ.06.043") (class "Default")
      (node (ref "U$6") (pin "P$89") (pinfunction "C29_P$89") (pintype "bidirectional"))
    )
    (net (code "1210") (name "ZZ.06.044") (class "Default")
      (node (ref "U$6") (pin "P$119") (pinfunction "D29_P$119") (pintype "bidirectional"))
    )
    (net (code "1211") (name "ZZ.06.045") (class "Default")
      (node (ref "U$6") (pin "P$179") (pinfunction "F29_P$179") (pintype "bidirectional"))
    )
    (net (code "1212") (name "ZZ.06.046") (class "Default")
      (node (ref "U$6") (pin "P$173") (pinfunction "F23_P$173") (pintype "bidirectional"))
    )
    (net (code "1213") (name "ZZ.06.047") (class "Default")
      (node (ref "U$6") (pin "P$143") (pinfunction "E23_P$143") (pintype "bidirectional"))
    )
    (net (code "1214") (name "ZZ.06.048") (class "Default")
      (node (ref "U$8") (pin "P$57") (pinfunction "B27_P$57") (pintype "bidirectional"))
    )
    (net (code "1215") (name "ZZ.06.049") (class "Default")
      (node (ref "U$8") (pin "P$87") (pinfunction "C27_P$87") (pintype "bidirectional"))
    )
    (net (code "1216") (name "ZZ.06.050") (class "Default")
      (node (ref "U$8") (pin "P$117") (pinfunction "D27_P$117") (pintype "bidirectional"))
    )
    (net (code "1217") (name "ZZ.06.051") (class "Default")
      (node (ref "U$8") (pin "P$178") (pinfunction "F28_P$178") (pintype "bidirectional"))
    )
    (net (code "1218") (name "ZZ.06.052") (class "Default")
      (node (ref "U$8") (pin "P$145") (pinfunction "E25_P$145") (pintype "bidirectional"))
    )
    (net (code "1219") (name "ZZ.06.053") (class "Default")
      (node (ref "U$8") (pin "P$58") (pinfunction "B28_P$58") (pintype "bidirectional"))
    )
    (net (code "1220") (name "ZZ.06.054") (class "Default")
      (node (ref "U$8") (pin "P$88") (pinfunction "C28_P$88") (pintype "bidirectional"))
    )
    (net (code "1221") (name "ZZ.06.055") (class "Default")
      (node (ref "U$8") (pin "P$118") (pinfunction "D28_P$118") (pintype "bidirectional"))
    )
    (net (code "1222") (name "ZZ.06.056") (class "Default")
      (node (ref "U$8") (pin "P$59") (pinfunction "B29_P$59") (pintype "bidirectional"))
    )
    (net (code "1223") (name "ZZ.06.057") (class "Default")
      (node (ref "U$8") (pin "P$89") (pinfunction "C29_P$89") (pintype "bidirectional"))
    )
    (net (code "1224") (name "ZZ.06.058") (class "Default")
      (node (ref "U$8") (pin "P$119") (pinfunction "D29_P$119") (pintype "bidirectional"))
    )
    (net (code "1225") (name "ZZ.06.059") (class "Default")
      (node (ref "U$8") (pin "P$179") (pinfunction "F29_P$179") (pintype "bidirectional"))
    )
    (net (code "1226") (name "ZZ.06.060") (class "Default")
      (node (ref "U$8") (pin "P$173") (pinfunction "F23_P$173") (pintype "bidirectional"))
    )
    (net (code "1227") (name "ZZ.06.061") (class "Default")
      (node (ref "U$8") (pin "P$143") (pinfunction "E23_P$143") (pintype "bidirectional"))
    )
    (net (code "1228") (name "ZZ.06.062") (class "Default")
      (node (ref "U$8") (pin "P$149") (pinfunction "E29_P$149") (pintype "bidirectional"))
    )
    (net (code "1229") (name "ZZ.06.063") (class "Default")
      (node (ref "U$8") (pin "P$144") (pinfunction "E24_P$144") (pintype "bidirectional"))
    )
    (net (code "1230") (name "ZZ.06.064") (class "Default")
      (node (ref "U$10") (pin "P$57") (pinfunction "B27_P$57") (pintype "bidirectional"))
    )
    (net (code "1231") (name "ZZ.06.065") (class "Default")
      (node (ref "U$10") (pin "P$87") (pinfunction "C27_P$87") (pintype "bidirectional"))
    )
    (net (code "1232") (name "ZZ.06.066") (class "Default")
      (node (ref "U$10") (pin "P$117") (pinfunction "D27_P$117") (pintype "bidirectional"))
    )
    (net (code "1233") (name "ZZ.06.067") (class "Default")
      (node (ref "U$10") (pin "P$58") (pinfunction "B28_P$58") (pintype "bidirectional"))
    )
    (net (code "1234") (name "ZZ.06.068") (class "Default")
      (node (ref "U$10") (pin "P$88") (pinfunction "C28_P$88") (pintype "bidirectional"))
    )
    (net (code "1235") (name "ZZ.06.069") (class "Default")
      (node (ref "U$10") (pin "P$118") (pinfunction "D28_P$118") (pintype "bidirectional"))
    )
    (net (code "1236") (name "ZZ.06.070") (class "Default")
      (node (ref "U$10") (pin "P$59") (pinfunction "B29_P$59") (pintype "bidirectional"))
    )
    (net (code "1237") (name "ZZ.06.071") (class "Default")
      (node (ref "U$10") (pin "P$89") (pinfunction "C29_P$89") (pintype "bidirectional"))
    )
    (net (code "1238") (name "ZZ.06.072") (class "Default")
      (node (ref "U$10") (pin "P$119") (pinfunction "D29_P$119") (pintype "bidirectional"))
    )
    (net (code "1239") (name "ZZ.06.073") (class "Default")
      (node (ref "U$10") (pin "P$179") (pinfunction "F29_P$179") (pintype "bidirectional"))
    )
    (net (code "1240") (name "ZZ.06.074") (class "Default")
      (node (ref "U$10") (pin "P$173") (pinfunction "F23_P$173") (pintype "bidirectional"))
    )
    (net (code "1241") (name "ZZ.06.075") (class "Default")
      (node (ref "U$10") (pin "P$143") (pinfunction "E23_P$143") (pintype "bidirectional"))
    )
    (net (code "1242") (name "ZZ.06.076") (class "Default")
      (node (ref "U$10") (pin "P$149") (pinfunction "E29_P$149") (pintype "bidirectional"))
    )
    (net (code "1243") (name "ZZ.06.077") (class "Default")
      (node (ref "U$10") (pin "P$144") (pinfunction "E24_P$144") (pintype "bidirectional"))
    )
    (net (code "1244") (name "ZZ.06.078") (class "Default")
      (node (ref "U$10") (pin "P$178") (pinfunction "F28_P$178") (pintype "bidirectional"))
    )
    (net (code "1245") (name "ZZ.06.079") (class "Default")
      (node (ref "U$10") (pin "P$145") (pinfunction "E25_P$145") (pintype "bidirectional"))
    )
    (net (code "1246") (name "ZZ.06.080") (class "Default")
      (node (ref "U$12") (pin "P$57") (pinfunction "B27_P$57") (pintype "bidirectional"))
    )
    (net (code "1247") (name "ZZ.06.081") (class "Default")
      (node (ref "U$12") (pin "P$58") (pinfunction "B28_P$58") (pintype "bidirectional"))
    )
    (net (code "1248") (name "ZZ.06.082") (class "Default")
      (node (ref "U$12") (pin "P$88") (pinfunction "C28_P$88") (pintype "bidirectional"))
    )
    (net (code "1249") (name "ZZ.06.083") (class "Default")
      (node (ref "U$12") (pin "P$118") (pinfunction "D28_P$118") (pintype "bidirectional"))
    )
    (net (code "1250") (name "ZZ.06.084") (class "Default")
      (node (ref "U$12") (pin "P$59") (pinfunction "B29_P$59") (pintype "bidirectional"))
    )
    (net (code "1251") (name "ZZ.06.085") (class "Default")
      (node (ref "U$12") (pin "P$89") (pinfunction "C29_P$89") (pintype "bidirectional"))
    )
    (net (code "1252") (name "ZZ.06.086") (class "Default")
      (node (ref "U$12") (pin "P$119") (pinfunction "D29_P$119") (pintype "bidirectional"))
    )
    (net (code "1253") (name "ZZ.06.087") (class "Default")
      (node (ref "U$12") (pin "P$179") (pinfunction "F29_P$179") (pintype "bidirectional"))
    )
    (net (code "1254") (name "ZZ.06.088") (class "Default")
      (node (ref "U$12") (pin "P$173") (pinfunction "F23_P$173") (pintype "bidirectional"))
    )
    (net (code "1255") (name "ZZ.06.089") (class "Default")
      (node (ref "U$12") (pin "P$143") (pinfunction "E23_P$143") (pintype "bidirectional"))
    )
    (net (code "1256") (name "ZZ.06.090") (class "Default")
      (node (ref "U$12") (pin "P$149") (pinfunction "E29_P$149") (pintype "bidirectional"))
    )
    (net (code "1257") (name "ZZ.06.091") (class "Default")
      (node (ref "U$12") (pin "P$144") (pinfunction "E24_P$144") (pintype "bidirectional"))
    )
    (net (code "1258") (name "ZZ.06.092") (class "Default")
      (node (ref "U$12") (pin "P$87") (pinfunction "C27_P$87") (pintype "bidirectional"))
    )
    (net (code "1259") (name "ZZ.06.093") (class "Default")
      (node (ref "U$12") (pin "P$117") (pinfunction "D27_P$117") (pintype "bidirectional"))
    )
    (net (code "1260") (name "ZZ.06.094") (class "Default")
      (node (ref "U$12") (pin "P$178") (pinfunction "F28_P$178") (pintype "bidirectional"))
    )
    (net (code "1261") (name "ZZ.06.095") (class "Default")
      (node (ref "U$12") (pin "P$145") (pinfunction "E25_P$145") (pintype "bidirectional"))
    )
    (net (code "1262") (name "ZZ.06.096") (class "Default")
      (node (ref "U$14") (pin "P$58") (pinfunction "B28_P$58") (pintype "bidirectional"))
    )
    (net (code "1263") (name "ZZ.06.097") (class "Default")
      (node (ref "U$14") (pin "P$59") (pinfunction "B29_P$59") (pintype "bidirectional"))
    )
    (net (code "1264") (name "ZZ.06.098") (class "Default")
      (node (ref "U$14") (pin "P$89") (pinfunction "C29_P$89") (pintype "bidirectional"))
    )
    (net (code "1265") (name "ZZ.06.099") (class "Default")
      (node (ref "U$14") (pin "P$119") (pinfunction "D29_P$119") (pintype "bidirectional"))
    )
    (net (code "1266") (name "ZZ.06.100") (class "Default")
      (node (ref "U$14") (pin "P$179") (pinfunction "F29_P$179") (pintype "bidirectional"))
    )
    (net (code "1267") (name "ZZ.06.101") (class "Default")
      (node (ref "U$14") (pin "P$173") (pinfunction "F23_P$173") (pintype "bidirectional"))
    )
    (net (code "1268") (name "ZZ.06.102") (class "Default")
      (node (ref "U$14") (pin "P$143") (pinfunction "E23_P$143") (pintype "bidirectional"))
    )
    (net (code "1269") (name "ZZ.06.103") (class "Default")
      (node (ref "U$14") (pin "P$88") (pinfunction "C28_P$88") (pintype "bidirectional"))
    )
    (net (code "1270") (name "ZZ.06.104") (class "Default")
      (node (ref "U$14") (pin "P$118") (pinfunction "D28_P$118") (pintype "bidirectional"))
    )
    (net (code "1271") (name "ZZ.06.105") (class "Default")
      (node (ref "U$14") (pin "P$149") (pinfunction "E29_P$149") (pintype "bidirectional"))
    )
    (net (code "1272") (name "ZZ.06.106") (class "Default")
      (node (ref "U$14") (pin "P$144") (pinfunction "E24_P$144") (pintype "bidirectional"))
    )
    (net (code "1273") (name "ZZ.06.107") (class "Default")
      (node (ref "U$14") (pin "P$57") (pinfunction "B27_P$57") (pintype "bidirectional"))
    )
    (net (code "1274") (name "ZZ.06.108") (class "Default")
      (node (ref "U$14") (pin "P$87") (pinfunction "C27_P$87") (pintype "bidirectional"))
    )
    (net (code "1275") (name "ZZ.06.109") (class "Default")
      (node (ref "U$14") (pin "P$117") (pinfunction "D27_P$117") (pintype "bidirectional"))
    )
    (net (code "1276") (name "ZZ.06.110") (class "Default")
      (node (ref "U$14") (pin "P$178") (pinfunction "F28_P$178") (pintype "bidirectional"))
    )
    (net (code "1277") (name "ZZ.06.111") (class "Default")
      (node (ref "U$14") (pin "P$145") (pinfunction "E25_P$145") (pintype "bidirectional"))
    )
    (net (code "1278") (name "ZZ.06.112") (class "Default")
      (node (ref "U$16") (pin "P$59") (pinfunction "B29_P$59") (pintype "bidirectional"))
    )
    (net (code "1279") (name "ZZ.06.113") (class "Default")
      (node (ref "U$16") (pin "P$89") (pinfunction "C29_P$89") (pintype "bidirectional"))
    )
    (net (code "1280") (name "ZZ.06.114") (class "Default")
      (node (ref "U$16") (pin "P$119") (pinfunction "D29_P$119") (pintype "bidirectional"))
    )
    (net (code "1281") (name "ZZ.06.115") (class "Default")
      (node (ref "U$16") (pin "P$179") (pinfunction "F29_P$179") (pintype "bidirectional"))
    )
    (net (code "1282") (name "ZZ.06.116") (class "Default")
      (node (ref "U$16") (pin "P$173") (pinfunction "F23_P$173") (pintype "bidirectional"))
    )
    (net (code "1283") (name "ZZ.06.117") (class "Default")
      (node (ref "U$16") (pin "P$143") (pinfunction "E23_P$143") (pintype "bidirectional"))
    )
    (net (code "1284") (name "ZZ.06.118") (class "Default")
      (node (ref "U$16") (pin "P$58") (pinfunction "B28_P$58") (pintype "bidirectional"))
    )
    (net (code "1285") (name "ZZ.06.119") (class "Default")
      (node (ref "U$16") (pin "P$88") (pinfunction "C28_P$88") (pintype "bidirectional"))
    )
    (net (code "1286") (name "ZZ.06.120") (class "Default")
      (node (ref "U$16") (pin "P$118") (pinfunction "D28_P$118") (pintype "bidirectional"))
    )
    (net (code "1287") (name "ZZ.06.121") (class "Default")
      (node (ref "U$16") (pin "P$149") (pinfunction "E29_P$149") (pintype "bidirectional"))
    )
    (net (code "1288") (name "ZZ.06.122") (class "Default")
      (node (ref "U$16") (pin "P$144") (pinfunction "E24_P$144") (pintype "bidirectional"))
    )
    (net (code "1289") (name "ZZ.06.123") (class "Default")
      (node (ref "U$16") (pin "P$57") (pinfunction "B27_P$57") (pintype "bidirectional"))
    )
    (net (code "1290") (name "ZZ.06.124") (class "Default")
      (node (ref "U$16") (pin "P$87") (pinfunction "C27_P$87") (pintype "bidirectional"))
    )
    (net (code "1291") (name "ZZ.06.125") (class "Default")
      (node (ref "U$16") (pin "P$117") (pinfunction "D27_P$117") (pintype "bidirectional"))
    )
    (net (code "1292") (name "ZZ.06.126") (class "Default")
      (node (ref "U$16") (pin "P$178") (pinfunction "F28_P$178") (pintype "bidirectional"))
    )
    (net (code "1293") (name "ZZ.06.127") (class "Default")
      (node (ref "U$16") (pin "P$145") (pinfunction "E25_P$145") (pintype "bidirectional"))
    )
    (net (code "1294") (name "ZZ.06.128") (class "Default")
      (node (ref "U$18") (pin "P$59") (pinfunction "B29_P$59") (pintype "bidirectional"))
    )
    (net (code "1295") (name "ZZ.06.129") (class "Default")
      (node (ref "U$18") (pin "P$89") (pinfunction "C29_P$89") (pintype "bidirectional"))
    )
    (net (code "1296") (name "ZZ.06.130") (class "Default")
      (node (ref "U$18") (pin "P$119") (pinfunction "D29_P$119") (pintype "bidirectional"))
    )
    (net (code "1297") (name "ZZ.06.131") (class "Default")
      (node (ref "U$18") (pin "P$179") (pinfunction "F29_P$179") (pintype "bidirectional"))
    )
    (net (code "1298") (name "ZZ.06.132") (class "Default")
      (node (ref "U$18") (pin "P$173") (pinfunction "F23_P$173") (pintype "bidirectional"))
    )
    (net (code "1299") (name "ZZ.06.133") (class "Default")
      (node (ref "U$18") (pin "P$143") (pinfunction "E23_P$143") (pintype "bidirectional"))
    )
    (net (code "1300") (name "ZZ.06.134") (class "Default")
      (node (ref "U$18") (pin "P$58") (pinfunction "B28_P$58") (pintype "bidirectional"))
    )
    (net (code "1301") (name "ZZ.06.135") (class "Default")
      (node (ref "U$18") (pin "P$88") (pinfunction "C28_P$88") (pintype "bidirectional"))
    )
    (net (code "1302") (name "ZZ.06.136") (class "Default")
      (node (ref "U$18") (pin "P$118") (pinfunction "D28_P$118") (pintype "bidirectional"))
    )
    (net (code "1303") (name "ZZ.06.137") (class "Default")
      (node (ref "U$18") (pin "P$149") (pinfunction "E29_P$149") (pintype "bidirectional"))
    )
    (net (code "1304") (name "ZZ.06.138") (class "Default")
      (node (ref "U$18") (pin "P$144") (pinfunction "E24_P$144") (pintype "bidirectional"))
    )
    (net (code "1305") (name "ZZ.06.139") (class "Default")
      (node (ref "U$18") (pin "P$57") (pinfunction "B27_P$57") (pintype "bidirectional"))
    )
    (net (code "1306") (name "ZZ.06.140") (class "Default")
      (node (ref "U$18") (pin "P$87") (pinfunction "C27_P$87") (pintype "bidirectional"))
    )
    (net (code "1307") (name "ZZ.06.141") (class "Default")
      (node (ref "U$18") (pin "P$117") (pinfunction "D27_P$117") (pintype "bidirectional"))
    )
    (net (code "1308") (name "ZZ.06.142") (class "Default")
      (node (ref "U$18") (pin "P$178") (pinfunction "F28_P$178") (pintype "bidirectional"))
    )
    (net (code "1309") (name "ZZ.06.143") (class "Default")
      (node (ref "U$18") (pin "P$145") (pinfunction "E25_P$145") (pintype "bidirectional"))
    )
    (net (code "1310") (name "ZZ.06.144") (class "Default")
      (node (ref "U$20") (pin "P$59") (pinfunction "B29_P$59") (pintype "bidirectional"))
    )
    (net (code "1311") (name "ZZ.06.145") (class "Default")
      (node (ref "U$20") (pin "P$89") (pinfunction "C29_P$89") (pintype "bidirectional"))
    )
    (net (code "1312") (name "ZZ.06.146") (class "Default")
      (node (ref "U$20") (pin "P$119") (pinfunction "D29_P$119") (pintype "bidirectional"))
    )
    (net (code "1313") (name "ZZ.06.147") (class "Default")
      (node (ref "U$20") (pin "P$179") (pinfunction "F29_P$179") (pintype "bidirectional"))
    )
    (net (code "1314") (name "ZZ.06.148") (class "Default")
      (node (ref "U$20") (pin "P$173") (pinfunction "F23_P$173") (pintype "bidirectional"))
    )
    (net (code "1315") (name "ZZ.06.149") (class "Default")
      (node (ref "U$20") (pin "P$143") (pinfunction "E23_P$143") (pintype "bidirectional"))
    )
    (net (code "1316") (name "ZZ.06.150") (class "Default")
      (node (ref "U$20") (pin "P$58") (pinfunction "B28_P$58") (pintype "bidirectional"))
    )
    (net (code "1317") (name "ZZ.06.151") (class "Default")
      (node (ref "U$20") (pin "P$88") (pinfunction "C28_P$88") (pintype "bidirectional"))
    )
    (net (code "1318") (name "ZZ.06.152") (class "Default")
      (node (ref "U$20") (pin "P$118") (pinfunction "D28_P$118") (pintype "bidirectional"))
    )
    (net (code "1319") (name "ZZ.06.153") (class "Default")
      (node (ref "U$20") (pin "P$149") (pinfunction "E29_P$149") (pintype "bidirectional"))
    )
    (net (code "1320") (name "ZZ.06.154") (class "Default")
      (node (ref "U$20") (pin "P$144") (pinfunction "E24_P$144") (pintype "bidirectional"))
    )
    (net (code "1321") (name "ZZ.06.155") (class "Default")
      (node (ref "U$20") (pin "P$57") (pinfunction "B27_P$57") (pintype "bidirectional"))
    )
    (net (code "1322") (name "ZZ.06.156") (class "Default")
      (node (ref "U$20") (pin "P$87") (pinfunction "C27_P$87") (pintype "bidirectional"))
    )
    (net (code "1323") (name "ZZ.06.157") (class "Default")
      (node (ref "U$20") (pin "P$117") (pinfunction "D27_P$117") (pintype "bidirectional"))
    )
    (net (code "1324") (name "ZZ.06.158") (class "Default")
      (node (ref "U$20") (pin "P$178") (pinfunction "F28_P$178") (pintype "bidirectional"))
    )
    (net (code "1325") (name "ZZ.06.159") (class "Default")
      (node (ref "U$20") (pin "P$145") (pinfunction "E25_P$145") (pintype "bidirectional"))
    )
    (net (code "1326") (name "ZZ.06.160") (class "Default")
      (node (ref "U$22") (pin "P$59") (pinfunction "B29_P$59") (pintype "bidirectional"))
    )
    (net (code "1327") (name "ZZ.06.161") (class "Default")
      (node (ref "U$22") (pin "P$89") (pinfunction "C29_P$89") (pintype "bidirectional"))
    )
    (net (code "1328") (name "ZZ.06.162") (class "Default")
      (node (ref "U$22") (pin "P$119") (pinfunction "D29_P$119") (pintype "bidirectional"))
    )
    (net (code "1329") (name "ZZ.06.163") (class "Default")
      (node (ref "U$22") (pin "P$179") (pinfunction "F29_P$179") (pintype "bidirectional"))
    )
    (net (code "1330") (name "ZZ.06.164") (class "Default")
      (node (ref "U$22") (pin "P$173") (pinfunction "F23_P$173") (pintype "bidirectional"))
    )
    (net (code "1331") (name "ZZ.06.165") (class "Default")
      (node (ref "U$22") (pin "P$143") (pinfunction "E23_P$143") (pintype "bidirectional"))
    )
    (net (code "1332") (name "ZZ.06.166") (class "Default")
      (node (ref "U$22") (pin "P$58") (pinfunction "B28_P$58") (pintype "bidirectional"))
    )
    (net (code "1333") (name "ZZ.06.167") (class "Default")
      (node (ref "U$22") (pin "P$88") (pinfunction "C28_P$88") (pintype "bidirectional"))
    )
    (net (code "1334") (name "ZZ.06.168") (class "Default")
      (node (ref "U$22") (pin "P$118") (pinfunction "D28_P$118") (pintype "bidirectional"))
    )
    (net (code "1335") (name "ZZ.06.169") (class "Default")
      (node (ref "U$22") (pin "P$149") (pinfunction "E29_P$149") (pintype "bidirectional"))
    )
    (net (code "1336") (name "ZZ.06.170") (class "Default")
      (node (ref "U$22") (pin "P$144") (pinfunction "E24_P$144") (pintype "bidirectional"))
    )
    (net (code "1337") (name "ZZ.06.171") (class "Default")
      (node (ref "U$22") (pin "P$57") (pinfunction "B27_P$57") (pintype "bidirectional"))
    )
    (net (code "1338") (name "ZZ.06.172") (class "Default")
      (node (ref "U$22") (pin "P$87") (pinfunction "C27_P$87") (pintype "bidirectional"))
    )
    (net (code "1339") (name "ZZ.06.173") (class "Default")
      (node (ref "U$22") (pin "P$117") (pinfunction "D27_P$117") (pintype "bidirectional"))
    )
    (net (code "1340") (name "ZZ.06.174") (class "Default")
      (node (ref "U$22") (pin "P$178") (pinfunction "F28_P$178") (pintype "bidirectional"))
    )
    (net (code "1341") (name "ZZ.06.175") (class "Default")
      (node (ref "U$22") (pin "P$145") (pinfunction "E25_P$145") (pintype "bidirectional"))
    )
    (net (code "1342") (name "ZZ.06.176") (class "Default")
      (node (ref "U$24") (pin "P$59") (pinfunction "B29_P$59") (pintype "bidirectional"))
    )
    (net (code "1343") (name "ZZ.06.177") (class "Default")
      (node (ref "U$24") (pin "P$89") (pinfunction "C29_P$89") (pintype "bidirectional"))
    )
    (net (code "1344") (name "ZZ.06.178") (class "Default")
      (node (ref "U$24") (pin "P$119") (pinfunction "D29_P$119") (pintype "bidirectional"))
    )
    (net (code "1345") (name "ZZ.06.179") (class "Default")
      (node (ref "U$24") (pin "P$179") (pinfunction "F29_P$179") (pintype "bidirectional"))
    )
    (net (code "1346") (name "ZZ.06.180") (class "Default")
      (node (ref "U$24") (pin "P$173") (pinfunction "F23_P$173") (pintype "bidirectional"))
    )
    (net (code "1347") (name "ZZ.06.181") (class "Default")
      (node (ref "U$24") (pin "P$143") (pinfunction "E23_P$143") (pintype "bidirectional"))
    )
    (net (code "1348") (name "ZZ.06.182") (class "Default")
      (node (ref "U$24") (pin "P$58") (pinfunction "B28_P$58") (pintype "bidirectional"))
    )
    (net (code "1349") (name "ZZ.06.183") (class "Default")
      (node (ref "U$24") (pin "P$88") (pinfunction "C28_P$88") (pintype "bidirectional"))
    )
    (net (code "1350") (name "ZZ.06.184") (class "Default")
      (node (ref "U$24") (pin "P$118") (pinfunction "D28_P$118") (pintype "bidirectional"))
    )
    (net (code "1351") (name "ZZ.06.185") (class "Default")
      (node (ref "U$24") (pin "P$149") (pinfunction "E29_P$149") (pintype "bidirectional"))
    )
    (net (code "1352") (name "ZZ.06.186") (class "Default")
      (node (ref "U$24") (pin "P$144") (pinfunction "E24_P$144") (pintype "bidirectional"))
    )
    (net (code "1353") (name "ZZ.06.187") (class "Default")
      (node (ref "U$24") (pin "P$57") (pinfunction "B27_P$57") (pintype "bidirectional"))
    )
    (net (code "1354") (name "ZZ.06.188") (class "Default")
      (node (ref "U$24") (pin "P$87") (pinfunction "C27_P$87") (pintype "bidirectional"))
    )
    (net (code "1355") (name "ZZ.06.189") (class "Default")
      (node (ref "U$24") (pin "P$117") (pinfunction "D27_P$117") (pintype "bidirectional"))
    )
    (net (code "1356") (name "ZZ.06.190") (class "Default")
      (node (ref "U$24") (pin "P$178") (pinfunction "F28_P$178") (pintype "bidirectional"))
    )
    (net (code "1357") (name "ZZ.06.191") (class "Default")
      (node (ref "U$24") (pin "P$145") (pinfunction "E25_P$145") (pintype "bidirectional"))
    )
    (net (code "1358") (name "ZZ.07.000") (class "Default")
      (node (ref "U$2") (pin "P$56") (pinfunction "B26_P$56") (pintype "bidirectional"))
    )
    (net (code "1359") (name "ZZ.07.001") (class "Default")
      (node (ref "U$2") (pin "P$86") (pinfunction "C26_P$86") (pintype "bidirectional"))
    )
    (net (code "1360") (name "ZZ.07.002") (class "Default")
      (node (ref "U$2") (pin "P$116") (pinfunction "D26_P$116") (pintype "bidirectional"))
    )
    (net (code "1361") (name "ZZ.07.003") (class "Default")
      (node (ref "U$2") (pin "P$148") (pinfunction "E28_P$148") (pintype "bidirectional"))
    )
    (net (code "1362") (name "ZZ.07.004") (class "Default")
      (node (ref "U$2") (pin "P$175") (pinfunction "F25_P$175") (pintype "bidirectional"))
    )
    (net (code "1363") (name "ZZ.07.005") (class "Default")
      (node (ref "U$2") (pin "P$55") (pinfunction "B25_P$55") (pintype "bidirectional"))
    )
    (net (code "1364") (name "ZZ.07.006") (class "Default")
      (node (ref "U$2") (pin "P$85") (pinfunction "C25_P$85") (pintype "bidirectional"))
    )
    (net (code "1365") (name "ZZ.07.007") (class "Default")
      (node (ref "U$2") (pin "P$115") (pinfunction "D25_P$115") (pintype "bidirectional"))
    )
    (net (code "1366") (name "ZZ.07.008") (class "Default")
      (node (ref "U$2") (pin "P$177") (pinfunction "F27_P$177") (pintype "bidirectional"))
    )
    (net (code "1367") (name "ZZ.07.009") (class "Default")
      (node (ref "U$2") (pin "P$146") (pinfunction "E26_P$146") (pintype "bidirectional"))
    )
    (net (code "1368") (name "ZZ.07.010") (class "Default")
      (node (ref "U$2") (pin "P$54") (pinfunction "B24_P$54") (pintype "bidirectional"))
    )
    (net (code "1369") (name "ZZ.07.011") (class "Default")
      (node (ref "U$2") (pin "P$84") (pinfunction "C24_P$84") (pintype "bidirectional"))
    )
    (net (code "1370") (name "ZZ.07.012") (class "Default")
      (node (ref "U$2") (pin "P$114") (pinfunction "D24_P$114") (pintype "bidirectional"))
    )
    (net (code "1371") (name "ZZ.07.013") (class "Default")
      (node (ref "U$2") (pin "P$147") (pinfunction "E27_P$147") (pintype "bidirectional"))
    )
    (net (code "1372") (name "ZZ.07.014") (class "Default")
      (node (ref "U$2") (pin "P$176") (pinfunction "F26_P$176") (pintype "bidirectional"))
    )
    (net (code "1373") (name "ZZ.07.015") (class "Default")
      (node (ref "U$2") (pin "P$174") (pinfunction "F24_P$174") (pintype "bidirectional"))
    )
    (net (code "1374") (name "ZZ.07.016") (class "Default")
      (node (ref "U$4") (pin "P$56") (pinfunction "B26_P$56") (pintype "bidirectional"))
    )
    (net (code "1375") (name "ZZ.07.017") (class "Default")
      (node (ref "U$4") (pin "P$86") (pinfunction "C26_P$86") (pintype "bidirectional"))
    )
    (net (code "1376") (name "ZZ.07.018") (class "Default")
      (node (ref "U$4") (pin "P$116") (pinfunction "D26_P$116") (pintype "bidirectional"))
    )
    (net (code "1377") (name "ZZ.07.019") (class "Default")
      (node (ref "U$4") (pin "P$148") (pinfunction "E28_P$148") (pintype "bidirectional"))
    )
    (net (code "1378") (name "ZZ.07.020") (class "Default")
      (node (ref "U$4") (pin "P$175") (pinfunction "F25_P$175") (pintype "bidirectional"))
    )
    (net (code "1379") (name "ZZ.07.021") (class "Default")
      (node (ref "U$4") (pin "P$55") (pinfunction "B25_P$55") (pintype "bidirectional"))
    )
    (net (code "1380") (name "ZZ.07.022") (class "Default")
      (node (ref "U$4") (pin "P$85") (pinfunction "C25_P$85") (pintype "bidirectional"))
    )
    (net (code "1381") (name "ZZ.07.023") (class "Default")
      (node (ref "U$4") (pin "P$115") (pinfunction "D25_P$115") (pintype "bidirectional"))
    )
    (net (code "1382") (name "ZZ.07.024") (class "Default")
      (node (ref "U$4") (pin "P$177") (pinfunction "F27_P$177") (pintype "bidirectional"))
    )
    (net (code "1383") (name "ZZ.07.025") (class "Default")
      (node (ref "U$4") (pin "P$146") (pinfunction "E26_P$146") (pintype "bidirectional"))
    )
    (net (code "1384") (name "ZZ.07.026") (class "Default")
      (node (ref "U$4") (pin "P$54") (pinfunction "B24_P$54") (pintype "bidirectional"))
    )
    (net (code "1385") (name "ZZ.07.027") (class "Default")
      (node (ref "U$4") (pin "P$84") (pinfunction "C24_P$84") (pintype "bidirectional"))
    )
    (net (code "1386") (name "ZZ.07.028") (class "Default")
      (node (ref "U$4") (pin "P$114") (pinfunction "D24_P$114") (pintype "bidirectional"))
    )
    (net (code "1387") (name "ZZ.07.029") (class "Default")
      (node (ref "U$4") (pin "P$147") (pinfunction "E27_P$147") (pintype "bidirectional"))
    )
    (net (code "1388") (name "ZZ.07.030") (class "Default")
      (node (ref "U$4") (pin "P$176") (pinfunction "F26_P$176") (pintype "bidirectional"))
    )
    (net (code "1389") (name "ZZ.07.031") (class "Default")
      (node (ref "U$4") (pin "P$174") (pinfunction "F24_P$174") (pintype "bidirectional"))
    )
    (net (code "1390") (name "ZZ.07.032") (class "Default")
      (node (ref "U$6") (pin "P$56") (pinfunction "B26_P$56") (pintype "bidirectional"))
    )
    (net (code "1391") (name "ZZ.07.033") (class "Default")
      (node (ref "U$6") (pin "P$86") (pinfunction "C26_P$86") (pintype "bidirectional"))
    )
    (net (code "1392") (name "ZZ.07.034") (class "Default")
      (node (ref "U$6") (pin "P$116") (pinfunction "D26_P$116") (pintype "bidirectional"))
    )
    (net (code "1393") (name "ZZ.07.035") (class "Default")
      (node (ref "U$6") (pin "P$148") (pinfunction "E28_P$148") (pintype "bidirectional"))
    )
    (net (code "1394") (name "ZZ.07.036") (class "Default")
      (node (ref "U$6") (pin "P$175") (pinfunction "F25_P$175") (pintype "bidirectional"))
    )
    (net (code "1395") (name "ZZ.07.037") (class "Default")
      (node (ref "U$6") (pin "P$55") (pinfunction "B25_P$55") (pintype "bidirectional"))
    )
    (net (code "1396") (name "ZZ.07.038") (class "Default")
      (node (ref "U$6") (pin "P$85") (pinfunction "C25_P$85") (pintype "bidirectional"))
    )
    (net (code "1397") (name "ZZ.07.039") (class "Default")
      (node (ref "U$6") (pin "P$115") (pinfunction "D25_P$115") (pintype "bidirectional"))
    )
    (net (code "1398") (name "ZZ.07.040") (class "Default")
      (node (ref "U$6") (pin "P$177") (pinfunction "F27_P$177") (pintype "bidirectional"))
    )
    (net (code "1399") (name "ZZ.07.041") (class "Default")
      (node (ref "U$6") (pin "P$146") (pinfunction "E26_P$146") (pintype "bidirectional"))
    )
    (net (code "1400") (name "ZZ.07.042") (class "Default")
      (node (ref "U$6") (pin "P$54") (pinfunction "B24_P$54") (pintype "bidirectional"))
    )
    (net (code "1401") (name "ZZ.07.043") (class "Default")
      (node (ref "U$6") (pin "P$84") (pinfunction "C24_P$84") (pintype "bidirectional"))
    )
    (net (code "1402") (name "ZZ.07.044") (class "Default")
      (node (ref "U$6") (pin "P$114") (pinfunction "D24_P$114") (pintype "bidirectional"))
    )
    (net (code "1403") (name "ZZ.07.045") (class "Default")
      (node (ref "U$6") (pin "P$147") (pinfunction "E27_P$147") (pintype "bidirectional"))
    )
    (net (code "1404") (name "ZZ.07.046") (class "Default")
      (node (ref "U$6") (pin "P$176") (pinfunction "F26_P$176") (pintype "bidirectional"))
    )
    (net (code "1405") (name "ZZ.07.047") (class "Default")
      (node (ref "U$6") (pin "P$174") (pinfunction "F24_P$174") (pintype "bidirectional"))
    )
    (net (code "1406") (name "ZZ.07.048") (class "Default")
      (node (ref "U$8") (pin "P$56") (pinfunction "B26_P$56") (pintype "bidirectional"))
    )
    (net (code "1407") (name "ZZ.07.049") (class "Default")
      (node (ref "U$8") (pin "P$86") (pinfunction "C26_P$86") (pintype "bidirectional"))
    )
    (net (code "1408") (name "ZZ.07.050") (class "Default")
      (node (ref "U$8") (pin "P$116") (pinfunction "D26_P$116") (pintype "bidirectional"))
    )
    (net (code "1409") (name "ZZ.07.051") (class "Default")
      (node (ref "U$8") (pin "P$148") (pinfunction "E28_P$148") (pintype "bidirectional"))
    )
    (net (code "1410") (name "ZZ.07.052") (class "Default")
      (node (ref "U$8") (pin "P$175") (pinfunction "F25_P$175") (pintype "bidirectional"))
    )
    (net (code "1411") (name "ZZ.07.053") (class "Default")
      (node (ref "U$8") (pin "P$55") (pinfunction "B25_P$55") (pintype "bidirectional"))
    )
    (net (code "1412") (name "ZZ.07.054") (class "Default")
      (node (ref "U$8") (pin "P$85") (pinfunction "C25_P$85") (pintype "bidirectional"))
    )
    (net (code "1413") (name "ZZ.07.055") (class "Default")
      (node (ref "U$8") (pin "P$115") (pinfunction "D25_P$115") (pintype "bidirectional"))
    )
    (net (code "1414") (name "ZZ.07.056") (class "Default")
      (node (ref "U$8") (pin "P$54") (pinfunction "B24_P$54") (pintype "bidirectional"))
    )
    (net (code "1415") (name "ZZ.07.057") (class "Default")
      (node (ref "U$8") (pin "P$84") (pinfunction "C24_P$84") (pintype "bidirectional"))
    )
    (net (code "1416") (name "ZZ.07.058") (class "Default")
      (node (ref "U$8") (pin "P$114") (pinfunction "D24_P$114") (pintype "bidirectional"))
    )
    (net (code "1417") (name "ZZ.07.059") (class "Default")
      (node (ref "U$8") (pin "P$147") (pinfunction "E27_P$147") (pintype "bidirectional"))
    )
    (net (code "1418") (name "ZZ.07.060") (class "Default")
      (node (ref "U$8") (pin "P$176") (pinfunction "F26_P$176") (pintype "bidirectional"))
    )
    (net (code "1419") (name "ZZ.07.061") (class "Default")
      (node (ref "U$8") (pin "P$174") (pinfunction "F24_P$174") (pintype "bidirectional"))
    )
    (net (code "1420") (name "ZZ.07.062") (class "Default")
      (node (ref "U$8") (pin "P$177") (pinfunction "F27_P$177") (pintype "bidirectional"))
    )
    (net (code "1421") (name "ZZ.07.063") (class "Default")
      (node (ref "U$8") (pin "P$146") (pinfunction "E26_P$146") (pintype "bidirectional"))
    )
    (net (code "1422") (name "ZZ.07.064") (class "Default")
      (node (ref "U$10") (pin "P$56") (pinfunction "B26_P$56") (pintype "bidirectional"))
    )
    (net (code "1423") (name "ZZ.07.065") (class "Default")
      (node (ref "U$10") (pin "P$86") (pinfunction "C26_P$86") (pintype "bidirectional"))
    )
    (net (code "1424") (name "ZZ.07.066") (class "Default")
      (node (ref "U$10") (pin "P$116") (pinfunction "D26_P$116") (pintype "bidirectional"))
    )
    (net (code "1425") (name "ZZ.07.067") (class "Default")
      (node (ref "U$10") (pin "P$55") (pinfunction "B25_P$55") (pintype "bidirectional"))
    )
    (net (code "1426") (name "ZZ.07.068") (class "Default")
      (node (ref "U$10") (pin "P$85") (pinfunction "C25_P$85") (pintype "bidirectional"))
    )
    (net (code "1427") (name "ZZ.07.069") (class "Default")
      (node (ref "U$10") (pin "P$115") (pinfunction "D25_P$115") (pintype "bidirectional"))
    )
    (net (code "1428") (name "ZZ.07.070") (class "Default")
      (node (ref "U$10") (pin "P$54") (pinfunction "B24_P$54") (pintype "bidirectional"))
    )
    (net (code "1429") (name "ZZ.07.071") (class "Default")
      (node (ref "U$10") (pin "P$84") (pinfunction "C24_P$84") (pintype "bidirectional"))
    )
    (net (code "1430") (name "ZZ.07.072") (class "Default")
      (node (ref "U$10") (pin "P$114") (pinfunction "D24_P$114") (pintype "bidirectional"))
    )
    (net (code "1431") (name "ZZ.07.073") (class "Default")
      (node (ref "U$10") (pin "P$147") (pinfunction "E27_P$147") (pintype "bidirectional"))
    )
    (net (code "1432") (name "ZZ.07.074") (class "Default")
      (node (ref "U$10") (pin "P$176") (pinfunction "F26_P$176") (pintype "bidirectional"))
    )
    (net (code "1433") (name "ZZ.07.075") (class "Default")
      (node (ref "U$10") (pin "P$174") (pinfunction "F24_P$174") (pintype "bidirectional"))
    )
    (net (code "1434") (name "ZZ.07.076") (class "Default")
      (node (ref "U$10") (pin "P$177") (pinfunction "F27_P$177") (pintype "bidirectional"))
    )
    (net (code "1435") (name "ZZ.07.077") (class "Default")
      (node (ref "U$10") (pin "P$146") (pinfunction "E26_P$146") (pintype "bidirectional"))
    )
    (net (code "1436") (name "ZZ.07.078") (class "Default")
      (node (ref "U$10") (pin "P$148") (pinfunction "E28_P$148") (pintype "bidirectional"))
    )
    (net (code "1437") (name "ZZ.07.079") (class "Default")
      (node (ref "U$10") (pin "P$175") (pinfunction "F25_P$175") (pintype "bidirectional"))
    )
    (net (code "1438") (name "ZZ.07.080") (class "Default")
      (node (ref "U$12") (pin "P$56") (pinfunction "B26_P$56") (pintype "bidirectional"))
    )
    (net (code "1439") (name "ZZ.07.081") (class "Default")
      (node (ref "U$12") (pin "P$55") (pinfunction "B25_P$55") (pintype "bidirectional"))
    )
    (net (code "1440") (name "ZZ.07.082") (class "Default")
      (node (ref "U$12") (pin "P$85") (pinfunction "C25_P$85") (pintype "bidirectional"))
    )
    (net (code "1441") (name "ZZ.07.083") (class "Default")
      (node (ref "U$12") (pin "P$115") (pinfunction "D25_P$115") (pintype "bidirectional"))
    )
    (net (code "1442") (name "ZZ.07.084") (class "Default")
      (node (ref "U$12") (pin "P$54") (pinfunction "B24_P$54") (pintype "bidirectional"))
    )
    (net (code "1443") (name "ZZ.07.085") (class "Default")
      (node (ref "U$12") (pin "P$84") (pinfunction "C24_P$84") (pintype "bidirectional"))
    )
    (net (code "1444") (name "ZZ.07.086") (class "Default")
      (node (ref "U$12") (pin "P$114") (pinfunction "D24_P$114") (pintype "bidirectional"))
    )
    (net (code "1445") (name "ZZ.07.087") (class "Default")
      (node (ref "U$12") (pin "P$147") (pinfunction "E27_P$147") (pintype "bidirectional"))
    )
    (net (code "1446") (name "ZZ.07.088") (class "Default")
      (node (ref "U$12") (pin "P$176") (pinfunction "F26_P$176") (pintype "bidirectional"))
    )
    (net (code "1447") (name "ZZ.07.089") (class "Default")
      (node (ref "U$12") (pin "P$174") (pinfunction "F24_P$174") (pintype "bidirectional"))
    )
    (net (code "1448") (name "ZZ.07.090") (class "Default")
      (node (ref "U$12") (pin "P$177") (pinfunction "F27_P$177") (pintype "bidirectional"))
    )
    (net (code "1449") (name "ZZ.07.091") (class "Default")
      (node (ref "U$12") (pin "P$146") (pinfunction "E26_P$146") (pintype "bidirectional"))
    )
    (net (code "1450") (name "ZZ.07.092") (class "Default")
      (node (ref "U$12") (pin "P$86") (pinfunction "C26_P$86") (pintype "bidirectional"))
    )
    (net (code "1451") (name "ZZ.07.093") (class "Default")
      (node (ref "U$12") (pin "P$116") (pinfunction "D26_P$116") (pintype "bidirectional"))
    )
    (net (code "1452") (name "ZZ.07.094") (class "Default")
      (node (ref "U$12") (pin "P$148") (pinfunction "E28_P$148") (pintype "bidirectional"))
    )
    (net (code "1453") (name "ZZ.07.095") (class "Default")
      (node (ref "U$12") (pin "P$175") (pinfunction "F25_P$175") (pintype "bidirectional"))
    )
    (net (code "1454") (name "ZZ.07.096") (class "Default")
      (node (ref "U$14") (pin "P$55") (pinfunction "B25_P$55") (pintype "bidirectional"))
    )
    (net (code "1455") (name "ZZ.07.097") (class "Default")
      (node (ref "U$14") (pin "P$54") (pinfunction "B24_P$54") (pintype "bidirectional"))
    )
    (net (code "1456") (name "ZZ.07.098") (class "Default")
      (node (ref "U$14") (pin "P$84") (pinfunction "C24_P$84") (pintype "bidirectional"))
    )
    (net (code "1457") (name "ZZ.07.099") (class "Default")
      (node (ref "U$14") (pin "P$114") (pinfunction "D24_P$114") (pintype "bidirectional"))
    )
    (net (code "1458") (name "ZZ.07.100") (class "Default")
      (node (ref "U$14") (pin "P$147") (pinfunction "E27_P$147") (pintype "bidirectional"))
    )
    (net (code "1459") (name "ZZ.07.101") (class "Default")
      (node (ref "U$14") (pin "P$176") (pinfunction "F26_P$176") (pintype "bidirectional"))
    )
    (net (code "1460") (name "ZZ.07.102") (class "Default")
      (node (ref "U$14") (pin "P$174") (pinfunction "F24_P$174") (pintype "bidirectional"))
    )
    (net (code "1461") (name "ZZ.07.103") (class "Default")
      (node (ref "U$14") (pin "P$85") (pinfunction "C25_P$85") (pintype "bidirectional"))
    )
    (net (code "1462") (name "ZZ.07.104") (class "Default")
      (node (ref "U$14") (pin "P$115") (pinfunction "D25_P$115") (pintype "bidirectional"))
    )
    (net (code "1463") (name "ZZ.07.105") (class "Default")
      (node (ref "U$14") (pin "P$177") (pinfunction "F27_P$177") (pintype "bidirectional"))
    )
    (net (code "1464") (name "ZZ.07.106") (class "Default")
      (node (ref "U$14") (pin "P$146") (pinfunction "E26_P$146") (pintype "bidirectional"))
    )
    (net (code "1465") (name "ZZ.07.107") (class "Default")
      (node (ref "U$14") (pin "P$56") (pinfunction "B26_P$56") (pintype "bidirectional"))
    )
    (net (code "1466") (name "ZZ.07.108") (class "Default")
      (node (ref "U$14") (pin "P$86") (pinfunction "C26_P$86") (pintype "bidirectional"))
    )
    (net (code "1467") (name "ZZ.07.109") (class "Default")
      (node (ref "U$14") (pin "P$116") (pinfunction "D26_P$116") (pintype "bidirectional"))
    )
    (net (code "1468") (name "ZZ.07.110") (class "Default")
      (node (ref "U$14") (pin "P$148") (pinfunction "E28_P$148") (pintype "bidirectional"))
    )
    (net (code "1469") (name "ZZ.07.111") (class "Default")
      (node (ref "U$14") (pin "P$175") (pinfunction "F25_P$175") (pintype "bidirectional"))
    )
    (net (code "1470") (name "ZZ.07.112") (class "Default")
      (node (ref "U$16") (pin "P$54") (pinfunction "B24_P$54") (pintype "bidirectional"))
    )
    (net (code "1471") (name "ZZ.07.113") (class "Default")
      (node (ref "U$16") (pin "P$84") (pinfunction "C24_P$84") (pintype "bidirectional"))
    )
    (net (code "1472") (name "ZZ.07.114") (class "Default")
      (node (ref "U$16") (pin "P$114") (pinfunction "D24_P$114") (pintype "bidirectional"))
    )
    (net (code "1473") (name "ZZ.07.115") (class "Default")
      (node (ref "U$16") (pin "P$147") (pinfunction "E27_P$147") (pintype "bidirectional"))
    )
    (net (code "1474") (name "ZZ.07.116") (class "Default")
      (node (ref "U$16") (pin "P$176") (pinfunction "F26_P$176") (pintype "bidirectional"))
    )
    (net (code "1475") (name "ZZ.07.117") (class "Default")
      (node (ref "U$16") (pin "P$174") (pinfunction "F24_P$174") (pintype "bidirectional"))
    )
    (net (code "1476") (name "ZZ.07.118") (class "Default")
      (node (ref "U$16") (pin "P$55") (pinfunction "B25_P$55") (pintype "bidirectional"))
    )
    (net (code "1477") (name "ZZ.07.119") (class "Default")
      (node (ref "U$16") (pin "P$85") (pinfunction "C25_P$85") (pintype "bidirectional"))
    )
    (net (code "1478") (name "ZZ.07.120") (class "Default")
      (node (ref "U$16") (pin "P$115") (pinfunction "D25_P$115") (pintype "bidirectional"))
    )
    (net (code "1479") (name "ZZ.07.121") (class "Default")
      (node (ref "U$16") (pin "P$177") (pinfunction "F27_P$177") (pintype "bidirectional"))
    )
    (net (code "1480") (name "ZZ.07.122") (class "Default")
      (node (ref "U$16") (pin "P$146") (pinfunction "E26_P$146") (pintype "bidirectional"))
    )
    (net (code "1481") (name "ZZ.07.123") (class "Default")
      (node (ref "U$16") (pin "P$56") (pinfunction "B26_P$56") (pintype "bidirectional"))
    )
    (net (code "1482") (name "ZZ.07.124") (class "Default")
      (node (ref "U$16") (pin "P$86") (pinfunction "C26_P$86") (pintype "bidirectional"))
    )
    (net (code "1483") (name "ZZ.07.125") (class "Default")
      (node (ref "U$16") (pin "P$116") (pinfunction "D26_P$116") (pintype "bidirectional"))
    )
    (net (code "1484") (name "ZZ.07.126") (class "Default")
      (node (ref "U$16") (pin "P$148") (pinfunction "E28_P$148") (pintype "bidirectional"))
    )
    (net (code "1485") (name "ZZ.07.127") (class "Default")
      (node (ref "U$16") (pin "P$175") (pinfunction "F25_P$175") (pintype "bidirectional"))
    )
    (net (code "1486") (name "ZZ.07.128") (class "Default")
      (node (ref "U$18") (pin "P$54") (pinfunction "B24_P$54") (pintype "bidirectional"))
    )
    (net (code "1487") (name "ZZ.07.129") (class "Default")
      (node (ref "U$18") (pin "P$84") (pinfunction "C24_P$84") (pintype "bidirectional"))
    )
    (net (code "1488") (name "ZZ.07.130") (class "Default")
      (node (ref "U$18") (pin "P$114") (pinfunction "D24_P$114") (pintype "bidirectional"))
    )
    (net (code "1489") (name "ZZ.07.131") (class "Default")
      (node (ref "U$18") (pin "P$147") (pinfunction "E27_P$147") (pintype "bidirectional"))
    )
    (net (code "1490") (name "ZZ.07.132") (class "Default")
      (node (ref "U$18") (pin "P$176") (pinfunction "F26_P$176") (pintype "bidirectional"))
    )
    (net (code "1491") (name "ZZ.07.133") (class "Default")
      (node (ref "U$18") (pin "P$174") (pinfunction "F24_P$174") (pintype "bidirectional"))
    )
    (net (code "1492") (name "ZZ.07.134") (class "Default")
      (node (ref "U$18") (pin "P$55") (pinfunction "B25_P$55") (pintype "bidirectional"))
    )
    (net (code "1493") (name "ZZ.07.135") (class "Default")
      (node (ref "U$18") (pin "P$85") (pinfunction "C25_P$85") (pintype "bidirectional"))
    )
    (net (code "1494") (name "ZZ.07.136") (class "Default")
      (node (ref "U$18") (pin "P$115") (pinfunction "D25_P$115") (pintype "bidirectional"))
    )
    (net (code "1495") (name "ZZ.07.137") (class "Default")
      (node (ref "U$18") (pin "P$177") (pinfunction "F27_P$177") (pintype "bidirectional"))
    )
    (net (code "1496") (name "ZZ.07.138") (class "Default")
      (node (ref "U$18") (pin "P$146") (pinfunction "E26_P$146") (pintype "bidirectional"))
    )
    (net (code "1497") (name "ZZ.07.139") (class "Default")
      (node (ref "U$18") (pin "P$56") (pinfunction "B26_P$56") (pintype "bidirectional"))
    )
    (net (code "1498") (name "ZZ.07.140") (class "Default")
      (node (ref "U$18") (pin "P$86") (pinfunction "C26_P$86") (pintype "bidirectional"))
    )
    (net (code "1499") (name "ZZ.07.141") (class "Default")
      (node (ref "U$18") (pin "P$116") (pinfunction "D26_P$116") (pintype "bidirectional"))
    )
    (net (code "1500") (name "ZZ.07.142") (class "Default")
      (node (ref "U$18") (pin "P$148") (pinfunction "E28_P$148") (pintype "bidirectional"))
    )
    (net (code "1501") (name "ZZ.07.143") (class "Default")
      (node (ref "U$18") (pin "P$175") (pinfunction "F25_P$175") (pintype "bidirectional"))
    )
    (net (code "1502") (name "ZZ.07.144") (class "Default")
      (node (ref "U$20") (pin "P$54") (pinfunction "B24_P$54") (pintype "bidirectional"))
    )
    (net (code "1503") (name "ZZ.07.145") (class "Default")
      (node (ref "U$20") (pin "P$84") (pinfunction "C24_P$84") (pintype "bidirectional"))
    )
    (net (code "1504") (name "ZZ.07.146") (class "Default")
      (node (ref "U$20") (pin "P$114") (pinfunction "D24_P$114") (pintype "bidirectional"))
    )
    (net (code "1505") (name "ZZ.07.147") (class "Default")
      (node (ref "U$20") (pin "P$147") (pinfunction "E27_P$147") (pintype "bidirectional"))
    )
    (net (code "1506") (name "ZZ.07.148") (class "Default")
      (node (ref "U$20") (pin "P$176") (pinfunction "F26_P$176") (pintype "bidirectional"))
    )
    (net (code "1507") (name "ZZ.07.149") (class "Default")
      (node (ref "U$20") (pin "P$174") (pinfunction "F24_P$174") (pintype "bidirectional"))
    )
    (net (code "1508") (name "ZZ.07.150") (class "Default")
      (node (ref "U$20") (pin "P$55") (pinfunction "B25_P$55") (pintype "bidirectional"))
    )
    (net (code "1509") (name "ZZ.07.151") (class "Default")
      (node (ref "U$20") (pin "P$85") (pinfunction "C25_P$85") (pintype "bidirectional"))
    )
    (net (code "1510") (name "ZZ.07.152") (class "Default")
      (node (ref "U$20") (pin "P$115") (pinfunction "D25_P$115") (pintype "bidirectional"))
    )
    (net (code "1511") (name "ZZ.07.153") (class "Default")
      (node (ref "U$20") (pin "P$177") (pinfunction "F27_P$177") (pintype "bidirectional"))
    )
    (net (code "1512") (name "ZZ.07.154") (class "Default")
      (node (ref "U$20") (pin "P$146") (pinfunction "E26_P$146") (pintype "bidirectional"))
    )
    (net (code "1513") (name "ZZ.07.155") (class "Default")
      (node (ref "U$20") (pin "P$56") (pinfunction "B26_P$56") (pintype "bidirectional"))
    )
    (net (code "1514") (name "ZZ.07.156") (class "Default")
      (node (ref "U$20") (pin "P$86") (pinfunction "C26_P$86") (pintype "bidirectional"))
    )
    (net (code "1515") (name "ZZ.07.157") (class "Default")
      (node (ref "U$20") (pin "P$116") (pinfunction "D26_P$116") (pintype "bidirectional"))
    )
    (net (code "1516") (name "ZZ.07.158") (class "Default")
      (node (ref "U$20") (pin "P$148") (pinfunction "E28_P$148") (pintype "bidirectional"))
    )
    (net (code "1517") (name "ZZ.07.159") (class "Default")
      (node (ref "U$20") (pin "P$175") (pinfunction "F25_P$175") (pintype "bidirectional"))
    )
    (net (code "1518") (name "ZZ.07.160") (class "Default")
      (node (ref "U$22") (pin "P$54") (pinfunction "B24_P$54") (pintype "bidirectional"))
    )
    (net (code "1519") (name "ZZ.07.161") (class "Default")
      (node (ref "U$22") (pin "P$84") (pinfunction "C24_P$84") (pintype "bidirectional"))
    )
    (net (code "1520") (name "ZZ.07.162") (class "Default")
      (node (ref "U$22") (pin "P$114") (pinfunction "D24_P$114") (pintype "bidirectional"))
    )
    (net (code "1521") (name "ZZ.07.163") (class "Default")
      (node (ref "U$22") (pin "P$147") (pinfunction "E27_P$147") (pintype "bidirectional"))
    )
    (net (code "1522") (name "ZZ.07.164") (class "Default")
      (node (ref "U$22") (pin "P$176") (pinfunction "F26_P$176") (pintype "bidirectional"))
    )
    (net (code "1523") (name "ZZ.07.165") (class "Default")
      (node (ref "U$22") (pin "P$174") (pinfunction "F24_P$174") (pintype "bidirectional"))
    )
    (net (code "1524") (name "ZZ.07.166") (class "Default")
      (node (ref "U$22") (pin "P$55") (pinfunction "B25_P$55") (pintype "bidirectional"))
    )
    (net (code "1525") (name "ZZ.07.167") (class "Default")
      (node (ref "U$22") (pin "P$85") (pinfunction "C25_P$85") (pintype "bidirectional"))
    )
    (net (code "1526") (name "ZZ.07.168") (class "Default")
      (node (ref "U$22") (pin "P$115") (pinfunction "D25_P$115") (pintype "bidirectional"))
    )
    (net (code "1527") (name "ZZ.07.169") (class "Default")
      (node (ref "U$22") (pin "P$177") (pinfunction "F27_P$177") (pintype "bidirectional"))
    )
    (net (code "1528") (name "ZZ.07.170") (class "Default")
      (node (ref "U$22") (pin "P$146") (pinfunction "E26_P$146") (pintype "bidirectional"))
    )
    (net (code "1529") (name "ZZ.07.171") (class "Default")
      (node (ref "U$22") (pin "P$56") (pinfunction "B26_P$56") (pintype "bidirectional"))
    )
    (net (code "1530") (name "ZZ.07.172") (class "Default")
      (node (ref "U$22") (pin "P$86") (pinfunction "C26_P$86") (pintype "bidirectional"))
    )
    (net (code "1531") (name "ZZ.07.173") (class "Default")
      (node (ref "U$22") (pin "P$116") (pinfunction "D26_P$116") (pintype "bidirectional"))
    )
    (net (code "1532") (name "ZZ.07.174") (class "Default")
      (node (ref "U$22") (pin "P$148") (pinfunction "E28_P$148") (pintype "bidirectional"))
    )
    (net (code "1533") (name "ZZ.07.175") (class "Default")
      (node (ref "U$22") (pin "P$175") (pinfunction "F25_P$175") (pintype "bidirectional"))
    )
    (net (code "1534") (name "ZZ.07.176") (class "Default")
      (node (ref "U$24") (pin "P$54") (pinfunction "B24_P$54") (pintype "bidirectional"))
    )
    (net (code "1535") (name "ZZ.07.177") (class "Default")
      (node (ref "U$24") (pin "P$84") (pinfunction "C24_P$84") (pintype "bidirectional"))
    )
    (net (code "1536") (name "ZZ.07.178") (class "Default")
      (node (ref "U$24") (pin "P$114") (pinfunction "D24_P$114") (pintype "bidirectional"))
    )
    (net (code "1537") (name "ZZ.07.179") (class "Default")
      (node (ref "U$24") (pin "P$147") (pinfunction "E27_P$147") (pintype "bidirectional"))
    )
    (net (code "1538") (name "ZZ.07.180") (class "Default")
      (node (ref "U$24") (pin "P$176") (pinfunction "F26_P$176") (pintype "bidirectional"))
    )
    (net (code "1539") (name "ZZ.07.181") (class "Default")
      (node (ref "U$24") (pin "P$174") (pinfunction "F24_P$174") (pintype "bidirectional"))
    )
    (net (code "1540") (name "ZZ.07.182") (class "Default")
      (node (ref "U$24") (pin "P$55") (pinfunction "B25_P$55") (pintype "bidirectional"))
    )
    (net (code "1541") (name "ZZ.07.183") (class "Default")
      (node (ref "U$24") (pin "P$85") (pinfunction "C25_P$85") (pintype "bidirectional"))
    )
    (net (code "1542") (name "ZZ.07.184") (class "Default")
      (node (ref "U$24") (pin "P$115") (pinfunction "D25_P$115") (pintype "bidirectional"))
    )
    (net (code "1543") (name "ZZ.07.185") (class "Default")
      (node (ref "U$24") (pin "P$177") (pinfunction "F27_P$177") (pintype "bidirectional"))
    )
    (net (code "1544") (name "ZZ.07.186") (class "Default")
      (node (ref "U$24") (pin "P$146") (pinfunction "E26_P$146") (pintype "bidirectional"))
    )
    (net (code "1545") (name "ZZ.07.187") (class "Default")
      (node (ref "U$24") (pin "P$56") (pinfunction "B26_P$56") (pintype "bidirectional"))
    )
    (net (code "1546") (name "ZZ.07.188") (class "Default")
      (node (ref "U$24") (pin "P$86") (pinfunction "C26_P$86") (pintype "bidirectional"))
    )
    (net (code "1547") (name "ZZ.07.189") (class "Default")
      (node (ref "U$24") (pin "P$116") (pinfunction "D26_P$116") (pintype "bidirectional"))
    )
    (net (code "1548") (name "ZZ.07.190") (class "Default")
      (node (ref "U$24") (pin "P$148") (pinfunction "E28_P$148") (pintype "bidirectional"))
    )
    (net (code "1549") (name "ZZ.07.191") (class "Default")
      (node (ref "U$24") (pin "P$175") (pinfunction "F25_P$175") (pintype "bidirectional"))
    )
    (net (code "1550") (name "ZZ.08.000") (class "Default")
      (node (ref "U$1") (pin "P$35") (pinfunction "B5_P$35") (pintype "bidirectional"))
    )
    (net (code "1551") (name "ZZ.08.001") (class "Default")
      (node (ref "U$1") (pin "P$65") (pinfunction "C5_P$65") (pintype "bidirectional"))
    )
    (net (code "1552") (name "ZZ.08.002") (class "Default")
      (node (ref "U$1") (pin "P$95") (pinfunction "D5_P$95") (pintype "bidirectional"))
    )
    (net (code "1553") (name "ZZ.08.003") (class "Default")
      (node (ref "U$1") (pin "P$125") (pinfunction "E5_P$125") (pintype "bidirectional"))
    )
    (net (code "1554") (name "ZZ.08.004") (class "Default")
      (node (ref "U$1") (pin "P$155") (pinfunction "F5_P$155") (pintype "bidirectional"))
    )
    (net (code "1555") (name "ZZ.08.005") (class "Default")
      (node (ref "U$1") (pin "P$34") (pinfunction "B4_P$34") (pintype "bidirectional"))
    )
    (net (code "1556") (name "ZZ.08.006") (class "Default")
      (node (ref "U$1") (pin "P$64") (pinfunction "C4_P$64") (pintype "bidirectional"))
    )
    (net (code "1557") (name "ZZ.08.007") (class "Default")
      (node (ref "U$1") (pin "P$94") (pinfunction "D4_P$94") (pintype "bidirectional"))
    )
    (net (code "1558") (name "ZZ.08.008") (class "Default")
      (node (ref "U$1") (pin "P$124") (pinfunction "E4_P$124") (pintype "bidirectional"))
    )
    (net (code "1559") (name "ZZ.08.009") (class "Default")
      (node (ref "U$1") (pin "P$154") (pinfunction "F4_P$154") (pintype "bidirectional"))
    )
    (net (code "1560") (name "ZZ.08.010") (class "Default")
      (node (ref "U$1") (pin "P$33") (pinfunction "B3_P$33") (pintype "bidirectional"))
    )
    (net (code "1561") (name "ZZ.08.011") (class "Default")
      (node (ref "U$1") (pin "P$63") (pinfunction "C3_P$63") (pintype "bidirectional"))
    )
    (net (code "1562") (name "ZZ.08.012") (class "Default")
      (node (ref "U$1") (pin "P$93") (pinfunction "D3_P$93") (pintype "bidirectional"))
    )
    (net (code "1563") (name "ZZ.08.013") (class "Default")
      (node (ref "U$1") (pin "P$123") (pinfunction "E3_P$123") (pintype "bidirectional"))
    )
    (net (code "1564") (name "ZZ.08.014") (class "Default")
      (node (ref "U$1") (pin "P$153") (pinfunction "F3_P$153") (pintype "bidirectional"))
    )
    (net (code "1565") (name "ZZ.08.015") (class "Default")
      (node (ref "U$1") (pin "P$122") (pinfunction "E2_P$122") (pintype "bidirectional"))
    )
    (net (code "1566") (name "ZZ.08.016") (class "Default")
      (node (ref "U$3") (pin "P$35") (pinfunction "B5_P$35") (pintype "bidirectional"))
    )
    (net (code "1567") (name "ZZ.08.017") (class "Default")
      (node (ref "U$3") (pin "P$65") (pinfunction "C5_P$65") (pintype "bidirectional"))
    )
    (net (code "1568") (name "ZZ.08.018") (class "Default")
      (node (ref "U$3") (pin "P$95") (pinfunction "D5_P$95") (pintype "bidirectional"))
    )
    (net (code "1569") (name "ZZ.08.019") (class "Default")
      (node (ref "U$3") (pin "P$125") (pinfunction "E5_P$125") (pintype "bidirectional"))
    )
    (net (code "1570") (name "ZZ.08.020") (class "Default")
      (node (ref "U$3") (pin "P$155") (pinfunction "F5_P$155") (pintype "bidirectional"))
    )
    (net (code "1571") (name "ZZ.08.021") (class "Default")
      (node (ref "U$3") (pin "P$34") (pinfunction "B4_P$34") (pintype "bidirectional"))
    )
    (net (code "1572") (name "ZZ.08.022") (class "Default")
      (node (ref "U$3") (pin "P$64") (pinfunction "C4_P$64") (pintype "bidirectional"))
    )
    (net (code "1573") (name "ZZ.08.023") (class "Default")
      (node (ref "U$3") (pin "P$94") (pinfunction "D4_P$94") (pintype "bidirectional"))
    )
    (net (code "1574") (name "ZZ.08.024") (class "Default")
      (node (ref "U$3") (pin "P$124") (pinfunction "E4_P$124") (pintype "bidirectional"))
    )
    (net (code "1575") (name "ZZ.08.025") (class "Default")
      (node (ref "U$3") (pin "P$154") (pinfunction "F4_P$154") (pintype "bidirectional"))
    )
    (net (code "1576") (name "ZZ.08.026") (class "Default")
      (node (ref "U$3") (pin "P$33") (pinfunction "B3_P$33") (pintype "bidirectional"))
    )
    (net (code "1577") (name "ZZ.08.027") (class "Default")
      (node (ref "U$3") (pin "P$63") (pinfunction "C3_P$63") (pintype "bidirectional"))
    )
    (net (code "1578") (name "ZZ.08.028") (class "Default")
      (node (ref "U$3") (pin "P$93") (pinfunction "D3_P$93") (pintype "bidirectional"))
    )
    (net (code "1579") (name "ZZ.08.029") (class "Default")
      (node (ref "U$3") (pin "P$123") (pinfunction "E3_P$123") (pintype "bidirectional"))
    )
    (net (code "1580") (name "ZZ.08.030") (class "Default")
      (node (ref "U$3") (pin "P$153") (pinfunction "F3_P$153") (pintype "bidirectional"))
    )
    (net (code "1581") (name "ZZ.08.031") (class "Default")
      (node (ref "U$3") (pin "P$122") (pinfunction "E2_P$122") (pintype "bidirectional"))
    )
    (net (code "1582") (name "ZZ.08.032") (class "Default")
      (node (ref "U$5") (pin "P$35") (pinfunction "B5_P$35") (pintype "bidirectional"))
    )
    (net (code "1583") (name "ZZ.08.033") (class "Default")
      (node (ref "U$5") (pin "P$65") (pinfunction "C5_P$65") (pintype "bidirectional"))
    )
    (net (code "1584") (name "ZZ.08.034") (class "Default")
      (node (ref "U$5") (pin "P$95") (pinfunction "D5_P$95") (pintype "bidirectional"))
    )
    (net (code "1585") (name "ZZ.08.035") (class "Default")
      (node (ref "U$5") (pin "P$125") (pinfunction "E5_P$125") (pintype "bidirectional"))
    )
    (net (code "1586") (name "ZZ.08.036") (class "Default")
      (node (ref "U$5") (pin "P$155") (pinfunction "F5_P$155") (pintype "bidirectional"))
    )
    (net (code "1587") (name "ZZ.08.037") (class "Default")
      (node (ref "U$5") (pin "P$34") (pinfunction "B4_P$34") (pintype "bidirectional"))
    )
    (net (code "1588") (name "ZZ.08.038") (class "Default")
      (node (ref "U$5") (pin "P$64") (pinfunction "C4_P$64") (pintype "bidirectional"))
    )
    (net (code "1589") (name "ZZ.08.039") (class "Default")
      (node (ref "U$5") (pin "P$94") (pinfunction "D4_P$94") (pintype "bidirectional"))
    )
    (net (code "1590") (name "ZZ.08.040") (class "Default")
      (node (ref "U$5") (pin "P$124") (pinfunction "E4_P$124") (pintype "bidirectional"))
    )
    (net (code "1591") (name "ZZ.08.041") (class "Default")
      (node (ref "U$5") (pin "P$154") (pinfunction "F4_P$154") (pintype "bidirectional"))
    )
    (net (code "1592") (name "ZZ.08.042") (class "Default")
      (node (ref "U$5") (pin "P$33") (pinfunction "B3_P$33") (pintype "bidirectional"))
    )
    (net (code "1593") (name "ZZ.08.043") (class "Default")
      (node (ref "U$5") (pin "P$63") (pinfunction "C3_P$63") (pintype "bidirectional"))
    )
    (net (code "1594") (name "ZZ.08.044") (class "Default")
      (node (ref "U$5") (pin "P$93") (pinfunction "D3_P$93") (pintype "bidirectional"))
    )
    (net (code "1595") (name "ZZ.08.045") (class "Default")
      (node (ref "U$5") (pin "P$123") (pinfunction "E3_P$123") (pintype "bidirectional"))
    )
    (net (code "1596") (name "ZZ.08.046") (class "Default")
      (node (ref "U$5") (pin "P$153") (pinfunction "F3_P$153") (pintype "bidirectional"))
    )
    (net (code "1597") (name "ZZ.08.047") (class "Default")
      (node (ref "U$5") (pin "P$122") (pinfunction "E2_P$122") (pintype "bidirectional"))
    )
    (net (code "1598") (name "ZZ.08.048") (class "Default")
      (node (ref "U$7") (pin "P$35") (pinfunction "B5_P$35") (pintype "bidirectional"))
    )
    (net (code "1599") (name "ZZ.08.049") (class "Default")
      (node (ref "U$7") (pin "P$65") (pinfunction "C5_P$65") (pintype "bidirectional"))
    )
    (net (code "1600") (name "ZZ.08.050") (class "Default")
      (node (ref "U$7") (pin "P$95") (pinfunction "D5_P$95") (pintype "bidirectional"))
    )
    (net (code "1601") (name "ZZ.08.051") (class "Default")
      (node (ref "U$7") (pin "P$125") (pinfunction "E5_P$125") (pintype "bidirectional"))
    )
    (net (code "1602") (name "ZZ.08.052") (class "Default")
      (node (ref "U$7") (pin "P$155") (pinfunction "F5_P$155") (pintype "bidirectional"))
    )
    (net (code "1603") (name "ZZ.08.053") (class "Default")
      (node (ref "U$7") (pin "P$34") (pinfunction "B4_P$34") (pintype "bidirectional"))
    )
    (net (code "1604") (name "ZZ.08.054") (class "Default")
      (node (ref "U$7") (pin "P$64") (pinfunction "C4_P$64") (pintype "bidirectional"))
    )
    (net (code "1605") (name "ZZ.08.055") (class "Default")
      (node (ref "U$7") (pin "P$94") (pinfunction "D4_P$94") (pintype "bidirectional"))
    )
    (net (code "1606") (name "ZZ.08.056") (class "Default")
      (node (ref "U$7") (pin "P$33") (pinfunction "B3_P$33") (pintype "bidirectional"))
    )
    (net (code "1607") (name "ZZ.08.057") (class "Default")
      (node (ref "U$7") (pin "P$63") (pinfunction "C3_P$63") (pintype "bidirectional"))
    )
    (net (code "1608") (name "ZZ.08.058") (class "Default")
      (node (ref "U$7") (pin "P$93") (pinfunction "D3_P$93") (pintype "bidirectional"))
    )
    (net (code "1609") (name "ZZ.08.059") (class "Default")
      (node (ref "U$7") (pin "P$123") (pinfunction "E3_P$123") (pintype "bidirectional"))
    )
    (net (code "1610") (name "ZZ.08.060") (class "Default")
      (node (ref "U$7") (pin "P$153") (pinfunction "F3_P$153") (pintype "bidirectional"))
    )
    (net (code "1611") (name "ZZ.08.061") (class "Default")
      (node (ref "U$7") (pin "P$122") (pinfunction "E2_P$122") (pintype "bidirectional"))
    )
    (net (code "1612") (name "ZZ.08.062") (class "Default")
      (node (ref "U$7") (pin "P$124") (pinfunction "E4_P$124") (pintype "bidirectional"))
    )
    (net (code "1613") (name "ZZ.08.063") (class "Default")
      (node (ref "U$7") (pin "P$154") (pinfunction "F4_P$154") (pintype "bidirectional"))
    )
    (net (code "1614") (name "ZZ.08.064") (class "Default")
      (node (ref "U$9") (pin "P$35") (pinfunction "B5_P$35") (pintype "bidirectional"))
    )
    (net (code "1615") (name "ZZ.08.065") (class "Default")
      (node (ref "U$9") (pin "P$65") (pinfunction "C5_P$65") (pintype "bidirectional"))
    )
    (net (code "1616") (name "ZZ.08.066") (class "Default")
      (node (ref "U$9") (pin "P$95") (pinfunction "D5_P$95") (pintype "bidirectional"))
    )
    (net (code "1617") (name "ZZ.08.067") (class "Default")
      (node (ref "U$9") (pin "P$34") (pinfunction "B4_P$34") (pintype "bidirectional"))
    )
    (net (code "1618") (name "ZZ.08.068") (class "Default")
      (node (ref "U$9") (pin "P$64") (pinfunction "C4_P$64") (pintype "bidirectional"))
    )
    (net (code "1619") (name "ZZ.08.069") (class "Default")
      (node (ref "U$9") (pin "P$94") (pinfunction "D4_P$94") (pintype "bidirectional"))
    )
    (net (code "1620") (name "ZZ.08.070") (class "Default")
      (node (ref "U$9") (pin "P$33") (pinfunction "B3_P$33") (pintype "bidirectional"))
    )
    (net (code "1621") (name "ZZ.08.071") (class "Default")
      (node (ref "U$9") (pin "P$63") (pinfunction "C3_P$63") (pintype "bidirectional"))
    )
    (net (code "1622") (name "ZZ.08.072") (class "Default")
      (node (ref "U$9") (pin "P$93") (pinfunction "D3_P$93") (pintype "bidirectional"))
    )
    (net (code "1623") (name "ZZ.08.073") (class "Default")
      (node (ref "U$9") (pin "P$123") (pinfunction "E3_P$123") (pintype "bidirectional"))
    )
    (net (code "1624") (name "ZZ.08.074") (class "Default")
      (node (ref "U$9") (pin "P$153") (pinfunction "F3_P$153") (pintype "bidirectional"))
    )
    (net (code "1625") (name "ZZ.08.075") (class "Default")
      (node (ref "U$9") (pin "P$122") (pinfunction "E2_P$122") (pintype "bidirectional"))
    )
    (net (code "1626") (name "ZZ.08.076") (class "Default")
      (node (ref "U$9") (pin "P$124") (pinfunction "E4_P$124") (pintype "bidirectional"))
    )
    (net (code "1627") (name "ZZ.08.077") (class "Default")
      (node (ref "U$9") (pin "P$154") (pinfunction "F4_P$154") (pintype "bidirectional"))
    )
    (net (code "1628") (name "ZZ.08.078") (class "Default")
      (node (ref "U$9") (pin "P$125") (pinfunction "E5_P$125") (pintype "bidirectional"))
    )
    (net (code "1629") (name "ZZ.08.079") (class "Default")
      (node (ref "U$9") (pin "P$155") (pinfunction "F5_P$155") (pintype "bidirectional"))
    )
    (net (code "1630") (name "ZZ.08.080") (class "Default")
      (node (ref "U$11") (pin "P$34") (pinfunction "B4_P$34") (pintype "bidirectional"))
    )
    (net (code "1631") (name "ZZ.08.081") (class "Default")
      (node (ref "U$11") (pin "P$64") (pinfunction "C4_P$64") (pintype "bidirectional"))
    )
    (net (code "1632") (name "ZZ.08.082") (class "Default")
      (node (ref "U$11") (pin "P$94") (pinfunction "D4_P$94") (pintype "bidirectional"))
    )
    (net (code "1633") (name "ZZ.08.083") (class "Default")
      (node (ref "U$11") (pin "P$33") (pinfunction "B3_P$33") (pintype "bidirectional"))
    )
    (net (code "1634") (name "ZZ.08.084") (class "Default")
      (node (ref "U$11") (pin "P$63") (pinfunction "C3_P$63") (pintype "bidirectional"))
    )
    (net (code "1635") (name "ZZ.08.085") (class "Default")
      (node (ref "U$11") (pin "P$93") (pinfunction "D3_P$93") (pintype "bidirectional"))
    )
    (net (code "1636") (name "ZZ.08.086") (class "Default")
      (node (ref "U$11") (pin "P$123") (pinfunction "E3_P$123") (pintype "bidirectional"))
    )
    (net (code "1637") (name "ZZ.08.087") (class "Default")
      (node (ref "U$11") (pin "P$153") (pinfunction "F3_P$153") (pintype "bidirectional"))
    )
    (net (code "1638") (name "ZZ.08.088") (class "Default")
      (node (ref "U$11") (pin "P$122") (pinfunction "E2_P$122") (pintype "bidirectional"))
    )
    (net (code "1639") (name "ZZ.08.089") (class "Default")
      (node (ref "U$11") (pin "P$124") (pinfunction "E4_P$124") (pintype "bidirectional"))
    )
    (net (code "1640") (name "ZZ.08.090") (class "Default")
      (node (ref "U$11") (pin "P$154") (pinfunction "F4_P$154") (pintype "bidirectional"))
    )
    (net (code "1641") (name "ZZ.08.091") (class "Default")
      (node (ref "U$11") (pin "P$35") (pinfunction "B5_P$35") (pintype "bidirectional"))
    )
    (net (code "1642") (name "ZZ.08.092") (class "Default")
      (node (ref "U$11") (pin "P$65") (pinfunction "C5_P$65") (pintype "bidirectional"))
    )
    (net (code "1643") (name "ZZ.08.093") (class "Default")
      (node (ref "U$11") (pin "P$95") (pinfunction "D5_P$95") (pintype "bidirectional"))
    )
    (net (code "1644") (name "ZZ.08.094") (class "Default")
      (node (ref "U$11") (pin "P$125") (pinfunction "E5_P$125") (pintype "bidirectional"))
    )
    (net (code "1645") (name "ZZ.08.095") (class "Default")
      (node (ref "U$11") (pin "P$155") (pinfunction "F5_P$155") (pintype "bidirectional"))
    )
    (net (code "1646") (name "ZZ.08.096") (class "Default")
      (node (ref "U$13") (pin "P$34") (pinfunction "B4_P$34") (pintype "bidirectional"))
    )
    (net (code "1647") (name "ZZ.08.097") (class "Default")
      (node (ref "U$13") (pin "P$33") (pinfunction "B3_P$33") (pintype "bidirectional"))
    )
    (net (code "1648") (name "ZZ.08.098") (class "Default")
      (node (ref "U$13") (pin "P$63") (pinfunction "C3_P$63") (pintype "bidirectional"))
    )
    (net (code "1649") (name "ZZ.08.099") (class "Default")
      (node (ref "U$13") (pin "P$93") (pinfunction "D3_P$93") (pintype "bidirectional"))
    )
    (net (code "1650") (name "ZZ.08.100") (class "Default")
      (node (ref "U$13") (pin "P$123") (pinfunction "E3_P$123") (pintype "bidirectional"))
    )
    (net (code "1651") (name "ZZ.08.101") (class "Default")
      (node (ref "U$13") (pin "P$153") (pinfunction "F3_P$153") (pintype "bidirectional"))
    )
    (net (code "1652") (name "ZZ.08.102") (class "Default")
      (node (ref "U$13") (pin "P$122") (pinfunction "E2_P$122") (pintype "bidirectional"))
    )
    (net (code "1653") (name "ZZ.08.103") (class "Default")
      (node (ref "U$13") (pin "P$64") (pinfunction "C4_P$64") (pintype "bidirectional"))
    )
    (net (code "1654") (name "ZZ.08.104") (class "Default")
      (node (ref "U$13") (pin "P$94") (pinfunction "D4_P$94") (pintype "bidirectional"))
    )
    (net (code "1655") (name "ZZ.08.105") (class "Default")
      (node (ref "U$13") (pin "P$124") (pinfunction "E4_P$124") (pintype "bidirectional"))
    )
    (net (code "1656") (name "ZZ.08.106") (class "Default")
      (node (ref "U$13") (pin "P$154") (pinfunction "F4_P$154") (pintype "bidirectional"))
    )
    (net (code "1657") (name "ZZ.08.107") (class "Default")
      (node (ref "U$13") (pin "P$35") (pinfunction "B5_P$35") (pintype "bidirectional"))
    )
    (net (code "1658") (name "ZZ.08.108") (class "Default")
      (node (ref "U$13") (pin "P$65") (pinfunction "C5_P$65") (pintype "bidirectional"))
    )
    (net (code "1659") (name "ZZ.08.109") (class "Default")
      (node (ref "U$13") (pin "P$95") (pinfunction "D5_P$95") (pintype "bidirectional"))
    )
    (net (code "1660") (name "ZZ.08.110") (class "Default")
      (node (ref "U$13") (pin "P$125") (pinfunction "E5_P$125") (pintype "bidirectional"))
    )
    (net (code "1661") (name "ZZ.08.111") (class "Default")
      (node (ref "U$13") (pin "P$155") (pinfunction "F5_P$155") (pintype "bidirectional"))
    )
    (net (code "1662") (name "ZZ.08.112") (class "Default")
      (node (ref "U$15") (pin "P$33") (pinfunction "B3_P$33") (pintype "bidirectional"))
    )
    (net (code "1663") (name "ZZ.08.113") (class "Default")
      (node (ref "U$15") (pin "P$63") (pinfunction "C3_P$63") (pintype "bidirectional"))
    )
    (net (code "1664") (name "ZZ.08.114") (class "Default")
      (node (ref "U$15") (pin "P$93") (pinfunction "D3_P$93") (pintype "bidirectional"))
    )
    (net (code "1665") (name "ZZ.08.115") (class "Default")
      (node (ref "U$15") (pin "P$123") (pinfunction "E3_P$123") (pintype "bidirectional"))
    )
    (net (code "1666") (name "ZZ.08.116") (class "Default")
      (node (ref "U$15") (pin "P$153") (pinfunction "F3_P$153") (pintype "bidirectional"))
    )
    (net (code "1667") (name "ZZ.08.117") (class "Default")
      (node (ref "U$15") (pin "P$122") (pinfunction "E2_P$122") (pintype "bidirectional"))
    )
    (net (code "1668") (name "ZZ.08.118") (class "Default")
      (node (ref "U$15") (pin "P$34") (pinfunction "B4_P$34") (pintype "bidirectional"))
    )
    (net (code "1669") (name "ZZ.08.119") (class "Default")
      (node (ref "U$15") (pin "P$64") (pinfunction "C4_P$64") (pintype "bidirectional"))
    )
    (net (code "1670") (name "ZZ.08.120") (class "Default")
      (node (ref "U$15") (pin "P$94") (pinfunction "D4_P$94") (pintype "bidirectional"))
    )
    (net (code "1671") (name "ZZ.08.121") (class "Default")
      (node (ref "U$15") (pin "P$124") (pinfunction "E4_P$124") (pintype "bidirectional"))
    )
    (net (code "1672") (name "ZZ.08.122") (class "Default")
      (node (ref "U$15") (pin "P$154") (pinfunction "F4_P$154") (pintype "bidirectional"))
    )
    (net (code "1673") (name "ZZ.08.123") (class "Default")
      (node (ref "U$15") (pin "P$35") (pinfunction "B5_P$35") (pintype "bidirectional"))
    )
    (net (code "1674") (name "ZZ.08.124") (class "Default")
      (node (ref "U$15") (pin "P$65") (pinfunction "C5_P$65") (pintype "bidirectional"))
    )
    (net (code "1675") (name "ZZ.08.125") (class "Default")
      (node (ref "U$15") (pin "P$95") (pinfunction "D5_P$95") (pintype "bidirectional"))
    )
    (net (code "1676") (name "ZZ.08.126") (class "Default")
      (node (ref "U$15") (pin "P$125") (pinfunction "E5_P$125") (pintype "bidirectional"))
    )
    (net (code "1677") (name "ZZ.08.127") (class "Default")
      (node (ref "U$15") (pin "P$155") (pinfunction "F5_P$155") (pintype "bidirectional"))
    )
    (net (code "1678") (name "ZZ.08.128") (class "Default")
      (node (ref "U$17") (pin "P$33") (pinfunction "B3_P$33") (pintype "bidirectional"))
    )
    (net (code "1679") (name "ZZ.08.129") (class "Default")
      (node (ref "U$17") (pin "P$63") (pinfunction "C3_P$63") (pintype "bidirectional"))
    )
    (net (code "1680") (name "ZZ.08.130") (class "Default")
      (node (ref "U$17") (pin "P$93") (pinfunction "D3_P$93") (pintype "bidirectional"))
    )
    (net (code "1681") (name "ZZ.08.131") (class "Default")
      (node (ref "U$17") (pin "P$123") (pinfunction "E3_P$123") (pintype "bidirectional"))
    )
    (net (code "1682") (name "ZZ.08.132") (class "Default")
      (node (ref "U$17") (pin "P$153") (pinfunction "F3_P$153") (pintype "bidirectional"))
    )
    (net (code "1683") (name "ZZ.08.133") (class "Default")
      (node (ref "U$17") (pin "P$122") (pinfunction "E2_P$122") (pintype "bidirectional"))
    )
    (net (code "1684") (name "ZZ.08.134") (class "Default")
      (node (ref "U$17") (pin "P$34") (pinfunction "B4_P$34") (pintype "bidirectional"))
    )
    (net (code "1685") (name "ZZ.08.135") (class "Default")
      (node (ref "U$17") (pin "P$64") (pinfunction "C4_P$64") (pintype "bidirectional"))
    )
    (net (code "1686") (name "ZZ.08.136") (class "Default")
      (node (ref "U$17") (pin "P$94") (pinfunction "D4_P$94") (pintype "bidirectional"))
    )
    (net (code "1687") (name "ZZ.08.137") (class "Default")
      (node (ref "U$17") (pin "P$124") (pinfunction "E4_P$124") (pintype "bidirectional"))
    )
    (net (code "1688") (name "ZZ.08.138") (class "Default")
      (node (ref "U$17") (pin "P$154") (pinfunction "F4_P$154") (pintype "bidirectional"))
    )
    (net (code "1689") (name "ZZ.08.139") (class "Default")
      (node (ref "U$17") (pin "P$35") (pinfunction "B5_P$35") (pintype "bidirectional"))
    )
    (net (code "1690") (name "ZZ.08.140") (class "Default")
      (node (ref "U$17") (pin "P$65") (pinfunction "C5_P$65") (pintype "bidirectional"))
    )
    (net (code "1691") (name "ZZ.08.141") (class "Default")
      (node (ref "U$17") (pin "P$95") (pinfunction "D5_P$95") (pintype "bidirectional"))
    )
    (net (code "1692") (name "ZZ.08.142") (class "Default")
      (node (ref "U$17") (pin "P$125") (pinfunction "E5_P$125") (pintype "bidirectional"))
    )
    (net (code "1693") (name "ZZ.08.143") (class "Default")
      (node (ref "U$17") (pin "P$155") (pinfunction "F5_P$155") (pintype "bidirectional"))
    )
    (net (code "1694") (name "ZZ.08.144") (class "Default")
      (node (ref "U$19") (pin "P$33") (pinfunction "B3_P$33") (pintype "bidirectional"))
    )
    (net (code "1695") (name "ZZ.08.145") (class "Default")
      (node (ref "U$19") (pin "P$63") (pinfunction "C3_P$63") (pintype "bidirectional"))
    )
    (net (code "1696") (name "ZZ.08.146") (class "Default")
      (node (ref "U$19") (pin "P$93") (pinfunction "D3_P$93") (pintype "bidirectional"))
    )
    (net (code "1697") (name "ZZ.08.147") (class "Default")
      (node (ref "U$19") (pin "P$123") (pinfunction "E3_P$123") (pintype "bidirectional"))
    )
    (net (code "1698") (name "ZZ.08.148") (class "Default")
      (node (ref "U$19") (pin "P$153") (pinfunction "F3_P$153") (pintype "bidirectional"))
    )
    (net (code "1699") (name "ZZ.08.149") (class "Default")
      (node (ref "U$19") (pin "P$122") (pinfunction "E2_P$122") (pintype "bidirectional"))
    )
    (net (code "1700") (name "ZZ.08.150") (class "Default")
      (node (ref "U$19") (pin "P$34") (pinfunction "B4_P$34") (pintype "bidirectional"))
    )
    (net (code "1701") (name "ZZ.08.151") (class "Default")
      (node (ref "U$19") (pin "P$64") (pinfunction "C4_P$64") (pintype "bidirectional"))
    )
    (net (code "1702") (name "ZZ.08.152") (class "Default")
      (node (ref "U$19") (pin "P$94") (pinfunction "D4_P$94") (pintype "bidirectional"))
    )
    (net (code "1703") (name "ZZ.08.153") (class "Default")
      (node (ref "U$19") (pin "P$124") (pinfunction "E4_P$124") (pintype "bidirectional"))
    )
    (net (code "1704") (name "ZZ.08.154") (class "Default")
      (node (ref "U$19") (pin "P$154") (pinfunction "F4_P$154") (pintype "bidirectional"))
    )
    (net (code "1705") (name "ZZ.08.155") (class "Default")
      (node (ref "U$19") (pin "P$35") (pinfunction "B5_P$35") (pintype "bidirectional"))
    )
    (net (code "1706") (name "ZZ.08.156") (class "Default")
      (node (ref "U$19") (pin "P$65") (pinfunction "C5_P$65") (pintype "bidirectional"))
    )
    (net (code "1707") (name "ZZ.08.157") (class "Default")
      (node (ref "U$19") (pin "P$95") (pinfunction "D5_P$95") (pintype "bidirectional"))
    )
    (net (code "1708") (name "ZZ.08.158") (class "Default")
      (node (ref "U$19") (pin "P$125") (pinfunction "E5_P$125") (pintype "bidirectional"))
    )
    (net (code "1709") (name "ZZ.08.159") (class "Default")
      (node (ref "U$19") (pin "P$155") (pinfunction "F5_P$155") (pintype "bidirectional"))
    )
    (net (code "1710") (name "ZZ.08.160") (class "Default")
      (node (ref "U$21") (pin "P$33") (pinfunction "B3_P$33") (pintype "bidirectional"))
    )
    (net (code "1711") (name "ZZ.08.161") (class "Default")
      (node (ref "U$21") (pin "P$63") (pinfunction "C3_P$63") (pintype "bidirectional"))
    )
    (net (code "1712") (name "ZZ.08.162") (class "Default")
      (node (ref "U$21") (pin "P$93") (pinfunction "D3_P$93") (pintype "bidirectional"))
    )
    (net (code "1713") (name "ZZ.08.163") (class "Default")
      (node (ref "U$21") (pin "P$123") (pinfunction "E3_P$123") (pintype "bidirectional"))
    )
    (net (code "1714") (name "ZZ.08.164") (class "Default")
      (node (ref "U$21") (pin "P$153") (pinfunction "F3_P$153") (pintype "bidirectional"))
    )
    (net (code "1715") (name "ZZ.08.165") (class "Default")
      (node (ref "U$21") (pin "P$122") (pinfunction "E2_P$122") (pintype "bidirectional"))
    )
    (net (code "1716") (name "ZZ.08.166") (class "Default")
      (node (ref "U$21") (pin "P$34") (pinfunction "B4_P$34") (pintype "bidirectional"))
    )
    (net (code "1717") (name "ZZ.08.167") (class "Default")
      (node (ref "U$21") (pin "P$64") (pinfunction "C4_P$64") (pintype "bidirectional"))
    )
    (net (code "1718") (name "ZZ.08.168") (class "Default")
      (node (ref "U$21") (pin "P$94") (pinfunction "D4_P$94") (pintype "bidirectional"))
    )
    (net (code "1719") (name "ZZ.08.169") (class "Default")
      (node (ref "U$21") (pin "P$124") (pinfunction "E4_P$124") (pintype "bidirectional"))
    )
    (net (code "1720") (name "ZZ.08.170") (class "Default")
      (node (ref "U$21") (pin "P$154") (pinfunction "F4_P$154") (pintype "bidirectional"))
    )
    (net (code "1721") (name "ZZ.08.171") (class "Default")
      (node (ref "U$21") (pin "P$35") (pinfunction "B5_P$35") (pintype "bidirectional"))
    )
    (net (code "1722") (name "ZZ.08.172") (class "Default")
      (node (ref "U$21") (pin "P$65") (pinfunction "C5_P$65") (pintype "bidirectional"))
    )
    (net (code "1723") (name "ZZ.08.173") (class "Default")
      (node (ref "U$21") (pin "P$95") (pinfunction "D5_P$95") (pintype "bidirectional"))
    )
    (net (code "1724") (name "ZZ.08.174") (class "Default")
      (node (ref "U$21") (pin "P$125") (pinfunction "E5_P$125") (pintype "bidirectional"))
    )
    (net (code "1725") (name "ZZ.08.175") (class "Default")
      (node (ref "U$21") (pin "P$155") (pinfunction "F5_P$155") (pintype "bidirectional"))
    )
    (net (code "1726") (name "ZZ.08.176") (class "Default")
      (node (ref "U$23") (pin "P$33") (pinfunction "B3_P$33") (pintype "bidirectional"))
    )
    (net (code "1727") (name "ZZ.08.177") (class "Default")
      (node (ref "U$23") (pin "P$63") (pinfunction "C3_P$63") (pintype "bidirectional"))
    )
    (net (code "1728") (name "ZZ.08.178") (class "Default")
      (node (ref "U$23") (pin "P$93") (pinfunction "D3_P$93") (pintype "bidirectional"))
    )
    (net (code "1729") (name "ZZ.08.179") (class "Default")
      (node (ref "U$23") (pin "P$123") (pinfunction "E3_P$123") (pintype "bidirectional"))
    )
    (net (code "1730") (name "ZZ.08.180") (class "Default")
      (node (ref "U$23") (pin "P$153") (pinfunction "F3_P$153") (pintype "bidirectional"))
    )
    (net (code "1731") (name "ZZ.08.181") (class "Default")
      (node (ref "U$23") (pin "P$122") (pinfunction "E2_P$122") (pintype "bidirectional"))
    )
    (net (code "1732") (name "ZZ.08.182") (class "Default")
      (node (ref "U$23") (pin "P$34") (pinfunction "B4_P$34") (pintype "bidirectional"))
    )
    (net (code "1733") (name "ZZ.08.183") (class "Default")
      (node (ref "U$23") (pin "P$64") (pinfunction "C4_P$64") (pintype "bidirectional"))
    )
    (net (code "1734") (name "ZZ.08.184") (class "Default")
      (node (ref "U$23") (pin "P$94") (pinfunction "D4_P$94") (pintype "bidirectional"))
    )
    (net (code "1735") (name "ZZ.08.185") (class "Default")
      (node (ref "U$23") (pin "P$124") (pinfunction "E4_P$124") (pintype "bidirectional"))
    )
    (net (code "1736") (name "ZZ.08.186") (class "Default")
      (node (ref "U$23") (pin "P$154") (pinfunction "F4_P$154") (pintype "bidirectional"))
    )
    (net (code "1737") (name "ZZ.08.187") (class "Default")
      (node (ref "U$23") (pin "P$35") (pinfunction "B5_P$35") (pintype "bidirectional"))
    )
    (net (code "1738") (name "ZZ.08.188") (class "Default")
      (node (ref "U$23") (pin "P$65") (pinfunction "C5_P$65") (pintype "bidirectional"))
    )
    (net (code "1739") (name "ZZ.08.189") (class "Default")
      (node (ref "U$23") (pin "P$95") (pinfunction "D5_P$95") (pintype "bidirectional"))
    )
    (net (code "1740") (name "ZZ.08.190") (class "Default")
      (node (ref "U$23") (pin "P$125") (pinfunction "E5_P$125") (pintype "bidirectional"))
    )
    (net (code "1741") (name "ZZ.08.191") (class "Default")
      (node (ref "U$23") (pin "P$155") (pinfunction "F5_P$155") (pintype "bidirectional"))
    )
    (net (code "1742") (name "ZZ.09.000") (class "Default")
      (node (ref "U$1") (pin "P$36") (pinfunction "B6_P$36") (pintype "bidirectional"))
    )
    (net (code "1743") (name "ZZ.09.001") (class "Default")
      (node (ref "U$1") (pin "P$66") (pinfunction "C6_P$66") (pintype "bidirectional"))
    )
    (net (code "1744") (name "ZZ.09.002") (class "Default")
      (node (ref "U$1") (pin "P$96") (pinfunction "D6_P$96") (pintype "bidirectional"))
    )
    (net (code "1745") (name "ZZ.09.003") (class "Default")
      (node (ref "U$1") (pin "P$126") (pinfunction "E6_P$126") (pintype "bidirectional"))
    )
    (net (code "1746") (name "ZZ.09.004") (class "Default")
      (node (ref "U$1") (pin "P$156") (pinfunction "F6_P$156") (pintype "bidirectional"))
    )
    (net (code "1747") (name "ZZ.09.005") (class "Default")
      (node (ref "U$1") (pin "P$152") (pinfunction "F2_P$152") (pintype "bidirectional"))
    )
    (net (code "1748") (name "ZZ.09.006") (class "Default")
      (node (ref "U$1") (pin "P$37") (pinfunction "B7_P$37") (pintype "bidirectional"))
    )
    (net (code "1749") (name "ZZ.09.007") (class "Default")
      (node (ref "U$1") (pin "P$67") (pinfunction "C7_P$67") (pintype "bidirectional"))
    )
    (net (code "1750") (name "ZZ.09.008") (class "Default")
      (node (ref "U$1") (pin "P$97") (pinfunction "D7_P$97") (pintype "bidirectional"))
    )
    (net (code "1751") (name "ZZ.09.009") (class "Default")
      (node (ref "U$1") (pin "P$127") (pinfunction "E7_P$127") (pintype "bidirectional"))
    )
    (net (code "1752") (name "ZZ.09.010") (class "Default")
      (node (ref "U$1") (pin "P$157") (pinfunction "F7_P$157") (pintype "bidirectional"))
    )
    (net (code "1753") (name "ZZ.09.011") (class "Default")
      (node (ref "U$1") (pin "P$38") (pinfunction "B8_P$38") (pintype "bidirectional"))
    )
    (net (code "1754") (name "ZZ.09.012") (class "Default")
      (node (ref "U$1") (pin "P$68") (pinfunction "C8_P$68") (pintype "bidirectional"))
    )
    (net (code "1755") (name "ZZ.09.013") (class "Default")
      (node (ref "U$1") (pin "P$98") (pinfunction "D8_P$98") (pintype "bidirectional"))
    )
    (net (code "1756") (name "ZZ.09.014") (class "Default")
      (node (ref "U$1") (pin "P$128") (pinfunction "E8_P$128") (pintype "bidirectional"))
    )
    (net (code "1757") (name "ZZ.09.015") (class "Default")
      (node (ref "U$1") (pin "P$158") (pinfunction "F8_P$158") (pintype "bidirectional"))
    )
    (net (code "1758") (name "ZZ.09.016") (class "Default")
      (node (ref "U$3") (pin "P$36") (pinfunction "B6_P$36") (pintype "bidirectional"))
    )
    (net (code "1759") (name "ZZ.09.017") (class "Default")
      (node (ref "U$3") (pin "P$66") (pinfunction "C6_P$66") (pintype "bidirectional"))
    )
    (net (code "1760") (name "ZZ.09.018") (class "Default")
      (node (ref "U$3") (pin "P$96") (pinfunction "D6_P$96") (pintype "bidirectional"))
    )
    (net (code "1761") (name "ZZ.09.019") (class "Default")
      (node (ref "U$3") (pin "P$126") (pinfunction "E6_P$126") (pintype "bidirectional"))
    )
    (net (code "1762") (name "ZZ.09.020") (class "Default")
      (node (ref "U$3") (pin "P$156") (pinfunction "F6_P$156") (pintype "bidirectional"))
    )
    (net (code "1763") (name "ZZ.09.021") (class "Default")
      (node (ref "U$3") (pin "P$152") (pinfunction "F2_P$152") (pintype "bidirectional"))
    )
    (net (code "1764") (name "ZZ.09.022") (class "Default")
      (node (ref "U$3") (pin "P$37") (pinfunction "B7_P$37") (pintype "bidirectional"))
    )
    (net (code "1765") (name "ZZ.09.023") (class "Default")
      (node (ref "U$3") (pin "P$67") (pinfunction "C7_P$67") (pintype "bidirectional"))
    )
    (net (code "1766") (name "ZZ.09.024") (class "Default")
      (node (ref "U$3") (pin "P$97") (pinfunction "D7_P$97") (pintype "bidirectional"))
    )
    (net (code "1767") (name "ZZ.09.025") (class "Default")
      (node (ref "U$3") (pin "P$127") (pinfunction "E7_P$127") (pintype "bidirectional"))
    )
    (net (code "1768") (name "ZZ.09.026") (class "Default")
      (node (ref "U$3") (pin "P$157") (pinfunction "F7_P$157") (pintype "bidirectional"))
    )
    (net (code "1769") (name "ZZ.09.027") (class "Default")
      (node (ref "U$3") (pin "P$38") (pinfunction "B8_P$38") (pintype "bidirectional"))
    )
    (net (code "1770") (name "ZZ.09.028") (class "Default")
      (node (ref "U$3") (pin "P$68") (pinfunction "C8_P$68") (pintype "bidirectional"))
    )
    (net (code "1771") (name "ZZ.09.029") (class "Default")
      (node (ref "U$3") (pin "P$98") (pinfunction "D8_P$98") (pintype "bidirectional"))
    )
    (net (code "1772") (name "ZZ.09.030") (class "Default")
      (node (ref "U$3") (pin "P$128") (pinfunction "E8_P$128") (pintype "bidirectional"))
    )
    (net (code "1773") (name "ZZ.09.031") (class "Default")
      (node (ref "U$3") (pin "P$158") (pinfunction "F8_P$158") (pintype "bidirectional"))
    )
    (net (code "1774") (name "ZZ.09.032") (class "Default")
      (node (ref "U$5") (pin "P$36") (pinfunction "B6_P$36") (pintype "bidirectional"))
    )
    (net (code "1775") (name "ZZ.09.033") (class "Default")
      (node (ref "U$5") (pin "P$66") (pinfunction "C6_P$66") (pintype "bidirectional"))
    )
    (net (code "1776") (name "ZZ.09.034") (class "Default")
      (node (ref "U$5") (pin "P$96") (pinfunction "D6_P$96") (pintype "bidirectional"))
    )
    (net (code "1777") (name "ZZ.09.035") (class "Default")
      (node (ref "U$5") (pin "P$126") (pinfunction "E6_P$126") (pintype "bidirectional"))
    )
    (net (code "1778") (name "ZZ.09.036") (class "Default")
      (node (ref "U$5") (pin "P$156") (pinfunction "F6_P$156") (pintype "bidirectional"))
    )
    (net (code "1779") (name "ZZ.09.037") (class "Default")
      (node (ref "U$5") (pin "P$152") (pinfunction "F2_P$152") (pintype "bidirectional"))
    )
    (net (code "1780") (name "ZZ.09.038") (class "Default")
      (node (ref "U$5") (pin "P$37") (pinfunction "B7_P$37") (pintype "bidirectional"))
    )
    (net (code "1781") (name "ZZ.09.039") (class "Default")
      (node (ref "U$5") (pin "P$67") (pinfunction "C7_P$67") (pintype "bidirectional"))
    )
    (net (code "1782") (name "ZZ.09.040") (class "Default")
      (node (ref "U$5") (pin "P$97") (pinfunction "D7_P$97") (pintype "bidirectional"))
    )
    (net (code "1783") (name "ZZ.09.041") (class "Default")
      (node (ref "U$5") (pin "P$127") (pinfunction "E7_P$127") (pintype "bidirectional"))
    )
    (net (code "1784") (name "ZZ.09.042") (class "Default")
      (node (ref "U$5") (pin "P$38") (pinfunction "B8_P$38") (pintype "bidirectional"))
    )
    (net (code "1785") (name "ZZ.09.043") (class "Default")
      (node (ref "U$5") (pin "P$68") (pinfunction "C8_P$68") (pintype "bidirectional"))
    )
    (net (code "1786") (name "ZZ.09.044") (class "Default")
      (node (ref "U$5") (pin "P$98") (pinfunction "D8_P$98") (pintype "bidirectional"))
    )
    (net (code "1787") (name "ZZ.09.045") (class "Default")
      (node (ref "U$5") (pin "P$128") (pinfunction "E8_P$128") (pintype "bidirectional"))
    )
    (net (code "1788") (name "ZZ.09.046") (class "Default")
      (node (ref "U$5") (pin "P$158") (pinfunction "F8_P$158") (pintype "bidirectional"))
    )
    (net (code "1789") (name "ZZ.09.047") (class "Default")
      (node (ref "U$5") (pin "P$157") (pinfunction "F7_P$157") (pintype "bidirectional"))
    )
    (net (code "1790") (name "ZZ.09.048") (class "Default")
      (node (ref "U$7") (pin "P$36") (pinfunction "B6_P$36") (pintype "bidirectional"))
    )
    (net (code "1791") (name "ZZ.09.049") (class "Default")
      (node (ref "U$7") (pin "P$66") (pinfunction "C6_P$66") (pintype "bidirectional"))
    )
    (net (code "1792") (name "ZZ.09.050") (class "Default")
      (node (ref "U$7") (pin "P$96") (pinfunction "D6_P$96") (pintype "bidirectional"))
    )
    (net (code "1793") (name "ZZ.09.051") (class "Default")
      (node (ref "U$7") (pin "P$126") (pinfunction "E6_P$126") (pintype "bidirectional"))
    )
    (net (code "1794") (name "ZZ.09.052") (class "Default")
      (node (ref "U$7") (pin "P$156") (pinfunction "F6_P$156") (pintype "bidirectional"))
    )
    (net (code "1795") (name "ZZ.09.053") (class "Default")
      (node (ref "U$7") (pin "P$152") (pinfunction "F2_P$152") (pintype "bidirectional"))
    )
    (net (code "1796") (name "ZZ.09.054") (class "Default")
      (node (ref "U$7") (pin "P$37") (pinfunction "B7_P$37") (pintype "bidirectional"))
    )
    (net (code "1797") (name "ZZ.09.055") (class "Default")
      (node (ref "U$7") (pin "P$67") (pinfunction "C7_P$67") (pintype "bidirectional"))
    )
    (net (code "1798") (name "ZZ.09.056") (class "Default")
      (node (ref "U$7") (pin "P$38") (pinfunction "B8_P$38") (pintype "bidirectional"))
    )
    (net (code "1799") (name "ZZ.09.057") (class "Default")
      (node (ref "U$7") (pin "P$68") (pinfunction "C8_P$68") (pintype "bidirectional"))
    )
    (net (code "1800") (name "ZZ.09.058") (class "Default")
      (node (ref "U$7") (pin "P$98") (pinfunction "D8_P$98") (pintype "bidirectional"))
    )
    (net (code "1801") (name "ZZ.09.059") (class "Default")
      (node (ref "U$7") (pin "P$128") (pinfunction "E8_P$128") (pintype "bidirectional"))
    )
    (net (code "1802") (name "ZZ.09.060") (class "Default")
      (node (ref "U$7") (pin "P$158") (pinfunction "F8_P$158") (pintype "bidirectional"))
    )
    (net (code "1803") (name "ZZ.09.061") (class "Default")
      (node (ref "U$7") (pin "P$97") (pinfunction "D7_P$97") (pintype "bidirectional"))
    )
    (net (code "1804") (name "ZZ.09.062") (class "Default")
      (node (ref "U$7") (pin "P$127") (pinfunction "E7_P$127") (pintype "bidirectional"))
    )
    (net (code "1805") (name "ZZ.09.063") (class "Default")
      (node (ref "U$7") (pin "P$157") (pinfunction "F7_P$157") (pintype "bidirectional"))
    )
    (net (code "1806") (name "ZZ.09.064") (class "Default")
      (node (ref "U$9") (pin "P$36") (pinfunction "B6_P$36") (pintype "bidirectional"))
    )
    (net (code "1807") (name "ZZ.09.065") (class "Default")
      (node (ref "U$9") (pin "P$66") (pinfunction "C6_P$66") (pintype "bidirectional"))
    )
    (net (code "1808") (name "ZZ.09.066") (class "Default")
      (node (ref "U$9") (pin "P$96") (pinfunction "D6_P$96") (pintype "bidirectional"))
    )
    (net (code "1809") (name "ZZ.09.067") (class "Default")
      (node (ref "U$9") (pin "P$126") (pinfunction "E6_P$126") (pintype "bidirectional"))
    )
    (net (code "1810") (name "ZZ.09.068") (class "Default")
      (node (ref "U$9") (pin "P$37") (pinfunction "B7_P$37") (pintype "bidirectional"))
    )
    (net (code "1811") (name "ZZ.09.069") (class "Default")
      (node (ref "U$9") (pin "P$67") (pinfunction "C7_P$67") (pintype "bidirectional"))
    )
    (net (code "1812") (name "ZZ.09.070") (class "Default")
      (node (ref "U$9") (pin "P$38") (pinfunction "B8_P$38") (pintype "bidirectional"))
    )
    (net (code "1813") (name "ZZ.09.071") (class "Default")
      (node (ref "U$9") (pin "P$68") (pinfunction "C8_P$68") (pintype "bidirectional"))
    )
    (net (code "1814") (name "ZZ.09.072") (class "Default")
      (node (ref "U$9") (pin "P$98") (pinfunction "D8_P$98") (pintype "bidirectional"))
    )
    (net (code "1815") (name "ZZ.09.073") (class "Default")
      (node (ref "U$9") (pin "P$128") (pinfunction "E8_P$128") (pintype "bidirectional"))
    )
    (net (code "1816") (name "ZZ.09.074") (class "Default")
      (node (ref "U$9") (pin "P$158") (pinfunction "F8_P$158") (pintype "bidirectional"))
    )
    (net (code "1817") (name "ZZ.09.075") (class "Default")
      (node (ref "U$9") (pin "P$97") (pinfunction "D7_P$97") (pintype "bidirectional"))
    )
    (net (code "1818") (name "ZZ.09.076") (class "Default")
      (node (ref "U$9") (pin "P$127") (pinfunction "E7_P$127") (pintype "bidirectional"))
    )
    (net (code "1819") (name "ZZ.09.077") (class "Default")
      (node (ref "U$9") (pin "P$157") (pinfunction "F7_P$157") (pintype "bidirectional"))
    )
    (net (code "1820") (name "ZZ.09.078") (class "Default")
      (node (ref "U$9") (pin "P$156") (pinfunction "F6_P$156") (pintype "bidirectional"))
    )
    (net (code "1821") (name "ZZ.09.079") (class "Default")
      (node (ref "U$9") (pin "P$152") (pinfunction "F2_P$152") (pintype "bidirectional"))
    )
    (net (code "1822") (name "ZZ.09.080") (class "Default")
      (node (ref "U$11") (pin "P$36") (pinfunction "B6_P$36") (pintype "bidirectional"))
    )
    (net (code "1823") (name "ZZ.09.081") (class "Default")
      (node (ref "U$11") (pin "P$37") (pinfunction "B7_P$37") (pintype "bidirectional"))
    )
    (net (code "1824") (name "ZZ.09.082") (class "Default")
      (node (ref "U$11") (pin "P$67") (pinfunction "C7_P$67") (pintype "bidirectional"))
    )
    (net (code "1825") (name "ZZ.09.083") (class "Default")
      (node (ref "U$11") (pin "P$38") (pinfunction "B8_P$38") (pintype "bidirectional"))
    )
    (net (code "1826") (name "ZZ.09.084") (class "Default")
      (node (ref "U$11") (pin "P$68") (pinfunction "C8_P$68") (pintype "bidirectional"))
    )
    (net (code "1827") (name "ZZ.09.085") (class "Default")
      (node (ref "U$11") (pin "P$98") (pinfunction "D8_P$98") (pintype "bidirectional"))
    )
    (net (code "1828") (name "ZZ.09.086") (class "Default")
      (node (ref "U$11") (pin "P$128") (pinfunction "E8_P$128") (pintype "bidirectional"))
    )
    (net (code "1829") (name "ZZ.09.087") (class "Default")
      (node (ref "U$11") (pin "P$158") (pinfunction "F8_P$158") (pintype "bidirectional"))
    )
    (net (code "1830") (name "ZZ.09.088") (class "Default")
      (node (ref "U$11") (pin "P$97") (pinfunction "D7_P$97") (pintype "bidirectional"))
    )
    (net (code "1831") (name "ZZ.09.089") (class "Default")
      (node (ref "U$11") (pin "P$127") (pinfunction "E7_P$127") (pintype "bidirectional"))
    )
    (net (code "1832") (name "ZZ.09.090") (class "Default")
      (node (ref "U$11") (pin "P$157") (pinfunction "F7_P$157") (pintype "bidirectional"))
    )
    (net (code "1833") (name "ZZ.09.091") (class "Default")
      (node (ref "U$11") (pin "P$66") (pinfunction "C6_P$66") (pintype "bidirectional"))
    )
    (net (code "1834") (name "ZZ.09.092") (class "Default")
      (node (ref "U$11") (pin "P$96") (pinfunction "D6_P$96") (pintype "bidirectional"))
    )
    (net (code "1835") (name "ZZ.09.093") (class "Default")
      (node (ref "U$11") (pin "P$126") (pinfunction "E6_P$126") (pintype "bidirectional"))
    )
    (net (code "1836") (name "ZZ.09.094") (class "Default")
      (node (ref "U$11") (pin "P$156") (pinfunction "F6_P$156") (pintype "bidirectional"))
    )
    (net (code "1837") (name "ZZ.09.095") (class "Default")
      (node (ref "U$11") (pin "P$152") (pinfunction "F2_P$152") (pintype "bidirectional"))
    )
    (net (code "1838") (name "ZZ.09.096") (class "Default")
      (node (ref "U$13") (pin "P$37") (pinfunction "B7_P$37") (pintype "bidirectional"))
    )
    (net (code "1839") (name "ZZ.09.097") (class "Default")
      (node (ref "U$13") (pin "P$38") (pinfunction "B8_P$38") (pintype "bidirectional"))
    )
    (net (code "1840") (name "ZZ.09.098") (class "Default")
      (node (ref "U$13") (pin "P$68") (pinfunction "C8_P$68") (pintype "bidirectional"))
    )
    (net (code "1841") (name "ZZ.09.099") (class "Default")
      (node (ref "U$13") (pin "P$98") (pinfunction "D8_P$98") (pintype "bidirectional"))
    )
    (net (code "1842") (name "ZZ.09.100") (class "Default")
      (node (ref "U$13") (pin "P$128") (pinfunction "E8_P$128") (pintype "bidirectional"))
    )
    (net (code "1843") (name "ZZ.09.101") (class "Default")
      (node (ref "U$13") (pin "P$158") (pinfunction "F8_P$158") (pintype "bidirectional"))
    )
    (net (code "1844") (name "ZZ.09.102") (class "Default")
      (node (ref "U$13") (pin "P$67") (pinfunction "C7_P$67") (pintype "bidirectional"))
    )
    (net (code "1845") (name "ZZ.09.103") (class "Default")
      (node (ref "U$13") (pin "P$97") (pinfunction "D7_P$97") (pintype "bidirectional"))
    )
    (net (code "1846") (name "ZZ.09.104") (class "Default")
      (node (ref "U$13") (pin "P$127") (pinfunction "E7_P$127") (pintype "bidirectional"))
    )
    (net (code "1847") (name "ZZ.09.105") (class "Default")
      (node (ref "U$13") (pin "P$157") (pinfunction "F7_P$157") (pintype "bidirectional"))
    )
    (net (code "1848") (name "ZZ.09.106") (class "Default")
      (node (ref "U$13") (pin "P$36") (pinfunction "B6_P$36") (pintype "bidirectional"))
    )
    (net (code "1849") (name "ZZ.09.107") (class "Default")
      (node (ref "U$13") (pin "P$66") (pinfunction "C6_P$66") (pintype "bidirectional"))
    )
    (net (code "1850") (name "ZZ.09.108") (class "Default")
      (node (ref "U$13") (pin "P$96") (pinfunction "D6_P$96") (pintype "bidirectional"))
    )
    (net (code "1851") (name "ZZ.09.109") (class "Default")
      (node (ref "U$13") (pin "P$126") (pinfunction "E6_P$126") (pintype "bidirectional"))
    )
    (net (code "1852") (name "ZZ.09.110") (class "Default")
      (node (ref "U$13") (pin "P$156") (pinfunction "F6_P$156") (pintype "bidirectional"))
    )
    (net (code "1853") (name "ZZ.09.111") (class "Default")
      (node (ref "U$13") (pin "P$152") (pinfunction "F2_P$152") (pintype "bidirectional"))
    )
    (net (code "1854") (name "ZZ.09.112") (class "Default")
      (node (ref "U$15") (pin "P$38") (pinfunction "B8_P$38") (pintype "bidirectional"))
    )
    (net (code "1855") (name "ZZ.09.113") (class "Default")
      (node (ref "U$15") (pin "P$68") (pinfunction "C8_P$68") (pintype "bidirectional"))
    )
    (net (code "1856") (name "ZZ.09.114") (class "Default")
      (node (ref "U$15") (pin "P$98") (pinfunction "D8_P$98") (pintype "bidirectional"))
    )
    (net (code "1857") (name "ZZ.09.115") (class "Default")
      (node (ref "U$15") (pin "P$128") (pinfunction "E8_P$128") (pintype "bidirectional"))
    )
    (net (code "1858") (name "ZZ.09.116") (class "Default")
      (node (ref "U$15") (pin "P$158") (pinfunction "F8_P$158") (pintype "bidirectional"))
    )
    (net (code "1859") (name "ZZ.09.117") (class "Default")
      (node (ref "U$15") (pin "P$37") (pinfunction "B7_P$37") (pintype "bidirectional"))
    )
    (net (code "1860") (name "ZZ.09.118") (class "Default")
      (node (ref "U$15") (pin "P$67") (pinfunction "C7_P$67") (pintype "bidirectional"))
    )
    (net (code "1861") (name "ZZ.09.119") (class "Default")
      (node (ref "U$15") (pin "P$97") (pinfunction "D7_P$97") (pintype "bidirectional"))
    )
    (net (code "1862") (name "ZZ.09.120") (class "Default")
      (node (ref "U$15") (pin "P$127") (pinfunction "E7_P$127") (pintype "bidirectional"))
    )
    (net (code "1863") (name "ZZ.09.121") (class "Default")
      (node (ref "U$15") (pin "P$157") (pinfunction "F7_P$157") (pintype "bidirectional"))
    )
    (net (code "1864") (name "ZZ.09.122") (class "Default")
      (node (ref "U$15") (pin "P$36") (pinfunction "B6_P$36") (pintype "bidirectional"))
    )
    (net (code "1865") (name "ZZ.09.123") (class "Default")
      (node (ref "U$15") (pin "P$66") (pinfunction "C6_P$66") (pintype "bidirectional"))
    )
    (net (code "1866") (name "ZZ.09.124") (class "Default")
      (node (ref "U$15") (pin "P$96") (pinfunction "D6_P$96") (pintype "bidirectional"))
    )
    (net (code "1867") (name "ZZ.09.125") (class "Default")
      (node (ref "U$15") (pin "P$126") (pinfunction "E6_P$126") (pintype "bidirectional"))
    )
    (net (code "1868") (name "ZZ.09.126") (class "Default")
      (node (ref "U$15") (pin "P$156") (pinfunction "F6_P$156") (pintype "bidirectional"))
    )
    (net (code "1869") (name "ZZ.09.127") (class "Default")
      (node (ref "U$15") (pin "P$152") (pinfunction "F2_P$152") (pintype "bidirectional"))
    )
    (net (code "1870") (name "ZZ.09.128") (class "Default")
      (node (ref "U$17") (pin "P$38") (pinfunction "B8_P$38") (pintype "bidirectional"))
    )
    (net (code "1871") (name "ZZ.09.129") (class "Default")
      (node (ref "U$17") (pin "P$68") (pinfunction "C8_P$68") (pintype "bidirectional"))
    )
    (net (code "1872") (name "ZZ.09.130") (class "Default")
      (node (ref "U$17") (pin "P$98") (pinfunction "D8_P$98") (pintype "bidirectional"))
    )
    (net (code "1873") (name "ZZ.09.131") (class "Default")
      (node (ref "U$17") (pin "P$128") (pinfunction "E8_P$128") (pintype "bidirectional"))
    )
    (net (code "1874") (name "ZZ.09.132") (class "Default")
      (node (ref "U$17") (pin "P$158") (pinfunction "F8_P$158") (pintype "bidirectional"))
    )
    (net (code "1875") (name "ZZ.09.133") (class "Default")
      (node (ref "U$17") (pin "P$37") (pinfunction "B7_P$37") (pintype "bidirectional"))
    )
    (net (code "1876") (name "ZZ.09.134") (class "Default")
      (node (ref "U$17") (pin "P$67") (pinfunction "C7_P$67") (pintype "bidirectional"))
    )
    (net (code "1877") (name "ZZ.09.135") (class "Default")
      (node (ref "U$17") (pin "P$97") (pinfunction "D7_P$97") (pintype "bidirectional"))
    )
    (net (code "1878") (name "ZZ.09.136") (class "Default")
      (node (ref "U$17") (pin "P$127") (pinfunction "E7_P$127") (pintype "bidirectional"))
    )
    (net (code "1879") (name "ZZ.09.137") (class "Default")
      (node (ref "U$17") (pin "P$157") (pinfunction "F7_P$157") (pintype "bidirectional"))
    )
    (net (code "1880") (name "ZZ.09.138") (class "Default")
      (node (ref "U$17") (pin "P$36") (pinfunction "B6_P$36") (pintype "bidirectional"))
    )
    (net (code "1881") (name "ZZ.09.139") (class "Default")
      (node (ref "U$17") (pin "P$66") (pinfunction "C6_P$66") (pintype "bidirectional"))
    )
    (net (code "1882") (name "ZZ.09.140") (class "Default")
      (node (ref "U$17") (pin "P$96") (pinfunction "D6_P$96") (pintype "bidirectional"))
    )
    (net (code "1883") (name "ZZ.09.141") (class "Default")
      (node (ref "U$17") (pin "P$126") (pinfunction "E6_P$126") (pintype "bidirectional"))
    )
    (net (code "1884") (name "ZZ.09.142") (class "Default")
      (node (ref "U$17") (pin "P$156") (pinfunction "F6_P$156") (pintype "bidirectional"))
    )
    (net (code "1885") (name "ZZ.09.143") (class "Default")
      (node (ref "U$17") (pin "P$152") (pinfunction "F2_P$152") (pintype "bidirectional"))
    )
    (net (code "1886") (name "ZZ.09.144") (class "Default")
      (node (ref "U$19") (pin "P$38") (pinfunction "B8_P$38") (pintype "bidirectional"))
    )
    (net (code "1887") (name "ZZ.09.145") (class "Default")
      (node (ref "U$19") (pin "P$68") (pinfunction "C8_P$68") (pintype "bidirectional"))
    )
    (net (code "1888") (name "ZZ.09.146") (class "Default")
      (node (ref "U$19") (pin "P$98") (pinfunction "D8_P$98") (pintype "bidirectional"))
    )
    (net (code "1889") (name "ZZ.09.147") (class "Default")
      (node (ref "U$19") (pin "P$128") (pinfunction "E8_P$128") (pintype "bidirectional"))
    )
    (net (code "1890") (name "ZZ.09.148") (class "Default")
      (node (ref "U$19") (pin "P$158") (pinfunction "F8_P$158") (pintype "bidirectional"))
    )
    (net (code "1891") (name "ZZ.09.149") (class "Default")
      (node (ref "U$19") (pin "P$37") (pinfunction "B7_P$37") (pintype "bidirectional"))
    )
    (net (code "1892") (name "ZZ.09.150") (class "Default")
      (node (ref "U$19") (pin "P$67") (pinfunction "C7_P$67") (pintype "bidirectional"))
    )
    (net (code "1893") (name "ZZ.09.151") (class "Default")
      (node (ref "U$19") (pin "P$97") (pinfunction "D7_P$97") (pintype "bidirectional"))
    )
    (net (code "1894") (name "ZZ.09.152") (class "Default")
      (node (ref "U$19") (pin "P$127") (pinfunction "E7_P$127") (pintype "bidirectional"))
    )
    (net (code "1895") (name "ZZ.09.153") (class "Default")
      (node (ref "U$19") (pin "P$157") (pinfunction "F7_P$157") (pintype "bidirectional"))
    )
    (net (code "1896") (name "ZZ.09.154") (class "Default")
      (node (ref "U$19") (pin "P$36") (pinfunction "B6_P$36") (pintype "bidirectional"))
    )
    (net (code "1897") (name "ZZ.09.155") (class "Default")
      (node (ref "U$19") (pin "P$66") (pinfunction "C6_P$66") (pintype "bidirectional"))
    )
    (net (code "1898") (name "ZZ.09.156") (class "Default")
      (node (ref "U$19") (pin "P$96") (pinfunction "D6_P$96") (pintype "bidirectional"))
    )
    (net (code "1899") (name "ZZ.09.157") (class "Default")
      (node (ref "U$19") (pin "P$126") (pinfunction "E6_P$126") (pintype "bidirectional"))
    )
    (net (code "1900") (name "ZZ.09.158") (class "Default")
      (node (ref "U$19") (pin "P$156") (pinfunction "F6_P$156") (pintype "bidirectional"))
    )
    (net (code "1901") (name "ZZ.09.159") (class "Default")
      (node (ref "U$19") (pin "P$152") (pinfunction "F2_P$152") (pintype "bidirectional"))
    )
    (net (code "1902") (name "ZZ.09.160") (class "Default")
      (node (ref "U$21") (pin "P$38") (pinfunction "B8_P$38") (pintype "bidirectional"))
    )
    (net (code "1903") (name "ZZ.09.161") (class "Default")
      (node (ref "U$21") (pin "P$68") (pinfunction "C8_P$68") (pintype "bidirectional"))
    )
    (net (code "1904") (name "ZZ.09.162") (class "Default")
      (node (ref "U$21") (pin "P$98") (pinfunction "D8_P$98") (pintype "bidirectional"))
    )
    (net (code "1905") (name "ZZ.09.163") (class "Default")
      (node (ref "U$21") (pin "P$128") (pinfunction "E8_P$128") (pintype "bidirectional"))
    )
    (net (code "1906") (name "ZZ.09.164") (class "Default")
      (node (ref "U$21") (pin "P$158") (pinfunction "F8_P$158") (pintype "bidirectional"))
    )
    (net (code "1907") (name "ZZ.09.165") (class "Default")
      (node (ref "U$21") (pin "P$37") (pinfunction "B7_P$37") (pintype "bidirectional"))
    )
    (net (code "1908") (name "ZZ.09.166") (class "Default")
      (node (ref "U$21") (pin "P$67") (pinfunction "C7_P$67") (pintype "bidirectional"))
    )
    (net (code "1909") (name "ZZ.09.167") (class "Default")
      (node (ref "U$21") (pin "P$97") (pinfunction "D7_P$97") (pintype "bidirectional"))
    )
    (net (code "1910") (name "ZZ.09.168") (class "Default")
      (node (ref "U$21") (pin "P$127") (pinfunction "E7_P$127") (pintype "bidirectional"))
    )
    (net (code "1911") (name "ZZ.09.169") (class "Default")
      (node (ref "U$21") (pin "P$157") (pinfunction "F7_P$157") (pintype "bidirectional"))
    )
    (net (code "1912") (name "ZZ.09.170") (class "Default")
      (node (ref "U$21") (pin "P$36") (pinfunction "B6_P$36") (pintype "bidirectional"))
    )
    (net (code "1913") (name "ZZ.09.171") (class "Default")
      (node (ref "U$21") (pin "P$66") (pinfunction "C6_P$66") (pintype "bidirectional"))
    )
    (net (code "1914") (name "ZZ.09.172") (class "Default")
      (node (ref "U$21") (pin "P$96") (pinfunction "D6_P$96") (pintype "bidirectional"))
    )
    (net (code "1915") (name "ZZ.09.173") (class "Default")
      (node (ref "U$21") (pin "P$126") (pinfunction "E6_P$126") (pintype "bidirectional"))
    )
    (net (code "1916") (name "ZZ.09.174") (class "Default")
      (node (ref "U$21") (pin "P$156") (pinfunction "F6_P$156") (pintype "bidirectional"))
    )
    (net (code "1917") (name "ZZ.09.175") (class "Default")
      (node (ref "U$21") (pin "P$152") (pinfunction "F2_P$152") (pintype "bidirectional"))
    )
    (net (code "1918") (name "ZZ.09.176") (class "Default")
      (node (ref "U$23") (pin "P$38") (pinfunction "B8_P$38") (pintype "bidirectional"))
    )
    (net (code "1919") (name "ZZ.09.177") (class "Default")
      (node (ref "U$23") (pin "P$68") (pinfunction "C8_P$68") (pintype "bidirectional"))
    )
    (net (code "1920") (name "ZZ.09.178") (class "Default")
      (node (ref "U$23") (pin "P$98") (pinfunction "D8_P$98") (pintype "bidirectional"))
    )
    (net (code "1921") (name "ZZ.09.179") (class "Default")
      (node (ref "U$23") (pin "P$128") (pinfunction "E8_P$128") (pintype "bidirectional"))
    )
    (net (code "1922") (name "ZZ.09.180") (class "Default")
      (node (ref "U$23") (pin "P$158") (pinfunction "F8_P$158") (pintype "bidirectional"))
    )
    (net (code "1923") (name "ZZ.09.181") (class "Default")
      (node (ref "U$23") (pin "P$37") (pinfunction "B7_P$37") (pintype "bidirectional"))
    )
    (net (code "1924") (name "ZZ.09.182") (class "Default")
      (node (ref "U$23") (pin "P$67") (pinfunction "C7_P$67") (pintype "bidirectional"))
    )
    (net (code "1925") (name "ZZ.09.183") (class "Default")
      (node (ref "U$23") (pin "P$97") (pinfunction "D7_P$97") (pintype "bidirectional"))
    )
    (net (code "1926") (name "ZZ.09.184") (class "Default")
      (node (ref "U$23") (pin "P$127") (pinfunction "E7_P$127") (pintype "bidirectional"))
    )
    (net (code "1927") (name "ZZ.09.185") (class "Default")
      (node (ref "U$23") (pin "P$157") (pinfunction "F7_P$157") (pintype "bidirectional"))
    )
    (net (code "1928") (name "ZZ.09.186") (class "Default")
      (node (ref "U$23") (pin "P$36") (pinfunction "B6_P$36") (pintype "bidirectional"))
    )
    (net (code "1929") (name "ZZ.09.187") (class "Default")
      (node (ref "U$23") (pin "P$66") (pinfunction "C6_P$66") (pintype "bidirectional"))
    )
    (net (code "1930") (name "ZZ.09.188") (class "Default")
      (node (ref "U$23") (pin "P$96") (pinfunction "D6_P$96") (pintype "bidirectional"))
    )
    (net (code "1931") (name "ZZ.09.189") (class "Default")
      (node (ref "U$23") (pin "P$126") (pinfunction "E6_P$126") (pintype "bidirectional"))
    )
    (net (code "1932") (name "ZZ.09.190") (class "Default")
      (node (ref "U$23") (pin "P$156") (pinfunction "F6_P$156") (pintype "bidirectional"))
    )
    (net (code "1933") (name "ZZ.09.191") (class "Default")
      (node (ref "U$23") (pin "P$152") (pinfunction "F2_P$152") (pintype "bidirectional"))
    )
    (net (code "1934") (name "ZZ.10.000") (class "Default")
      (node (ref "U$1") (pin "P$70") (pinfunction "C10_P$70") (pintype "bidirectional"))
    )
    (net (code "1935") (name "ZZ.10.001") (class "Default")
      (node (ref "U$1") (pin "P$130") (pinfunction "E10_P$130") (pintype "bidirectional"))
    )
    (net (code "1936") (name "ZZ.10.002") (class "Default")
      (node (ref "U$1") (pin "P$129") (pinfunction "E9_P$129") (pintype "bidirectional"))
    )
    (net (code "1937") (name "ZZ.10.003") (class "Default")
      (node (ref "U$1") (pin "P$41") (pinfunction "B11_P$41") (pintype "bidirectional"))
    )
    (net (code "1938") (name "ZZ.10.004") (class "Default")
      (node (ref "U$1") (pin "P$131") (pinfunction "E11_P$131") (pintype "bidirectional"))
    )
    (net (code "1939") (name "ZZ.10.005") (class "Default")
      (node (ref "U$1") (pin "P$42") (pinfunction "B12_P$42") (pintype "bidirectional"))
    )
    (net (code "1940") (name "ZZ.10.006") (class "Default")
      (node (ref "U$1") (pin "P$102") (pinfunction "D12_P$102") (pintype "bidirectional"))
    )
    (net (code "1941") (name "ZZ.10.007") (class "Default")
      (node (ref "U$1") (pin "P$162") (pinfunction "F12_P$162") (pintype "bidirectional"))
    )
    (net (code "1942") (name "ZZ.10.008") (class "Default")
      (node (ref "U$1") (pin "P$43") (pinfunction "B13_P$43") (pintype "bidirectional"))
    )
    (net (code "1943") (name "ZZ.10.009") (class "Default")
      (node (ref "U$1") (pin "P$103") (pinfunction "D13_P$103") (pintype "bidirectional"))
    )
    (net (code "1944") (name "ZZ.10.010") (class "Default")
      (node (ref "U$1") (pin "P$163") (pinfunction "F13_P$163") (pintype "bidirectional"))
    )
    (net (code "1945") (name "ZZ.10.011") (class "Default")
      (node (ref "U$1") (pin "P$74") (pinfunction "C14_P$74") (pintype "bidirectional"))
    )
    (net (code "1946") (name "ZZ.10.012") (class "Default")
      (node (ref "U$1") (pin "P$164") (pinfunction "F14_P$164") (pintype "bidirectional"))
    )
    (net (code "1947") (name "ZZ.10.013") (class "Default")
      (node (ref "U$1") (pin "P$75") (pinfunction "C15_P$75") (pintype "bidirectional"))
    )
    (net (code "1948") (name "ZZ.10.014") (class "Default")
      (node (ref "U$1") (pin "P$135") (pinfunction "E15_P$135") (pintype "bidirectional"))
    )
    (net (code "1949") (name "ZZ.10.015") (class "Default")
      (node (ref "U$1") (pin "P$45") (pinfunction "B15_P$45") (pintype "bidirectional"))
    )
    (net (code "1950") (name "ZZ.10.016") (class "Default")
      (node (ref "U$3") (pin "P$40") (pinfunction "B10_P$40") (pintype "bidirectional"))
    )
    (net (code "1951") (name "ZZ.10.017") (class "Default")
      (node (ref "U$3") (pin "P$100") (pinfunction "D10_P$100") (pintype "bidirectional"))
    )
    (net (code "1952") (name "ZZ.10.018") (class "Default")
      (node (ref "U$3") (pin "P$129") (pinfunction "E9_P$129") (pintype "bidirectional"))
    )
    (net (code "1953") (name "ZZ.10.019") (class "Default")
      (node (ref "U$3") (pin "P$71") (pinfunction "C11_P$71") (pintype "bidirectional"))
    )
    (net (code "1954") (name "ZZ.10.020") (class "Default")
      (node (ref "U$3") (pin "P$101") (pinfunction "D11_P$101") (pintype "bidirectional"))
    )
    (net (code "1955") (name "ZZ.10.021") (class "Default")
      (node (ref "U$3") (pin "P$42") (pinfunction "B12_P$42") (pintype "bidirectional"))
    )
    (net (code "1956") (name "ZZ.10.022") (class "Default")
      (node (ref "U$3") (pin "P$102") (pinfunction "D12_P$102") (pintype "bidirectional"))
    )
    (net (code "1957") (name "ZZ.10.023") (class "Default")
      (node (ref "U$3") (pin "P$132") (pinfunction "E12_P$132") (pintype "bidirectional"))
    )
    (net (code "1958") (name "ZZ.10.024") (class "Default")
      (node (ref "U$3") (pin "P$43") (pinfunction "B13_P$43") (pintype "bidirectional"))
    )
    (net (code "1959") (name "ZZ.10.025") (class "Default")
      (node (ref "U$3") (pin "P$133") (pinfunction "E13_P$133") (pintype "bidirectional"))
    )
    (net (code "1960") (name "ZZ.10.026") (class "Default")
      (node (ref "U$3") (pin "P$159") (pinfunction "F9_P$159") (pintype "bidirectional"))
    )
    (net (code "1961") (name "ZZ.10.027") (class "Default")
      (node (ref "U$3") (pin "P$165") (pinfunction "F15_P$165") (pintype "bidirectional"))
    )
    (net (code "1962") (name "ZZ.10.028") (class "Default")
      (node (ref "U$3") (pin "P$45") (pinfunction "B15_P$45") (pintype "bidirectional"))
    )
    (net (code "1963") (name "ZZ.10.029") (class "Default")
      (node (ref "U$3") (pin "P$75") (pinfunction "C15_P$75") (pintype "bidirectional"))
    )
    (net (code "1964") (name "ZZ.10.030") (class "Default")
      (node (ref "U$3") (pin "P$105") (pinfunction "D15_P$105") (pintype "bidirectional"))
    )
    (net (code "1965") (name "ZZ.10.031") (class "Default")
      (node (ref "U$3") (pin "P$135") (pinfunction "E15_P$135") (pintype "bidirectional"))
    )
    (net (code "1966") (name "ZZ.10.032") (class "Default")
      (node (ref "U$5") (pin "P$40") (pinfunction "B10_P$40") (pintype "bidirectional"))
    )
    (net (code "1967") (name "ZZ.10.033") (class "Default")
      (node (ref "U$5") (pin "P$100") (pinfunction "D10_P$100") (pintype "bidirectional"))
    )
    (net (code "1968") (name "ZZ.10.034") (class "Default")
      (node (ref "U$5") (pin "P$160") (pinfunction "F10_P$160") (pintype "bidirectional"))
    )
    (net (code "1969") (name "ZZ.10.035") (class "Default")
      (node (ref "U$5") (pin "P$41") (pinfunction "B11_P$41") (pintype "bidirectional"))
    )
    (net (code "1970") (name "ZZ.10.036") (class "Default")
      (node (ref "U$5") (pin "P$101") (pinfunction "D11_P$101") (pintype "bidirectional"))
    )
    (net (code "1971") (name "ZZ.10.037") (class "Default")
      (node (ref "U$5") (pin "P$42") (pinfunction "B12_P$42") (pintype "bidirectional"))
    )
    (net (code "1972") (name "ZZ.10.038") (class "Default")
      (node (ref "U$5") (pin "P$102") (pinfunction "D12_P$102") (pintype "bidirectional"))
    )
    (net (code "1973") (name "ZZ.10.039") (class "Default")
      (node (ref "U$5") (pin "P$162") (pinfunction "F12_P$162") (pintype "bidirectional"))
    )
    (net (code "1974") (name "ZZ.10.040") (class "Default")
      (node (ref "U$5") (pin "P$43") (pinfunction "B13_P$43") (pintype "bidirectional"))
    )
    (net (code "1975") (name "ZZ.10.041") (class "Default")
      (node (ref "U$5") (pin "P$103") (pinfunction "D13_P$103") (pintype "bidirectional"))
    )
    (net (code "1976") (name "ZZ.10.042") (class "Default")
      (node (ref "U$5") (pin "P$45") (pinfunction "B15_P$45") (pintype "bidirectional"))
    )
    (net (code "1977") (name "ZZ.10.043") (class "Default")
      (node (ref "U$5") (pin "P$75") (pinfunction "C15_P$75") (pintype "bidirectional"))
    )
    (net (code "1978") (name "ZZ.10.044") (class "Default")
      (node (ref "U$5") (pin "P$105") (pinfunction "D15_P$105") (pintype "bidirectional"))
    )
    (net (code "1979") (name "ZZ.10.045") (class "Default")
      (node (ref "U$5") (pin "P$135") (pinfunction "E15_P$135") (pintype "bidirectional"))
    )
    (net (code "1980") (name "ZZ.10.046") (class "Default")
      (node (ref "U$5") (pin "P$165") (pinfunction "F15_P$165") (pintype "bidirectional"))
    )
    (net (code "1981") (name "ZZ.10.047") (class "Default")
      (node (ref "U$5") (pin "P$159") (pinfunction "F9_P$159") (pintype "bidirectional"))
    )
    (net (code "1982") (name "ZZ.10.048") (class "Default")
      (node (ref "U$7") (pin "P$40") (pinfunction "B10_P$40") (pintype "bidirectional"))
    )
    (net (code "1983") (name "ZZ.10.049") (class "Default")
      (node (ref "U$7") (pin "P$100") (pinfunction "D10_P$100") (pintype "bidirectional"))
    )
    (net (code "1984") (name "ZZ.10.050") (class "Default")
      (node (ref "U$7") (pin "P$129") (pinfunction "E9_P$129") (pintype "bidirectional"))
    )
    (net (code "1985") (name "ZZ.10.051") (class "Default")
      (node (ref "U$7") (pin "P$41") (pinfunction "B11_P$41") (pintype "bidirectional"))
    )
    (net (code "1986") (name "ZZ.10.052") (class "Default")
      (node (ref "U$7") (pin "P$101") (pinfunction "D11_P$101") (pintype "bidirectional"))
    )
    (net (code "1987") (name "ZZ.10.053") (class "Default")
      (node (ref "U$7") (pin "P$42") (pinfunction "B12_P$42") (pintype "bidirectional"))
    )
    (net (code "1988") (name "ZZ.10.054") (class "Default")
      (node (ref "U$7") (pin "P$102") (pinfunction "D12_P$102") (pintype "bidirectional"))
    )
    (net (code "1989") (name "ZZ.10.055") (class "Default")
      (node (ref "U$7") (pin "P$73") (pinfunction "C13_P$73") (pintype "bidirectional"))
    )
    (net (code "1990") (name "ZZ.10.056") (class "Default")
      (node (ref "U$7") (pin "P$45") (pinfunction "B15_P$45") (pintype "bidirectional"))
    )
    (net (code "1991") (name "ZZ.10.057") (class "Default")
      (node (ref "U$7") (pin "P$75") (pinfunction "C15_P$75") (pintype "bidirectional"))
    )
    (net (code "1992") (name "ZZ.10.058") (class "Default")
      (node (ref "U$7") (pin "P$105") (pinfunction "D15_P$105") (pintype "bidirectional"))
    )
    (net (code "1993") (name "ZZ.10.059") (class "Default")
      (node (ref "U$7") (pin "P$135") (pinfunction "E15_P$135") (pintype "bidirectional"))
    )
    (net (code "1994") (name "ZZ.10.060") (class "Default")
      (node (ref "U$7") (pin "P$165") (pinfunction "F15_P$165") (pintype "bidirectional"))
    )
    (net (code "1995") (name "ZZ.10.061") (class "Default")
      (node (ref "U$7") (pin "P$103") (pinfunction "D13_P$103") (pintype "bidirectional"))
    )
    (net (code "1996") (name "ZZ.10.062") (class "Default")
      (node (ref "U$7") (pin "P$159") (pinfunction "F9_P$159") (pintype "bidirectional"))
    )
    (net (code "1997") (name "ZZ.10.063") (class "Default")
      (node (ref "U$7") (pin "P$162") (pinfunction "F12_P$162") (pintype "bidirectional"))
    )
    (net (code "1998") (name "ZZ.10.064") (class "Default")
      (node (ref "U$9") (pin "P$40") (pinfunction "B10_P$40") (pintype "bidirectional"))
    )
    (net (code "1999") (name "ZZ.10.065") (class "Default")
      (node (ref "U$9") (pin "P$130") (pinfunction "E10_P$130") (pintype "bidirectional"))
    )
    (net (code "2000") (name "ZZ.10.066") (class "Default")
      (node (ref "U$9") (pin "P$41") (pinfunction "B11_P$41") (pintype "bidirectional"))
    )
    (net (code "2001") (name "ZZ.10.067") (class "Default")
      (node (ref "U$9") (pin "P$42") (pinfunction "B12_P$42") (pintype "bidirectional"))
    )
    (net (code "2002") (name "ZZ.10.068") (class "Default")
      (node (ref "U$9") (pin "P$102") (pinfunction "D12_P$102") (pintype "bidirectional"))
    )
    (net (code "2003") (name "ZZ.10.069") (class "Default")
      (node (ref "U$9") (pin "P$73") (pinfunction "C13_P$73") (pintype "bidirectional"))
    )
    (net (code "2004") (name "ZZ.10.070") (class "Default")
      (node (ref "U$9") (pin "P$45") (pinfunction "B15_P$45") (pintype "bidirectional"))
    )
    (net (code "2005") (name "ZZ.10.071") (class "Default")
      (node (ref "U$9") (pin "P$75") (pinfunction "C15_P$75") (pintype "bidirectional"))
    )
    (net (code "2006") (name "ZZ.10.072") (class "Default")
      (node (ref "U$9") (pin "P$105") (pinfunction "D15_P$105") (pintype "bidirectional"))
    )
    (net (code "2007") (name "ZZ.10.073") (class "Default")
      (node (ref "U$9") (pin "P$135") (pinfunction "E15_P$135") (pintype "bidirectional"))
    )
    (net (code "2008") (name "ZZ.10.074") (class "Default")
      (node (ref "U$9") (pin "P$165") (pinfunction "F15_P$165") (pintype "bidirectional"))
    )
    (net (code "2009") (name "ZZ.10.075") (class "Default")
      (node (ref "U$9") (pin "P$133") (pinfunction "E13_P$133") (pintype "bidirectional"))
    )
    (net (code "2010") (name "ZZ.10.076") (class "Default")
      (node (ref "U$9") (pin "P$159") (pinfunction "F9_P$159") (pintype "bidirectional"))
    )
    (net (code "2011") (name "ZZ.10.077") (class "Default")
      (node (ref "U$9") (pin "P$132") (pinfunction "E12_P$132") (pintype "bidirectional"))
    )
    (net (code "2012") (name "ZZ.10.078") (class "Default")
      (node (ref "U$9") (pin "P$131") (pinfunction "E11_P$131") (pintype "bidirectional"))
    )
    (net (code "2013") (name "ZZ.10.079") (class "Default")
      (node (ref "U$9") (pin "P$129") (pinfunction "E9_P$129") (pintype "bidirectional"))
    )
    (net (code "2014") (name "ZZ.10.080") (class "Default")
      (node (ref "U$11") (pin "P$42") (pinfunction "B12_P$42") (pintype "bidirectional"))
    )
    (net (code "2015") (name "ZZ.10.081") (class "Default")
      (node (ref "U$11") (pin "P$102") (pinfunction "D12_P$102") (pintype "bidirectional"))
    )
    (net (code "2016") (name "ZZ.10.082") (class "Default")
      (node (ref "U$11") (pin "P$73") (pinfunction "C13_P$73") (pintype "bidirectional"))
    )
    (net (code "2017") (name "ZZ.10.083") (class "Default")
      (node (ref "U$11") (pin "P$45") (pinfunction "B15_P$45") (pintype "bidirectional"))
    )
    (net (code "2018") (name "ZZ.10.084") (class "Default")
      (node (ref "U$11") (pin "P$75") (pinfunction "C15_P$75") (pintype "bidirectional"))
    )
    (net (code "2019") (name "ZZ.10.085") (class "Default")
      (node (ref "U$11") (pin "P$105") (pinfunction "D15_P$105") (pintype "bidirectional"))
    )
    (net (code "2020") (name "ZZ.10.086") (class "Default")
      (node (ref "U$11") (pin "P$135") (pinfunction "E15_P$135") (pintype "bidirectional"))
    )
    (net (code "2021") (name "ZZ.10.087") (class "Default")
      (node (ref "U$11") (pin "P$165") (pinfunction "F15_P$165") (pintype "bidirectional"))
    )
    (net (code "2022") (name "ZZ.10.088") (class "Default")
      (node (ref "U$11") (pin "P$103") (pinfunction "D13_P$103") (pintype "bidirectional"))
    )
    (net (code "2023") (name "ZZ.10.089") (class "Default")
      (node (ref "U$11") (pin "P$163") (pinfunction "F13_P$163") (pintype "bidirectional"))
    )
    (net (code "2024") (name "ZZ.10.090") (class "Default")
      (node (ref "U$11") (pin "P$162") (pinfunction "F12_P$162") (pintype "bidirectional"))
    )
    (net (code "2025") (name "ZZ.10.091") (class "Default")
      (node (ref "U$11") (pin "P$71") (pinfunction "C11_P$71") (pintype "bidirectional"))
    )
    (net (code "2026") (name "ZZ.10.092") (class "Default")
      (node (ref "U$11") (pin "P$161") (pinfunction "F11_P$161") (pintype "bidirectional"))
    )
    (net (code "2027") (name "ZZ.10.093") (class "Default")
      (node (ref "U$11") (pin "P$40") (pinfunction "B10_P$40") (pintype "bidirectional"))
    )
    (net (code "2028") (name "ZZ.10.094") (class "Default")
      (node (ref "U$11") (pin "P$100") (pinfunction "D10_P$100") (pintype "bidirectional"))
    )
    (net (code "2029") (name "ZZ.10.095") (class "Default")
      (node (ref "U$11") (pin "P$129") (pinfunction "E9_P$129") (pintype "bidirectional"))
    )
    (net (code "2030") (name "ZZ.10.096") (class "Default")
      (node (ref "U$13") (pin "P$73") (pinfunction "C13_P$73") (pintype "bidirectional"))
    )
    (net (code "2031") (name "ZZ.10.097") (class "Default")
      (node (ref "U$13") (pin "P$45") (pinfunction "B15_P$45") (pintype "bidirectional"))
    )
    (net (code "2032") (name "ZZ.10.098") (class "Default")
      (node (ref "U$13") (pin "P$75") (pinfunction "C15_P$75") (pintype "bidirectional"))
    )
    (net (code "2033") (name "ZZ.10.099") (class "Default")
      (node (ref "U$13") (pin "P$105") (pinfunction "D15_P$105") (pintype "bidirectional"))
    )
    (net (code "2034") (name "ZZ.10.100") (class "Default")
      (node (ref "U$13") (pin "P$135") (pinfunction "E15_P$135") (pintype "bidirectional"))
    )
    (net (code "2035") (name "ZZ.10.101") (class "Default")
      (node (ref "U$13") (pin "P$165") (pinfunction "F15_P$165") (pintype "bidirectional"))
    )
    (net (code "2036") (name "ZZ.10.102") (class "Default")
      (node (ref "U$13") (pin "P$133") (pinfunction "E13_P$133") (pintype "bidirectional"))
    )
    (net (code "2037") (name "ZZ.10.103") (class "Default")
      (node (ref "U$13") (pin "P$159") (pinfunction "F9_P$159") (pintype "bidirectional"))
    )
    (net (code "2038") (name "ZZ.10.104") (class "Default")
      (node (ref "U$13") (pin "P$72") (pinfunction "C12_P$72") (pintype "bidirectional"))
    )
    (net (code "2039") (name "ZZ.10.105") (class "Default")
      (node (ref "U$13") (pin "P$102") (pinfunction "D12_P$102") (pintype "bidirectional"))
    )
    (net (code "2040") (name "ZZ.10.106") (class "Default")
      (node (ref "U$13") (pin "P$41") (pinfunction "B11_P$41") (pintype "bidirectional"))
    )
    (net (code "2041") (name "ZZ.10.107") (class "Default")
      (node (ref "U$13") (pin "P$71") (pinfunction "C11_P$71") (pintype "bidirectional"))
    )
    (net (code "2042") (name "ZZ.10.108") (class "Default")
      (node (ref "U$13") (pin "P$131") (pinfunction "E11_P$131") (pintype "bidirectional"))
    )
    (net (code "2043") (name "ZZ.10.109") (class "Default")
      (node (ref "U$13") (pin "P$40") (pinfunction "B10_P$40") (pintype "bidirectional"))
    )
    (net (code "2044") (name "ZZ.10.110") (class "Default")
      (node (ref "U$13") (pin "P$130") (pinfunction "E10_P$130") (pintype "bidirectional"))
    )
    (net (code "2045") (name "ZZ.10.111") (class "Default")
      (node (ref "U$13") (pin "P$129") (pinfunction "E9_P$129") (pintype "bidirectional"))
    )
    (net (code "2046") (name "ZZ.10.112") (class "Default")
      (node (ref "U$15") (pin "P$75") (pinfunction "C15_P$75") (pintype "bidirectional"))
    )
    (net (code "2047") (name "ZZ.10.113") (class "Default")
      (node (ref "U$15") (pin "P$105") (pinfunction "D15_P$105") (pintype "bidirectional"))
    )
    (net (code "2048") (name "ZZ.10.114") (class "Default")
      (node (ref "U$15") (pin "P$135") (pinfunction "E15_P$135") (pintype "bidirectional"))
    )
    (net (code "2049") (name "ZZ.10.115") (class "Default")
      (node (ref "U$15") (pin "P$165") (pinfunction "F15_P$165") (pintype "bidirectional"))
    )
    (net (code "2050") (name "ZZ.10.116") (class "Default")
      (node (ref "U$15") (pin "P$44") (pinfunction "B14_P$44") (pintype "bidirectional"))
    )
    (net (code "2051") (name "ZZ.10.117") (class "Default")
      (node (ref "U$15") (pin "P$43") (pinfunction "B13_P$43") (pintype "bidirectional"))
    )
    (net (code "2052") (name "ZZ.10.118") (class "Default")
      (node (ref "U$15") (pin "P$133") (pinfunction "E13_P$133") (pintype "bidirectional"))
    )
    (net (code "2053") (name "ZZ.10.119") (class "Default")
      (node (ref "U$15") (pin "P$159") (pinfunction "F9_P$159") (pintype "bidirectional"))
    )
    (net (code "2054") (name "ZZ.10.120") (class "Default")
      (node (ref "U$15") (pin "P$72") (pinfunction "C12_P$72") (pintype "bidirectional"))
    )
    (net (code "2055") (name "ZZ.10.121") (class "Default")
      (node (ref "U$15") (pin "P$102") (pinfunction "D12_P$102") (pintype "bidirectional"))
    )
    (net (code "2056") (name "ZZ.10.122") (class "Default")
      (node (ref "U$15") (pin "P$41") (pinfunction "B11_P$41") (pintype "bidirectional"))
    )
    (net (code "2057") (name "ZZ.10.123") (class "Default")
      (node (ref "U$15") (pin "P$71") (pinfunction "C11_P$71") (pintype "bidirectional"))
    )
    (net (code "2058") (name "ZZ.10.124") (class "Default")
      (node (ref "U$15") (pin "P$161") (pinfunction "F11_P$161") (pintype "bidirectional"))
    )
    (net (code "2059") (name "ZZ.10.125") (class "Default")
      (node (ref "U$15") (pin "P$40") (pinfunction "B10_P$40") (pintype "bidirectional"))
    )
    (net (code "2060") (name "ZZ.10.126") (class "Default")
      (node (ref "U$15") (pin "P$100") (pinfunction "D10_P$100") (pintype "bidirectional"))
    )
    (net (code "2061") (name "ZZ.10.127") (class "Default")
      (node (ref "U$15") (pin "P$129") (pinfunction "E9_P$129") (pintype "bidirectional"))
    )
    (net (code "2062") (name "ZZ.10.128") (class "Default")
      (node (ref "U$17") (pin "P$165") (pinfunction "F15_P$165") (pintype "bidirectional"))
    )
    (net (code "2063") (name "ZZ.10.129") (class "Default")
      (node (ref "U$17") (pin "P$75") (pinfunction "C15_P$75") (pintype "bidirectional"))
    )
    (net (code "2064") (name "ZZ.10.130") (class "Default")
      (node (ref "U$17") (pin "P$135") (pinfunction "E15_P$135") (pintype "bidirectional"))
    )
    (net (code "2065") (name "ZZ.10.131") (class "Default")
      (node (ref "U$17") (pin "P$74") (pinfunction "C14_P$74") (pintype "bidirectional"))
    )
    (net (code "2066") (name "ZZ.10.132") (class "Default")
      (node (ref "U$17") (pin "P$134") (pinfunction "E14_P$134") (pintype "bidirectional"))
    )
    (net (code "2067") (name "ZZ.10.133") (class "Default")
      (node (ref "U$17") (pin "P$73") (pinfunction "C13_P$73") (pintype "bidirectional"))
    )
    (net (code "2068") (name "ZZ.10.134") (class "Default")
      (node (ref "U$17") (pin "P$103") (pinfunction "D13_P$103") (pintype "bidirectional"))
    )
    (net (code "2069") (name "ZZ.10.135") (class "Default")
      (node (ref "U$17") (pin "P$163") (pinfunction "F13_P$163") (pintype "bidirectional"))
    )
    (net (code "2070") (name "ZZ.10.136") (class "Default")
      (node (ref "U$17") (pin "P$72") (pinfunction "C12_P$72") (pintype "bidirectional"))
    )
    (net (code "2071") (name "ZZ.10.137") (class "Default")
      (node (ref "U$17") (pin "P$132") (pinfunction "E12_P$132") (pintype "bidirectional"))
    )
    (net (code "2072") (name "ZZ.10.138") (class "Default")
      (node (ref "U$17") (pin "P$41") (pinfunction "B11_P$41") (pintype "bidirectional"))
    )
    (net (code "2073") (name "ZZ.10.139") (class "Default")
      (node (ref "U$17") (pin "P$71") (pinfunction "C11_P$71") (pintype "bidirectional"))
    )
    (net (code "2074") (name "ZZ.10.140") (class "Default")
      (node (ref "U$17") (pin "P$161") (pinfunction "F11_P$161") (pintype "bidirectional"))
    )
    (net (code "2075") (name "ZZ.10.141") (class "Default")
      (node (ref "U$17") (pin "P$40") (pinfunction "B10_P$40") (pintype "bidirectional"))
    )
    (net (code "2076") (name "ZZ.10.142") (class "Default")
      (node (ref "U$17") (pin "P$130") (pinfunction "E10_P$130") (pintype "bidirectional"))
    )
    (net (code "2077") (name "ZZ.10.143") (class "Default")
      (node (ref "U$17") (pin "P$160") (pinfunction "F10_P$160") (pintype "bidirectional"))
    )
    (net (code "2078") (name "ZZ.10.144") (class "Default")
      (node (ref "U$19") (pin "P$45") (pinfunction "B15_P$45") (pintype "bidirectional"))
    )
    (net (code "2079") (name "ZZ.10.145") (class "Default")
      (node (ref "U$19") (pin "P$135") (pinfunction "E15_P$135") (pintype "bidirectional"))
    )
    (net (code "2080") (name "ZZ.10.146") (class "Default")
      (node (ref "U$19") (pin "P$44") (pinfunction "B14_P$44") (pintype "bidirectional"))
    )
    (net (code "2081") (name "ZZ.10.147") (class "Default")
      (node (ref "U$19") (pin "P$74") (pinfunction "C14_P$74") (pintype "bidirectional"))
    )
    (net (code "2082") (name "ZZ.10.148") (class "Default")
      (node (ref "U$19") (pin "P$134") (pinfunction "E14_P$134") (pintype "bidirectional"))
    )
    (net (code "2083") (name "ZZ.10.149") (class "Default")
      (node (ref "U$19") (pin "P$43") (pinfunction "B13_P$43") (pintype "bidirectional"))
    )
    (net (code "2084") (name "ZZ.10.150") (class "Default")
      (node (ref "U$19") (pin "P$133") (pinfunction "E13_P$133") (pintype "bidirectional"))
    )
    (net (code "2085") (name "ZZ.10.151") (class "Default")
      (node (ref "U$19") (pin "P$159") (pinfunction "F9_P$159") (pintype "bidirectional"))
    )
    (net (code "2086") (name "ZZ.10.152") (class "Default")
      (node (ref "U$19") (pin "P$72") (pinfunction "C12_P$72") (pintype "bidirectional"))
    )
    (net (code "2087") (name "ZZ.10.153") (class "Default")
      (node (ref "U$19") (pin "P$132") (pinfunction "E12_P$132") (pintype "bidirectional"))
    )
    (net (code "2088") (name "ZZ.10.154") (class "Default")
      (node (ref "U$19") (pin "P$41") (pinfunction "B11_P$41") (pintype "bidirectional"))
    )
    (net (code "2089") (name "ZZ.10.155") (class "Default")
      (node (ref "U$19") (pin "P$71") (pinfunction "C11_P$71") (pintype "bidirectional"))
    )
    (net (code "2090") (name "ZZ.10.156") (class "Default")
      (node (ref "U$19") (pin "P$161") (pinfunction "F11_P$161") (pintype "bidirectional"))
    )
    (net (code "2091") (name "ZZ.10.157") (class "Default")
      (node (ref "U$19") (pin "P$40") (pinfunction "B10_P$40") (pintype "bidirectional"))
    )
    (net (code "2092") (name "ZZ.10.158") (class "Default")
      (node (ref "U$19") (pin "P$130") (pinfunction "E10_P$130") (pintype "bidirectional"))
    )
    (net (code "2093") (name "ZZ.10.159") (class "Default")
      (node (ref "U$19") (pin "P$129") (pinfunction "E9_P$129") (pintype "bidirectional"))
    )
    (net (code "2094") (name "ZZ.10.160") (class "Default")
      (node (ref "U$21") (pin "P$75") (pinfunction "C15_P$75") (pintype "bidirectional"))
    )
    (net (code "2095") (name "ZZ.10.161") (class "Default")
      (node (ref "U$21") (pin "P$135") (pinfunction "E15_P$135") (pintype "bidirectional"))
    )
    (net (code "2096") (name "ZZ.10.162") (class "Default")
      (node (ref "U$21") (pin "P$44") (pinfunction "B14_P$44") (pintype "bidirectional"))
    )
    (net (code "2097") (name "ZZ.10.163") (class "Default")
      (node (ref "U$21") (pin "P$74") (pinfunction "C14_P$74") (pintype "bidirectional"))
    )
    (net (code "2098") (name "ZZ.10.164") (class "Default")
      (node (ref "U$21") (pin "P$164") (pinfunction "F14_P$164") (pintype "bidirectional"))
    )
    (net (code "2099") (name "ZZ.10.165") (class "Default")
      (node (ref "U$21") (pin "P$73") (pinfunction "C13_P$73") (pintype "bidirectional"))
    )
    (net (code "2100") (name "ZZ.10.166") (class "Default")
      (node (ref "U$21") (pin "P$133") (pinfunction "E13_P$133") (pintype "bidirectional"))
    )
    (net (code "2101") (name "ZZ.10.167") (class "Default")
      (node (ref "U$21") (pin "P$159") (pinfunction "F9_P$159") (pintype "bidirectional"))
    )
    (net (code "2102") (name "ZZ.10.168") (class "Default")
      (node (ref "U$21") (pin "P$42") (pinfunction "B12_P$42") (pintype "bidirectional"))
    )
    (net (code "2103") (name "ZZ.10.169") (class "Default")
      (node (ref "U$21") (pin "P$102") (pinfunction "D12_P$102") (pintype "bidirectional"))
    )
    (net (code "2104") (name "ZZ.10.170") (class "Default")
      (node (ref "U$21") (pin "P$41") (pinfunction "B11_P$41") (pintype "bidirectional"))
    )
    (net (code "2105") (name "ZZ.10.171") (class "Default")
      (node (ref "U$21") (pin "P$101") (pinfunction "D11_P$101") (pintype "bidirectional"))
    )
    (net (code "2106") (name "ZZ.10.172") (class "Default")
      (node (ref "U$21") (pin "P$131") (pinfunction "E11_P$131") (pintype "bidirectional"))
    )
    (net (code "2107") (name "ZZ.10.173") (class "Default")
      (node (ref "U$21") (pin "P$40") (pinfunction "B10_P$40") (pintype "bidirectional"))
    )
    (net (code "2108") (name "ZZ.10.174") (class "Default")
      (node (ref "U$21") (pin "P$130") (pinfunction "E10_P$130") (pintype "bidirectional"))
    )
    (net (code "2109") (name "ZZ.10.175") (class "Default")
      (node (ref "U$21") (pin "P$129") (pinfunction "E9_P$129") (pintype "bidirectional"))
    )
    (net (code "2110") (name "ZZ.10.176") (class "Default")
      (node (ref "U$23") (pin "P$45") (pinfunction "B15_P$45") (pintype "bidirectional"))
    )
    (net (code "2111") (name "ZZ.10.177") (class "Default")
      (node (ref "U$23") (pin "P$135") (pinfunction "E15_P$135") (pintype "bidirectional"))
    )
    (net (code "2112") (name "ZZ.10.178") (class "Default")
      (node (ref "U$23") (pin "P$44") (pinfunction "B14_P$44") (pintype "bidirectional"))
    )
    (net (code "2113") (name "ZZ.10.179") (class "Default")
      (node (ref "U$23") (pin "P$74") (pinfunction "C14_P$74") (pintype "bidirectional"))
    )
    (net (code "2114") (name "ZZ.10.180") (class "Default")
      (node (ref "U$23") (pin "P$164") (pinfunction "F14_P$164") (pintype "bidirectional"))
    )
    (net (code "2115") (name "ZZ.10.181") (class "Default")
      (node (ref "U$23") (pin "P$73") (pinfunction "C13_P$73") (pintype "bidirectional"))
    )
    (net (code "2116") (name "ZZ.10.182") (class "Default")
      (node (ref "U$23") (pin "P$103") (pinfunction "D13_P$103") (pintype "bidirectional"))
    )
    (net (code "2117") (name "ZZ.10.183") (class "Default")
      (node (ref "U$23") (pin "P$159") (pinfunction "F9_P$159") (pintype "bidirectional"))
    )
    (net (code "2118") (name "ZZ.10.184") (class "Default")
      (node (ref "U$23") (pin "P$42") (pinfunction "B12_P$42") (pintype "bidirectional"))
    )
    (net (code "2119") (name "ZZ.10.185") (class "Default")
      (node (ref "U$23") (pin "P$102") (pinfunction "D12_P$102") (pintype "bidirectional"))
    )
    (net (code "2120") (name "ZZ.10.186") (class "Default")
      (node (ref "U$23") (pin "P$41") (pinfunction "B11_P$41") (pintype "bidirectional"))
    )
    (net (code "2121") (name "ZZ.10.187") (class "Default")
      (node (ref "U$23") (pin "P$101") (pinfunction "D11_P$101") (pintype "bidirectional"))
    )
    (net (code "2122") (name "ZZ.10.188") (class "Default")
      (node (ref "U$23") (pin "P$131") (pinfunction "E11_P$131") (pintype "bidirectional"))
    )
    (net (code "2123") (name "ZZ.10.189") (class "Default")
      (node (ref "U$23") (pin "P$40") (pinfunction "B10_P$40") (pintype "bidirectional"))
    )
    (net (code "2124") (name "ZZ.10.190") (class "Default")
      (node (ref "U$23") (pin "P$130") (pinfunction "E10_P$130") (pintype "bidirectional"))
    )
    (net (code "2125") (name "ZZ.10.191") (class "Default")
      (node (ref "U$23") (pin "P$129") (pinfunction "E9_P$129") (pintype "bidirectional"))
    )
    (net (code "2126") (name "ZZ.11.000") (class "Default")
      (node (ref "U$1") (pin "P$40") (pinfunction "B10_P$40") (pintype "bidirectional"))
    )
    (net (code "2127") (name "ZZ.11.001") (class "Default")
      (node (ref "U$1") (pin "P$100") (pinfunction "D10_P$100") (pintype "bidirectional"))
    )
    (net (code "2128") (name "ZZ.11.002") (class "Default")
      (node (ref "U$1") (pin "P$160") (pinfunction "F10_P$160") (pintype "bidirectional"))
    )
    (net (code "2129") (name "ZZ.11.003") (class "Default")
      (node (ref "U$1") (pin "P$71") (pinfunction "C11_P$71") (pintype "bidirectional"))
    )
    (net (code "2130") (name "ZZ.11.004") (class "Default")
      (node (ref "U$1") (pin "P$101") (pinfunction "D11_P$101") (pintype "bidirectional"))
    )
    (net (code "2131") (name "ZZ.11.005") (class "Default")
      (node (ref "U$1") (pin "P$161") (pinfunction "F11_P$161") (pintype "bidirectional"))
    )
    (net (code "2132") (name "ZZ.11.006") (class "Default")
      (node (ref "U$1") (pin "P$72") (pinfunction "C12_P$72") (pintype "bidirectional"))
    )
    (net (code "2133") (name "ZZ.11.007") (class "Default")
      (node (ref "U$1") (pin "P$132") (pinfunction "E12_P$132") (pintype "bidirectional"))
    )
    (net (code "2134") (name "ZZ.11.008") (class "Default")
      (node (ref "U$1") (pin "P$73") (pinfunction "C13_P$73") (pintype "bidirectional"))
    )
    (net (code "2135") (name "ZZ.11.009") (class "Default")
      (node (ref "U$1") (pin "P$133") (pinfunction "E13_P$133") (pintype "bidirectional"))
    )
    (net (code "2136") (name "ZZ.11.010") (class "Default")
      (node (ref "U$1") (pin "P$159") (pinfunction "F9_P$159") (pintype "bidirectional"))
    )
    (net (code "2137") (name "ZZ.11.011") (class "Default")
      (node (ref "U$1") (pin "P$104") (pinfunction "D14_P$104") (pintype "bidirectional"))
    )
    (net (code "2138") (name "ZZ.11.012") (class "Default")
      (node (ref "U$1") (pin "P$134") (pinfunction "E14_P$134") (pintype "bidirectional"))
    )
    (net (code "2139") (name "ZZ.11.013") (class "Default")
      (node (ref "U$1") (pin "P$105") (pinfunction "D15_P$105") (pintype "bidirectional"))
    )
    (net (code "2140") (name "ZZ.11.014") (class "Default")
      (node (ref "U$1") (pin "P$165") (pinfunction "F15_P$165") (pintype "bidirectional"))
    )
    (net (code "2141") (name "ZZ.11.015") (class "Default")
      (node (ref "U$1") (pin "P$44") (pinfunction "B14_P$44") (pintype "bidirectional"))
    )
    (net (code "2142") (name "ZZ.11.016") (class "Default")
      (node (ref "U$3") (pin "P$70") (pinfunction "C10_P$70") (pintype "bidirectional"))
    )
    (net (code "2143") (name "ZZ.11.017") (class "Default")
      (node (ref "U$3") (pin "P$130") (pinfunction "E10_P$130") (pintype "bidirectional"))
    )
    (net (code "2144") (name "ZZ.11.018") (class "Default")
      (node (ref "U$3") (pin "P$160") (pinfunction "F10_P$160") (pintype "bidirectional"))
    )
    (net (code "2145") (name "ZZ.11.019") (class "Default")
      (node (ref "U$3") (pin "P$41") (pinfunction "B11_P$41") (pintype "bidirectional"))
    )
    (net (code "2146") (name "ZZ.11.020") (class "Default")
      (node (ref "U$3") (pin "P$131") (pinfunction "E11_P$131") (pintype "bidirectional"))
    )
    (net (code "2147") (name "ZZ.11.021") (class "Default")
      (node (ref "U$3") (pin "P$161") (pinfunction "F11_P$161") (pintype "bidirectional"))
    )
    (net (code "2148") (name "ZZ.11.022") (class "Default")
      (node (ref "U$3") (pin "P$72") (pinfunction "C12_P$72") (pintype "bidirectional"))
    )
    (net (code "2149") (name "ZZ.11.023") (class "Default")
      (node (ref "U$3") (pin "P$162") (pinfunction "F12_P$162") (pintype "bidirectional"))
    )
    (net (code "2150") (name "ZZ.11.024") (class "Default")
      (node (ref "U$3") (pin "P$73") (pinfunction "C13_P$73") (pintype "bidirectional"))
    )
    (net (code "2151") (name "ZZ.11.025") (class "Default")
      (node (ref "U$3") (pin "P$103") (pinfunction "D13_P$103") (pintype "bidirectional"))
    )
    (net (code "2152") (name "ZZ.11.026") (class "Default")
      (node (ref "U$3") (pin "P$163") (pinfunction "F13_P$163") (pintype "bidirectional"))
    )
    (net (code "2153") (name "ZZ.11.027") (class "Default")
      (node (ref "U$3") (pin "P$164") (pinfunction "F14_P$164") (pintype "bidirectional"))
    )
    (net (code "2154") (name "ZZ.11.028") (class "Default")
      (node (ref "U$3") (pin "P$44") (pinfunction "B14_P$44") (pintype "bidirectional"))
    )
    (net (code "2155") (name "ZZ.11.029") (class "Default")
      (node (ref "U$3") (pin "P$74") (pinfunction "C14_P$74") (pintype "bidirectional"))
    )
    (net (code "2156") (name "ZZ.11.030") (class "Default")
      (node (ref "U$3") (pin "P$104") (pinfunction "D14_P$104") (pintype "bidirectional"))
    )
    (net (code "2157") (name "ZZ.11.031") (class "Default")
      (node (ref "U$3") (pin "P$134") (pinfunction "E14_P$134") (pintype "bidirectional"))
    )
    (net (code "2158") (name "ZZ.11.032") (class "Default")
      (node (ref "U$5") (pin "P$70") (pinfunction "C10_P$70") (pintype "bidirectional"))
    )
    (net (code "2159") (name "ZZ.11.033") (class "Default")
      (node (ref "U$5") (pin "P$130") (pinfunction "E10_P$130") (pintype "bidirectional"))
    )
    (net (code "2160") (name "ZZ.11.034") (class "Default")
      (node (ref "U$5") (pin "P$129") (pinfunction "E9_P$129") (pintype "bidirectional"))
    )
    (net (code "2161") (name "ZZ.11.035") (class "Default")
      (node (ref "U$5") (pin "P$71") (pinfunction "C11_P$71") (pintype "bidirectional"))
    )
    (net (code "2162") (name "ZZ.11.036") (class "Default")
      (node (ref "U$5") (pin "P$131") (pinfunction "E11_P$131") (pintype "bidirectional"))
    )
    (net (code "2163") (name "ZZ.11.037") (class "Default")
      (node (ref "U$5") (pin "P$161") (pinfunction "F11_P$161") (pintype "bidirectional"))
    )
    (net (code "2164") (name "ZZ.11.038") (class "Default")
      (node (ref "U$5") (pin "P$72") (pinfunction "C12_P$72") (pintype "bidirectional"))
    )
    (net (code "2165") (name "ZZ.11.039") (class "Default")
      (node (ref "U$5") (pin "P$132") (pinfunction "E12_P$132") (pintype "bidirectional"))
    )
    (net (code "2166") (name "ZZ.11.040") (class "Default")
      (node (ref "U$5") (pin "P$73") (pinfunction "C13_P$73") (pintype "bidirectional"))
    )
    (net (code "2167") (name "ZZ.11.041") (class "Default")
      (node (ref "U$5") (pin "P$133") (pinfunction "E13_P$133") (pintype "bidirectional"))
    )
    (net (code "2168") (name "ZZ.11.042") (class "Default")
      (node (ref "U$5") (pin "P$44") (pinfunction "B14_P$44") (pintype "bidirectional"))
    )
    (net (code "2169") (name "ZZ.11.043") (class "Default")
      (node (ref "U$5") (pin "P$74") (pinfunction "C14_P$74") (pintype "bidirectional"))
    )
    (net (code "2170") (name "ZZ.11.044") (class "Default")
      (node (ref "U$5") (pin "P$104") (pinfunction "D14_P$104") (pintype "bidirectional"))
    )
    (net (code "2171") (name "ZZ.11.045") (class "Default")
      (node (ref "U$5") (pin "P$134") (pinfunction "E14_P$134") (pintype "bidirectional"))
    )
    (net (code "2172") (name "ZZ.11.046") (class "Default")
      (node (ref "U$5") (pin "P$164") (pinfunction "F14_P$164") (pintype "bidirectional"))
    )
    (net (code "2173") (name "ZZ.11.047") (class "Default")
      (node (ref "U$5") (pin "P$163") (pinfunction "F13_P$163") (pintype "bidirectional"))
    )
    (net (code "2174") (name "ZZ.11.048") (class "Default")
      (node (ref "U$7") (pin "P$70") (pinfunction "C10_P$70") (pintype "bidirectional"))
    )
    (net (code "2175") (name "ZZ.11.049") (class "Default")
      (node (ref "U$7") (pin "P$130") (pinfunction "E10_P$130") (pintype "bidirectional"))
    )
    (net (code "2176") (name "ZZ.11.050") (class "Default")
      (node (ref "U$7") (pin "P$160") (pinfunction "F10_P$160") (pintype "bidirectional"))
    )
    (net (code "2177") (name "ZZ.11.051") (class "Default")
      (node (ref "U$7") (pin "P$71") (pinfunction "C11_P$71") (pintype "bidirectional"))
    )
    (net (code "2178") (name "ZZ.11.052") (class "Default")
      (node (ref "U$7") (pin "P$131") (pinfunction "E11_P$131") (pintype "bidirectional"))
    )
    (net (code "2179") (name "ZZ.11.053") (class "Default")
      (node (ref "U$7") (pin "P$161") (pinfunction "F11_P$161") (pintype "bidirectional"))
    )
    (net (code "2180") (name "ZZ.11.054") (class "Default")
      (node (ref "U$7") (pin "P$72") (pinfunction "C12_P$72") (pintype "bidirectional"))
    )
    (net (code "2181") (name "ZZ.11.055") (class "Default")
      (node (ref "U$7") (pin "P$43") (pinfunction "B13_P$43") (pintype "bidirectional"))
    )
    (net (code "2182") (name "ZZ.11.056") (class "Default")
      (node (ref "U$7") (pin "P$44") (pinfunction "B14_P$44") (pintype "bidirectional"))
    )
    (net (code "2183") (name "ZZ.11.057") (class "Default")
      (node (ref "U$7") (pin "P$74") (pinfunction "C14_P$74") (pintype "bidirectional"))
    )
    (net (code "2184") (name "ZZ.11.058") (class "Default")
      (node (ref "U$7") (pin "P$104") (pinfunction "D14_P$104") (pintype "bidirectional"))
    )
    (net (code "2185") (name "ZZ.11.059") (class "Default")
      (node (ref "U$7") (pin "P$134") (pinfunction "E14_P$134") (pintype "bidirectional"))
    )
    (net (code "2186") (name "ZZ.11.060") (class "Default")
      (node (ref "U$7") (pin "P$164") (pinfunction "F14_P$164") (pintype "bidirectional"))
    )
    (net (code "2187") (name "ZZ.11.061") (class "Default")
      (node (ref "U$7") (pin "P$133") (pinfunction "E13_P$133") (pintype "bidirectional"))
    )
    (net (code "2188") (name "ZZ.11.062") (class "Default")
      (node (ref "U$7") (pin "P$163") (pinfunction "F13_P$163") (pintype "bidirectional"))
    )
    (net (code "2189") (name "ZZ.11.063") (class "Default")
      (node (ref "U$7") (pin "P$132") (pinfunction "E12_P$132") (pintype "bidirectional"))
    )
    (net (code "2190") (name "ZZ.11.064") (class "Default")
      (node (ref "U$9") (pin "P$70") (pinfunction "C10_P$70") (pintype "bidirectional"))
    )
    (net (code "2191") (name "ZZ.11.065") (class "Default")
      (node (ref "U$9") (pin "P$100") (pinfunction "D10_P$100") (pintype "bidirectional"))
    )
    (net (code "2192") (name "ZZ.11.066") (class "Default")
      (node (ref "U$9") (pin "P$160") (pinfunction "F10_P$160") (pintype "bidirectional"))
    )
    (net (code "2193") (name "ZZ.11.067") (class "Default")
      (node (ref "U$9") (pin "P$71") (pinfunction "C11_P$71") (pintype "bidirectional"))
    )
    (net (code "2194") (name "ZZ.11.068") (class "Default")
      (node (ref "U$9") (pin "P$72") (pinfunction "C12_P$72") (pintype "bidirectional"))
    )
    (net (code "2195") (name "ZZ.11.069") (class "Default")
      (node (ref "U$9") (pin "P$43") (pinfunction "B13_P$43") (pintype "bidirectional"))
    )
    (net (code "2196") (name "ZZ.11.070") (class "Default")
      (node (ref "U$9") (pin "P$44") (pinfunction "B14_P$44") (pintype "bidirectional"))
    )
    (net (code "2197") (name "ZZ.11.071") (class "Default")
      (node (ref "U$9") (pin "P$74") (pinfunction "C14_P$74") (pintype "bidirectional"))
    )
    (net (code "2198") (name "ZZ.11.072") (class "Default")
      (node (ref "U$9") (pin "P$104") (pinfunction "D14_P$104") (pintype "bidirectional"))
    )
    (net (code "2199") (name "ZZ.11.073") (class "Default")
      (node (ref "U$9") (pin "P$134") (pinfunction "E14_P$134") (pintype "bidirectional"))
    )
    (net (code "2200") (name "ZZ.11.074") (class "Default")
      (node (ref "U$9") (pin "P$164") (pinfunction "F14_P$164") (pintype "bidirectional"))
    )
    (net (code "2201") (name "ZZ.11.075") (class "Default")
      (node (ref "U$9") (pin "P$103") (pinfunction "D13_P$103") (pintype "bidirectional"))
    )
    (net (code "2202") (name "ZZ.11.076") (class "Default")
      (node (ref "U$9") (pin "P$163") (pinfunction "F13_P$163") (pintype "bidirectional"))
    )
    (net (code "2203") (name "ZZ.11.077") (class "Default")
      (node (ref "U$9") (pin "P$162") (pinfunction "F12_P$162") (pintype "bidirectional"))
    )
    (net (code "2204") (name "ZZ.11.078") (class "Default")
      (node (ref "U$9") (pin "P$101") (pinfunction "D11_P$101") (pintype "bidirectional"))
    )
    (net (code "2205") (name "ZZ.11.079") (class "Default")
      (node (ref "U$9") (pin "P$161") (pinfunction "F11_P$161") (pintype "bidirectional"))
    )
    (net (code "2206") (name "ZZ.11.080") (class "Default")
      (node (ref "U$11") (pin "P$41") (pinfunction "B11_P$41") (pintype "bidirectional"))
    )
    (net (code "2207") (name "ZZ.11.081") (class "Default")
      (node (ref "U$11") (pin "P$72") (pinfunction "C12_P$72") (pintype "bidirectional"))
    )
    (net (code "2208") (name "ZZ.11.082") (class "Default")
      (node (ref "U$11") (pin "P$43") (pinfunction "B13_P$43") (pintype "bidirectional"))
    )
    (net (code "2209") (name "ZZ.11.083") (class "Default")
      (node (ref "U$11") (pin "P$44") (pinfunction "B14_P$44") (pintype "bidirectional"))
    )
    (net (code "2210") (name "ZZ.11.084") (class "Default")
      (node (ref "U$11") (pin "P$74") (pinfunction "C14_P$74") (pintype "bidirectional"))
    )
    (net (code "2211") (name "ZZ.11.085") (class "Default")
      (node (ref "U$11") (pin "P$104") (pinfunction "D14_P$104") (pintype "bidirectional"))
    )
    (net (code "2212") (name "ZZ.11.086") (class "Default")
      (node (ref "U$11") (pin "P$134") (pinfunction "E14_P$134") (pintype "bidirectional"))
    )
    (net (code "2213") (name "ZZ.11.087") (class "Default")
      (node (ref "U$11") (pin "P$164") (pinfunction "F14_P$164") (pintype "bidirectional"))
    )
    (net (code "2214") (name "ZZ.11.088") (class "Default")
      (node (ref "U$11") (pin "P$133") (pinfunction "E13_P$133") (pintype "bidirectional"))
    )
    (net (code "2215") (name "ZZ.11.089") (class "Default")
      (node (ref "U$11") (pin "P$159") (pinfunction "F9_P$159") (pintype "bidirectional"))
    )
    (net (code "2216") (name "ZZ.11.090") (class "Default")
      (node (ref "U$11") (pin "P$132") (pinfunction "E12_P$132") (pintype "bidirectional"))
    )
    (net (code "2217") (name "ZZ.11.091") (class "Default")
      (node (ref "U$11") (pin "P$101") (pinfunction "D11_P$101") (pintype "bidirectional"))
    )
    (net (code "2218") (name "ZZ.11.092") (class "Default")
      (node (ref "U$11") (pin "P$131") (pinfunction "E11_P$131") (pintype "bidirectional"))
    )
    (net (code "2219") (name "ZZ.11.093") (class "Default")
      (node (ref "U$11") (pin "P$70") (pinfunction "C10_P$70") (pintype "bidirectional"))
    )
    (net (code "2220") (name "ZZ.11.094") (class "Default")
      (node (ref "U$11") (pin "P$130") (pinfunction "E10_P$130") (pintype "bidirectional"))
    )
    (net (code "2221") (name "ZZ.11.095") (class "Default")
      (node (ref "U$11") (pin "P$160") (pinfunction "F10_P$160") (pintype "bidirectional"))
    )
    (net (code "2222") (name "ZZ.11.096") (class "Default")
      (node (ref "U$13") (pin "P$43") (pinfunction "B13_P$43") (pintype "bidirectional"))
    )
    (net (code "2223") (name "ZZ.11.097") (class "Default")
      (node (ref "U$13") (pin "P$44") (pinfunction "B14_P$44") (pintype "bidirectional"))
    )
    (net (code "2224") (name "ZZ.11.098") (class "Default")
      (node (ref "U$13") (pin "P$74") (pinfunction "C14_P$74") (pintype "bidirectional"))
    )
    (net (code "2225") (name "ZZ.11.099") (class "Default")
      (node (ref "U$13") (pin "P$104") (pinfunction "D14_P$104") (pintype "bidirectional"))
    )
    (net (code "2226") (name "ZZ.11.100") (class "Default")
      (node (ref "U$13") (pin "P$134") (pinfunction "E14_P$134") (pintype "bidirectional"))
    )
    (net (code "2227") (name "ZZ.11.101") (class "Default")
      (node (ref "U$13") (pin "P$164") (pinfunction "F14_P$164") (pintype "bidirectional"))
    )
    (net (code "2228") (name "ZZ.11.102") (class "Default")
      (node (ref "U$13") (pin "P$103") (pinfunction "D13_P$103") (pintype "bidirectional"))
    )
    (net (code "2229") (name "ZZ.11.103") (class "Default")
      (node (ref "U$13") (pin "P$163") (pinfunction "F13_P$163") (pintype "bidirectional"))
    )
    (net (code "2230") (name "ZZ.11.104") (class "Default")
      (node (ref "U$13") (pin "P$42") (pinfunction "B12_P$42") (pintype "bidirectional"))
    )
    (net (code "2231") (name "ZZ.11.105") (class "Default")
      (node (ref "U$13") (pin "P$132") (pinfunction "E12_P$132") (pintype "bidirectional"))
    )
    (net (code "2232") (name "ZZ.11.106") (class "Default")
      (node (ref "U$13") (pin "P$162") (pinfunction "F12_P$162") (pintype "bidirectional"))
    )
    (net (code "2233") (name "ZZ.11.107") (class "Default")
      (node (ref "U$13") (pin "P$101") (pinfunction "D11_P$101") (pintype "bidirectional"))
    )
    (net (code "2234") (name "ZZ.11.108") (class "Default")
      (node (ref "U$13") (pin "P$161") (pinfunction "F11_P$161") (pintype "bidirectional"))
    )
    (net (code "2235") (name "ZZ.11.109") (class "Default")
      (node (ref "U$13") (pin "P$70") (pinfunction "C10_P$70") (pintype "bidirectional"))
    )
    (net (code "2236") (name "ZZ.11.110") (class "Default")
      (node (ref "U$13") (pin "P$100") (pinfunction "D10_P$100") (pintype "bidirectional"))
    )
    (net (code "2237") (name "ZZ.11.111") (class "Default")
      (node (ref "U$13") (pin "P$160") (pinfunction "F10_P$160") (pintype "bidirectional"))
    )
    (net (code "2238") (name "ZZ.11.112") (class "Default")
      (node (ref "U$15") (pin "P$74") (pinfunction "C14_P$74") (pintype "bidirectional"))
    )
    (net (code "2239") (name "ZZ.11.113") (class "Default")
      (node (ref "U$15") (pin "P$104") (pinfunction "D14_P$104") (pintype "bidirectional"))
    )
    (net (code "2240") (name "ZZ.11.114") (class "Default")
      (node (ref "U$15") (pin "P$134") (pinfunction "E14_P$134") (pintype "bidirectional"))
    )
    (net (code "2241") (name "ZZ.11.115") (class "Default")
      (node (ref "U$15") (pin "P$164") (pinfunction "F14_P$164") (pintype "bidirectional"))
    )
    (net (code "2242") (name "ZZ.11.116") (class "Default")
      (node (ref "U$15") (pin "P$45") (pinfunction "B15_P$45") (pintype "bidirectional"))
    )
    (net (code "2243") (name "ZZ.11.117") (class "Default")
      (node (ref "U$15") (pin "P$73") (pinfunction "C13_P$73") (pintype "bidirectional"))
    )
    (net (code "2244") (name "ZZ.11.118") (class "Default")
      (node (ref "U$15") (pin "P$103") (pinfunction "D13_P$103") (pintype "bidirectional"))
    )
    (net (code "2245") (name "ZZ.11.119") (class "Default")
      (node (ref "U$15") (pin "P$163") (pinfunction "F13_P$163") (pintype "bidirectional"))
    )
    (net (code "2246") (name "ZZ.11.120") (class "Default")
      (node (ref "U$15") (pin "P$42") (pinfunction "B12_P$42") (pintype "bidirectional"))
    )
    (net (code "2247") (name "ZZ.11.121") (class "Default")
      (node (ref "U$15") (pin "P$132") (pinfunction "E12_P$132") (pintype "bidirectional"))
    )
    (net (code "2248") (name "ZZ.11.122") (class "Default")
      (node (ref "U$15") (pin "P$162") (pinfunction "F12_P$162") (pintype "bidirectional"))
    )
    (net (code "2249") (name "ZZ.11.123") (class "Default")
      (node (ref "U$15") (pin "P$101") (pinfunction "D11_P$101") (pintype "bidirectional"))
    )
    (net (code "2250") (name "ZZ.11.124") (class "Default")
      (node (ref "U$15") (pin "P$131") (pinfunction "E11_P$131") (pintype "bidirectional"))
    )
    (net (code "2251") (name "ZZ.11.125") (class "Default")
      (node (ref "U$15") (pin "P$70") (pinfunction "C10_P$70") (pintype "bidirectional"))
    )
    (net (code "2252") (name "ZZ.11.126") (class "Default")
      (node (ref "U$15") (pin "P$130") (pinfunction "E10_P$130") (pintype "bidirectional"))
    )
    (net (code "2253") (name "ZZ.11.127") (class "Default")
      (node (ref "U$15") (pin "P$160") (pinfunction "F10_P$160") (pintype "bidirectional"))
    )
    (net (code "2254") (name "ZZ.11.128") (class "Default")
      (node (ref "U$17") (pin "P$164") (pinfunction "F14_P$164") (pintype "bidirectional"))
    )
    (net (code "2255") (name "ZZ.11.129") (class "Default")
      (node (ref "U$17") (pin "P$45") (pinfunction "B15_P$45") (pintype "bidirectional"))
    )
    (net (code "2256") (name "ZZ.11.130") (class "Default")
      (node (ref "U$17") (pin "P$105") (pinfunction "D15_P$105") (pintype "bidirectional"))
    )
    (net (code "2257") (name "ZZ.11.131") (class "Default")
      (node (ref "U$17") (pin "P$44") (pinfunction "B14_P$44") (pintype "bidirectional"))
    )
    (net (code "2258") (name "ZZ.11.132") (class "Default")
      (node (ref "U$17") (pin "P$104") (pinfunction "D14_P$104") (pintype "bidirectional"))
    )
    (net (code "2259") (name "ZZ.11.133") (class "Default")
      (node (ref "U$17") (pin "P$43") (pinfunction "B13_P$43") (pintype "bidirectional"))
    )
    (net (code "2260") (name "ZZ.11.134") (class "Default")
      (node (ref "U$17") (pin "P$133") (pinfunction "E13_P$133") (pintype "bidirectional"))
    )
    (net (code "2261") (name "ZZ.11.135") (class "Default")
      (node (ref "U$17") (pin "P$159") (pinfunction "F9_P$159") (pintype "bidirectional"))
    )
    (net (code "2262") (name "ZZ.11.136") (class "Default")
      (node (ref "U$17") (pin "P$42") (pinfunction "B12_P$42") (pintype "bidirectional"))
    )
    (net (code "2263") (name "ZZ.11.137") (class "Default")
      (node (ref "U$17") (pin "P$102") (pinfunction "D12_P$102") (pintype "bidirectional"))
    )
    (net (code "2264") (name "ZZ.11.138") (class "Default")
      (node (ref "U$17") (pin "P$162") (pinfunction "F12_P$162") (pintype "bidirectional"))
    )
    (net (code "2265") (name "ZZ.11.139") (class "Default")
      (node (ref "U$17") (pin "P$101") (pinfunction "D11_P$101") (pintype "bidirectional"))
    )
    (net (code "2266") (name "ZZ.11.140") (class "Default")
      (node (ref "U$17") (pin "P$131") (pinfunction "E11_P$131") (pintype "bidirectional"))
    )
    (net (code "2267") (name "ZZ.11.141") (class "Default")
      (node (ref "U$17") (pin "P$70") (pinfunction "C10_P$70") (pintype "bidirectional"))
    )
    (net (code "2268") (name "ZZ.11.142") (class "Default")
      (node (ref "U$17") (pin "P$100") (pinfunction "D10_P$100") (pintype "bidirectional"))
    )
    (net (code "2269") (name "ZZ.11.143") (class "Default")
      (node (ref "U$17") (pin "P$129") (pinfunction "E9_P$129") (pintype "bidirectional"))
    )
    (net (code "2270") (name "ZZ.11.144") (class "Default")
      (node (ref "U$19") (pin "P$75") (pinfunction "C15_P$75") (pintype "bidirectional"))
    )
    (net (code "2271") (name "ZZ.11.145") (class "Default")
      (node (ref "U$19") (pin "P$105") (pinfunction "D15_P$105") (pintype "bidirectional"))
    )
    (net (code "2272") (name "ZZ.11.146") (class "Default")
      (node (ref "U$19") (pin "P$165") (pinfunction "F15_P$165") (pintype "bidirectional"))
    )
    (net (code "2273") (name "ZZ.11.147") (class "Default")
      (node (ref "U$19") (pin "P$104") (pinfunction "D14_P$104") (pintype "bidirectional"))
    )
    (net (code "2274") (name "ZZ.11.148") (class "Default")
      (node (ref "U$19") (pin "P$164") (pinfunction "F14_P$164") (pintype "bidirectional"))
    )
    (net (code "2275") (name "ZZ.11.149") (class "Default")
      (node (ref "U$19") (pin "P$73") (pinfunction "C13_P$73") (pintype "bidirectional"))
    )
    (net (code "2276") (name "ZZ.11.150") (class "Default")
      (node (ref "U$19") (pin "P$103") (pinfunction "D13_P$103") (pintype "bidirectional"))
    )
    (net (code "2277") (name "ZZ.11.151") (class "Default")
      (node (ref "U$19") (pin "P$163") (pinfunction "F13_P$163") (pintype "bidirectional"))
    )
    (net (code "2278") (name "ZZ.11.152") (class "Default")
      (node (ref "U$19") (pin "P$42") (pinfunction "B12_P$42") (pintype "bidirectional"))
    )
    (net (code "2279") (name "ZZ.11.153") (class "Default")
      (node (ref "U$19") (pin "P$102") (pinfunction "D12_P$102") (pintype "bidirectional"))
    )
    (net (code "2280") (name "ZZ.11.154") (class "Default")
      (node (ref "U$19") (pin "P$162") (pinfunction "F12_P$162") (pintype "bidirectional"))
    )
    (net (code "2281") (name "ZZ.11.155") (class "Default")
      (node (ref "U$19") (pin "P$101") (pinfunction "D11_P$101") (pintype "bidirectional"))
    )
    (net (code "2282") (name "ZZ.11.156") (class "Default")
      (node (ref "U$19") (pin "P$131") (pinfunction "E11_P$131") (pintype "bidirectional"))
    )
    (net (code "2283") (name "ZZ.11.157") (class "Default")
      (node (ref "U$19") (pin "P$70") (pinfunction "C10_P$70") (pintype "bidirectional"))
    )
    (net (code "2284") (name "ZZ.11.158") (class "Default")
      (node (ref "U$19") (pin "P$100") (pinfunction "D10_P$100") (pintype "bidirectional"))
    )
    (net (code "2285") (name "ZZ.11.159") (class "Default")
      (node (ref "U$19") (pin "P$160") (pinfunction "F10_P$160") (pintype "bidirectional"))
    )
    (net (code "2286") (name "ZZ.11.160") (class "Default")
      (node (ref "U$21") (pin "P$45") (pinfunction "B15_P$45") (pintype "bidirectional"))
    )
    (net (code "2287") (name "ZZ.11.161") (class "Default")
      (node (ref "U$21") (pin "P$105") (pinfunction "D15_P$105") (pintype "bidirectional"))
    )
    (net (code "2288") (name "ZZ.11.162") (class "Default")
      (node (ref "U$21") (pin "P$165") (pinfunction "F15_P$165") (pintype "bidirectional"))
    )
    (net (code "2289") (name "ZZ.11.163") (class "Default")
      (node (ref "U$21") (pin "P$104") (pinfunction "D14_P$104") (pintype "bidirectional"))
    )
    (net (code "2290") (name "ZZ.11.164") (class "Default")
      (node (ref "U$21") (pin "P$134") (pinfunction "E14_P$134") (pintype "bidirectional"))
    )
    (net (code "2291") (name "ZZ.11.165") (class "Default")
      (node (ref "U$21") (pin "P$43") (pinfunction "B13_P$43") (pintype "bidirectional"))
    )
    (net (code "2292") (name "ZZ.11.166") (class "Default")
      (node (ref "U$21") (pin "P$103") (pinfunction "D13_P$103") (pintype "bidirectional"))
    )
    (net (code "2293") (name "ZZ.11.167") (class "Default")
      (node (ref "U$21") (pin "P$163") (pinfunction "F13_P$163") (pintype "bidirectional"))
    )
    (net (code "2294") (name "ZZ.11.168") (class "Default")
      (node (ref "U$21") (pin "P$72") (pinfunction "C12_P$72") (pintype "bidirectional"))
    )
    (net (code "2295") (name "ZZ.11.169") (class "Default")
      (node (ref "U$21") (pin "P$132") (pinfunction "E12_P$132") (pintype "bidirectional"))
    )
    (net (code "2296") (name "ZZ.11.170") (class "Default")
      (node (ref "U$21") (pin "P$162") (pinfunction "F12_P$162") (pintype "bidirectional"))
    )
    (net (code "2297") (name "ZZ.11.171") (class "Default")
      (node (ref "U$21") (pin "P$71") (pinfunction "C11_P$71") (pintype "bidirectional"))
    )
    (net (code "2298") (name "ZZ.11.172") (class "Default")
      (node (ref "U$21") (pin "P$161") (pinfunction "F11_P$161") (pintype "bidirectional"))
    )
    (net (code "2299") (name "ZZ.11.173") (class "Default")
      (node (ref "U$21") (pin "P$70") (pinfunction "C10_P$70") (pintype "bidirectional"))
    )
    (net (code "2300") (name "ZZ.11.174") (class "Default")
      (node (ref "U$21") (pin "P$100") (pinfunction "D10_P$100") (pintype "bidirectional"))
    )
    (net (code "2301") (name "ZZ.11.175") (class "Default")
      (node (ref "U$21") (pin "P$160") (pinfunction "F10_P$160") (pintype "bidirectional"))
    )
    (net (code "2302") (name "ZZ.11.176") (class "Default")
      (node (ref "U$23") (pin "P$75") (pinfunction "C15_P$75") (pintype "bidirectional"))
    )
    (net (code "2303") (name "ZZ.11.177") (class "Default")
      (node (ref "U$23") (pin "P$105") (pinfunction "D15_P$105") (pintype "bidirectional"))
    )
    (net (code "2304") (name "ZZ.11.178") (class "Default")
      (node (ref "U$23") (pin "P$165") (pinfunction "F15_P$165") (pintype "bidirectional"))
    )
    (net (code "2305") (name "ZZ.11.179") (class "Default")
      (node (ref "U$23") (pin "P$104") (pinfunction "D14_P$104") (pintype "bidirectional"))
    )
    (net (code "2306") (name "ZZ.11.180") (class "Default")
      (node (ref "U$23") (pin "P$134") (pinfunction "E14_P$134") (pintype "bidirectional"))
    )
    (net (code "2307") (name "ZZ.11.181") (class "Default")
      (node (ref "U$23") (pin "P$43") (pinfunction "B13_P$43") (pintype "bidirectional"))
    )
    (net (code "2308") (name "ZZ.11.182") (class "Default")
      (node (ref "U$23") (pin "P$133") (pinfunction "E13_P$133") (pintype "bidirectional"))
    )
    (net (code "2309") (name "ZZ.11.183") (class "Default")
      (node (ref "U$23") (pin "P$163") (pinfunction "F13_P$163") (pintype "bidirectional"))
    )
    (net (code "2310") (name "ZZ.11.184") (class "Default")
      (node (ref "U$23") (pin "P$72") (pinfunction "C12_P$72") (pintype "bidirectional"))
    )
    (net (code "2311") (name "ZZ.11.185") (class "Default")
      (node (ref "U$23") (pin "P$132") (pinfunction "E12_P$132") (pintype "bidirectional"))
    )
    (net (code "2312") (name "ZZ.11.186") (class "Default")
      (node (ref "U$23") (pin "P$162") (pinfunction "F12_P$162") (pintype "bidirectional"))
    )
    (net (code "2313") (name "ZZ.11.187") (class "Default")
      (node (ref "U$23") (pin "P$71") (pinfunction "C11_P$71") (pintype "bidirectional"))
    )
    (net (code "2314") (name "ZZ.11.188") (class "Default")
      (node (ref "U$23") (pin "P$161") (pinfunction "F11_P$161") (pintype "bidirectional"))
    )
    (net (code "2315") (name "ZZ.11.189") (class "Default")
      (node (ref "U$23") (pin "P$70") (pinfunction "C10_P$70") (pintype "bidirectional"))
    )
    (net (code "2316") (name "ZZ.11.190") (class "Default")
      (node (ref "U$23") (pin "P$100") (pinfunction "D10_P$100") (pintype "bidirectional"))
    )
    (net (code "2317") (name "ZZ.11.191") (class "Default")
      (node (ref "U$23") (pin "P$160") (pinfunction "F10_P$160") (pintype "bidirectional"))
    )
    (net (code "2318") (name "ZZ.12.000") (class "Default")
      (node (ref "U$1") (pin "P$48") (pinfunction "B18_P$48") (pintype "bidirectional"))
    )
    (net (code "2319") (name "ZZ.12.001") (class "Default")
      (node (ref "U$1") (pin "P$50") (pinfunction "B20_P$50") (pintype "bidirectional"))
    )
    (net (code "2320") (name "ZZ.12.002") (class "Default")
      (node (ref "U$1") (pin "P$52") (pinfunction "B22_P$52") (pintype "bidirectional"))
    )
    (net (code "2321") (name "ZZ.12.003") (class "Default")
      (node (ref "U$1") (pin "P$78") (pinfunction "C18_P$78") (pintype "bidirectional"))
    )
    (net (code "2322") (name "ZZ.12.004") (class "Default")
      (node (ref "U$1") (pin "P$80") (pinfunction "C20_P$80") (pintype "bidirectional"))
    )
    (net (code "2323") (name "ZZ.12.005") (class "Default")
      (node (ref "U$1") (pin "P$82") (pinfunction "C22_P$82") (pintype "bidirectional"))
    )
    (net (code "2324") (name "ZZ.12.006") (class "Default")
      (node (ref "U$1") (pin "P$108") (pinfunction "D18_P$108") (pintype "bidirectional"))
    )
    (net (code "2325") (name "ZZ.12.007") (class "Default")
      (node (ref "U$1") (pin "P$110") (pinfunction "D20_P$110") (pintype "bidirectional"))
    )
    (net (code "2326") (name "ZZ.12.008") (class "Default")
      (node (ref "U$1") (pin "P$112") (pinfunction "D22_P$112") (pintype "bidirectional"))
    )
    (net (code "2327") (name "ZZ.12.009") (class "Default")
      (node (ref "U$1") (pin "P$171") (pinfunction "F21_P$171") (pintype "bidirectional"))
    )
    (net (code "2328") (name "ZZ.12.010") (class "Default")
      (node (ref "U$1") (pin "P$138") (pinfunction "E18_P$138") (pintype "bidirectional"))
    )
    (net (code "2329") (name "ZZ.12.011") (class "Default")
      (node (ref "U$3") (pin "P$48") (pinfunction "B18_P$48") (pintype "bidirectional"))
    )
    (net (code "2330") (name "ZZ.12.012") (class "Default")
      (node (ref "U$3") (pin "P$50") (pinfunction "B20_P$50") (pintype "bidirectional"))
    )
    (net (code "2331") (name "ZZ.12.013") (class "Default")
      (node (ref "U$3") (pin "P$52") (pinfunction "B22_P$52") (pintype "bidirectional"))
    )
    (net (code "2332") (name "ZZ.12.014") (class "Default")
      (node (ref "U$1") (pin "P$142") (pinfunction "E22_P$142") (pintype "bidirectional"))
    )
    (net (code "2333") (name "ZZ.12.015") (class "Default")
      (node (ref "U$1") (pin "P$137") (pinfunction "E17_P$137") (pintype "bidirectional"))
    )
    (net (code "2334") (name "ZZ.12.016") (class "Default")
      (node (ref "U$3") (pin "P$78") (pinfunction "C18_P$78") (pintype "bidirectional"))
    )
    (net (code "2335") (name "ZZ.12.017") (class "Default")
      (node (ref "U$3") (pin "P$80") (pinfunction "C20_P$80") (pintype "bidirectional"))
    )
    (net (code "2336") (name "ZZ.12.018") (class "Default")
      (node (ref "U$3") (pin "P$82") (pinfunction "C22_P$82") (pintype "bidirectional"))
    )
    (net (code "2337") (name "ZZ.12.019") (class "Default")
      (node (ref "U$1") (pin "P$172") (pinfunction "F22_P$172") (pintype "bidirectional"))
    )
    (net (code "2338") (name "ZZ.12.020") (class "Default")
      (node (ref "U$1") (pin "P$166") (pinfunction "F16_P$166") (pintype "bidirectional"))
    )
    (net (code "2339") (name "ZZ.12.021") (class "Default")
      (node (ref "U$1") (pin "P$136") (pinfunction "E16_P$136") (pintype "bidirectional"))
    )
    (net (code "2340") (name "ZZ.12.022") (class "Default")
      (node (ref "U$3") (pin "P$108") (pinfunction "D18_P$108") (pintype "bidirectional"))
    )
    (net (code "2341") (name "ZZ.12.023") (class "Default")
      (node (ref "U$3") (pin "P$110") (pinfunction "D20_P$110") (pintype "bidirectional"))
    )
    (net (code "2342") (name "ZZ.12.024") (class "Default")
      (node (ref "U$3") (pin "P$112") (pinfunction "D22_P$112") (pintype "bidirectional"))
    )
    (net (code "2343") (name "ZZ.12.025") (class "Default")
      (node (ref "U$3") (pin "P$171") (pinfunction "F21_P$171") (pintype "bidirectional"))
    )
    (net (code "2344") (name "ZZ.12.026") (class "Default")
      (node (ref "U$3") (pin "P$138") (pinfunction "E18_P$138") (pintype "bidirectional"))
    )
    (net (code "2345") (name "ZZ.12.027") (class "Default")
      (node (ref "U$5") (pin "P$48") (pinfunction "B18_P$48") (pintype "bidirectional"))
    )
    (net (code "2346") (name "ZZ.12.028") (class "Default")
      (node (ref "U$5") (pin "P$50") (pinfunction "B20_P$50") (pintype "bidirectional"))
    )
    (net (code "2347") (name "ZZ.12.029") (class "Default")
      (node (ref "U$5") (pin "P$52") (pinfunction "B22_P$52") (pintype "bidirectional"))
    )
    (net (code "2348") (name "ZZ.12.030") (class "Default")
      (node (ref "U$3") (pin "P$142") (pinfunction "E22_P$142") (pintype "bidirectional"))
    )
    (net (code "2349") (name "ZZ.12.031") (class "Default")
      (node (ref "U$3") (pin "P$137") (pinfunction "E17_P$137") (pintype "bidirectional"))
    )
    (net (code "2350") (name "ZZ.12.032") (class "Default")
      (node (ref "U$5") (pin "P$78") (pinfunction "C18_P$78") (pintype "bidirectional"))
    )
    (net (code "2351") (name "ZZ.12.033") (class "Default")
      (node (ref "U$5") (pin "P$80") (pinfunction "C20_P$80") (pintype "bidirectional"))
    )
    (net (code "2352") (name "ZZ.12.034") (class "Default")
      (node (ref "U$5") (pin "P$82") (pinfunction "C22_P$82") (pintype "bidirectional"))
    )
    (net (code "2353") (name "ZZ.12.035") (class "Default")
      (node (ref "U$3") (pin "P$172") (pinfunction "F22_P$172") (pintype "bidirectional"))
    )
    (net (code "2354") (name "ZZ.12.036") (class "Default")
      (node (ref "U$3") (pin "P$166") (pinfunction "F16_P$166") (pintype "bidirectional"))
    )
    (net (code "2355") (name "ZZ.12.037") (class "Default")
      (node (ref "U$3") (pin "P$136") (pinfunction "E16_P$136") (pintype "bidirectional"))
    )
    (net (code "2356") (name "ZZ.12.038") (class "Default")
      (node (ref "U$5") (pin "P$108") (pinfunction "D18_P$108") (pintype "bidirectional"))
    )
    (net (code "2357") (name "ZZ.12.039") (class "Default")
      (node (ref "U$5") (pin "P$110") (pinfunction "D20_P$110") (pintype "bidirectional"))
    )
    (net (code "2358") (name "ZZ.12.040") (class "Default")
      (node (ref "U$5") (pin "P$112") (pinfunction "D22_P$112") (pintype "bidirectional"))
    )
    (net (code "2359") (name "ZZ.12.041") (class "Default")
      (node (ref "U$5") (pin "P$171") (pinfunction "F21_P$171") (pintype "bidirectional"))
    )
    (net (code "2360") (name "ZZ.12.042") (class "Default")
      (node (ref "U$5") (pin "P$138") (pinfunction "E18_P$138") (pintype "bidirectional"))
    )
    (net (code "2361") (name "ZZ.12.043") (class "Default")
      (node (ref "U$7") (pin "P$48") (pinfunction "B18_P$48") (pintype "bidirectional"))
    )
    (net (code "2362") (name "ZZ.12.044") (class "Default")
      (node (ref "U$7") (pin "P$50") (pinfunction "B20_P$50") (pintype "bidirectional"))
    )
    (net (code "2363") (name "ZZ.12.045") (class "Default")
      (node (ref "U$7") (pin "P$52") (pinfunction "B22_P$52") (pintype "bidirectional"))
    )
    (net (code "2364") (name "ZZ.12.046") (class "Default")
      (node (ref "U$5") (pin "P$142") (pinfunction "E22_P$142") (pintype "bidirectional"))
    )
    (net (code "2365") (name "ZZ.12.047") (class "Default")
      (node (ref "U$5") (pin "P$137") (pinfunction "E17_P$137") (pintype "bidirectional"))
    )
    (net (code "2366") (name "ZZ.12.048") (class "Default")
      (node (ref "U$7") (pin "P$78") (pinfunction "C18_P$78") (pintype "bidirectional"))
    )
    (net (code "2367") (name "ZZ.12.049") (class "Default")
      (node (ref "U$7") (pin "P$80") (pinfunction "C20_P$80") (pintype "bidirectional"))
    )
    (net (code "2368") (name "ZZ.12.050") (class "Default")
      (node (ref "U$5") (pin "P$172") (pinfunction "F22_P$172") (pintype "bidirectional"))
    )
    (net (code "2369") (name "ZZ.12.051") (class "Default")
      (node (ref "U$5") (pin "P$166") (pinfunction "F16_P$166") (pintype "bidirectional"))
    )
    (net (code "2370") (name "ZZ.12.052") (class "Default")
      (node (ref "U$5") (pin "P$136") (pinfunction "E16_P$136") (pintype "bidirectional"))
    )
    (net (code "2371") (name "ZZ.12.053") (class "Default")
      (node (ref "U$7") (pin "P$108") (pinfunction "D18_P$108") (pintype "bidirectional"))
    )
    (net (code "2372") (name "ZZ.12.054") (class "Default")
      (node (ref "U$7") (pin "P$110") (pinfunction "D20_P$110") (pintype "bidirectional"))
    )
    (net (code "2373") (name "ZZ.12.055") (class "Default")
      (node (ref "U$7") (pin "P$112") (pinfunction "D22_P$112") (pintype "bidirectional"))
    )
    (net (code "2374") (name "ZZ.12.056") (class "Default")
      (node (ref "U$7") (pin "P$82") (pinfunction "C22_P$82") (pintype "bidirectional"))
    )
    (net (code "2375") (name "ZZ.12.057") (class "Default")
      (node (ref "U$7") (pin "P$171") (pinfunction "F21_P$171") (pintype "bidirectional"))
    )
    (net (code "2376") (name "ZZ.12.058") (class "Default")
      (node (ref "U$7") (pin "P$138") (pinfunction "E18_P$138") (pintype "bidirectional"))
    )
    (net (code "2377") (name "ZZ.12.059") (class "Default")
      (node (ref "U$9") (pin "P$48") (pinfunction "B18_P$48") (pintype "bidirectional"))
    )
    (net (code "2378") (name "ZZ.12.060") (class "Default")
      (node (ref "U$9") (pin "P$50") (pinfunction "B20_P$50") (pintype "bidirectional"))
    )
    (net (code "2379") (name "ZZ.12.061") (class "Default")
      (node (ref "U$7") (pin "P$142") (pinfunction "E22_P$142") (pintype "bidirectional"))
    )
    (net (code "2380") (name "ZZ.12.062") (class "Default")
      (node (ref "U$7") (pin "P$137") (pinfunction "E17_P$137") (pintype "bidirectional"))
    )
    (net (code "2381") (name "ZZ.12.063") (class "Default")
      (node (ref "U$9") (pin "P$78") (pinfunction "C18_P$78") (pintype "bidirectional"))
    )
    (net (code "2382") (name "ZZ.12.064") (class "Default")
      (node (ref "U$7") (pin "P$172") (pinfunction "F22_P$172") (pintype "bidirectional"))
    )
    (net (code "2383") (name "ZZ.12.065") (class "Default")
      (node (ref "U$7") (pin "P$166") (pinfunction "F16_P$166") (pintype "bidirectional"))
    )
    (net (code "2384") (name "ZZ.12.066") (class "Default")
      (node (ref "U$7") (pin "P$136") (pinfunction "E16_P$136") (pintype "bidirectional"))
    )
    (net (code "2385") (name "ZZ.12.067") (class "Default")
      (node (ref "U$9") (pin "P$108") (pinfunction "D18_P$108") (pintype "bidirectional"))
    )
    (net (code "2386") (name "ZZ.12.068") (class "Default")
      (node (ref "U$9") (pin "P$110") (pinfunction "D20_P$110") (pintype "bidirectional"))
    )
    (net (code "2387") (name "ZZ.12.069") (class "Default")
      (node (ref "U$9") (pin "P$112") (pinfunction "D22_P$112") (pintype "bidirectional"))
    )
    (net (code "2388") (name "ZZ.12.070") (class "Default")
      (node (ref "U$9") (pin "P$80") (pinfunction "C20_P$80") (pintype "bidirectional"))
    )
    (net (code "2389") (name "ZZ.12.071") (class "Default")
      (node (ref "U$9") (pin "P$82") (pinfunction "C22_P$82") (pintype "bidirectional"))
    )
    (net (code "2390") (name "ZZ.12.072") (class "Default")
      (node (ref "U$9") (pin "P$52") (pinfunction "B22_P$52") (pintype "bidirectional"))
    )
    (net (code "2391") (name "ZZ.12.073") (class "Default")
      (node (ref "U$9") (pin "P$171") (pinfunction "F21_P$171") (pintype "bidirectional"))
    )
    (net (code "2392") (name "ZZ.12.074") (class "Default")
      (node (ref "U$9") (pin "P$138") (pinfunction "E18_P$138") (pintype "bidirectional"))
    )
    (net (code "2393") (name "ZZ.12.075") (class "Default")
      (node (ref "U$9") (pin "P$142") (pinfunction "E22_P$142") (pintype "bidirectional"))
    )
    (net (code "2394") (name "ZZ.12.076") (class "Default")
      (node (ref "U$9") (pin "P$137") (pinfunction "E17_P$137") (pintype "bidirectional"))
    )
    (net (code "2395") (name "ZZ.12.077") (class "Default")
      (node (ref "U$9") (pin "P$172") (pinfunction "F22_P$172") (pintype "bidirectional"))
    )
    (net (code "2396") (name "ZZ.12.078") (class "Default")
      (node (ref "U$9") (pin "P$166") (pinfunction "F16_P$166") (pintype "bidirectional"))
    )
    (net (code "2397") (name "ZZ.12.079") (class "Default")
      (node (ref "U$9") (pin "P$136") (pinfunction "E16_P$136") (pintype "bidirectional"))
    )
    (net (code "2398") (name "ZZ.12.080") (class "Default")
      (node (ref "U$11") (pin "P$108") (pinfunction "D18_P$108") (pintype "bidirectional"))
    )
    (net (code "2399") (name "ZZ.12.081") (class "Default")
      (node (ref "U$11") (pin "P$110") (pinfunction "D20_P$110") (pintype "bidirectional"))
    )
    (net (code "2400") (name "ZZ.12.082") (class "Default")
      (node (ref "U$11") (pin "P$112") (pinfunction "D22_P$112") (pintype "bidirectional"))
    )
    (net (code "2401") (name "ZZ.12.083") (class "Default")
      (node (ref "U$11") (pin "P$78") (pinfunction "C18_P$78") (pintype "bidirectional"))
    )
    (net (code "2402") (name "ZZ.12.084") (class "Default")
      (node (ref "U$11") (pin "P$80") (pinfunction "C20_P$80") (pintype "bidirectional"))
    )
    (net (code "2403") (name "ZZ.12.085") (class "Default")
      (node (ref "U$11") (pin "P$82") (pinfunction "C22_P$82") (pintype "bidirectional"))
    )
    (net (code "2404") (name "ZZ.12.086") (class "Default")
      (node (ref "U$11") (pin "P$48") (pinfunction "B18_P$48") (pintype "bidirectional"))
    )
    (net (code "2405") (name "ZZ.12.087") (class "Default")
      (node (ref "U$11") (pin "P$50") (pinfunction "B20_P$50") (pintype "bidirectional"))
    )
    (net (code "2406") (name "ZZ.12.088") (class "Default")
      (node (ref "U$11") (pin "P$52") (pinfunction "B22_P$52") (pintype "bidirectional"))
    )
    (net (code "2407") (name "ZZ.12.089") (class "Default")
      (node (ref "U$11") (pin "P$142") (pinfunction "E22_P$142") (pintype "bidirectional"))
    )
    (net (code "2408") (name "ZZ.12.090") (class "Default")
      (node (ref "U$11") (pin "P$137") (pinfunction "E17_P$137") (pintype "bidirectional"))
    )
    (net (code "2409") (name "ZZ.12.091") (class "Default")
      (node (ref "U$11") (pin "P$172") (pinfunction "F22_P$172") (pintype "bidirectional"))
    )
    (net (code "2410") (name "ZZ.12.092") (class "Default")
      (node (ref "U$11") (pin "P$166") (pinfunction "F16_P$166") (pintype "bidirectional"))
    )
    (net (code "2411") (name "ZZ.12.093") (class "Default")
      (node (ref "U$11") (pin "P$136") (pinfunction "E16_P$136") (pintype "bidirectional"))
    )
    (net (code "2412") (name "ZZ.12.094") (class "Default")
      (node (ref "U$13") (pin "P$108") (pinfunction "D18_P$108") (pintype "bidirectional"))
    )
    (net (code "2413") (name "ZZ.12.095") (class "Default")
      (node (ref "U$13") (pin "P$110") (pinfunction "D20_P$110") (pintype "bidirectional"))
    )
    (net (code "2414") (name "ZZ.12.096") (class "Default")
      (node (ref "U$13") (pin "P$112") (pinfunction "D22_P$112") (pintype "bidirectional"))
    )
    (net (code "2415") (name "ZZ.12.097") (class "Default")
      (node (ref "U$13") (pin "P$78") (pinfunction "C18_P$78") (pintype "bidirectional"))
    )
    (net (code "2416") (name "ZZ.12.098") (class "Default")
      (node (ref "U$13") (pin "P$80") (pinfunction "C20_P$80") (pintype "bidirectional"))
    )
    (net (code "2417") (name "ZZ.12.099") (class "Default")
      (node (ref "U$13") (pin "P$82") (pinfunction "C22_P$82") (pintype "bidirectional"))
    )
    (net (code "2418") (name "ZZ.12.100") (class "Default")
      (node (ref "U$11") (pin "P$171") (pinfunction "F21_P$171") (pintype "bidirectional"))
    )
    (net (code "2419") (name "ZZ.12.101") (class "Default")
      (node (ref "U$11") (pin "P$138") (pinfunction "E18_P$138") (pintype "bidirectional"))
    )
    (net (code "2420") (name "ZZ.12.102") (class "Default")
      (node (ref "U$13") (pin "P$48") (pinfunction "B18_P$48") (pintype "bidirectional"))
    )
    (net (code "2421") (name "ZZ.12.103") (class "Default")
      (node (ref "U$13") (pin "P$50") (pinfunction "B20_P$50") (pintype "bidirectional"))
    )
    (net (code "2422") (name "ZZ.12.104") (class "Default")
      (node (ref "U$13") (pin "P$52") (pinfunction "B22_P$52") (pintype "bidirectional"))
    )
    (net (code "2423") (name "ZZ.12.105") (class "Default")
      (node (ref "U$13") (pin "P$172") (pinfunction "F22_P$172") (pintype "bidirectional"))
    )
    (net (code "2424") (name "ZZ.12.106") (class "Default")
      (node (ref "U$13") (pin "P$166") (pinfunction "F16_P$166") (pintype "bidirectional"))
    )
    (net (code "2425") (name "ZZ.12.107") (class "Default")
      (node (ref "U$13") (pin "P$136") (pinfunction "E16_P$136") (pintype "bidirectional"))
    )
    (net (code "2426") (name "ZZ.12.108") (class "Default")
      (node (ref "U$15") (pin "P$108") (pinfunction "D18_P$108") (pintype "bidirectional"))
    )
    (net (code "2427") (name "ZZ.12.109") (class "Default")
      (node (ref "U$15") (pin "P$110") (pinfunction "D20_P$110") (pintype "bidirectional"))
    )
    (net (code "2428") (name "ZZ.12.110") (class "Default")
      (node (ref "U$15") (pin "P$112") (pinfunction "D22_P$112") (pintype "bidirectional"))
    )
    (net (code "2429") (name "ZZ.12.111") (class "Default")
      (node (ref "U$13") (pin "P$142") (pinfunction "E22_P$142") (pintype "bidirectional"))
    )
    (net (code "2430") (name "ZZ.12.112") (class "Default")
      (node (ref "U$13") (pin "P$137") (pinfunction "E17_P$137") (pintype "bidirectional"))
    )
    (net (code "2431") (name "ZZ.12.113") (class "Default")
      (node (ref "U$15") (pin "P$78") (pinfunction "C18_P$78") (pintype "bidirectional"))
    )
    (net (code "2432") (name "ZZ.12.114") (class "Default")
      (node (ref "U$15") (pin "P$80") (pinfunction "C20_P$80") (pintype "bidirectional"))
    )
    (net (code "2433") (name "ZZ.12.115") (class "Default")
      (node (ref "U$15") (pin "P$82") (pinfunction "C22_P$82") (pintype "bidirectional"))
    )
    (net (code "2434") (name "ZZ.12.116") (class "Default")
      (node (ref "U$13") (pin "P$171") (pinfunction "F21_P$171") (pintype "bidirectional"))
    )
    (net (code "2435") (name "ZZ.12.117") (class "Default")
      (node (ref "U$13") (pin "P$138") (pinfunction "E18_P$138") (pintype "bidirectional"))
    )
    (net (code "2436") (name "ZZ.12.118") (class "Default")
      (node (ref "U$15") (pin "P$48") (pinfunction "B18_P$48") (pintype "bidirectional"))
    )
    (net (code "2437") (name "ZZ.12.119") (class "Default")
      (node (ref "U$15") (pin "P$50") (pinfunction "B20_P$50") (pintype "bidirectional"))
    )
    (net (code "2438") (name "ZZ.12.120") (class "Default")
      (node (ref "U$15") (pin "P$52") (pinfunction "B22_P$52") (pintype "bidirectional"))
    )
    (net (code "2439") (name "ZZ.12.121") (class "Default")
      (node (ref "U$15") (pin "P$172") (pinfunction "F22_P$172") (pintype "bidirectional"))
    )
    (net (code "2440") (name "ZZ.12.122") (class "Default")
      (node (ref "U$15") (pin "P$166") (pinfunction "F16_P$166") (pintype "bidirectional"))
    )
    (net (code "2441") (name "ZZ.12.123") (class "Default")
      (node (ref "U$15") (pin "P$136") (pinfunction "E16_P$136") (pintype "bidirectional"))
    )
    (net (code "2442") (name "ZZ.12.124") (class "Default")
      (node (ref "U$17") (pin "P$108") (pinfunction "D18_P$108") (pintype "bidirectional"))
    )
    (net (code "2443") (name "ZZ.12.125") (class "Default")
      (node (ref "U$17") (pin "P$110") (pinfunction "D20_P$110") (pintype "bidirectional"))
    )
    (net (code "2444") (name "ZZ.12.126") (class "Default")
      (node (ref "U$17") (pin "P$112") (pinfunction "D22_P$112") (pintype "bidirectional"))
    )
    (net (code "2445") (name "ZZ.12.127") (class "Default")
      (node (ref "U$15") (pin "P$142") (pinfunction "E22_P$142") (pintype "bidirectional"))
    )
    (net (code "2446") (name "ZZ.12.128") (class "Default")
      (node (ref "U$15") (pin "P$137") (pinfunction "E17_P$137") (pintype "bidirectional"))
    )
    (net (code "2447") (name "ZZ.12.129") (class "Default")
      (node (ref "U$17") (pin "P$78") (pinfunction "C18_P$78") (pintype "bidirectional"))
    )
    (net (code "2448") (name "ZZ.12.130") (class "Default")
      (node (ref "U$17") (pin "P$80") (pinfunction "C20_P$80") (pintype "bidirectional"))
    )
    (net (code "2449") (name "ZZ.12.131") (class "Default")
      (node (ref "U$17") (pin "P$82") (pinfunction "C22_P$82") (pintype "bidirectional"))
    )
    (net (code "2450") (name "ZZ.12.132") (class "Default")
      (node (ref "U$15") (pin "P$171") (pinfunction "F21_P$171") (pintype "bidirectional"))
    )
    (net (code "2451") (name "ZZ.12.133") (class "Default")
      (node (ref "U$15") (pin "P$138") (pinfunction "E18_P$138") (pintype "bidirectional"))
    )
    (net (code "2452") (name "ZZ.12.134") (class "Default")
      (node (ref "U$17") (pin "P$48") (pinfunction "B18_P$48") (pintype "bidirectional"))
    )
    (net (code "2453") (name "ZZ.12.135") (class "Default")
      (node (ref "U$17") (pin "P$50") (pinfunction "B20_P$50") (pintype "bidirectional"))
    )
    (net (code "2454") (name "ZZ.12.136") (class "Default")
      (node (ref "U$17") (pin "P$52") (pinfunction "B22_P$52") (pintype "bidirectional"))
    )
    (net (code "2455") (name "ZZ.12.137") (class "Default")
      (node (ref "U$17") (pin "P$172") (pinfunction "F22_P$172") (pintype "bidirectional"))
    )
    (net (code "2456") (name "ZZ.12.138") (class "Default")
      (node (ref "U$17") (pin "P$166") (pinfunction "F16_P$166") (pintype "bidirectional"))
    )
    (net (code "2457") (name "ZZ.12.139") (class "Default")
      (node (ref "U$17") (pin "P$136") (pinfunction "E16_P$136") (pintype "bidirectional"))
    )
    (net (code "2458") (name "ZZ.12.140") (class "Default")
      (node (ref "U$19") (pin "P$108") (pinfunction "D18_P$108") (pintype "bidirectional"))
    )
    (net (code "2459") (name "ZZ.12.141") (class "Default")
      (node (ref "U$19") (pin "P$110") (pinfunction "D20_P$110") (pintype "bidirectional"))
    )
    (net (code "2460") (name "ZZ.12.142") (class "Default")
      (node (ref "U$19") (pin "P$112") (pinfunction "D22_P$112") (pintype "bidirectional"))
    )
    (net (code "2461") (name "ZZ.12.143") (class "Default")
      (node (ref "U$17") (pin "P$142") (pinfunction "E22_P$142") (pintype "bidirectional"))
    )
    (net (code "2462") (name "ZZ.12.144") (class "Default")
      (node (ref "U$17") (pin "P$137") (pinfunction "E17_P$137") (pintype "bidirectional"))
    )
    (net (code "2463") (name "ZZ.12.145") (class "Default")
      (node (ref "U$19") (pin "P$78") (pinfunction "C18_P$78") (pintype "bidirectional"))
    )
    (net (code "2464") (name "ZZ.12.146") (class "Default")
      (node (ref "U$19") (pin "P$80") (pinfunction "C20_P$80") (pintype "bidirectional"))
    )
    (net (code "2465") (name "ZZ.12.147") (class "Default")
      (node (ref "U$19") (pin "P$82") (pinfunction "C22_P$82") (pintype "bidirectional"))
    )
    (net (code "2466") (name "ZZ.12.148") (class "Default")
      (node (ref "U$17") (pin "P$171") (pinfunction "F21_P$171") (pintype "bidirectional"))
    )
    (net (code "2467") (name "ZZ.12.149") (class "Default")
      (node (ref "U$17") (pin "P$138") (pinfunction "E18_P$138") (pintype "bidirectional"))
    )
    (net (code "2468") (name "ZZ.12.150") (class "Default")
      (node (ref "U$19") (pin "P$48") (pinfunction "B18_P$48") (pintype "bidirectional"))
    )
    (net (code "2469") (name "ZZ.12.151") (class "Default")
      (node (ref "U$19") (pin "P$50") (pinfunction "B20_P$50") (pintype "bidirectional"))
    )
    (net (code "2470") (name "ZZ.12.152") (class "Default")
      (node (ref "U$19") (pin "P$52") (pinfunction "B22_P$52") (pintype "bidirectional"))
    )
    (net (code "2471") (name "ZZ.12.153") (class "Default")
      (node (ref "U$19") (pin "P$172") (pinfunction "F22_P$172") (pintype "bidirectional"))
    )
    (net (code "2472") (name "ZZ.12.154") (class "Default")
      (node (ref "U$19") (pin "P$166") (pinfunction "F16_P$166") (pintype "bidirectional"))
    )
    (net (code "2473") (name "ZZ.12.155") (class "Default")
      (node (ref "U$19") (pin "P$136") (pinfunction "E16_P$136") (pintype "bidirectional"))
    )
    (net (code "2474") (name "ZZ.12.156") (class "Default")
      (node (ref "U$21") (pin "P$108") (pinfunction "D18_P$108") (pintype "bidirectional"))
    )
    (net (code "2475") (name "ZZ.12.157") (class "Default")
      (node (ref "U$21") (pin "P$110") (pinfunction "D20_P$110") (pintype "bidirectional"))
    )
    (net (code "2476") (name "ZZ.12.158") (class "Default")
      (node (ref "U$21") (pin "P$112") (pinfunction "D22_P$112") (pintype "bidirectional"))
    )
    (net (code "2477") (name "ZZ.12.159") (class "Default")
      (node (ref "U$19") (pin "P$142") (pinfunction "E22_P$142") (pintype "bidirectional"))
    )
    (net (code "2478") (name "ZZ.12.160") (class "Default")
      (node (ref "U$19") (pin "P$137") (pinfunction "E17_P$137") (pintype "bidirectional"))
    )
    (net (code "2479") (name "ZZ.12.161") (class "Default")
      (node (ref "U$21") (pin "P$78") (pinfunction "C18_P$78") (pintype "bidirectional"))
    )
    (net (code "2480") (name "ZZ.12.162") (class "Default")
      (node (ref "U$21") (pin "P$80") (pinfunction "C20_P$80") (pintype "bidirectional"))
    )
    (net (code "2481") (name "ZZ.12.163") (class "Default")
      (node (ref "U$21") (pin "P$82") (pinfunction "C22_P$82") (pintype "bidirectional"))
    )
    (net (code "2482") (name "ZZ.12.164") (class "Default")
      (node (ref "U$19") (pin "P$171") (pinfunction "F21_P$171") (pintype "bidirectional"))
    )
    (net (code "2483") (name "ZZ.12.165") (class "Default")
      (node (ref "U$19") (pin "P$138") (pinfunction "E18_P$138") (pintype "bidirectional"))
    )
    (net (code "2484") (name "ZZ.12.166") (class "Default")
      (node (ref "U$21") (pin "P$48") (pinfunction "B18_P$48") (pintype "bidirectional"))
    )
    (net (code "2485") (name "ZZ.12.167") (class "Default")
      (node (ref "U$21") (pin "P$50") (pinfunction "B20_P$50") (pintype "bidirectional"))
    )
    (net (code "2486") (name "ZZ.12.168") (class "Default")
      (node (ref "U$21") (pin "P$52") (pinfunction "B22_P$52") (pintype "bidirectional"))
    )
    (net (code "2487") (name "ZZ.12.169") (class "Default")
      (node (ref "U$21") (pin "P$172") (pinfunction "F22_P$172") (pintype "bidirectional"))
    )
    (net (code "2488") (name "ZZ.12.170") (class "Default")
      (node (ref "U$21") (pin "P$166") (pinfunction "F16_P$166") (pintype "bidirectional"))
    )
    (net (code "2489") (name "ZZ.12.171") (class "Default")
      (node (ref "U$21") (pin "P$136") (pinfunction "E16_P$136") (pintype "bidirectional"))
    )
    (net (code "2490") (name "ZZ.12.172") (class "Default")
      (node (ref "U$23") (pin "P$108") (pinfunction "D18_P$108") (pintype "bidirectional"))
    )
    (net (code "2491") (name "ZZ.12.173") (class "Default")
      (node (ref "U$23") (pin "P$110") (pinfunction "D20_P$110") (pintype "bidirectional"))
    )
    (net (code "2492") (name "ZZ.12.174") (class "Default")
      (node (ref "U$23") (pin "P$112") (pinfunction "D22_P$112") (pintype "bidirectional"))
    )
    (net (code "2493") (name "ZZ.12.175") (class "Default")
      (node (ref "U$21") (pin "P$142") (pinfunction "E22_P$142") (pintype "bidirectional"))
    )
    (net (code "2494") (name "ZZ.12.176") (class "Default")
      (node (ref "U$21") (pin "P$137") (pinfunction "E17_P$137") (pintype "bidirectional"))
    )
    (net (code "2495") (name "ZZ.12.177") (class "Default")
      (node (ref "U$23") (pin "P$78") (pinfunction "C18_P$78") (pintype "bidirectional"))
    )
    (net (code "2496") (name "ZZ.12.178") (class "Default")
      (node (ref "U$23") (pin "P$80") (pinfunction "C20_P$80") (pintype "bidirectional"))
    )
    (net (code "2497") (name "ZZ.12.179") (class "Default")
      (node (ref "U$23") (pin "P$82") (pinfunction "C22_P$82") (pintype "bidirectional"))
    )
    (net (code "2498") (name "ZZ.12.180") (class "Default")
      (node (ref "U$21") (pin "P$171") (pinfunction "F21_P$171") (pintype "bidirectional"))
    )
    (net (code "2499") (name "ZZ.12.181") (class "Default")
      (node (ref "U$21") (pin "P$138") (pinfunction "E18_P$138") (pintype "bidirectional"))
    )
    (net (code "2500") (name "ZZ.12.182") (class "Default")
      (node (ref "U$23") (pin "P$48") (pinfunction "B18_P$48") (pintype "bidirectional"))
    )
    (net (code "2501") (name "ZZ.12.183") (class "Default")
      (node (ref "U$23") (pin "P$50") (pinfunction "B20_P$50") (pintype "bidirectional"))
    )
    (net (code "2502") (name "ZZ.12.184") (class "Default")
      (node (ref "U$23") (pin "P$52") (pinfunction "B22_P$52") (pintype "bidirectional"))
    )
    (net (code "2503") (name "ZZ.12.185") (class "Default")
      (node (ref "U$23") (pin "P$172") (pinfunction "F22_P$172") (pintype "bidirectional"))
    )
    (net (code "2504") (name "ZZ.12.186") (class "Default")
      (node (ref "U$23") (pin "P$166") (pinfunction "F16_P$166") (pintype "bidirectional"))
    )
    (net (code "2505") (name "ZZ.12.187") (class "Default")
      (node (ref "U$23") (pin "P$136") (pinfunction "E16_P$136") (pintype "bidirectional"))
    )
    (net (code "2506") (name "ZZ.12.188") (class "Default")
      (node (ref "U$23") (pin "P$142") (pinfunction "E22_P$142") (pintype "bidirectional"))
    )
    (net (code "2507") (name "ZZ.12.189") (class "Default")
      (node (ref "U$23") (pin "P$137") (pinfunction "E17_P$137") (pintype "bidirectional"))
    )
    (net (code "2508") (name "ZZ.12.190") (class "Default")
      (node (ref "U$23") (pin "P$171") (pinfunction "F21_P$171") (pintype "bidirectional"))
    )
    (net (code "2509") (name "ZZ.12.191") (class "Default")
      (node (ref "U$23") (pin "P$138") (pinfunction "E18_P$138") (pintype "bidirectional"))
    )
    (net (code "2510") (name "ZZ.13.000") (class "Default")
      (node (ref "U$1") (pin "P$107") (pinfunction "D17_P$107") (pintype "bidirectional"))
    )
    (net (code "2511") (name "ZZ.13.001") (class "Default")
      (node (ref "U$1") (pin "P$109") (pinfunction "D19_P$109") (pintype "bidirectional"))
    )
    (net (code "2512") (name "ZZ.13.002") (class "Default")
      (node (ref "U$1") (pin "P$111") (pinfunction "D21_P$111") (pintype "bidirectional"))
    )
    (net (code "2513") (name "ZZ.13.003") (class "Default")
      (node (ref "U$1") (pin "P$77") (pinfunction "C17_P$77") (pintype "bidirectional"))
    )
    (net (code "2514") (name "ZZ.13.004") (class "Default")
      (node (ref "U$1") (pin "P$79") (pinfunction "C19_P$79") (pintype "bidirectional"))
    )
    (net (code "2515") (name "ZZ.13.005") (class "Default")
      (node (ref "U$1") (pin "P$81") (pinfunction "C21_P$81") (pintype "bidirectional"))
    )
    (net (code "2516") (name "ZZ.13.006") (class "Default")
      (node (ref "U$1") (pin "P$47") (pinfunction "B17_P$47") (pintype "bidirectional"))
    )
    (net (code "2517") (name "ZZ.13.007") (class "Default")
      (node (ref "U$1") (pin "P$49") (pinfunction "B19_P$49") (pintype "bidirectional"))
    )
    (net (code "2518") (name "ZZ.13.008") (class "Default")
      (node (ref "U$1") (pin "P$51") (pinfunction "B21_P$51") (pintype "bidirectional"))
    )
    (net (code "2519") (name "ZZ.13.009") (class "Default")
      (node (ref "U$1") (pin "P$141") (pinfunction "E21_P$141") (pintype "bidirectional"))
    )
    (net (code "2520") (name "ZZ.13.010") (class "Default")
      (node (ref "U$1") (pin "P$168") (pinfunction "F18_P$168") (pintype "bidirectional"))
    )
    (net (code "2521") (name "ZZ.13.011") (class "Default")
      (node (ref "U$3") (pin "P$107") (pinfunction "D17_P$107") (pintype "bidirectional"))
    )
    (net (code "2522") (name "ZZ.13.012") (class "Default")
      (node (ref "U$3") (pin "P$109") (pinfunction "D19_P$109") (pintype "bidirectional"))
    )
    (net (code "2523") (name "ZZ.13.013") (class "Default")
      (node (ref "U$3") (pin "P$111") (pinfunction "D21_P$111") (pintype "bidirectional"))
    )
    (net (code "2524") (name "ZZ.13.014") (class "Default")
      (node (ref "U$1") (pin "P$170") (pinfunction "F20_P$170") (pintype "bidirectional"))
    )
    (net (code "2525") (name "ZZ.13.015") (class "Default")
      (node (ref "U$1") (pin "P$139") (pinfunction "E19_P$139") (pintype "bidirectional"))
    )
    (net (code "2526") (name "ZZ.13.016") (class "Default")
      (node (ref "U$3") (pin "P$77") (pinfunction "C17_P$77") (pintype "bidirectional"))
    )
    (net (code "2527") (name "ZZ.13.017") (class "Default")
      (node (ref "U$3") (pin "P$79") (pinfunction "C19_P$79") (pintype "bidirectional"))
    )
    (net (code "2528") (name "ZZ.13.018") (class "Default")
      (node (ref "U$3") (pin "P$81") (pinfunction "C21_P$81") (pintype "bidirectional"))
    )
    (net (code "2529") (name "ZZ.13.019") (class "Default")
      (node (ref "U$1") (pin "P$140") (pinfunction "E20_P$140") (pintype "bidirectional"))
    )
    (net (code "2530") (name "ZZ.13.020") (class "Default")
      (node (ref "U$1") (pin "P$169") (pinfunction "F19_P$169") (pintype "bidirectional"))
    )
    (net (code "2531") (name "ZZ.13.021") (class "Default")
      (node (ref "U$1") (pin "P$167") (pinfunction "F17_P$167") (pintype "bidirectional"))
    )
    (net (code "2532") (name "ZZ.13.022") (class "Default")
      (node (ref "U$3") (pin "P$47") (pinfunction "B17_P$47") (pintype "bidirectional"))
    )
    (net (code "2533") (name "ZZ.13.023") (class "Default")
      (node (ref "U$3") (pin "P$49") (pinfunction "B19_P$49") (pintype "bidirectional"))
    )
    (net (code "2534") (name "ZZ.13.024") (class "Default")
      (node (ref "U$3") (pin "P$51") (pinfunction "B21_P$51") (pintype "bidirectional"))
    )
    (net (code "2535") (name "ZZ.13.025") (class "Default")
      (node (ref "U$3") (pin "P$141") (pinfunction "E21_P$141") (pintype "bidirectional"))
    )
    (net (code "2536") (name "ZZ.13.026") (class "Default")
      (node (ref "U$3") (pin "P$168") (pinfunction "F18_P$168") (pintype "bidirectional"))
    )
    (net (code "2537") (name "ZZ.13.027") (class "Default")
      (node (ref "U$5") (pin "P$107") (pinfunction "D17_P$107") (pintype "bidirectional"))
    )
    (net (code "2538") (name "ZZ.13.028") (class "Default")
      (node (ref "U$5") (pin "P$109") (pinfunction "D19_P$109") (pintype "bidirectional"))
    )
    (net (code "2539") (name "ZZ.13.029") (class "Default")
      (node (ref "U$5") (pin "P$111") (pinfunction "D21_P$111") (pintype "bidirectional"))
    )
    (net (code "2540") (name "ZZ.13.030") (class "Default")
      (node (ref "U$3") (pin "P$170") (pinfunction "F20_P$170") (pintype "bidirectional"))
    )
    (net (code "2541") (name "ZZ.13.031") (class "Default")
      (node (ref "U$3") (pin "P$139") (pinfunction "E19_P$139") (pintype "bidirectional"))
    )
    (net (code "2542") (name "ZZ.13.032") (class "Default")
      (node (ref "U$5") (pin "P$77") (pinfunction "C17_P$77") (pintype "bidirectional"))
    )
    (net (code "2543") (name "ZZ.13.033") (class "Default")
      (node (ref "U$5") (pin "P$79") (pinfunction "C19_P$79") (pintype "bidirectional"))
    )
    (net (code "2544") (name "ZZ.13.034") (class "Default")
      (node (ref "U$5") (pin "P$81") (pinfunction "C21_P$81") (pintype "bidirectional"))
    )
    (net (code "2545") (name "ZZ.13.035") (class "Default")
      (node (ref "U$3") (pin "P$140") (pinfunction "E20_P$140") (pintype "bidirectional"))
    )
    (net (code "2546") (name "ZZ.13.036") (class "Default")
      (node (ref "U$3") (pin "P$169") (pinfunction "F19_P$169") (pintype "bidirectional"))
    )
    (net (code "2547") (name "ZZ.13.037") (class "Default")
      (node (ref "U$3") (pin "P$167") (pinfunction "F17_P$167") (pintype "bidirectional"))
    )
    (net (code "2548") (name "ZZ.13.038") (class "Default")
      (node (ref "U$5") (pin "P$47") (pinfunction "B17_P$47") (pintype "bidirectional"))
    )
    (net (code "2549") (name "ZZ.13.039") (class "Default")
      (node (ref "U$5") (pin "P$49") (pinfunction "B19_P$49") (pintype "bidirectional"))
    )
    (net (code "2550") (name "ZZ.13.040") (class "Default")
      (node (ref "U$5") (pin "P$51") (pinfunction "B21_P$51") (pintype "bidirectional"))
    )
    (net (code "2551") (name "ZZ.13.041") (class "Default")
      (node (ref "U$5") (pin "P$141") (pinfunction "E21_P$141") (pintype "bidirectional"))
    )
    (net (code "2552") (name "ZZ.13.042") (class "Default")
      (node (ref "U$5") (pin "P$168") (pinfunction "F18_P$168") (pintype "bidirectional"))
    )
    (net (code "2553") (name "ZZ.13.043") (class "Default")
      (node (ref "U$7") (pin "P$107") (pinfunction "D17_P$107") (pintype "bidirectional"))
    )
    (net (code "2554") (name "ZZ.13.044") (class "Default")
      (node (ref "U$7") (pin "P$109") (pinfunction "D19_P$109") (pintype "bidirectional"))
    )
    (net (code "2555") (name "ZZ.13.045") (class "Default")
      (node (ref "U$7") (pin "P$111") (pinfunction "D21_P$111") (pintype "bidirectional"))
    )
    (net (code "2556") (name "ZZ.13.046") (class "Default")
      (node (ref "U$5") (pin "P$170") (pinfunction "F20_P$170") (pintype "bidirectional"))
    )
    (net (code "2557") (name "ZZ.13.047") (class "Default")
      (node (ref "U$5") (pin "P$139") (pinfunction "E19_P$139") (pintype "bidirectional"))
    )
    (net (code "2558") (name "ZZ.13.048") (class "Default")
      (node (ref "U$7") (pin "P$77") (pinfunction "C17_P$77") (pintype "bidirectional"))
    )
    (net (code "2559") (name "ZZ.13.049") (class "Default")
      (node (ref "U$7") (pin "P$79") (pinfunction "C19_P$79") (pintype "bidirectional"))
    )
    (net (code "2560") (name "ZZ.13.050") (class "Default")
      (node (ref "U$5") (pin "P$140") (pinfunction "E20_P$140") (pintype "bidirectional"))
    )
    (net (code "2561") (name "ZZ.13.051") (class "Default")
      (node (ref "U$5") (pin "P$169") (pinfunction "F19_P$169") (pintype "bidirectional"))
    )
    (net (code "2562") (name "ZZ.13.052") (class "Default")
      (node (ref "U$5") (pin "P$167") (pinfunction "F17_P$167") (pintype "bidirectional"))
    )
    (net (code "2563") (name "ZZ.13.053") (class "Default")
      (node (ref "U$7") (pin "P$47") (pinfunction "B17_P$47") (pintype "bidirectional"))
    )
    (net (code "2564") (name "ZZ.13.054") (class "Default")
      (node (ref "U$7") (pin "P$49") (pinfunction "B19_P$49") (pintype "bidirectional"))
    )
    (net (code "2565") (name "ZZ.13.055") (class "Default")
      (node (ref "U$7") (pin "P$51") (pinfunction "B21_P$51") (pintype "bidirectional"))
    )
    (net (code "2566") (name "ZZ.13.056") (class "Default")
      (node (ref "U$7") (pin "P$81") (pinfunction "C21_P$81") (pintype "bidirectional"))
    )
    (net (code "2567") (name "ZZ.13.057") (class "Default")
      (node (ref "U$7") (pin "P$141") (pinfunction "E21_P$141") (pintype "bidirectional"))
    )
    (net (code "2568") (name "ZZ.13.058") (class "Default")
      (node (ref "U$7") (pin "P$168") (pinfunction "F18_P$168") (pintype "bidirectional"))
    )
    (net (code "2569") (name "ZZ.13.059") (class "Default")
      (node (ref "U$9") (pin "P$107") (pinfunction "D17_P$107") (pintype "bidirectional"))
    )
    (net (code "2570") (name "ZZ.13.060") (class "Default")
      (node (ref "U$9") (pin "P$109") (pinfunction "D19_P$109") (pintype "bidirectional"))
    )
    (net (code "2571") (name "ZZ.13.061") (class "Default")
      (node (ref "U$7") (pin "P$170") (pinfunction "F20_P$170") (pintype "bidirectional"))
    )
    (net (code "2572") (name "ZZ.13.062") (class "Default")
      (node (ref "U$7") (pin "P$139") (pinfunction "E19_P$139") (pintype "bidirectional"))
    )
    (net (code "2573") (name "ZZ.13.063") (class "Default")
      (node (ref "U$9") (pin "P$77") (pinfunction "C17_P$77") (pintype "bidirectional"))
    )
    (net (code "2574") (name "ZZ.13.064") (class "Default")
      (node (ref "U$7") (pin "P$140") (pinfunction "E20_P$140") (pintype "bidirectional"))
    )
    (net (code "2575") (name "ZZ.13.065") (class "Default")
      (node (ref "U$7") (pin "P$169") (pinfunction "F19_P$169") (pintype "bidirectional"))
    )
    (net (code "2576") (name "ZZ.13.066") (class "Default")
      (node (ref "U$7") (pin "P$167") (pinfunction "F17_P$167") (pintype "bidirectional"))
    )
    (net (code "2577") (name "ZZ.13.067") (class "Default")
      (node (ref "U$9") (pin "P$47") (pinfunction "B17_P$47") (pintype "bidirectional"))
    )
    (net (code "2578") (name "ZZ.13.068") (class "Default")
      (node (ref "U$9") (pin "P$49") (pinfunction "B19_P$49") (pintype "bidirectional"))
    )
    (net (code "2579") (name "ZZ.13.069") (class "Default")
      (node (ref "U$9") (pin "P$51") (pinfunction "B21_P$51") (pintype "bidirectional"))
    )
    (net (code "2580") (name "ZZ.13.070") (class "Default")
      (node (ref "U$9") (pin "P$79") (pinfunction "C19_P$79") (pintype "bidirectional"))
    )
    (net (code "2581") (name "ZZ.13.071") (class "Default")
      (node (ref "U$9") (pin "P$81") (pinfunction "C21_P$81") (pintype "bidirectional"))
    )
    (net (code "2582") (name "ZZ.13.072") (class "Default")
      (node (ref "U$9") (pin "P$111") (pinfunction "D21_P$111") (pintype "bidirectional"))
    )
    (net (code "2583") (name "ZZ.13.073") (class "Default")
      (node (ref "U$9") (pin "P$141") (pinfunction "E21_P$141") (pintype "bidirectional"))
    )
    (net (code "2584") (name "ZZ.13.074") (class "Default")
      (node (ref "U$9") (pin "P$168") (pinfunction "F18_P$168") (pintype "bidirectional"))
    )
    (net (code "2585") (name "ZZ.13.075") (class "Default")
      (node (ref "U$9") (pin "P$170") (pinfunction "F20_P$170") (pintype "bidirectional"))
    )
    (net (code "2586") (name "ZZ.13.076") (class "Default")
      (node (ref "U$9") (pin "P$139") (pinfunction "E19_P$139") (pintype "bidirectional"))
    )
    (net (code "2587") (name "ZZ.13.077") (class "Default")
      (node (ref "U$9") (pin "P$140") (pinfunction "E20_P$140") (pintype "bidirectional"))
    )
    (net (code "2588") (name "ZZ.13.078") (class "Default")
      (node (ref "U$9") (pin "P$169") (pinfunction "F19_P$169") (pintype "bidirectional"))
    )
    (net (code "2589") (name "ZZ.13.079") (class "Default")
      (node (ref "U$9") (pin "P$167") (pinfunction "F17_P$167") (pintype "bidirectional"))
    )
    (net (code "2590") (name "ZZ.13.080") (class "Default")
      (node (ref "U$11") (pin "P$47") (pinfunction "B17_P$47") (pintype "bidirectional"))
    )
    (net (code "2591") (name "ZZ.13.081") (class "Default")
      (node (ref "U$11") (pin "P$49") (pinfunction "B19_P$49") (pintype "bidirectional"))
    )
    (net (code "2592") (name "ZZ.13.082") (class "Default")
      (node (ref "U$11") (pin "P$51") (pinfunction "B21_P$51") (pintype "bidirectional"))
    )
    (net (code "2593") (name "ZZ.13.083") (class "Default")
      (node (ref "U$11") (pin "P$77") (pinfunction "C17_P$77") (pintype "bidirectional"))
    )
    (net (code "2594") (name "ZZ.13.084") (class "Default")
      (node (ref "U$11") (pin "P$79") (pinfunction "C19_P$79") (pintype "bidirectional"))
    )
    (net (code "2595") (name "ZZ.13.085") (class "Default")
      (node (ref "U$11") (pin "P$81") (pinfunction "C21_P$81") (pintype "bidirectional"))
    )
    (net (code "2596") (name "ZZ.13.086") (class "Default")
      (node (ref "U$11") (pin "P$107") (pinfunction "D17_P$107") (pintype "bidirectional"))
    )
    (net (code "2597") (name "ZZ.13.087") (class "Default")
      (node (ref "U$11") (pin "P$109") (pinfunction "D19_P$109") (pintype "bidirectional"))
    )
    (net (code "2598") (name "ZZ.13.088") (class "Default")
      (node (ref "U$11") (pin "P$111") (pinfunction "D21_P$111") (pintype "bidirectional"))
    )
    (net (code "2599") (name "ZZ.13.089") (class "Default")
      (node (ref "U$11") (pin "P$170") (pinfunction "F20_P$170") (pintype "bidirectional"))
    )
    (net (code "2600") (name "ZZ.13.090") (class "Default")
      (node (ref "U$11") (pin "P$139") (pinfunction "E19_P$139") (pintype "bidirectional"))
    )
    (net (code "2601") (name "ZZ.13.091") (class "Default")
      (node (ref "U$11") (pin "P$140") (pinfunction "E20_P$140") (pintype "bidirectional"))
    )
    (net (code "2602") (name "ZZ.13.092") (class "Default")
      (node (ref "U$11") (pin "P$169") (pinfunction "F19_P$169") (pintype "bidirectional"))
    )
    (net (code "2603") (name "ZZ.13.093") (class "Default")
      (node (ref "U$11") (pin "P$167") (pinfunction "F17_P$167") (pintype "bidirectional"))
    )
    (net (code "2604") (name "ZZ.13.094") (class "Default")
      (node (ref "U$13") (pin "P$47") (pinfunction "B17_P$47") (pintype "bidirectional"))
    )
    (net (code "2605") (name "ZZ.13.095") (class "Default")
      (node (ref "U$13") (pin "P$49") (pinfunction "B19_P$49") (pintype "bidirectional"))
    )
    (net (code "2606") (name "ZZ.13.096") (class "Default")
      (node (ref "U$13") (pin "P$51") (pinfunction "B21_P$51") (pintype "bidirectional"))
    )
    (net (code "2607") (name "ZZ.13.097") (class "Default")
      (node (ref "U$13") (pin "P$77") (pinfunction "C17_P$77") (pintype "bidirectional"))
    )
    (net (code "2608") (name "ZZ.13.098") (class "Default")
      (node (ref "U$13") (pin "P$79") (pinfunction "C19_P$79") (pintype "bidirectional"))
    )
    (net (code "2609") (name "ZZ.13.099") (class "Default")
      (node (ref "U$13") (pin "P$81") (pinfunction "C21_P$81") (pintype "bidirectional"))
    )
    (net (code "2610") (name "ZZ.13.100") (class "Default")
      (node (ref "U$11") (pin "P$141") (pinfunction "E21_P$141") (pintype "bidirectional"))
    )
    (net (code "2611") (name "ZZ.13.101") (class "Default")
      (node (ref "U$11") (pin "P$168") (pinfunction "F18_P$168") (pintype "bidirectional"))
    )
    (net (code "2612") (name "ZZ.13.102") (class "Default")
      (node (ref "U$13") (pin "P$107") (pinfunction "D17_P$107") (pintype "bidirectional"))
    )
    (net (code "2613") (name "ZZ.13.103") (class "Default")
      (node (ref "U$13") (pin "P$109") (pinfunction "D19_P$109") (pintype "bidirectional"))
    )
    (net (code "2614") (name "ZZ.13.104") (class "Default")
      (node (ref "U$13") (pin "P$111") (pinfunction "D21_P$111") (pintype "bidirectional"))
    )
    (net (code "2615") (name "ZZ.13.105") (class "Default")
      (node (ref "U$13") (pin "P$140") (pinfunction "E20_P$140") (pintype "bidirectional"))
    )
    (net (code "2616") (name "ZZ.13.106") (class "Default")
      (node (ref "U$13") (pin "P$169") (pinfunction "F19_P$169") (pintype "bidirectional"))
    )
    (net (code "2617") (name "ZZ.13.107") (class "Default")
      (node (ref "U$13") (pin "P$167") (pinfunction "F17_P$167") (pintype "bidirectional"))
    )
    (net (code "2618") (name "ZZ.13.108") (class "Default")
      (node (ref "U$15") (pin "P$47") (pinfunction "B17_P$47") (pintype "bidirectional"))
    )
    (net (code "2619") (name "ZZ.13.109") (class "Default")
      (node (ref "U$15") (pin "P$49") (pinfunction "B19_P$49") (pintype "bidirectional"))
    )
    (net (code "2620") (name "ZZ.13.110") (class "Default")
      (node (ref "U$15") (pin "P$51") (pinfunction "B21_P$51") (pintype "bidirectional"))
    )
    (net (code "2621") (name "ZZ.13.111") (class "Default")
      (node (ref "U$13") (pin "P$170") (pinfunction "F20_P$170") (pintype "bidirectional"))
    )
    (net (code "2622") (name "ZZ.13.112") (class "Default")
      (node (ref "U$13") (pin "P$139") (pinfunction "E19_P$139") (pintype "bidirectional"))
    )
    (net (code "2623") (name "ZZ.13.113") (class "Default")
      (node (ref "U$15") (pin "P$77") (pinfunction "C17_P$77") (pintype "bidirectional"))
    )
    (net (code "2624") (name "ZZ.13.114") (class "Default")
      (node (ref "U$15") (pin "P$79") (pinfunction "C19_P$79") (pintype "bidirectional"))
    )
    (net (code "2625") (name "ZZ.13.115") (class "Default")
      (node (ref "U$15") (pin "P$81") (pinfunction "C21_P$81") (pintype "bidirectional"))
    )
    (net (code "2626") (name "ZZ.13.116") (class "Default")
      (node (ref "U$13") (pin "P$141") (pinfunction "E21_P$141") (pintype "bidirectional"))
    )
    (net (code "2627") (name "ZZ.13.117") (class "Default")
      (node (ref "U$13") (pin "P$168") (pinfunction "F18_P$168") (pintype "bidirectional"))
    )
    (net (code "2628") (name "ZZ.13.118") (class "Default")
      (node (ref "U$15") (pin "P$107") (pinfunction "D17_P$107") (pintype "bidirectional"))
    )
    (net (code "2629") (name "ZZ.13.119") (class "Default")
      (node (ref "U$15") (pin "P$109") (pinfunction "D19_P$109") (pintype "bidirectional"))
    )
    (net (code "2630") (name "ZZ.13.120") (class "Default")
      (node (ref "U$15") (pin "P$111") (pinfunction "D21_P$111") (pintype "bidirectional"))
    )
    (net (code "2631") (name "ZZ.13.121") (class "Default")
      (node (ref "U$15") (pin "P$140") (pinfunction "E20_P$140") (pintype "bidirectional"))
    )
    (net (code "2632") (name "ZZ.13.122") (class "Default")
      (node (ref "U$15") (pin "P$169") (pinfunction "F19_P$169") (pintype "bidirectional"))
    )
    (net (code "2633") (name "ZZ.13.123") (class "Default")
      (node (ref "U$15") (pin "P$167") (pinfunction "F17_P$167") (pintype "bidirectional"))
    )
    (net (code "2634") (name "ZZ.13.124") (class "Default")
      (node (ref "U$17") (pin "P$47") (pinfunction "B17_P$47") (pintype "bidirectional"))
    )
    (net (code "2635") (name "ZZ.13.125") (class "Default")
      (node (ref "U$17") (pin "P$49") (pinfunction "B19_P$49") (pintype "bidirectional"))
    )
    (net (code "2636") (name "ZZ.13.126") (class "Default")
      (node (ref "U$17") (pin "P$51") (pinfunction "B21_P$51") (pintype "bidirectional"))
    )
    (net (code "2637") (name "ZZ.13.127") (class "Default")
      (node (ref "U$15") (pin "P$170") (pinfunction "F20_P$170") (pintype "bidirectional"))
    )
    (net (code "2638") (name "ZZ.13.128") (class "Default")
      (node (ref "U$15") (pin "P$139") (pinfunction "E19_P$139") (pintype "bidirectional"))
    )
    (net (code "2639") (name "ZZ.13.129") (class "Default")
      (node (ref "U$17") (pin "P$77") (pinfunction "C17_P$77") (pintype "bidirectional"))
    )
    (net (code "2640") (name "ZZ.13.130") (class "Default")
      (node (ref "U$17") (pin "P$79") (pinfunction "C19_P$79") (pintype "bidirectional"))
    )
    (net (code "2641") (name "ZZ.13.131") (class "Default")
      (node (ref "U$17") (pin "P$81") (pinfunction "C21_P$81") (pintype "bidirectional"))
    )
    (net (code "2642") (name "ZZ.13.132") (class "Default")
      (node (ref "U$15") (pin "P$141") (pinfunction "E21_P$141") (pintype "bidirectional"))
    )
    (net (code "2643") (name "ZZ.13.133") (class "Default")
      (node (ref "U$15") (pin "P$168") (pinfunction "F18_P$168") (pintype "bidirectional"))
    )
    (net (code "2644") (name "ZZ.13.134") (class "Default")
      (node (ref "U$17") (pin "P$107") (pinfunction "D17_P$107") (pintype "bidirectional"))
    )
    (net (code "2645") (name "ZZ.13.135") (class "Default")
      (node (ref "U$17") (pin "P$109") (pinfunction "D19_P$109") (pintype "bidirectional"))
    )
    (net (code "2646") (name "ZZ.13.136") (class "Default")
      (node (ref "U$17") (pin "P$111") (pinfunction "D21_P$111") (pintype "bidirectional"))
    )
    (net (code "2647") (name "ZZ.13.137") (class "Default")
      (node (ref "U$17") (pin "P$140") (pinfunction "E20_P$140") (pintype "bidirectional"))
    )
    (net (code "2648") (name "ZZ.13.138") (class "Default")
      (node (ref "U$17") (pin "P$169") (pinfunction "F19_P$169") (pintype "bidirectional"))
    )
    (net (code "2649") (name "ZZ.13.139") (class "Default")
      (node (ref "U$17") (pin "P$167") (pinfunction "F17_P$167") (pintype "bidirectional"))
    )
    (net (code "2650") (name "ZZ.13.140") (class "Default")
      (node (ref "U$19") (pin "P$47") (pinfunction "B17_P$47") (pintype "bidirectional"))
    )
    (net (code "2651") (name "ZZ.13.141") (class "Default")
      (node (ref "U$19") (pin "P$49") (pinfunction "B19_P$49") (pintype "bidirectional"))
    )
    (net (code "2652") (name "ZZ.13.142") (class "Default")
      (node (ref "U$19") (pin "P$51") (pinfunction "B21_P$51") (pintype "bidirectional"))
    )
    (net (code "2653") (name "ZZ.13.143") (class "Default")
      (node (ref "U$17") (pin "P$170") (pinfunction "F20_P$170") (pintype "bidirectional"))
    )
    (net (code "2654") (name "ZZ.13.144") (class "Default")
      (node (ref "U$17") (pin "P$139") (pinfunction "E19_P$139") (pintype "bidirectional"))
    )
    (net (code "2655") (name "ZZ.13.145") (class "Default")
      (node (ref "U$19") (pin "P$77") (pinfunction "C17_P$77") (pintype "bidirectional"))
    )
    (net (code "2656") (name "ZZ.13.146") (class "Default")
      (node (ref "U$19") (pin "P$79") (pinfunction "C19_P$79") (pintype "bidirectional"))
    )
    (net (code "2657") (name "ZZ.13.147") (class "Default")
      (node (ref "U$19") (pin "P$81") (pinfunction "C21_P$81") (pintype "bidirectional"))
    )
    (net (code "2658") (name "ZZ.13.148") (class "Default")
      (node (ref "U$17") (pin "P$141") (pinfunction "E21_P$141") (pintype "bidirectional"))
    )
    (net (code "2659") (name "ZZ.13.149") (class "Default")
      (node (ref "U$17") (pin "P$168") (pinfunction "F18_P$168") (pintype "bidirectional"))
    )
    (net (code "2660") (name "ZZ.13.150") (class "Default")
      (node (ref "U$19") (pin "P$107") (pinfunction "D17_P$107") (pintype "bidirectional"))
    )
    (net (code "2661") (name "ZZ.13.151") (class "Default")
      (node (ref "U$19") (pin "P$109") (pinfunction "D19_P$109") (pintype "bidirectional"))
    )
    (net (code "2662") (name "ZZ.13.152") (class "Default")
      (node (ref "U$19") (pin "P$111") (pinfunction "D21_P$111") (pintype "bidirectional"))
    )
    (net (code "2663") (name "ZZ.13.153") (class "Default")
      (node (ref "U$19") (pin "P$140") (pinfunction "E20_P$140") (pintype "bidirectional"))
    )
    (net (code "2664") (name "ZZ.13.154") (class "Default")
      (node (ref "U$19") (pin "P$169") (pinfunction "F19_P$169") (pintype "bidirectional"))
    )
    (net (code "2665") (name "ZZ.13.155") (class "Default")
      (node (ref "U$19") (pin "P$167") (pinfunction "F17_P$167") (pintype "bidirectional"))
    )
    (net (code "2666") (name "ZZ.13.156") (class "Default")
      (node (ref "U$21") (pin "P$47") (pinfunction "B17_P$47") (pintype "bidirectional"))
    )
    (net (code "2667") (name "ZZ.13.157") (class "Default")
      (node (ref "U$21") (pin "P$49") (pinfunction "B19_P$49") (pintype "bidirectional"))
    )
    (net (code "2668") (name "ZZ.13.158") (class "Default")
      (node (ref "U$21") (pin "P$51") (pinfunction "B21_P$51") (pintype "bidirectional"))
    )
    (net (code "2669") (name "ZZ.13.159") (class "Default")
      (node (ref "U$19") (pin "P$170") (pinfunction "F20_P$170") (pintype "bidirectional"))
    )
    (net (code "2670") (name "ZZ.13.160") (class "Default")
      (node (ref "U$19") (pin "P$139") (pinfunction "E19_P$139") (pintype "bidirectional"))
    )
    (net (code "2671") (name "ZZ.13.161") (class "Default")
      (node (ref "U$21") (pin "P$77") (pinfunction "C17_P$77") (pintype "bidirectional"))
    )
    (net (code "2672") (name "ZZ.13.162") (class "Default")
      (node (ref "U$21") (pin "P$79") (pinfunction "C19_P$79") (pintype "bidirectional"))
    )
    (net (code "2673") (name "ZZ.13.163") (class "Default")
      (node (ref "U$21") (pin "P$81") (pinfunction "C21_P$81") (pintype "bidirectional"))
    )
    (net (code "2674") (name "ZZ.13.164") (class "Default")
      (node (ref "U$19") (pin "P$141") (pinfunction "E21_P$141") (pintype "bidirectional"))
    )
    (net (code "2675") (name "ZZ.13.165") (class "Default")
      (node (ref "U$19") (pin "P$168") (pinfunction "F18_P$168") (pintype "bidirectional"))
    )
    (net (code "2676") (name "ZZ.13.166") (class "Default")
      (node (ref "U$21") (pin "P$107") (pinfunction "D17_P$107") (pintype "bidirectional"))
    )
    (net (code "2677") (name "ZZ.13.167") (class "Default")
      (node (ref "U$21") (pin "P$109") (pinfunction "D19_P$109") (pintype "bidirectional"))
    )
    (net (code "2678") (name "ZZ.13.168") (class "Default")
      (node (ref "U$21") (pin "P$111") (pinfunction "D21_P$111") (pintype "bidirectional"))
    )
    (net (code "2679") (name "ZZ.13.169") (class "Default")
      (node (ref "U$21") (pin "P$140") (pinfunction "E20_P$140") (pintype "bidirectional"))
    )
    (net (code "2680") (name "ZZ.13.170") (class "Default")
      (node (ref "U$21") (pin "P$169") (pinfunction "F19_P$169") (pintype "bidirectional"))
    )
    (net (code "2681") (name "ZZ.13.171") (class "Default")
      (node (ref "U$21") (pin "P$167") (pinfunction "F17_P$167") (pintype "bidirectional"))
    )
    (net (code "2682") (name "ZZ.13.172") (class "Default")
      (node (ref "U$23") (pin "P$47") (pinfunction "B17_P$47") (pintype "bidirectional"))
    )
    (net (code "2683") (name "ZZ.13.173") (class "Default")
      (node (ref "U$23") (pin "P$49") (pinfunction "B19_P$49") (pintype "bidirectional"))
    )
    (net (code "2684") (name "ZZ.13.174") (class "Default")
      (node (ref "U$23") (pin "P$51") (pinfunction "B21_P$51") (pintype "bidirectional"))
    )
    (net (code "2685") (name "ZZ.13.175") (class "Default")
      (node (ref "U$21") (pin "P$170") (pinfunction "F20_P$170") (pintype "bidirectional"))
    )
    (net (code "2686") (name "ZZ.13.176") (class "Default")
      (node (ref "U$21") (pin "P$139") (pinfunction "E19_P$139") (pintype "bidirectional"))
    )
    (net (code "2687") (name "ZZ.13.177") (class "Default")
      (node (ref "U$23") (pin "P$77") (pinfunction "C17_P$77") (pintype "bidirectional"))
    )
    (net (code "2688") (name "ZZ.13.178") (class "Default")
      (node (ref "U$23") (pin "P$79") (pinfunction "C19_P$79") (pintype "bidirectional"))
    )
    (net (code "2689") (name "ZZ.13.179") (class "Default")
      (node (ref "U$23") (pin "P$81") (pinfunction "C21_P$81") (pintype "bidirectional"))
    )
    (net (code "2690") (name "ZZ.13.180") (class "Default")
      (node (ref "U$21") (pin "P$141") (pinfunction "E21_P$141") (pintype "bidirectional"))
    )
    (net (code "2691") (name "ZZ.13.181") (class "Default")
      (node (ref "U$21") (pin "P$168") (pinfunction "F18_P$168") (pintype "bidirectional"))
    )
    (net (code "2692") (name "ZZ.13.182") (class "Default")
      (node (ref "U$23") (pin "P$107") (pinfunction "D17_P$107") (pintype "bidirectional"))
    )
    (net (code "2693") (name "ZZ.13.183") (class "Default")
      (node (ref "U$23") (pin "P$109") (pinfunction "D19_P$109") (pintype "bidirectional"))
    )
    (net (code "2694") (name "ZZ.13.184") (class "Default")
      (node (ref "U$23") (pin "P$111") (pinfunction "D21_P$111") (pintype "bidirectional"))
    )
    (net (code "2695") (name "ZZ.13.185") (class "Default")
      (node (ref "U$23") (pin "P$140") (pinfunction "E20_P$140") (pintype "bidirectional"))
    )
    (net (code "2696") (name "ZZ.13.186") (class "Default")
      (node (ref "U$23") (pin "P$169") (pinfunction "F19_P$169") (pintype "bidirectional"))
    )
    (net (code "2697") (name "ZZ.13.187") (class "Default")
      (node (ref "U$23") (pin "P$167") (pinfunction "F17_P$167") (pintype "bidirectional"))
    )
    (net (code "2698") (name "ZZ.13.188") (class "Default")
      (node (ref "U$23") (pin "P$170") (pinfunction "F20_P$170") (pintype "bidirectional"))
    )
    (net (code "2699") (name "ZZ.13.189") (class "Default")
      (node (ref "U$23") (pin "P$139") (pinfunction "E19_P$139") (pintype "bidirectional"))
    )
    (net (code "2700") (name "ZZ.13.190") (class "Default")
      (node (ref "U$23") (pin "P$141") (pinfunction "E21_P$141") (pintype "bidirectional"))
    )
    (net (code "2701") (name "ZZ.13.191") (class "Default")
      (node (ref "U$23") (pin "P$168") (pinfunction "F18_P$168") (pintype "bidirectional"))
    )
    (net (code "2702") (name "ZZ.14.000") (class "Default")
      (node (ref "U$1") (pin "P$57") (pinfunction "B27_P$57") (pintype "bidirectional"))
    )
    (net (code "2703") (name "ZZ.14.001") (class "Default")
      (node (ref "U$1") (pin "P$87") (pinfunction "C27_P$87") (pintype "bidirectional"))
    )
    (net (code "2704") (name "ZZ.14.002") (class "Default")
      (node (ref "U$1") (pin "P$117") (pinfunction "D27_P$117") (pintype "bidirectional"))
    )
    (net (code "2705") (name "ZZ.14.003") (class "Default")
      (node (ref "U$1") (pin "P$178") (pinfunction "F28_P$178") (pintype "bidirectional"))
    )
    (net (code "2706") (name "ZZ.14.004") (class "Default")
      (node (ref "U$1") (pin "P$145") (pinfunction "E25_P$145") (pintype "bidirectional"))
    )
    (net (code "2707") (name "ZZ.14.005") (class "Default")
      (node (ref "U$1") (pin "P$58") (pinfunction "B28_P$58") (pintype "bidirectional"))
    )
    (net (code "2708") (name "ZZ.14.006") (class "Default")
      (node (ref "U$1") (pin "P$88") (pinfunction "C28_P$88") (pintype "bidirectional"))
    )
    (net (code "2709") (name "ZZ.14.007") (class "Default")
      (node (ref "U$1") (pin "P$118") (pinfunction "D28_P$118") (pintype "bidirectional"))
    )
    (net (code "2710") (name "ZZ.14.008") (class "Default")
      (node (ref "U$1") (pin "P$149") (pinfunction "E29_P$149") (pintype "bidirectional"))
    )
    (net (code "2711") (name "ZZ.14.009") (class "Default")
      (node (ref "U$1") (pin "P$144") (pinfunction "E24_P$144") (pintype "bidirectional"))
    )
    (net (code "2712") (name "ZZ.14.010") (class "Default")
      (node (ref "U$1") (pin "P$59") (pinfunction "B29_P$59") (pintype "bidirectional"))
    )
    (net (code "2713") (name "ZZ.14.011") (class "Default")
      (node (ref "U$1") (pin "P$89") (pinfunction "C29_P$89") (pintype "bidirectional"))
    )
    (net (code "2714") (name "ZZ.14.012") (class "Default")
      (node (ref "U$1") (pin "P$119") (pinfunction "D29_P$119") (pintype "bidirectional"))
    )
    (net (code "2715") (name "ZZ.14.013") (class "Default")
      (node (ref "U$1") (pin "P$179") (pinfunction "F29_P$179") (pintype "bidirectional"))
    )
    (net (code "2716") (name "ZZ.14.014") (class "Default")
      (node (ref "U$1") (pin "P$173") (pinfunction "F23_P$173") (pintype "bidirectional"))
    )
    (net (code "2717") (name "ZZ.14.015") (class "Default")
      (node (ref "U$1") (pin "P$143") (pinfunction "E23_P$143") (pintype "bidirectional"))
    )
    (net (code "2718") (name "ZZ.14.016") (class "Default")
      (node (ref "U$3") (pin "P$57") (pinfunction "B27_P$57") (pintype "bidirectional"))
    )
    (net (code "2719") (name "ZZ.14.017") (class "Default")
      (node (ref "U$3") (pin "P$87") (pinfunction "C27_P$87") (pintype "bidirectional"))
    )
    (net (code "2720") (name "ZZ.14.018") (class "Default")
      (node (ref "U$3") (pin "P$117") (pinfunction "D27_P$117") (pintype "bidirectional"))
    )
    (net (code "2721") (name "ZZ.14.019") (class "Default")
      (node (ref "U$3") (pin "P$178") (pinfunction "F28_P$178") (pintype "bidirectional"))
    )
    (net (code "2722") (name "ZZ.14.020") (class "Default")
      (node (ref "U$3") (pin "P$145") (pinfunction "E25_P$145") (pintype "bidirectional"))
    )
    (net (code "2723") (name "ZZ.14.021") (class "Default")
      (node (ref "U$3") (pin "P$58") (pinfunction "B28_P$58") (pintype "bidirectional"))
    )
    (net (code "2724") (name "ZZ.14.022") (class "Default")
      (node (ref "U$3") (pin "P$88") (pinfunction "C28_P$88") (pintype "bidirectional"))
    )
    (net (code "2725") (name "ZZ.14.023") (class "Default")
      (node (ref "U$3") (pin "P$118") (pinfunction "D28_P$118") (pintype "bidirectional"))
    )
    (net (code "2726") (name "ZZ.14.024") (class "Default")
      (node (ref "U$3") (pin "P$149") (pinfunction "E29_P$149") (pintype "bidirectional"))
    )
    (net (code "2727") (name "ZZ.14.025") (class "Default")
      (node (ref "U$3") (pin "P$144") (pinfunction "E24_P$144") (pintype "bidirectional"))
    )
    (net (code "2728") (name "ZZ.14.026") (class "Default")
      (node (ref "U$3") (pin "P$59") (pinfunction "B29_P$59") (pintype "bidirectional"))
    )
    (net (code "2729") (name "ZZ.14.027") (class "Default")
      (node (ref "U$3") (pin "P$89") (pinfunction "C29_P$89") (pintype "bidirectional"))
    )
    (net (code "2730") (name "ZZ.14.028") (class "Default")
      (node (ref "U$3") (pin "P$119") (pinfunction "D29_P$119") (pintype "bidirectional"))
    )
    (net (code "2731") (name "ZZ.14.029") (class "Default")
      (node (ref "U$3") (pin "P$179") (pinfunction "F29_P$179") (pintype "bidirectional"))
    )
    (net (code "2732") (name "ZZ.14.030") (class "Default")
      (node (ref "U$3") (pin "P$173") (pinfunction "F23_P$173") (pintype "bidirectional"))
    )
    (net (code "2733") (name "ZZ.14.031") (class "Default")
      (node (ref "U$3") (pin "P$143") (pinfunction "E23_P$143") (pintype "bidirectional"))
    )
    (net (code "2734") (name "ZZ.14.032") (class "Default")
      (node (ref "U$5") (pin "P$57") (pinfunction "B27_P$57") (pintype "bidirectional"))
    )
    (net (code "2735") (name "ZZ.14.033") (class "Default")
      (node (ref "U$5") (pin "P$87") (pinfunction "C27_P$87") (pintype "bidirectional"))
    )
    (net (code "2736") (name "ZZ.14.034") (class "Default")
      (node (ref "U$5") (pin "P$117") (pinfunction "D27_P$117") (pintype "bidirectional"))
    )
    (net (code "2737") (name "ZZ.14.035") (class "Default")
      (node (ref "U$5") (pin "P$178") (pinfunction "F28_P$178") (pintype "bidirectional"))
    )
    (net (code "2738") (name "ZZ.14.036") (class "Default")
      (node (ref "U$5") (pin "P$145") (pinfunction "E25_P$145") (pintype "bidirectional"))
    )
    (net (code "2739") (name "ZZ.14.037") (class "Default")
      (node (ref "U$5") (pin "P$58") (pinfunction "B28_P$58") (pintype "bidirectional"))
    )
    (net (code "2740") (name "ZZ.14.038") (class "Default")
      (node (ref "U$5") (pin "P$88") (pinfunction "C28_P$88") (pintype "bidirectional"))
    )
    (net (code "2741") (name "ZZ.14.039") (class "Default")
      (node (ref "U$5") (pin "P$118") (pinfunction "D28_P$118") (pintype "bidirectional"))
    )
    (net (code "2742") (name "ZZ.14.040") (class "Default")
      (node (ref "U$5") (pin "P$149") (pinfunction "E29_P$149") (pintype "bidirectional"))
    )
    (net (code "2743") (name "ZZ.14.041") (class "Default")
      (node (ref "U$5") (pin "P$144") (pinfunction "E24_P$144") (pintype "bidirectional"))
    )
    (net (code "2744") (name "ZZ.14.042") (class "Default")
      (node (ref "U$5") (pin "P$59") (pinfunction "B29_P$59") (pintype "bidirectional"))
    )
    (net (code "2745") (name "ZZ.14.043") (class "Default")
      (node (ref "U$5") (pin "P$89") (pinfunction "C29_P$89") (pintype "bidirectional"))
    )
    (net (code "2746") (name "ZZ.14.044") (class "Default")
      (node (ref "U$5") (pin "P$119") (pinfunction "D29_P$119") (pintype "bidirectional"))
    )
    (net (code "2747") (name "ZZ.14.045") (class "Default")
      (node (ref "U$5") (pin "P$179") (pinfunction "F29_P$179") (pintype "bidirectional"))
    )
    (net (code "2748") (name "ZZ.14.046") (class "Default")
      (node (ref "U$5") (pin "P$173") (pinfunction "F23_P$173") (pintype "bidirectional"))
    )
    (net (code "2749") (name "ZZ.14.047") (class "Default")
      (node (ref "U$5") (pin "P$143") (pinfunction "E23_P$143") (pintype "bidirectional"))
    )
    (net (code "2750") (name "ZZ.14.048") (class "Default")
      (node (ref "U$7") (pin "P$57") (pinfunction "B27_P$57") (pintype "bidirectional"))
    )
    (net (code "2751") (name "ZZ.14.049") (class "Default")
      (node (ref "U$7") (pin "P$87") (pinfunction "C27_P$87") (pintype "bidirectional"))
    )
    (net (code "2752") (name "ZZ.14.050") (class "Default")
      (node (ref "U$7") (pin "P$117") (pinfunction "D27_P$117") (pintype "bidirectional"))
    )
    (net (code "2753") (name "ZZ.14.051") (class "Default")
      (node (ref "U$7") (pin "P$178") (pinfunction "F28_P$178") (pintype "bidirectional"))
    )
    (net (code "2754") (name "ZZ.14.052") (class "Default")
      (node (ref "U$7") (pin "P$145") (pinfunction "E25_P$145") (pintype "bidirectional"))
    )
    (net (code "2755") (name "ZZ.14.053") (class "Default")
      (node (ref "U$7") (pin "P$58") (pinfunction "B28_P$58") (pintype "bidirectional"))
    )
    (net (code "2756") (name "ZZ.14.054") (class "Default")
      (node (ref "U$7") (pin "P$88") (pinfunction "C28_P$88") (pintype "bidirectional"))
    )
    (net (code "2757") (name "ZZ.14.055") (class "Default")
      (node (ref "U$7") (pin "P$118") (pinfunction "D28_P$118") (pintype "bidirectional"))
    )
    (net (code "2758") (name "ZZ.14.056") (class "Default")
      (node (ref "U$7") (pin "P$59") (pinfunction "B29_P$59") (pintype "bidirectional"))
    )
    (net (code "2759") (name "ZZ.14.057") (class "Default")
      (node (ref "U$7") (pin "P$89") (pinfunction "C29_P$89") (pintype "bidirectional"))
    )
    (net (code "2760") (name "ZZ.14.058") (class "Default")
      (node (ref "U$7") (pin "P$119") (pinfunction "D29_P$119") (pintype "bidirectional"))
    )
    (net (code "2761") (name "ZZ.14.059") (class "Default")
      (node (ref "U$7") (pin "P$179") (pinfunction "F29_P$179") (pintype "bidirectional"))
    )
    (net (code "2762") (name "ZZ.14.060") (class "Default")
      (node (ref "U$7") (pin "P$173") (pinfunction "F23_P$173") (pintype "bidirectional"))
    )
    (net (code "2763") (name "ZZ.14.061") (class "Default")
      (node (ref "U$7") (pin "P$143") (pinfunction "E23_P$143") (pintype "bidirectional"))
    )
    (net (code "2764") (name "ZZ.14.062") (class "Default")
      (node (ref "U$7") (pin "P$149") (pinfunction "E29_P$149") (pintype "bidirectional"))
    )
    (net (code "2765") (name "ZZ.14.063") (class "Default")
      (node (ref "U$7") (pin "P$144") (pinfunction "E24_P$144") (pintype "bidirectional"))
    )
    (net (code "2766") (name "ZZ.14.064") (class "Default")
      (node (ref "U$9") (pin "P$57") (pinfunction "B27_P$57") (pintype "bidirectional"))
    )
    (net (code "2767") (name "ZZ.14.065") (class "Default")
      (node (ref "U$9") (pin "P$87") (pinfunction "C27_P$87") (pintype "bidirectional"))
    )
    (net (code "2768") (name "ZZ.14.066") (class "Default")
      (node (ref "U$9") (pin "P$117") (pinfunction "D27_P$117") (pintype "bidirectional"))
    )
    (net (code "2769") (name "ZZ.14.067") (class "Default")
      (node (ref "U$9") (pin "P$58") (pinfunction "B28_P$58") (pintype "bidirectional"))
    )
    (net (code "2770") (name "ZZ.14.068") (class "Default")
      (node (ref "U$9") (pin "P$88") (pinfunction "C28_P$88") (pintype "bidirectional"))
    )
    (net (code "2771") (name "ZZ.14.069") (class "Default")
      (node (ref "U$9") (pin "P$118") (pinfunction "D28_P$118") (pintype "bidirectional"))
    )
    (net (code "2772") (name "ZZ.14.070") (class "Default")
      (node (ref "U$9") (pin "P$59") (pinfunction "B29_P$59") (pintype "bidirectional"))
    )
    (net (code "2773") (name "ZZ.14.071") (class "Default")
      (node (ref "U$9") (pin "P$89") (pinfunction "C29_P$89") (pintype "bidirectional"))
    )
    (net (code "2774") (name "ZZ.14.072") (class "Default")
      (node (ref "U$9") (pin "P$119") (pinfunction "D29_P$119") (pintype "bidirectional"))
    )
    (net (code "2775") (name "ZZ.14.073") (class "Default")
      (node (ref "U$9") (pin "P$179") (pinfunction "F29_P$179") (pintype "bidirectional"))
    )
    (net (code "2776") (name "ZZ.14.074") (class "Default")
      (node (ref "U$9") (pin "P$173") (pinfunction "F23_P$173") (pintype "bidirectional"))
    )
    (net (code "2777") (name "ZZ.14.075") (class "Default")
      (node (ref "U$9") (pin "P$143") (pinfunction "E23_P$143") (pintype "bidirectional"))
    )
    (net (code "2778") (name "ZZ.14.076") (class "Default")
      (node (ref "U$9") (pin "P$149") (pinfunction "E29_P$149") (pintype "bidirectional"))
    )
    (net (code "2779") (name "ZZ.14.077") (class "Default")
      (node (ref "U$9") (pin "P$144") (pinfunction "E24_P$144") (pintype "bidirectional"))
    )
    (net (code "2780") (name "ZZ.14.078") (class "Default")
      (node (ref "U$9") (pin "P$178") (pinfunction "F28_P$178") (pintype "bidirectional"))
    )
    (net (code "2781") (name "ZZ.14.079") (class "Default")
      (node (ref "U$9") (pin "P$145") (pinfunction "E25_P$145") (pintype "bidirectional"))
    )
    (net (code "2782") (name "ZZ.14.080") (class "Default")
      (node (ref "U$11") (pin "P$58") (pinfunction "B28_P$58") (pintype "bidirectional"))
    )
    (net (code "2783") (name "ZZ.14.081") (class "Default")
      (node (ref "U$11") (pin "P$88") (pinfunction "C28_P$88") (pintype "bidirectional"))
    )
    (net (code "2784") (name "ZZ.14.082") (class "Default")
      (node (ref "U$11") (pin "P$118") (pinfunction "D28_P$118") (pintype "bidirectional"))
    )
    (net (code "2785") (name "ZZ.14.083") (class "Default")
      (node (ref "U$11") (pin "P$59") (pinfunction "B29_P$59") (pintype "bidirectional"))
    )
    (net (code "2786") (name "ZZ.14.084") (class "Default")
      (node (ref "U$11") (pin "P$89") (pinfunction "C29_P$89") (pintype "bidirectional"))
    )
    (net (code "2787") (name "ZZ.14.085") (class "Default")
      (node (ref "U$11") (pin "P$119") (pinfunction "D29_P$119") (pintype "bidirectional"))
    )
    (net (code "2788") (name "ZZ.14.086") (class "Default")
      (node (ref "U$11") (pin "P$179") (pinfunction "F29_P$179") (pintype "bidirectional"))
    )
    (net (code "2789") (name "ZZ.14.087") (class "Default")
      (node (ref "U$11") (pin "P$173") (pinfunction "F23_P$173") (pintype "bidirectional"))
    )
    (net (code "2790") (name "ZZ.14.088") (class "Default")
      (node (ref "U$11") (pin "P$143") (pinfunction "E23_P$143") (pintype "bidirectional"))
    )
    (net (code "2791") (name "ZZ.14.089") (class "Default")
      (node (ref "U$11") (pin "P$149") (pinfunction "E29_P$149") (pintype "bidirectional"))
    )
    (net (code "2792") (name "ZZ.14.090") (class "Default")
      (node (ref "U$11") (pin "P$144") (pinfunction "E24_P$144") (pintype "bidirectional"))
    )
    (net (code "2793") (name "ZZ.14.091") (class "Default")
      (node (ref "U$11") (pin "P$57") (pinfunction "B27_P$57") (pintype "bidirectional"))
    )
    (net (code "2794") (name "ZZ.14.092") (class "Default")
      (node (ref "U$11") (pin "P$87") (pinfunction "C27_P$87") (pintype "bidirectional"))
    )
    (net (code "2795") (name "ZZ.14.093") (class "Default")
      (node (ref "U$11") (pin "P$117") (pinfunction "D27_P$117") (pintype "bidirectional"))
    )
    (net (code "2796") (name "ZZ.14.094") (class "Default")
      (node (ref "U$11") (pin "P$178") (pinfunction "F28_P$178") (pintype "bidirectional"))
    )
    (net (code "2797") (name "ZZ.14.095") (class "Default")
      (node (ref "U$11") (pin "P$145") (pinfunction "E25_P$145") (pintype "bidirectional"))
    )
    (net (code "2798") (name "ZZ.14.096") (class "Default")
      (node (ref "U$13") (pin "P$58") (pinfunction "B28_P$58") (pintype "bidirectional"))
    )
    (net (code "2799") (name "ZZ.14.097") (class "Default")
      (node (ref "U$13") (pin "P$59") (pinfunction "B29_P$59") (pintype "bidirectional"))
    )
    (net (code "2800") (name "ZZ.14.098") (class "Default")
      (node (ref "U$13") (pin "P$89") (pinfunction "C29_P$89") (pintype "bidirectional"))
    )
    (net (code "2801") (name "ZZ.14.099") (class "Default")
      (node (ref "U$13") (pin "P$119") (pinfunction "D29_P$119") (pintype "bidirectional"))
    )
    (net (code "2802") (name "ZZ.14.100") (class "Default")
      (node (ref "U$13") (pin "P$179") (pinfunction "F29_P$179") (pintype "bidirectional"))
    )
    (net (code "2803") (name "ZZ.14.101") (class "Default")
      (node (ref "U$13") (pin "P$173") (pinfunction "F23_P$173") (pintype "bidirectional"))
    )
    (net (code "2804") (name "ZZ.14.102") (class "Default")
      (node (ref "U$13") (pin "P$143") (pinfunction "E23_P$143") (pintype "bidirectional"))
    )
    (net (code "2805") (name "ZZ.14.103") (class "Default")
      (node (ref "U$13") (pin "P$88") (pinfunction "C28_P$88") (pintype "bidirectional"))
    )
    (net (code "2806") (name "ZZ.14.104") (class "Default")
      (node (ref "U$13") (pin "P$118") (pinfunction "D28_P$118") (pintype "bidirectional"))
    )
    (net (code "2807") (name "ZZ.14.105") (class "Default")
      (node (ref "U$13") (pin "P$149") (pinfunction "E29_P$149") (pintype "bidirectional"))
    )
    (net (code "2808") (name "ZZ.14.106") (class "Default")
      (node (ref "U$13") (pin "P$144") (pinfunction "E24_P$144") (pintype "bidirectional"))
    )
    (net (code "2809") (name "ZZ.14.107") (class "Default")
      (node (ref "U$13") (pin "P$57") (pinfunction "B27_P$57") (pintype "bidirectional"))
    )
    (net (code "2810") (name "ZZ.14.108") (class "Default")
      (node (ref "U$13") (pin "P$87") (pinfunction "C27_P$87") (pintype "bidirectional"))
    )
    (net (code "2811") (name "ZZ.14.109") (class "Default")
      (node (ref "U$13") (pin "P$117") (pinfunction "D27_P$117") (pintype "bidirectional"))
    )
    (net (code "2812") (name "ZZ.14.110") (class "Default")
      (node (ref "U$13") (pin "P$178") (pinfunction "F28_P$178") (pintype "bidirectional"))
    )
    (net (code "2813") (name "ZZ.14.111") (class "Default")
      (node (ref "U$13") (pin "P$145") (pinfunction "E25_P$145") (pintype "bidirectional"))
    )
    (net (code "2814") (name "ZZ.14.112") (class "Default")
      (node (ref "U$15") (pin "P$59") (pinfunction "B29_P$59") (pintype "bidirectional"))
    )
    (net (code "2815") (name "ZZ.14.113") (class "Default")
      (node (ref "U$15") (pin "P$89") (pinfunction "C29_P$89") (pintype "bidirectional"))
    )
    (net (code "2816") (name "ZZ.14.114") (class "Default")
      (node (ref "U$15") (pin "P$119") (pinfunction "D29_P$119") (pintype "bidirectional"))
    )
    (net (code "2817") (name "ZZ.14.115") (class "Default")
      (node (ref "U$15") (pin "P$179") (pinfunction "F29_P$179") (pintype "bidirectional"))
    )
    (net (code "2818") (name "ZZ.14.116") (class "Default")
      (node (ref "U$15") (pin "P$173") (pinfunction "F23_P$173") (pintype "bidirectional"))
    )
    (net (code "2819") (name "ZZ.14.117") (class "Default")
      (node (ref "U$15") (pin "P$143") (pinfunction "E23_P$143") (pintype "bidirectional"))
    )
    (net (code "2820") (name "ZZ.14.118") (class "Default")
      (node (ref "U$15") (pin "P$58") (pinfunction "B28_P$58") (pintype "bidirectional"))
    )
    (net (code "2821") (name "ZZ.14.119") (class "Default")
      (node (ref "U$15") (pin "P$88") (pinfunction "C28_P$88") (pintype "bidirectional"))
    )
    (net (code "2822") (name "ZZ.14.120") (class "Default")
      (node (ref "U$15") (pin "P$118") (pinfunction "D28_P$118") (pintype "bidirectional"))
    )
    (net (code "2823") (name "ZZ.14.121") (class "Default")
      (node (ref "U$15") (pin "P$149") (pinfunction "E29_P$149") (pintype "bidirectional"))
    )
    (net (code "2824") (name "ZZ.14.122") (class "Default")
      (node (ref "U$15") (pin "P$144") (pinfunction "E24_P$144") (pintype "bidirectional"))
    )
    (net (code "2825") (name "ZZ.14.123") (class "Default")
      (node (ref "U$15") (pin "P$57") (pinfunction "B27_P$57") (pintype "bidirectional"))
    )
    (net (code "2826") (name "ZZ.14.124") (class "Default")
      (node (ref "U$15") (pin "P$87") (pinfunction "C27_P$87") (pintype "bidirectional"))
    )
    (net (code "2827") (name "ZZ.14.125") (class "Default")
      (node (ref "U$15") (pin "P$117") (pinfunction "D27_P$117") (pintype "bidirectional"))
    )
    (net (code "2828") (name "ZZ.14.126") (class "Default")
      (node (ref "U$15") (pin "P$178") (pinfunction "F28_P$178") (pintype "bidirectional"))
    )
    (net (code "2829") (name "ZZ.14.127") (class "Default")
      (node (ref "U$15") (pin "P$145") (pinfunction "E25_P$145") (pintype "bidirectional"))
    )
    (net (code "2830") (name "ZZ.14.128") (class "Default")
      (node (ref "U$17") (pin "P$59") (pinfunction "B29_P$59") (pintype "bidirectional"))
    )
    (net (code "2831") (name "ZZ.14.129") (class "Default")
      (node (ref "U$17") (pin "P$89") (pinfunction "C29_P$89") (pintype "bidirectional"))
    )
    (net (code "2832") (name "ZZ.14.130") (class "Default")
      (node (ref "U$17") (pin "P$119") (pinfunction "D29_P$119") (pintype "bidirectional"))
    )
    (net (code "2833") (name "ZZ.14.131") (class "Default")
      (node (ref "U$17") (pin "P$179") (pinfunction "F29_P$179") (pintype "bidirectional"))
    )
    (net (code "2834") (name "ZZ.14.132") (class "Default")
      (node (ref "U$17") (pin "P$173") (pinfunction "F23_P$173") (pintype "bidirectional"))
    )
    (net (code "2835") (name "ZZ.14.133") (class "Default")
      (node (ref "U$17") (pin "P$143") (pinfunction "E23_P$143") (pintype "bidirectional"))
    )
    (net (code "2836") (name "ZZ.14.134") (class "Default")
      (node (ref "U$17") (pin "P$58") (pinfunction "B28_P$58") (pintype "bidirectional"))
    )
    (net (code "2837") (name "ZZ.14.135") (class "Default")
      (node (ref "U$17") (pin "P$88") (pinfunction "C28_P$88") (pintype "bidirectional"))
    )
    (net (code "2838") (name "ZZ.14.136") (class "Default")
      (node (ref "U$17") (pin "P$118") (pinfunction "D28_P$118") (pintype "bidirectional"))
    )
    (net (code "2839") (name "ZZ.14.137") (class "Default")
      (node (ref "U$17") (pin "P$149") (pinfunction "E29_P$149") (pintype "bidirectional"))
    )
    (net (code "2840") (name "ZZ.14.138") (class "Default")
      (node (ref "U$17") (pin "P$144") (pinfunction "E24_P$144") (pintype "bidirectional"))
    )
    (net (code "2841") (name "ZZ.14.139") (class "Default")
      (node (ref "U$17") (pin "P$57") (pinfunction "B27_P$57") (pintype "bidirectional"))
    )
    (net (code "2842") (name "ZZ.14.140") (class "Default")
      (node (ref "U$17") (pin "P$87") (pinfunction "C27_P$87") (pintype "bidirectional"))
    )
    (net (code "2843") (name "ZZ.14.141") (class "Default")
      (node (ref "U$17") (pin "P$117") (pinfunction "D27_P$117") (pintype "bidirectional"))
    )
    (net (code "2844") (name "ZZ.14.142") (class "Default")
      (node (ref "U$17") (pin "P$178") (pinfunction "F28_P$178") (pintype "bidirectional"))
    )
    (net (code "2845") (name "ZZ.14.143") (class "Default")
      (node (ref "U$17") (pin "P$145") (pinfunction "E25_P$145") (pintype "bidirectional"))
    )
    (net (code "2846") (name "ZZ.14.144") (class "Default")
      (node (ref "U$19") (pin "P$59") (pinfunction "B29_P$59") (pintype "bidirectional"))
    )
    (net (code "2847") (name "ZZ.14.145") (class "Default")
      (node (ref "U$19") (pin "P$89") (pinfunction "C29_P$89") (pintype "bidirectional"))
    )
    (net (code "2848") (name "ZZ.14.146") (class "Default")
      (node (ref "U$19") (pin "P$119") (pinfunction "D29_P$119") (pintype "bidirectional"))
    )
    (net (code "2849") (name "ZZ.14.147") (class "Default")
      (node (ref "U$19") (pin "P$179") (pinfunction "F29_P$179") (pintype "bidirectional"))
    )
    (net (code "2850") (name "ZZ.14.148") (class "Default")
      (node (ref "U$19") (pin "P$173") (pinfunction "F23_P$173") (pintype "bidirectional"))
    )
    (net (code "2851") (name "ZZ.14.149") (class "Default")
      (node (ref "U$19") (pin "P$143") (pinfunction "E23_P$143") (pintype "bidirectional"))
    )
    (net (code "2852") (name "ZZ.14.150") (class "Default")
      (node (ref "U$19") (pin "P$58") (pinfunction "B28_P$58") (pintype "bidirectional"))
    )
    (net (code "2853") (name "ZZ.14.151") (class "Default")
      (node (ref "U$19") (pin "P$88") (pinfunction "C28_P$88") (pintype "bidirectional"))
    )
    (net (code "2854") (name "ZZ.14.152") (class "Default")
      (node (ref "U$19") (pin "P$118") (pinfunction "D28_P$118") (pintype "bidirectional"))
    )
    (net (code "2855") (name "ZZ.14.153") (class "Default")
      (node (ref "U$19") (pin "P$149") (pinfunction "E29_P$149") (pintype "bidirectional"))
    )
    (net (code "2856") (name "ZZ.14.154") (class "Default")
      (node (ref "U$19") (pin "P$144") (pinfunction "E24_P$144") (pintype "bidirectional"))
    )
    (net (code "2857") (name "ZZ.14.155") (class "Default")
      (node (ref "U$19") (pin "P$57") (pinfunction "B27_P$57") (pintype "bidirectional"))
    )
    (net (code "2858") (name "ZZ.14.156") (class "Default")
      (node (ref "U$19") (pin "P$87") (pinfunction "C27_P$87") (pintype "bidirectional"))
    )
    (net (code "2859") (name "ZZ.14.157") (class "Default")
      (node (ref "U$19") (pin "P$117") (pinfunction "D27_P$117") (pintype "bidirectional"))
    )
    (net (code "2860") (name "ZZ.14.158") (class "Default")
      (node (ref "U$19") (pin "P$178") (pinfunction "F28_P$178") (pintype "bidirectional"))
    )
    (net (code "2861") (name "ZZ.14.159") (class "Default")
      (node (ref "U$19") (pin "P$145") (pinfunction "E25_P$145") (pintype "bidirectional"))
    )
    (net (code "2862") (name "ZZ.14.160") (class "Default")
      (node (ref "U$21") (pin "P$59") (pinfunction "B29_P$59") (pintype "bidirectional"))
    )
    (net (code "2863") (name "ZZ.14.161") (class "Default")
      (node (ref "U$21") (pin "P$89") (pinfunction "C29_P$89") (pintype "bidirectional"))
    )
    (net (code "2864") (name "ZZ.14.162") (class "Default")
      (node (ref "U$21") (pin "P$119") (pinfunction "D29_P$119") (pintype "bidirectional"))
    )
    (net (code "2865") (name "ZZ.14.163") (class "Default")
      (node (ref "U$21") (pin "P$179") (pinfunction "F29_P$179") (pintype "bidirectional"))
    )
    (net (code "2866") (name "ZZ.14.164") (class "Default")
      (node (ref "U$21") (pin "P$173") (pinfunction "F23_P$173") (pintype "bidirectional"))
    )
    (net (code "2867") (name "ZZ.14.165") (class "Default")
      (node (ref "U$21") (pin "P$143") (pinfunction "E23_P$143") (pintype "bidirectional"))
    )
    (net (code "2868") (name "ZZ.14.166") (class "Default")
      (node (ref "U$21") (pin "P$58") (pinfunction "B28_P$58") (pintype "bidirectional"))
    )
    (net (code "2869") (name "ZZ.14.167") (class "Default")
      (node (ref "U$21") (pin "P$88") (pinfunction "C28_P$88") (pintype "bidirectional"))
    )
    (net (code "2870") (name "ZZ.14.168") (class "Default")
      (node (ref "U$21") (pin "P$118") (pinfunction "D28_P$118") (pintype "bidirectional"))
    )
    (net (code "2871") (name "ZZ.14.169") (class "Default")
      (node (ref "U$21") (pin "P$149") (pinfunction "E29_P$149") (pintype "bidirectional"))
    )
    (net (code "2872") (name "ZZ.14.170") (class "Default")
      (node (ref "U$21") (pin "P$144") (pinfunction "E24_P$144") (pintype "bidirectional"))
    )
    (net (code "2873") (name "ZZ.14.171") (class "Default")
      (node (ref "U$21") (pin "P$57") (pinfunction "B27_P$57") (pintype "bidirectional"))
    )
    (net (code "2874") (name "ZZ.14.172") (class "Default")
      (node (ref "U$21") (pin "P$87") (pinfunction "C27_P$87") (pintype "bidirectional"))
    )
    (net (code "2875") (name "ZZ.14.173") (class "Default")
      (node (ref "U$21") (pin "P$117") (pinfunction "D27_P$117") (pintype "bidirectional"))
    )
    (net (code "2876") (name "ZZ.14.174") (class "Default")
      (node (ref "U$21") (pin "P$178") (pinfunction "F28_P$178") (pintype "bidirectional"))
    )
    (net (code "2877") (name "ZZ.14.175") (class "Default")
      (node (ref "U$21") (pin "P$145") (pinfunction "E25_P$145") (pintype "bidirectional"))
    )
    (net (code "2878") (name "ZZ.14.176") (class "Default")
      (node (ref "U$23") (pin "P$59") (pinfunction "B29_P$59") (pintype "bidirectional"))
    )
    (net (code "2879") (name "ZZ.14.177") (class "Default")
      (node (ref "U$23") (pin "P$89") (pinfunction "C29_P$89") (pintype "bidirectional"))
    )
    (net (code "2880") (name "ZZ.14.178") (class "Default")
      (node (ref "U$23") (pin "P$119") (pinfunction "D29_P$119") (pintype "bidirectional"))
    )
    (net (code "2881") (name "ZZ.14.179") (class "Default")
      (node (ref "U$23") (pin "P$179") (pinfunction "F29_P$179") (pintype "bidirectional"))
    )
    (net (code "2882") (name "ZZ.14.180") (class "Default")
      (node (ref "U$23") (pin "P$173") (pinfunction "F23_P$173") (pintype "bidirectional"))
    )
    (net (code "2883") (name "ZZ.14.181") (class "Default")
      (node (ref "U$23") (pin "P$143") (pinfunction "E23_P$143") (pintype "bidirectional"))
    )
    (net (code "2884") (name "ZZ.14.182") (class "Default")
      (node (ref "U$23") (pin "P$58") (pinfunction "B28_P$58") (pintype "bidirectional"))
    )
    (net (code "2885") (name "ZZ.14.183") (class "Default")
      (node (ref "U$23") (pin "P$88") (pinfunction "C28_P$88") (pintype "bidirectional"))
    )
    (net (code "2886") (name "ZZ.14.184") (class "Default")
      (node (ref "U$23") (pin "P$118") (pinfunction "D28_P$118") (pintype "bidirectional"))
    )
    (net (code "2887") (name "ZZ.14.185") (class "Default")
      (node (ref "U$23") (pin "P$149") (pinfunction "E29_P$149") (pintype "bidirectional"))
    )
    (net (code "2888") (name "ZZ.14.186") (class "Default")
      (node (ref "U$23") (pin "P$144") (pinfunction "E24_P$144") (pintype "bidirectional"))
    )
    (net (code "2889") (name "ZZ.14.187") (class "Default")
      (node (ref "U$23") (pin "P$57") (pinfunction "B27_P$57") (pintype "bidirectional"))
    )
    (net (code "2890") (name "ZZ.14.188") (class "Default")
      (node (ref "U$23") (pin "P$87") (pinfunction "C27_P$87") (pintype "bidirectional"))
    )
    (net (code "2891") (name "ZZ.14.189") (class "Default")
      (node (ref "U$23") (pin "P$117") (pinfunction "D27_P$117") (pintype "bidirectional"))
    )
    (net (code "2892") (name "ZZ.14.190") (class "Default")
      (node (ref "U$23") (pin "P$178") (pinfunction "F28_P$178") (pintype "bidirectional"))
    )
    (net (code "2893") (name "ZZ.14.191") (class "Default")
      (node (ref "U$23") (pin "P$145") (pinfunction "E25_P$145") (pintype "bidirectional"))
    )
    (net (code "2894") (name "ZZ.15.000") (class "Default")
      (node (ref "U$1") (pin "P$56") (pinfunction "B26_P$56") (pintype "bidirectional"))
    )
    (net (code "2895") (name "ZZ.15.001") (class "Default")
      (node (ref "U$1") (pin "P$86") (pinfunction "C26_P$86") (pintype "bidirectional"))
    )
    (net (code "2896") (name "ZZ.15.002") (class "Default")
      (node (ref "U$1") (pin "P$116") (pinfunction "D26_P$116") (pintype "bidirectional"))
    )
    (net (code "2897") (name "ZZ.15.003") (class "Default")
      (node (ref "U$1") (pin "P$148") (pinfunction "E28_P$148") (pintype "bidirectional"))
    )
    (net (code "2898") (name "ZZ.15.004") (class "Default")
      (node (ref "U$1") (pin "P$175") (pinfunction "F25_P$175") (pintype "bidirectional"))
    )
    (net (code "2899") (name "ZZ.15.005") (class "Default")
      (node (ref "U$1") (pin "P$55") (pinfunction "B25_P$55") (pintype "bidirectional"))
    )
    (net (code "2900") (name "ZZ.15.006") (class "Default")
      (node (ref "U$1") (pin "P$85") (pinfunction "C25_P$85") (pintype "bidirectional"))
    )
    (net (code "2901") (name "ZZ.15.007") (class "Default")
      (node (ref "U$1") (pin "P$115") (pinfunction "D25_P$115") (pintype "bidirectional"))
    )
    (net (code "2902") (name "ZZ.15.008") (class "Default")
      (node (ref "U$1") (pin "P$177") (pinfunction "F27_P$177") (pintype "bidirectional"))
    )
    (net (code "2903") (name "ZZ.15.009") (class "Default")
      (node (ref "U$1") (pin "P$146") (pinfunction "E26_P$146") (pintype "bidirectional"))
    )
    (net (code "2904") (name "ZZ.15.010") (class "Default")
      (node (ref "U$1") (pin "P$54") (pinfunction "B24_P$54") (pintype "bidirectional"))
    )
    (net (code "2905") (name "ZZ.15.011") (class "Default")
      (node (ref "U$1") (pin "P$84") (pinfunction "C24_P$84") (pintype "bidirectional"))
    )
    (net (code "2906") (name "ZZ.15.012") (class "Default")
      (node (ref "U$1") (pin "P$114") (pinfunction "D24_P$114") (pintype "bidirectional"))
    )
    (net (code "2907") (name "ZZ.15.013") (class "Default")
      (node (ref "U$1") (pin "P$147") (pinfunction "E27_P$147") (pintype "bidirectional"))
    )
    (net (code "2908") (name "ZZ.15.014") (class "Default")
      (node (ref "U$1") (pin "P$176") (pinfunction "F26_P$176") (pintype "bidirectional"))
    )
    (net (code "2909") (name "ZZ.15.015") (class "Default")
      (node (ref "U$1") (pin "P$174") (pinfunction "F24_P$174") (pintype "bidirectional"))
    )
    (net (code "2910") (name "ZZ.15.016") (class "Default")
      (node (ref "U$3") (pin "P$56") (pinfunction "B26_P$56") (pintype "bidirectional"))
    )
    (net (code "2911") (name "ZZ.15.017") (class "Default")
      (node (ref "U$3") (pin "P$86") (pinfunction "C26_P$86") (pintype "bidirectional"))
    )
    (net (code "2912") (name "ZZ.15.018") (class "Default")
      (node (ref "U$3") (pin "P$116") (pinfunction "D26_P$116") (pintype "bidirectional"))
    )
    (net (code "2913") (name "ZZ.15.019") (class "Default")
      (node (ref "U$3") (pin "P$148") (pinfunction "E28_P$148") (pintype "bidirectional"))
    )
    (net (code "2914") (name "ZZ.15.020") (class "Default")
      (node (ref "U$3") (pin "P$175") (pinfunction "F25_P$175") (pintype "bidirectional"))
    )
    (net (code "2915") (name "ZZ.15.021") (class "Default")
      (node (ref "U$3") (pin "P$55") (pinfunction "B25_P$55") (pintype "bidirectional"))
    )
    (net (code "2916") (name "ZZ.15.022") (class "Default")
      (node (ref "U$3") (pin "P$85") (pinfunction "C25_P$85") (pintype "bidirectional"))
    )
    (net (code "2917") (name "ZZ.15.023") (class "Default")
      (node (ref "U$3") (pin "P$115") (pinfunction "D25_P$115") (pintype "bidirectional"))
    )
    (net (code "2918") (name "ZZ.15.024") (class "Default")
      (node (ref "U$3") (pin "P$177") (pinfunction "F27_P$177") (pintype "bidirectional"))
    )
    (net (code "2919") (name "ZZ.15.025") (class "Default")
      (node (ref "U$3") (pin "P$146") (pinfunction "E26_P$146") (pintype "bidirectional"))
    )
    (net (code "2920") (name "ZZ.15.026") (class "Default")
      (node (ref "U$3") (pin "P$54") (pinfunction "B24_P$54") (pintype "bidirectional"))
    )
    (net (code "2921") (name "ZZ.15.027") (class "Default")
      (node (ref "U$3") (pin "P$84") (pinfunction "C24_P$84") (pintype "bidirectional"))
    )
    (net (code "2922") (name "ZZ.15.028") (class "Default")
      (node (ref "U$3") (pin "P$114") (pinfunction "D24_P$114") (pintype "bidirectional"))
    )
    (net (code "2923") (name "ZZ.15.029") (class "Default")
      (node (ref "U$3") (pin "P$147") (pinfunction "E27_P$147") (pintype "bidirectional"))
    )
    (net (code "2924") (name "ZZ.15.030") (class "Default")
      (node (ref "U$3") (pin "P$176") (pinfunction "F26_P$176") (pintype "bidirectional"))
    )
    (net (code "2925") (name "ZZ.15.031") (class "Default")
      (node (ref "U$3") (pin "P$174") (pinfunction "F24_P$174") (pintype "bidirectional"))
    )
    (net (code "2926") (name "ZZ.15.032") (class "Default")
      (node (ref "U$5") (pin "P$56") (pinfunction "B26_P$56") (pintype "bidirectional"))
    )
    (net (code "2927") (name "ZZ.15.033") (class "Default")
      (node (ref "U$5") (pin "P$86") (pinfunction "C26_P$86") (pintype "bidirectional"))
    )
    (net (code "2928") (name "ZZ.15.034") (class "Default")
      (node (ref "U$5") (pin "P$116") (pinfunction "D26_P$116") (pintype "bidirectional"))
    )
    (net (code "2929") (name "ZZ.15.035") (class "Default")
      (node (ref "U$5") (pin "P$148") (pinfunction "E28_P$148") (pintype "bidirectional"))
    )
    (net (code "2930") (name "ZZ.15.036") (class "Default")
      (node (ref "U$5") (pin "P$175") (pinfunction "F25_P$175") (pintype "bidirectional"))
    )
    (net (code "2931") (name "ZZ.15.037") (class "Default")
      (node (ref "U$5") (pin "P$55") (pinfunction "B25_P$55") (pintype "bidirectional"))
    )
    (net (code "2932") (name "ZZ.15.038") (class "Default")
      (node (ref "U$5") (pin "P$85") (pinfunction "C25_P$85") (pintype "bidirectional"))
    )
    (net (code "2933") (name "ZZ.15.039") (class "Default")
      (node (ref "U$5") (pin "P$115") (pinfunction "D25_P$115") (pintype "bidirectional"))
    )
    (net (code "2934") (name "ZZ.15.040") (class "Default")
      (node (ref "U$5") (pin "P$177") (pinfunction "F27_P$177") (pintype "bidirectional"))
    )
    (net (code "2935") (name "ZZ.15.041") (class "Default")
      (node (ref "U$5") (pin "P$146") (pinfunction "E26_P$146") (pintype "bidirectional"))
    )
    (net (code "2936") (name "ZZ.15.042") (class "Default")
      (node (ref "U$5") (pin "P$54") (pinfunction "B24_P$54") (pintype "bidirectional"))
    )
    (net (code "2937") (name "ZZ.15.043") (class "Default")
      (node (ref "U$5") (pin "P$84") (pinfunction "C24_P$84") (pintype "bidirectional"))
    )
    (net (code "2938") (name "ZZ.15.044") (class "Default")
      (node (ref "U$5") (pin "P$114") (pinfunction "D24_P$114") (pintype "bidirectional"))
    )
    (net (code "2939") (name "ZZ.15.045") (class "Default")
      (node (ref "U$5") (pin "P$147") (pinfunction "E27_P$147") (pintype "bidirectional"))
    )
    (net (code "2940") (name "ZZ.15.046") (class "Default")
      (node (ref "U$5") (pin "P$176") (pinfunction "F26_P$176") (pintype "bidirectional"))
    )
    (net (code "2941") (name "ZZ.15.047") (class "Default")
      (node (ref "U$5") (pin "P$174") (pinfunction "F24_P$174") (pintype "bidirectional"))
    )
    (net (code "2942") (name "ZZ.15.048") (class "Default")
      (node (ref "U$7") (pin "P$56") (pinfunction "B26_P$56") (pintype "bidirectional"))
    )
    (net (code "2943") (name "ZZ.15.049") (class "Default")
      (node (ref "U$7") (pin "P$86") (pinfunction "C26_P$86") (pintype "bidirectional"))
    )
    (net (code "2944") (name "ZZ.15.050") (class "Default")
      (node (ref "U$7") (pin "P$116") (pinfunction "D26_P$116") (pintype "bidirectional"))
    )
    (net (code "2945") (name "ZZ.15.051") (class "Default")
      (node (ref "U$7") (pin "P$148") (pinfunction "E28_P$148") (pintype "bidirectional"))
    )
    (net (code "2946") (name "ZZ.15.052") (class "Default")
      (node (ref "U$7") (pin "P$175") (pinfunction "F25_P$175") (pintype "bidirectional"))
    )
    (net (code "2947") (name "ZZ.15.053") (class "Default")
      (node (ref "U$7") (pin "P$55") (pinfunction "B25_P$55") (pintype "bidirectional"))
    )
    (net (code "2948") (name "ZZ.15.054") (class "Default")
      (node (ref "U$7") (pin "P$85") (pinfunction "C25_P$85") (pintype "bidirectional"))
    )
    (net (code "2949") (name "ZZ.15.055") (class "Default")
      (node (ref "U$7") (pin "P$115") (pinfunction "D25_P$115") (pintype "bidirectional"))
    )
    (net (code "2950") (name "ZZ.15.056") (class "Default")
      (node (ref "U$7") (pin "P$54") (pinfunction "B24_P$54") (pintype "bidirectional"))
    )
    (net (code "2951") (name "ZZ.15.057") (class "Default")
      (node (ref "U$7") (pin "P$84") (pinfunction "C24_P$84") (pintype "bidirectional"))
    )
    (net (code "2952") (name "ZZ.15.058") (class "Default")
      (node (ref "U$7") (pin "P$114") (pinfunction "D24_P$114") (pintype "bidirectional"))
    )
    (net (code "2953") (name "ZZ.15.059") (class "Default")
      (node (ref "U$7") (pin "P$147") (pinfunction "E27_P$147") (pintype "bidirectional"))
    )
    (net (code "2954") (name "ZZ.15.060") (class "Default")
      (node (ref "U$7") (pin "P$176") (pinfunction "F26_P$176") (pintype "bidirectional"))
    )
    (net (code "2955") (name "ZZ.15.061") (class "Default")
      (node (ref "U$7") (pin "P$174") (pinfunction "F24_P$174") (pintype "bidirectional"))
    )
    (net (code "2956") (name "ZZ.15.062") (class "Default")
      (node (ref "U$7") (pin "P$177") (pinfunction "F27_P$177") (pintype "bidirectional"))
    )
    (net (code "2957") (name "ZZ.15.063") (class "Default")
      (node (ref "U$7") (pin "P$146") (pinfunction "E26_P$146") (pintype "bidirectional"))
    )
    (net (code "2958") (name "ZZ.15.064") (class "Default")
      (node (ref "U$9") (pin "P$56") (pinfunction "B26_P$56") (pintype "bidirectional"))
    )
    (net (code "2959") (name "ZZ.15.065") (class "Default")
      (node (ref "U$9") (pin "P$86") (pinfunction "C26_P$86") (pintype "bidirectional"))
    )
    (net (code "2960") (name "ZZ.15.066") (class "Default")
      (node (ref "U$9") (pin "P$116") (pinfunction "D26_P$116") (pintype "bidirectional"))
    )
    (net (code "2961") (name "ZZ.15.067") (class "Default")
      (node (ref "U$9") (pin "P$55") (pinfunction "B25_P$55") (pintype "bidirectional"))
    )
    (net (code "2962") (name "ZZ.15.068") (class "Default")
      (node (ref "U$9") (pin "P$85") (pinfunction "C25_P$85") (pintype "bidirectional"))
    )
    (net (code "2963") (name "ZZ.15.069") (class "Default")
      (node (ref "U$9") (pin "P$115") (pinfunction "D25_P$115") (pintype "bidirectional"))
    )
    (net (code "2964") (name "ZZ.15.070") (class "Default")
      (node (ref "U$9") (pin "P$54") (pinfunction "B24_P$54") (pintype "bidirectional"))
    )
    (net (code "2965") (name "ZZ.15.071") (class "Default")
      (node (ref "U$9") (pin "P$84") (pinfunction "C24_P$84") (pintype "bidirectional"))
    )
    (net (code "2966") (name "ZZ.15.072") (class "Default")
      (node (ref "U$9") (pin "P$114") (pinfunction "D24_P$114") (pintype "bidirectional"))
    )
    (net (code "2967") (name "ZZ.15.073") (class "Default")
      (node (ref "U$9") (pin "P$147") (pinfunction "E27_P$147") (pintype "bidirectional"))
    )
    (net (code "2968") (name "ZZ.15.074") (class "Default")
      (node (ref "U$9") (pin "P$176") (pinfunction "F26_P$176") (pintype "bidirectional"))
    )
    (net (code "2969") (name "ZZ.15.075") (class "Default")
      (node (ref "U$9") (pin "P$174") (pinfunction "F24_P$174") (pintype "bidirectional"))
    )
    (net (code "2970") (name "ZZ.15.076") (class "Default")
      (node (ref "U$9") (pin "P$177") (pinfunction "F27_P$177") (pintype "bidirectional"))
    )
    (net (code "2971") (name "ZZ.15.077") (class "Default")
      (node (ref "U$9") (pin "P$146") (pinfunction "E26_P$146") (pintype "bidirectional"))
    )
    (net (code "2972") (name "ZZ.15.078") (class "Default")
      (node (ref "U$9") (pin "P$148") (pinfunction "E28_P$148") (pintype "bidirectional"))
    )
    (net (code "2973") (name "ZZ.15.079") (class "Default")
      (node (ref "U$9") (pin "P$175") (pinfunction "F25_P$175") (pintype "bidirectional"))
    )
    (net (code "2974") (name "ZZ.15.080") (class "Default")
      (node (ref "U$11") (pin "P$55") (pinfunction "B25_P$55") (pintype "bidirectional"))
    )
    (net (code "2975") (name "ZZ.15.081") (class "Default")
      (node (ref "U$11") (pin "P$85") (pinfunction "C25_P$85") (pintype "bidirectional"))
    )
    (net (code "2976") (name "ZZ.15.082") (class "Default")
      (node (ref "U$11") (pin "P$115") (pinfunction "D25_P$115") (pintype "bidirectional"))
    )
    (net (code "2977") (name "ZZ.15.083") (class "Default")
      (node (ref "U$11") (pin "P$54") (pinfunction "B24_P$54") (pintype "bidirectional"))
    )
    (net (code "2978") (name "ZZ.15.084") (class "Default")
      (node (ref "U$11") (pin "P$84") (pinfunction "C24_P$84") (pintype "bidirectional"))
    )
    (net (code "2979") (name "ZZ.15.085") (class "Default")
      (node (ref "U$11") (pin "P$114") (pinfunction "D24_P$114") (pintype "bidirectional"))
    )
    (net (code "2980") (name "ZZ.15.086") (class "Default")
      (node (ref "U$11") (pin "P$147") (pinfunction "E27_P$147") (pintype "bidirectional"))
    )
    (net (code "2981") (name "ZZ.15.087") (class "Default")
      (node (ref "U$11") (pin "P$176") (pinfunction "F26_P$176") (pintype "bidirectional"))
    )
    (net (code "2982") (name "ZZ.15.088") (class "Default")
      (node (ref "U$11") (pin "P$174") (pinfunction "F24_P$174") (pintype "bidirectional"))
    )
    (net (code "2983") (name "ZZ.15.089") (class "Default")
      (node (ref "U$11") (pin "P$177") (pinfunction "F27_P$177") (pintype "bidirectional"))
    )
    (net (code "2984") (name "ZZ.15.090") (class "Default")
      (node (ref "U$11") (pin "P$146") (pinfunction "E26_P$146") (pintype "bidirectional"))
    )
    (net (code "2985") (name "ZZ.15.091") (class "Default")
      (node (ref "U$11") (pin "P$56") (pinfunction "B26_P$56") (pintype "bidirectional"))
    )
    (net (code "2986") (name "ZZ.15.092") (class "Default")
      (node (ref "U$11") (pin "P$86") (pinfunction "C26_P$86") (pintype "bidirectional"))
    )
    (net (code "2987") (name "ZZ.15.093") (class "Default")
      (node (ref "U$11") (pin "P$116") (pinfunction "D26_P$116") (pintype "bidirectional"))
    )
    (net (code "2988") (name "ZZ.15.094") (class "Default")
      (node (ref "U$11") (pin "P$148") (pinfunction "E28_P$148") (pintype "bidirectional"))
    )
    (net (code "2989") (name "ZZ.15.095") (class "Default")
      (node (ref "U$11") (pin "P$175") (pinfunction "F25_P$175") (pintype "bidirectional"))
    )
    (net (code "2990") (name "ZZ.15.096") (class "Default")
      (node (ref "U$13") (pin "P$55") (pinfunction "B25_P$55") (pintype "bidirectional"))
    )
    (net (code "2991") (name "ZZ.15.097") (class "Default")
      (node (ref "U$13") (pin "P$54") (pinfunction "B24_P$54") (pintype "bidirectional"))
    )
    (net (code "2992") (name "ZZ.15.098") (class "Default")
      (node (ref "U$13") (pin "P$84") (pinfunction "C24_P$84") (pintype "bidirectional"))
    )
    (net (code "2993") (name "ZZ.15.099") (class "Default")
      (node (ref "U$13") (pin "P$114") (pinfunction "D24_P$114") (pintype "bidirectional"))
    )
    (net (code "2994") (name "ZZ.15.100") (class "Default")
      (node (ref "U$13") (pin "P$147") (pinfunction "E27_P$147") (pintype "bidirectional"))
    )
    (net (code "2995") (name "ZZ.15.101") (class "Default")
      (node (ref "U$13") (pin "P$176") (pinfunction "F26_P$176") (pintype "bidirectional"))
    )
    (net (code "2996") (name "ZZ.15.102") (class "Default")
      (node (ref "U$13") (pin "P$174") (pinfunction "F24_P$174") (pintype "bidirectional"))
    )
    (net (code "2997") (name "ZZ.15.103") (class "Default")
      (node (ref "U$13") (pin "P$85") (pinfunction "C25_P$85") (pintype "bidirectional"))
    )
    (net (code "2998") (name "ZZ.15.104") (class "Default")
      (node (ref "U$13") (pin "P$115") (pinfunction "D25_P$115") (pintype "bidirectional"))
    )
    (net (code "2999") (name "ZZ.15.105") (class "Default")
      (node (ref "U$13") (pin "P$177") (pinfunction "F27_P$177") (pintype "bidirectional"))
    )
    (net (code "3000") (name "ZZ.15.106") (class "Default")
      (node (ref "U$13") (pin "P$146") (pinfunction "E26_P$146") (pintype "bidirectional"))
    )
    (net (code "3001") (name "ZZ.15.107") (class "Default")
      (node (ref "U$13") (pin "P$56") (pinfunction "B26_P$56") (pintype "bidirectional"))
    )
    (net (code "3002") (name "ZZ.15.108") (class "Default")
      (node (ref "U$13") (pin "P$86") (pinfunction "C26_P$86") (pintype "bidirectional"))
    )
    (net (code "3003") (name "ZZ.15.109") (class "Default")
      (node (ref "U$13") (pin "P$116") (pinfunction "D26_P$116") (pintype "bidirectional"))
    )
    (net (code "3004") (name "ZZ.15.110") (class "Default")
      (node (ref "U$13") (pin "P$148") (pinfunction "E28_P$148") (pintype "bidirectional"))
    )
    (net (code "3005") (name "ZZ.15.111") (class "Default")
      (node (ref "U$13") (pin "P$175") (pinfunction "F25_P$175") (pintype "bidirectional"))
    )
    (net (code "3006") (name "ZZ.15.112") (class "Default")
      (node (ref "U$15") (pin "P$54") (pinfunction "B24_P$54") (pintype "bidirectional"))
    )
    (net (code "3007") (name "ZZ.15.113") (class "Default")
      (node (ref "U$15") (pin "P$84") (pinfunction "C24_P$84") (pintype "bidirectional"))
    )
    (net (code "3008") (name "ZZ.15.114") (class "Default")
      (node (ref "U$15") (pin "P$114") (pinfunction "D24_P$114") (pintype "bidirectional"))
    )
    (net (code "3009") (name "ZZ.15.115") (class "Default")
      (node (ref "U$15") (pin "P$147") (pinfunction "E27_P$147") (pintype "bidirectional"))
    )
    (net (code "3010") (name "ZZ.15.116") (class "Default")
      (node (ref "U$15") (pin "P$176") (pinfunction "F26_P$176") (pintype "bidirectional"))
    )
    (net (code "3011") (name "ZZ.15.117") (class "Default")
      (node (ref "U$15") (pin "P$174") (pinfunction "F24_P$174") (pintype "bidirectional"))
    )
    (net (code "3012") (name "ZZ.15.118") (class "Default")
      (node (ref "U$15") (pin "P$55") (pinfunction "B25_P$55") (pintype "bidirectional"))
    )
    (net (code "3013") (name "ZZ.15.119") (class "Default")
      (node (ref "U$15") (pin "P$85") (pinfunction "C25_P$85") (pintype "bidirectional"))
    )
    (net (code "3014") (name "ZZ.15.120") (class "Default")
      (node (ref "U$15") (pin "P$115") (pinfunction "D25_P$115") (pintype "bidirectional"))
    )
    (net (code "3015") (name "ZZ.15.121") (class "Default")
      (node (ref "U$15") (pin "P$177") (pinfunction "F27_P$177") (pintype "bidirectional"))
    )
    (net (code "3016") (name "ZZ.15.122") (class "Default")
      (node (ref "U$15") (pin "P$146") (pinfunction "E26_P$146") (pintype "bidirectional"))
    )
    (net (code "3017") (name "ZZ.15.123") (class "Default")
      (node (ref "U$15") (pin "P$56") (pinfunction "B26_P$56") (pintype "bidirectional"))
    )
    (net (code "3018") (name "ZZ.15.124") (class "Default")
      (node (ref "U$15") (pin "P$86") (pinfunction "C26_P$86") (pintype "bidirectional"))
    )
    (net (code "3019") (name "ZZ.15.125") (class "Default")
      (node (ref "U$15") (pin "P$116") (pinfunction "D26_P$116") (pintype "bidirectional"))
    )
    (net (code "3020") (name "ZZ.15.126") (class "Default")
      (node (ref "U$15") (pin "P$148") (pinfunction "E28_P$148") (pintype "bidirectional"))
    )
    (net (code "3021") (name "ZZ.15.127") (class "Default")
      (node (ref "U$15") (pin "P$175") (pinfunction "F25_P$175") (pintype "bidirectional"))
    )
    (net (code "3022") (name "ZZ.15.128") (class "Default")
      (node (ref "U$17") (pin "P$54") (pinfunction "B24_P$54") (pintype "bidirectional"))
    )
    (net (code "3023") (name "ZZ.15.129") (class "Default")
      (node (ref "U$17") (pin "P$84") (pinfunction "C24_P$84") (pintype "bidirectional"))
    )
    (net (code "3024") (name "ZZ.15.130") (class "Default")
      (node (ref "U$17") (pin "P$114") (pinfunction "D24_P$114") (pintype "bidirectional"))
    )
    (net (code "3025") (name "ZZ.15.131") (class "Default")
      (node (ref "U$17") (pin "P$147") (pinfunction "E27_P$147") (pintype "bidirectional"))
    )
    (net (code "3026") (name "ZZ.15.132") (class "Default")
      (node (ref "U$17") (pin "P$176") (pinfunction "F26_P$176") (pintype "bidirectional"))
    )
    (net (code "3027") (name "ZZ.15.133") (class "Default")
      (node (ref "U$17") (pin "P$174") (pinfunction "F24_P$174") (pintype "bidirectional"))
    )
    (net (code "3028") (name "ZZ.15.134") (class "Default")
      (node (ref "U$17") (pin "P$55") (pinfunction "B25_P$55") (pintype "bidirectional"))
    )
    (net (code "3029") (name "ZZ.15.135") (class "Default")
      (node (ref "U$17") (pin "P$85") (pinfunction "C25_P$85") (pintype "bidirectional"))
    )
    (net (code "3030") (name "ZZ.15.136") (class "Default")
      (node (ref "U$17") (pin "P$115") (pinfunction "D25_P$115") (pintype "bidirectional"))
    )
    (net (code "3031") (name "ZZ.15.137") (class "Default")
      (node (ref "U$17") (pin "P$177") (pinfunction "F27_P$177") (pintype "bidirectional"))
    )
    (net (code "3032") (name "ZZ.15.138") (class "Default")
      (node (ref "U$17") (pin "P$146") (pinfunction "E26_P$146") (pintype "bidirectional"))
    )
    (net (code "3033") (name "ZZ.15.139") (class "Default")
      (node (ref "U$17") (pin "P$56") (pinfunction "B26_P$56") (pintype "bidirectional"))
    )
    (net (code "3034") (name "ZZ.15.140") (class "Default")
      (node (ref "U$17") (pin "P$86") (pinfunction "C26_P$86") (pintype "bidirectional"))
    )
    (net (code "3035") (name "ZZ.15.141") (class "Default")
      (node (ref "U$17") (pin "P$116") (pinfunction "D26_P$116") (pintype "bidirectional"))
    )
    (net (code "3036") (name "ZZ.15.142") (class "Default")
      (node (ref "U$17") (pin "P$148") (pinfunction "E28_P$148") (pintype "bidirectional"))
    )
    (net (code "3037") (name "ZZ.15.143") (class "Default")
      (node (ref "U$17") (pin "P$175") (pinfunction "F25_P$175") (pintype "bidirectional"))
    )
    (net (code "3038") (name "ZZ.15.144") (class "Default")
      (node (ref "U$19") (pin "P$54") (pinfunction "B24_P$54") (pintype "bidirectional"))
    )
    (net (code "3039") (name "ZZ.15.145") (class "Default")
      (node (ref "U$19") (pin "P$84") (pinfunction "C24_P$84") (pintype "bidirectional"))
    )
    (net (code "3040") (name "ZZ.15.146") (class "Default")
      (node (ref "U$19") (pin "P$114") (pinfunction "D24_P$114") (pintype "bidirectional"))
    )
    (net (code "3041") (name "ZZ.15.147") (class "Default")
      (node (ref "U$19") (pin "P$147") (pinfunction "E27_P$147") (pintype "bidirectional"))
    )
    (net (code "3042") (name "ZZ.15.148") (class "Default")
      (node (ref "U$19") (pin "P$176") (pinfunction "F26_P$176") (pintype "bidirectional"))
    )
    (net (code "3043") (name "ZZ.15.149") (class "Default")
      (node (ref "U$19") (pin "P$174") (pinfunction "F24_P$174") (pintype "bidirectional"))
    )
    (net (code "3044") (name "ZZ.15.150") (class "Default")
      (node (ref "U$19") (pin "P$55") (pinfunction "B25_P$55") (pintype "bidirectional"))
    )
    (net (code "3045") (name "ZZ.15.151") (class "Default")
      (node (ref "U$19") (pin "P$85") (pinfunction "C25_P$85") (pintype "bidirectional"))
    )
    (net (code "3046") (name "ZZ.15.152") (class "Default")
      (node (ref "U$19") (pin "P$115") (pinfunction "D25_P$115") (pintype "bidirectional"))
    )
    (net (code "3047") (name "ZZ.15.153") (class "Default")
      (node (ref "U$19") (pin "P$177") (pinfunction "F27_P$177") (pintype "bidirectional"))
    )
    (net (code "3048") (name "ZZ.15.154") (class "Default")
      (node (ref "U$19") (pin "P$146") (pinfunction "E26_P$146") (pintype "bidirectional"))
    )
    (net (code "3049") (name "ZZ.15.155") (class "Default")
      (node (ref "U$19") (pin "P$56") (pinfunction "B26_P$56") (pintype "bidirectional"))
    )
    (net (code "3050") (name "ZZ.15.156") (class "Default")
      (node (ref "U$19") (pin "P$86") (pinfunction "C26_P$86") (pintype "bidirectional"))
    )
    (net (code "3051") (name "ZZ.15.157") (class "Default")
      (node (ref "U$19") (pin "P$116") (pinfunction "D26_P$116") (pintype "bidirectional"))
    )
    (net (code "3052") (name "ZZ.15.158") (class "Default")
      (node (ref "U$19") (pin "P$148") (pinfunction "E28_P$148") (pintype "bidirectional"))
    )
    (net (code "3053") (name "ZZ.15.159") (class "Default")
      (node (ref "U$19") (pin "P$175") (pinfunction "F25_P$175") (pintype "bidirectional"))
    )
    (net (code "3054") (name "ZZ.15.160") (class "Default")
      (node (ref "U$21") (pin "P$54") (pinfunction "B24_P$54") (pintype "bidirectional"))
    )
    (net (code "3055") (name "ZZ.15.161") (class "Default")
      (node (ref "U$21") (pin "P$84") (pinfunction "C24_P$84") (pintype "bidirectional"))
    )
    (net (code "3056") (name "ZZ.15.162") (class "Default")
      (node (ref "U$21") (pin "P$114") (pinfunction "D24_P$114") (pintype "bidirectional"))
    )
    (net (code "3057") (name "ZZ.15.163") (class "Default")
      (node (ref "U$21") (pin "P$147") (pinfunction "E27_P$147") (pintype "bidirectional"))
    )
    (net (code "3058") (name "ZZ.15.164") (class "Default")
      (node (ref "U$21") (pin "P$176") (pinfunction "F26_P$176") (pintype "bidirectional"))
    )
    (net (code "3059") (name "ZZ.15.165") (class "Default")
      (node (ref "U$21") (pin "P$174") (pinfunction "F24_P$174") (pintype "bidirectional"))
    )
    (net (code "3060") (name "ZZ.15.166") (class "Default")
      (node (ref "U$21") (pin "P$55") (pinfunction "B25_P$55") (pintype "bidirectional"))
    )
    (net (code "3061") (name "ZZ.15.167") (class "Default")
      (node (ref "U$21") (pin "P$85") (pinfunction "C25_P$85") (pintype "bidirectional"))
    )
    (net (code "3062") (name "ZZ.15.168") (class "Default")
      (node (ref "U$21") (pin "P$115") (pinfunction "D25_P$115") (pintype "bidirectional"))
    )
    (net (code "3063") (name "ZZ.15.169") (class "Default")
      (node (ref "U$21") (pin "P$177") (pinfunction "F27_P$177") (pintype "bidirectional"))
    )
    (net (code "3064") (name "ZZ.15.170") (class "Default")
      (node (ref "U$21") (pin "P$146") (pinfunction "E26_P$146") (pintype "bidirectional"))
    )
    (net (code "3065") (name "ZZ.15.171") (class "Default")
      (node (ref "U$21") (pin "P$56") (pinfunction "B26_P$56") (pintype "bidirectional"))
    )
    (net (code "3066") (name "ZZ.15.172") (class "Default")
      (node (ref "U$21") (pin "P$86") (pinfunction "C26_P$86") (pintype "bidirectional"))
    )
    (net (code "3067") (name "ZZ.15.173") (class "Default")
      (node (ref "U$21") (pin "P$116") (pinfunction "D26_P$116") (pintype "bidirectional"))
    )
    (net (code "3068") (name "ZZ.15.174") (class "Default")
      (node (ref "U$21") (pin "P$148") (pinfunction "E28_P$148") (pintype "bidirectional"))
    )
    (net (code "3069") (name "ZZ.15.175") (class "Default")
      (node (ref "U$21") (pin "P$175") (pinfunction "F25_P$175") (pintype "bidirectional"))
    )
    (net (code "3070") (name "ZZ.15.176") (class "Default")
      (node (ref "U$23") (pin "P$54") (pinfunction "B24_P$54") (pintype "bidirectional"))
    )
    (net (code "3071") (name "ZZ.15.177") (class "Default")
      (node (ref "U$23") (pin "P$84") (pinfunction "C24_P$84") (pintype "bidirectional"))
    )
    (net (code "3072") (name "ZZ.15.178") (class "Default")
      (node (ref "U$23") (pin "P$114") (pinfunction "D24_P$114") (pintype "bidirectional"))
    )
    (net (code "3073") (name "ZZ.15.179") (class "Default")
      (node (ref "U$23") (pin "P$147") (pinfunction "E27_P$147") (pintype "bidirectional"))
    )
    (net (code "3074") (name "ZZ.15.180") (class "Default")
      (node (ref "U$23") (pin "P$176") (pinfunction "F26_P$176") (pintype "bidirectional"))
    )
    (net (code "3075") (name "ZZ.15.181") (class "Default")
      (node (ref "U$23") (pin "P$174") (pinfunction "F24_P$174") (pintype "bidirectional"))
    )
    (net (code "3076") (name "ZZ.15.182") (class "Default")
      (node (ref "U$23") (pin "P$55") (pinfunction "B25_P$55") (pintype "bidirectional"))
    )
    (net (code "3077") (name "ZZ.15.183") (class "Default")
      (node (ref "U$23") (pin "P$85") (pinfunction "C25_P$85") (pintype "bidirectional"))
    )
    (net (code "3078") (name "ZZ.15.184") (class "Default")
      (node (ref "U$23") (pin "P$115") (pinfunction "D25_P$115") (pintype "bidirectional"))
    )
    (net (code "3079") (name "ZZ.15.185") (class "Default")
      (node (ref "U$23") (pin "P$177") (pinfunction "F27_P$177") (pintype "bidirectional"))
    )
    (net (code "3080") (name "ZZ.15.186") (class "Default")
      (node (ref "U$23") (pin "P$146") (pinfunction "E26_P$146") (pintype "bidirectional"))
    )
    (net (code "3081") (name "ZZ.15.187") (class "Default")
      (node (ref "U$23") (pin "P$56") (pinfunction "B26_P$56") (pintype "bidirectional"))
    )
    (net (code "3082") (name "ZZ.15.188") (class "Default")
      (node (ref "U$23") (pin "P$86") (pinfunction "C26_P$86") (pintype "bidirectional"))
    )
    (net (code "3083") (name "ZZ.15.189") (class "Default")
      (node (ref "U$23") (pin "P$116") (pinfunction "D26_P$116") (pintype "bidirectional"))
    )
    (net (code "3084") (name "ZZ.15.190") (class "Default")
      (node (ref "U$23") (pin "P$148") (pinfunction "E28_P$148") (pintype "bidirectional"))
    )
    (net (code "3085") (name "ZZ.15.191") (class "Default")
      (node (ref "U$23") (pin "P$175") (pinfunction "F25_P$175") (pintype "bidirectional"))
    )
    (net (code "3086") (name "unconnected-(U$2-A30-PadP$30)") (class "Default")
      (node (ref "U$2") (pin "P$30") (pinfunction "A30_P$30") (pintype "bidirectional"))
    )
    (net (code "3087") (name "unconnected-(U$4-A30-PadP$30)") (class "Default")
      (node (ref "U$4") (pin "P$30") (pinfunction "A30_P$30") (pintype "bidirectional"))
    )
    (net (code "3088") (name "unconnected-(U$6-A30-PadP$30)") (class "Default")
      (node (ref "U$6") (pin "P$30") (pinfunction "A30_P$30") (pintype "bidirectional"))
    )
    (net (code "3089") (name "unconnected-(U$8-A30-PadP$30)") (class "Default")
      (node (ref "U$8") (pin "P$30") (pinfunction "A30_P$30") (pintype "bidirectional"))
    )
    (net (code "3090") (name "unconnected-(U$10-A30-PadP$30)") (class "Default")
      (node (ref "U$10") (pin "P$30") (pinfunction "A30_P$30") (pintype "bidirectional"))
    )
    (net (code "3091") (name "unconnected-(U$12-A30-PadP$30)") (class "Default")
      (node (ref "U$12") (pin "P$30") (pinfunction "A30_P$30") (pintype "bidirectional"))
    )
    (net (code "3092") (name "unconnected-(U$14-A30-PadP$30)") (class "Default")
      (node (ref "U$14") (pin "P$30") (pinfunction "A30_P$30") (pintype "bidirectional"))
    )
    (net (code "3093") (name "unconnected-(U$16-A30-PadP$30)") (class "Default")
      (node (ref "U$16") (pin "P$30") (pinfunction "A30_P$30") (pintype "bidirectional"))
    )
    (net (code "3094") (name "unconnected-(U$18-A30-PadP$30)") (class "Default")
      (node (ref "U$18") (pin "P$30") (pinfunction "A30_P$30") (pintype "bidirectional"))
    )
    (net (code "3095") (name "unconnected-(U$20-A30-PadP$30)") (class "Default")
      (node (ref "U$20") (pin "P$30") (pinfunction "A30_P$30") (pintype "bidirectional"))
    )
    (net (code "3096") (name "unconnected-(U$22-A30-PadP$30)") (class "Default")
      (node (ref "U$22") (pin "P$30") (pinfunction "A30_P$30") (pintype "bidirectional"))
    )
    (net (code "3097") (name "unconnected-(U$24-A30-PadP$30)") (class "Default")
      (node (ref "U$24") (pin "P$30") (pinfunction "A30_P$30") (pintype "bidirectional"))
    )
  )
)
